# Sheet1.net
KiCad netlist of a schematic drawn in Altium Designer
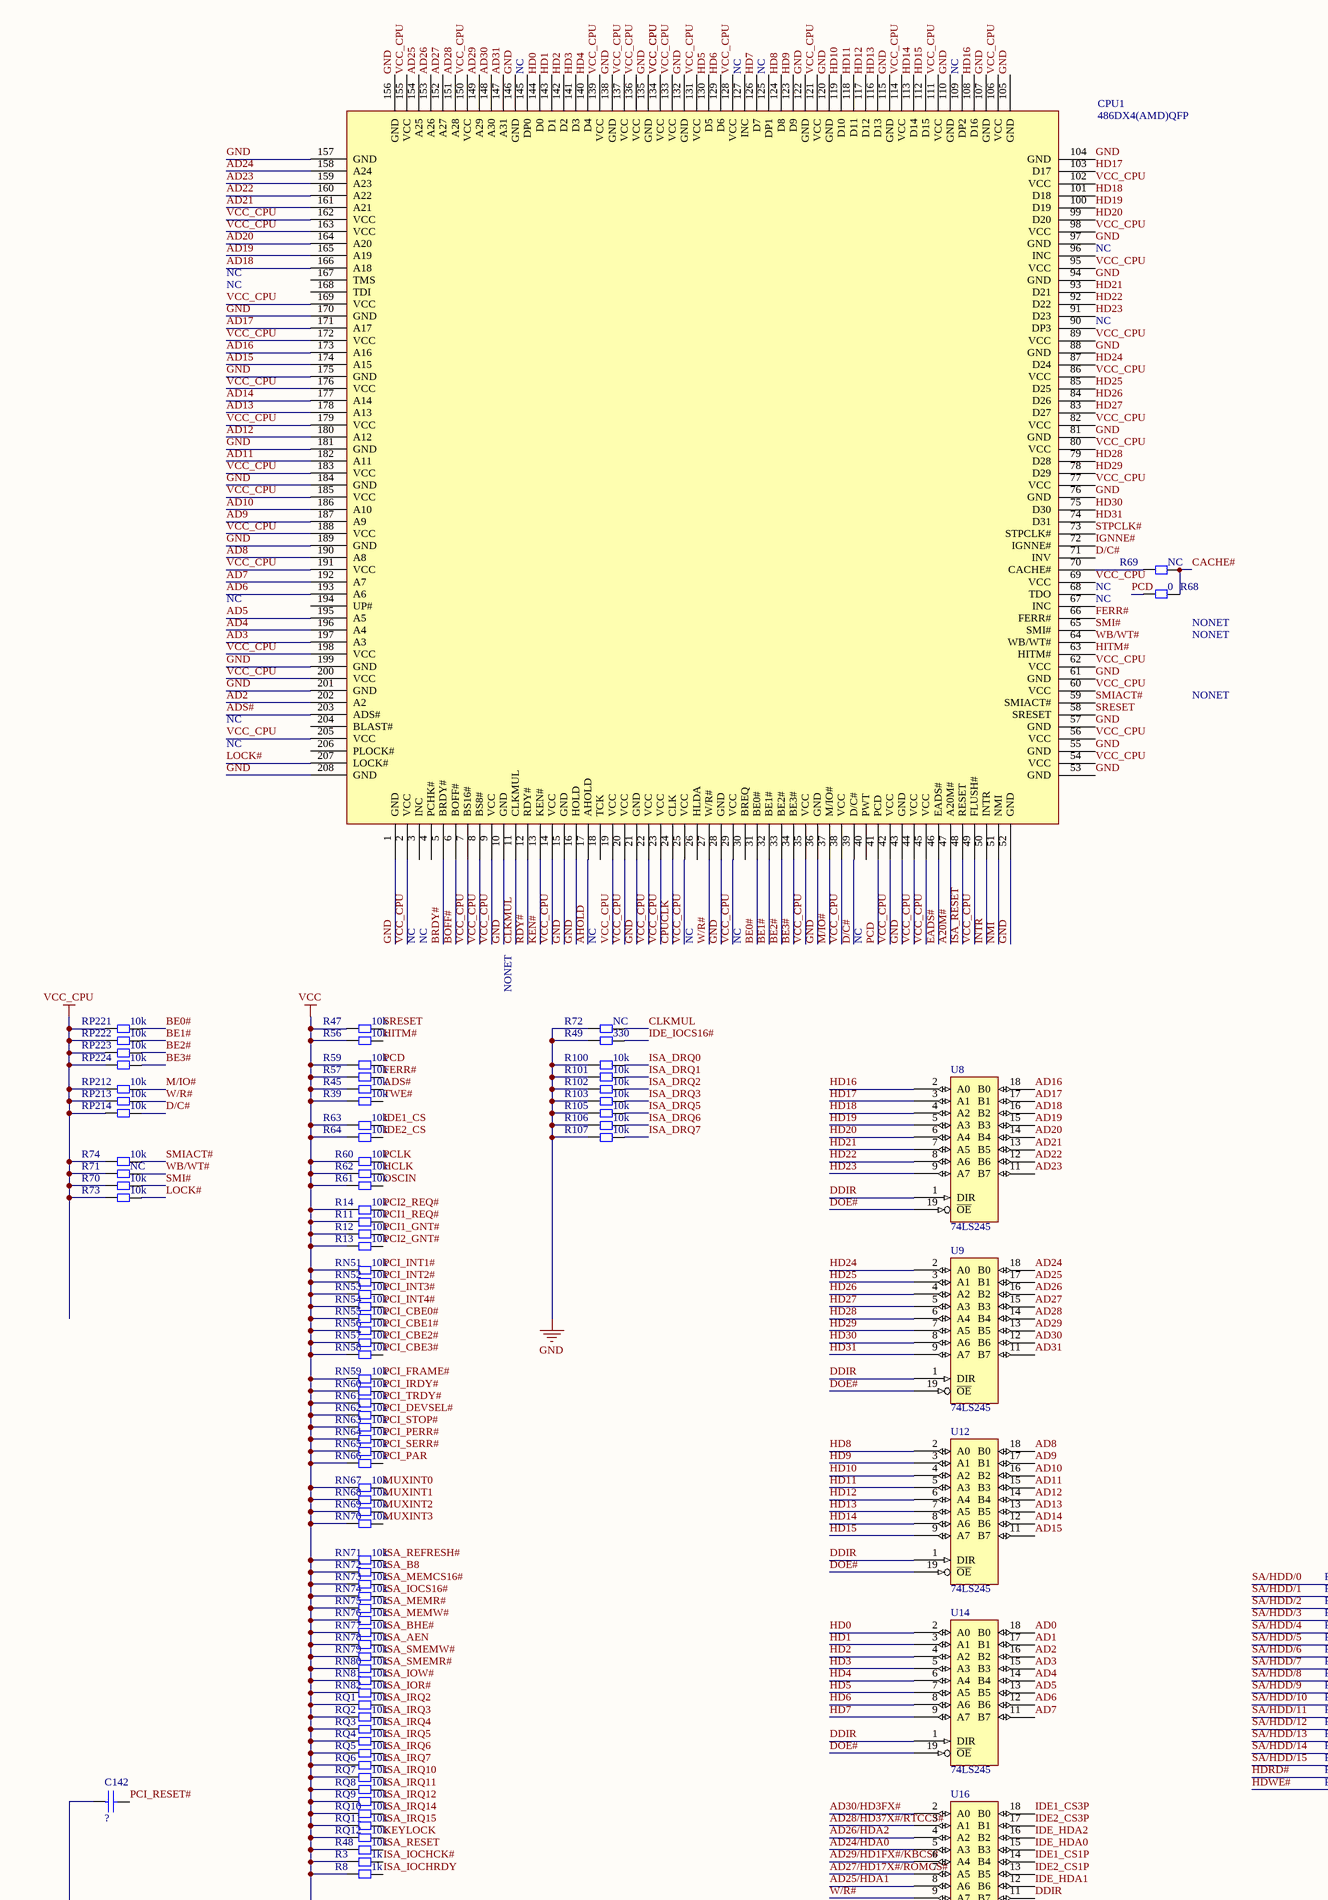
[diagram p0: Sheet1.SchDoc, top left]
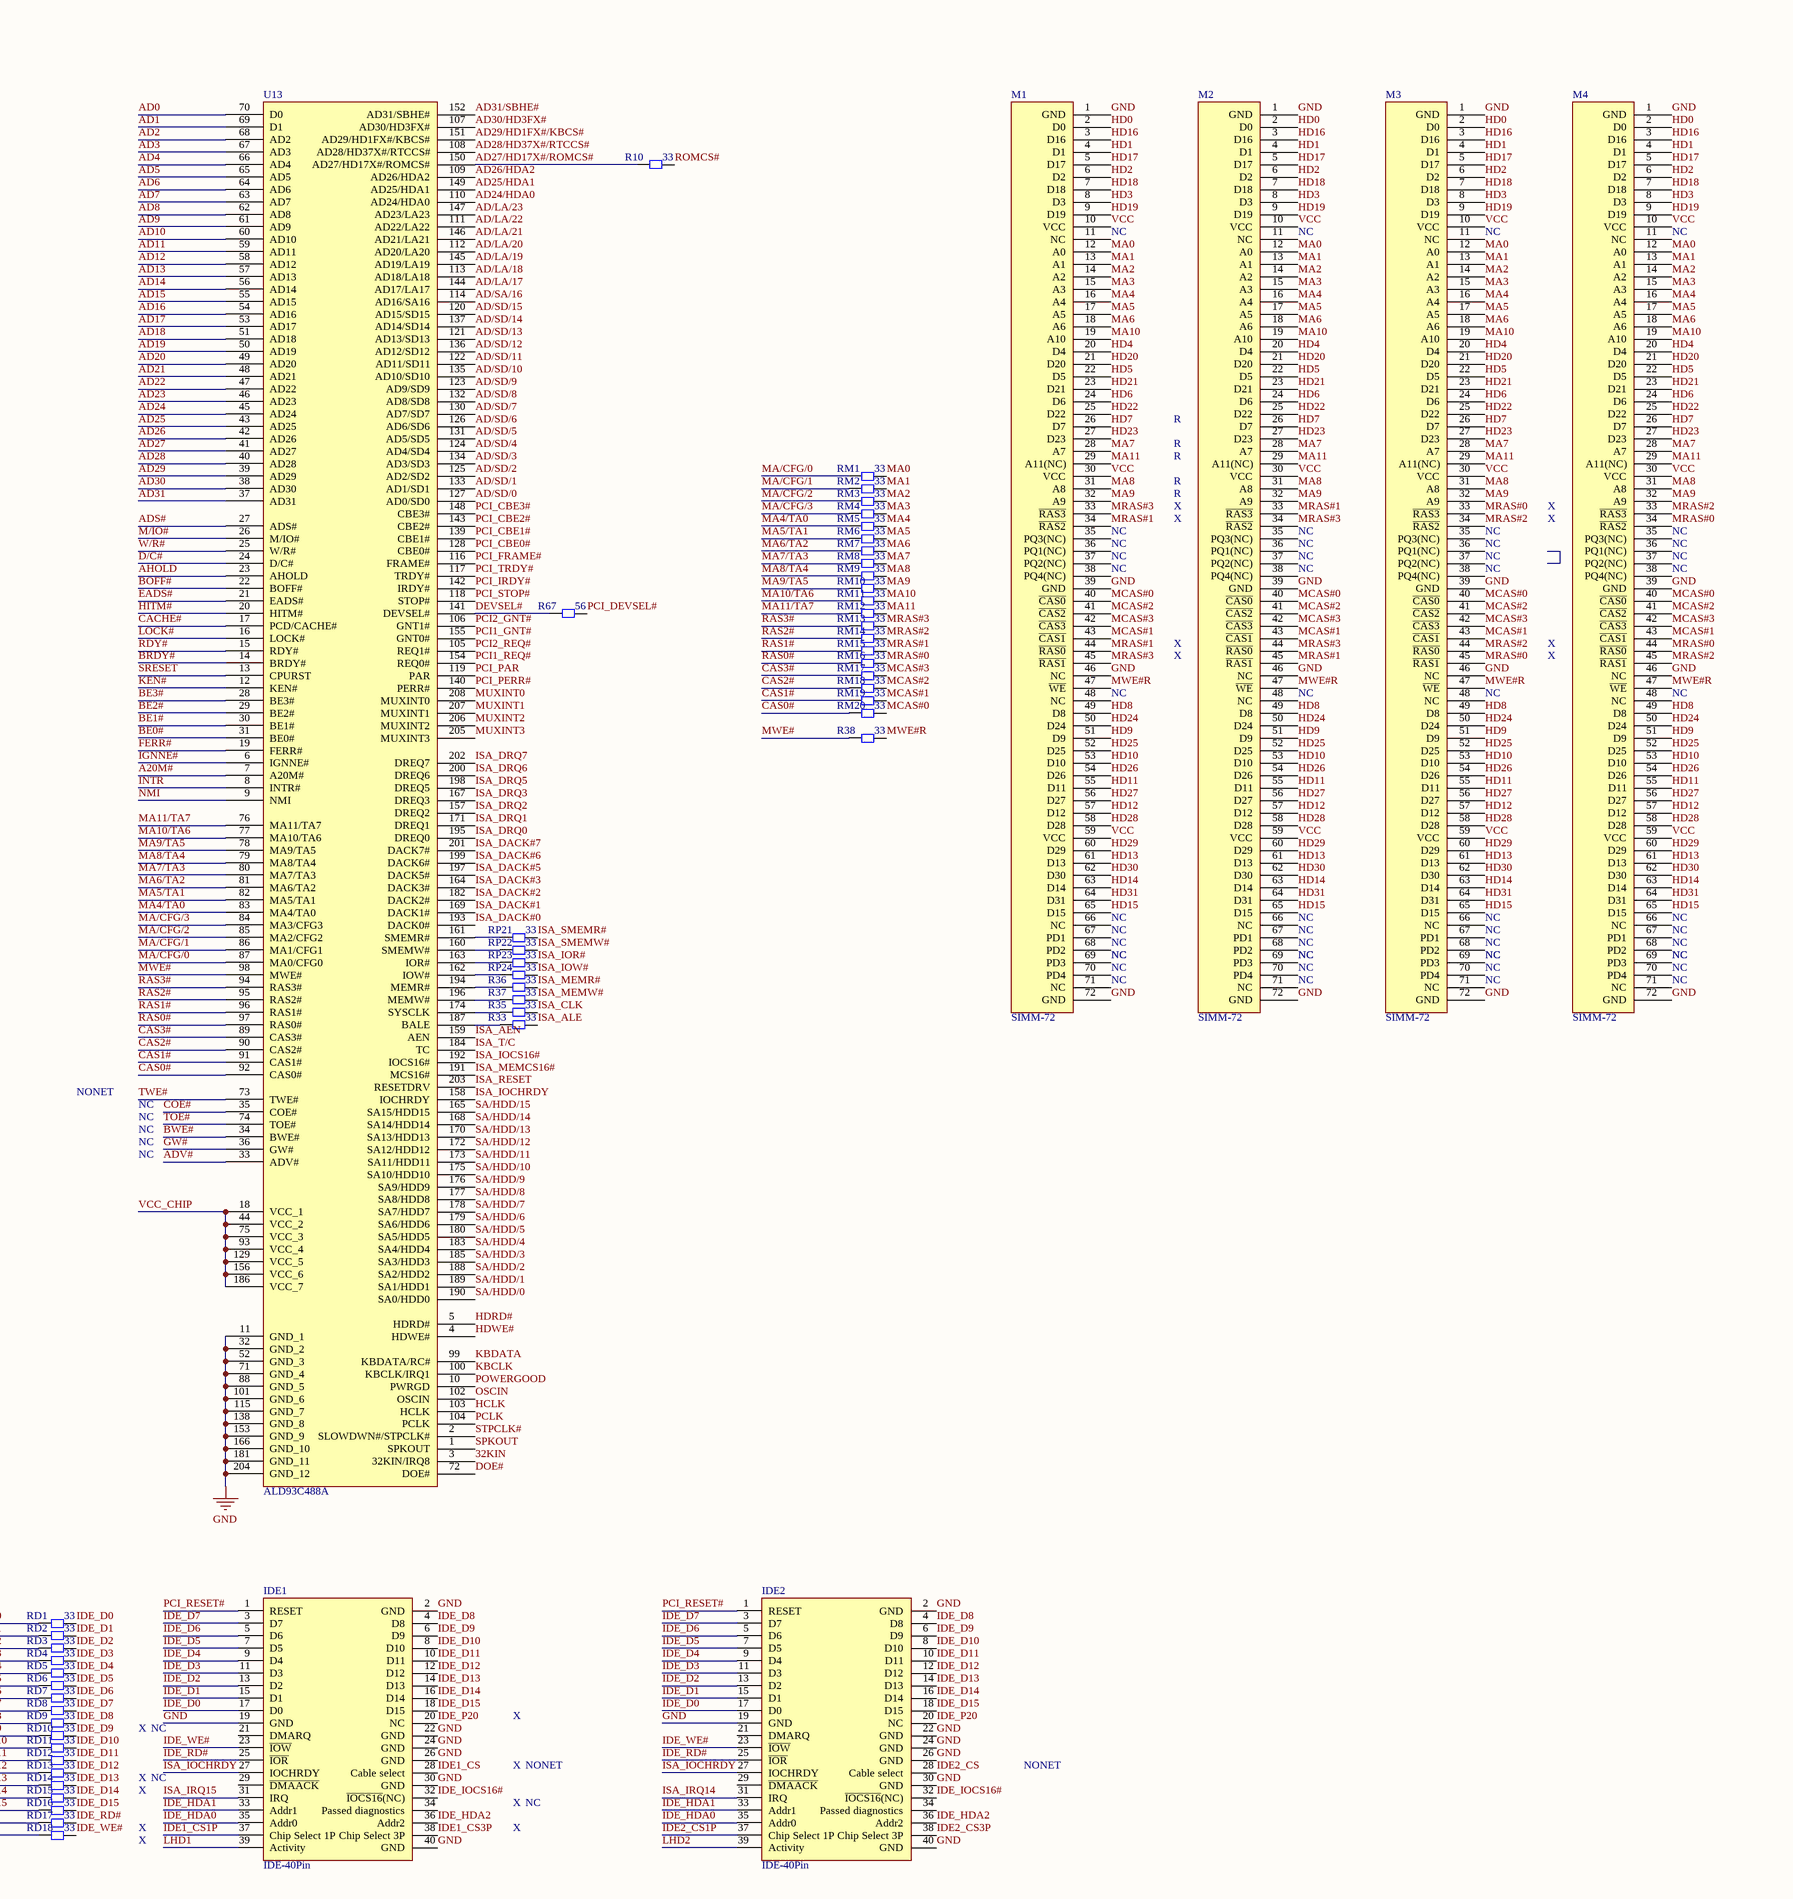
[diagram p1: Sheet1.SchDoc, top middle]
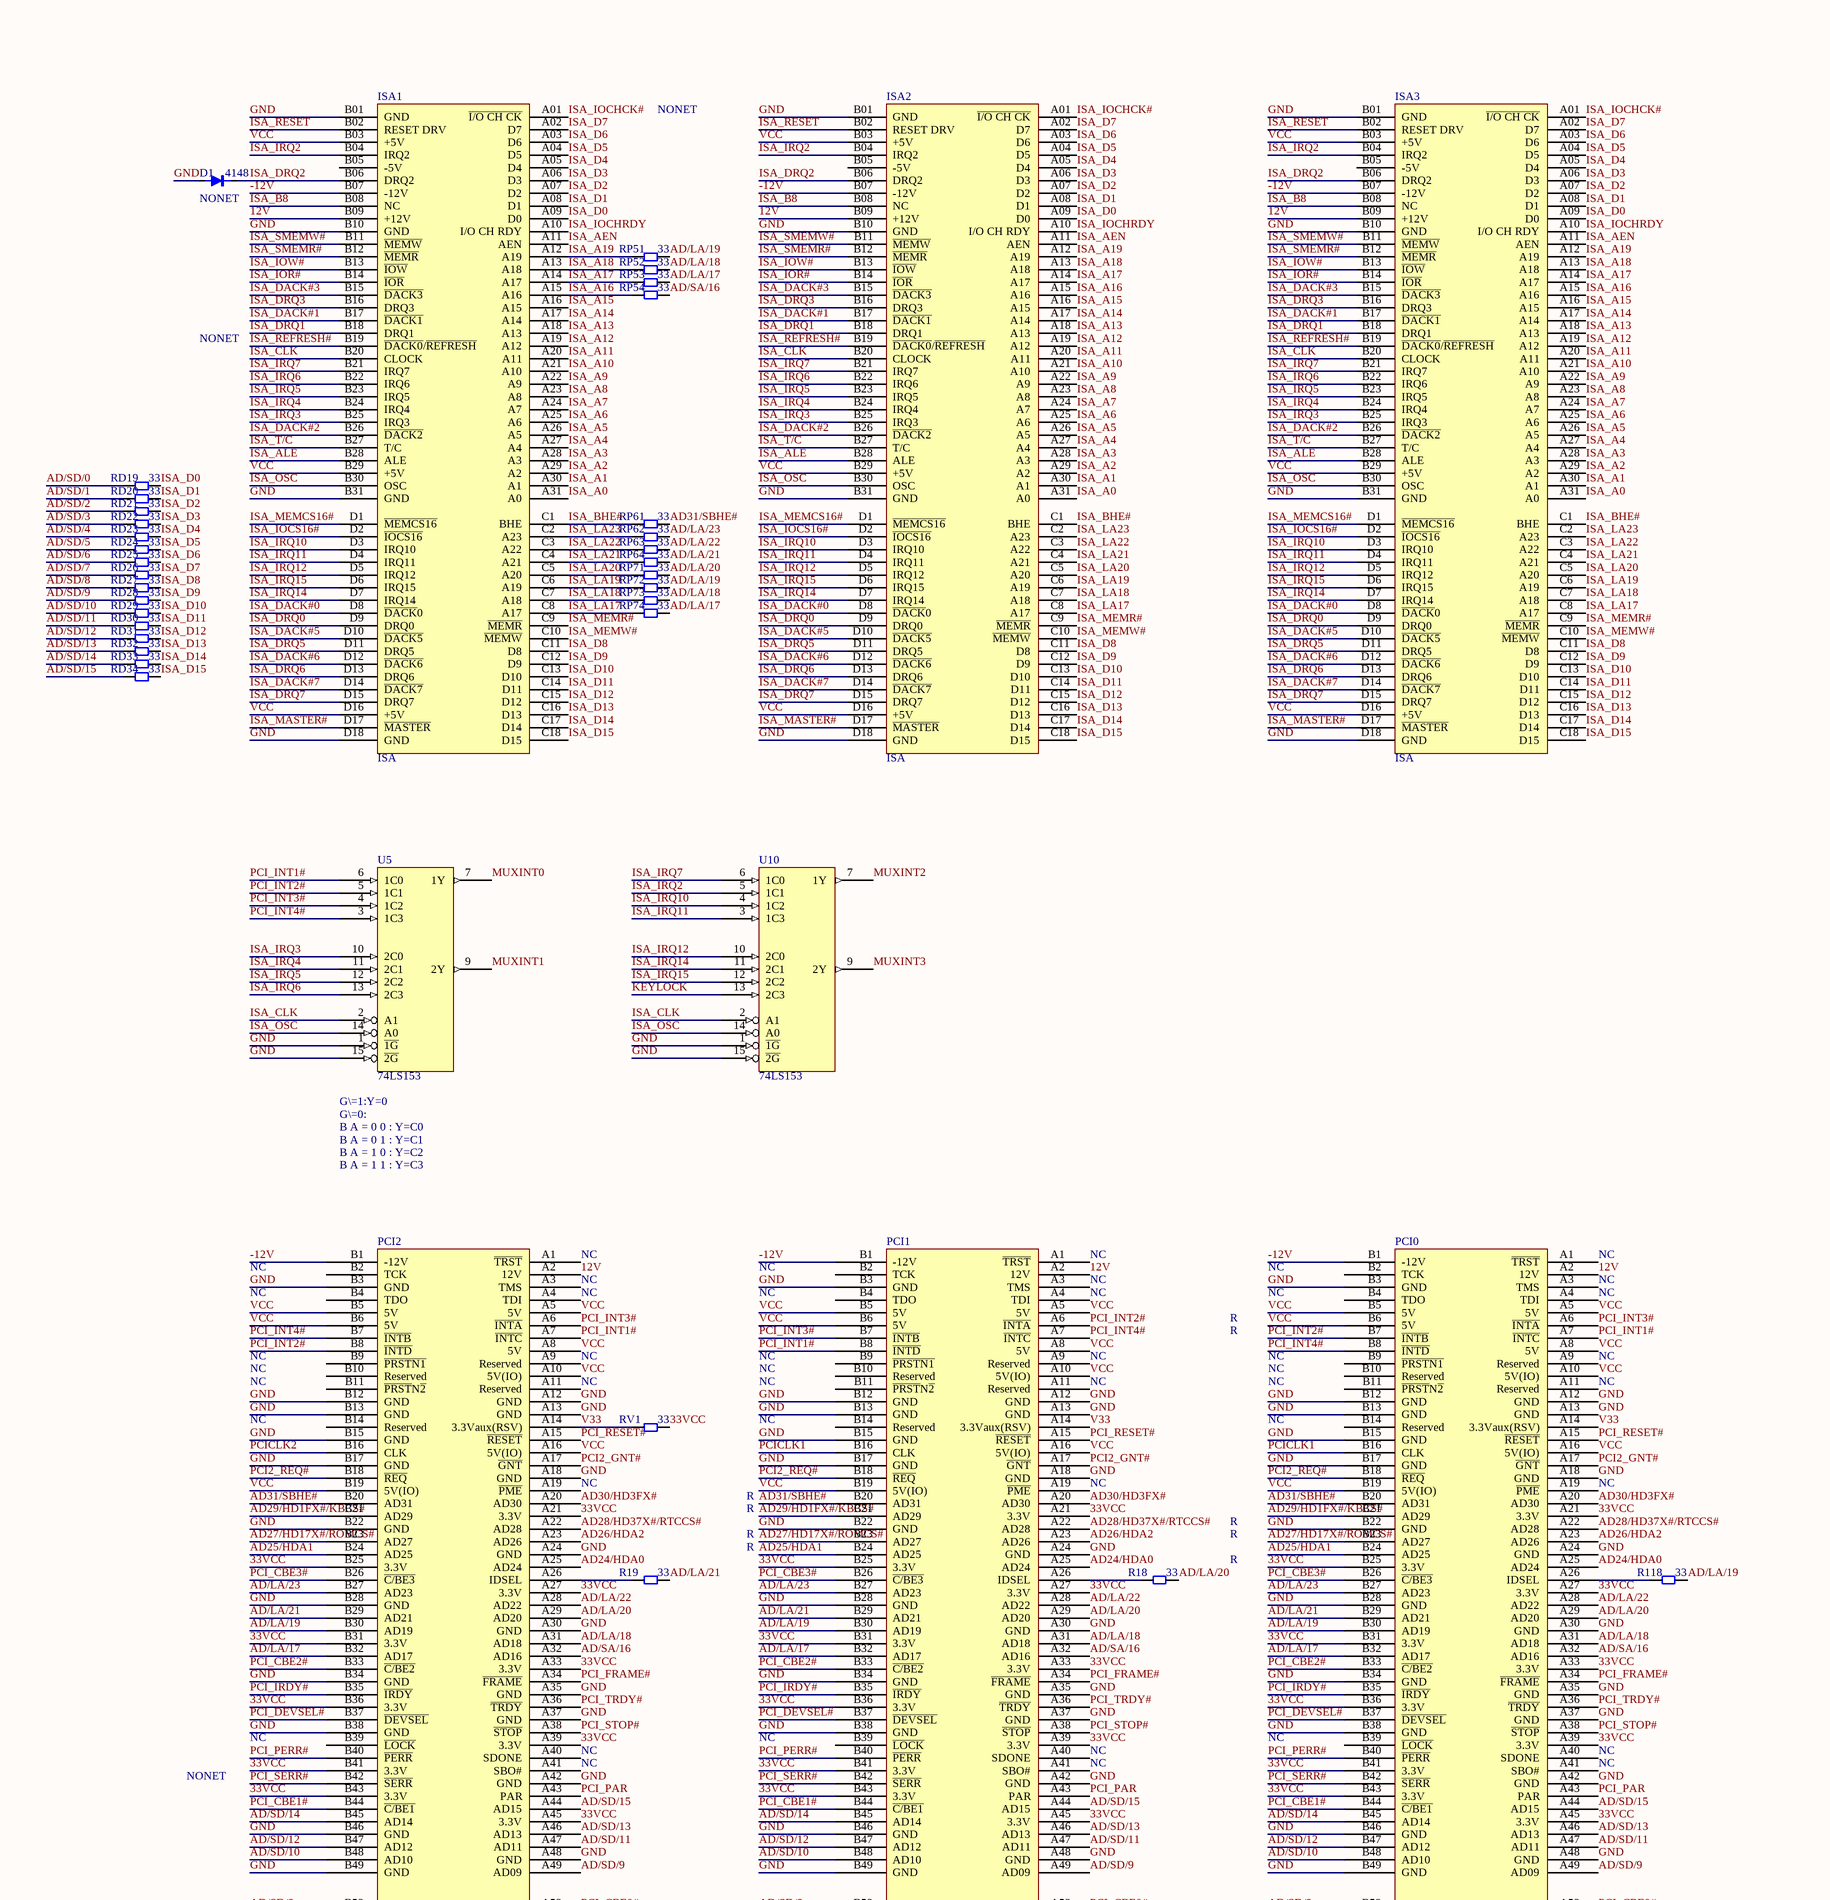
[diagram p2: Sheet1.SchDoc, top right]
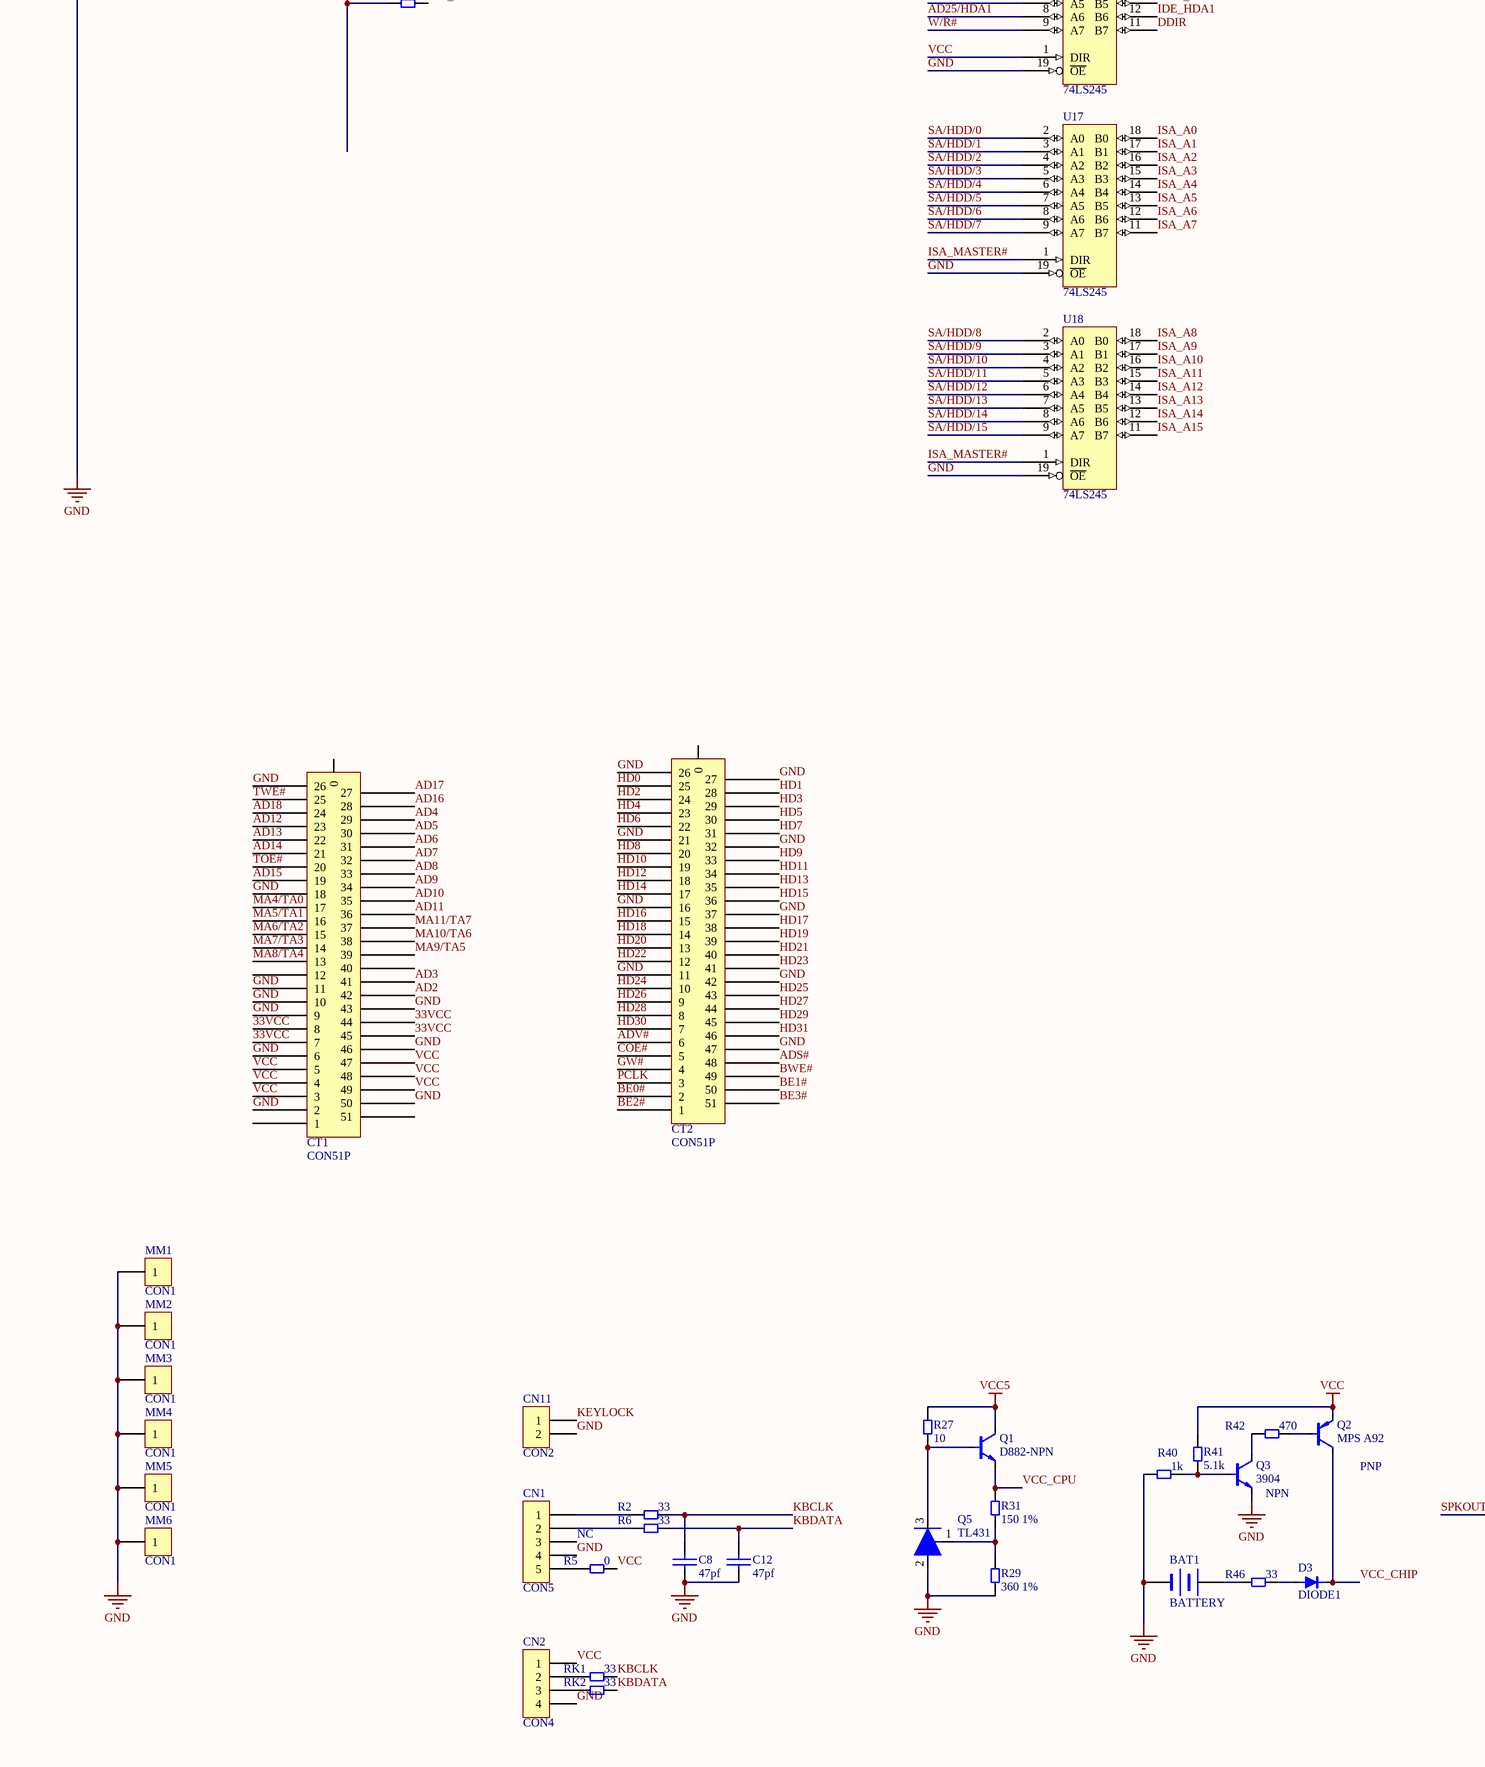
[diagram p3: Sheet1.SchDoc, bottom left]
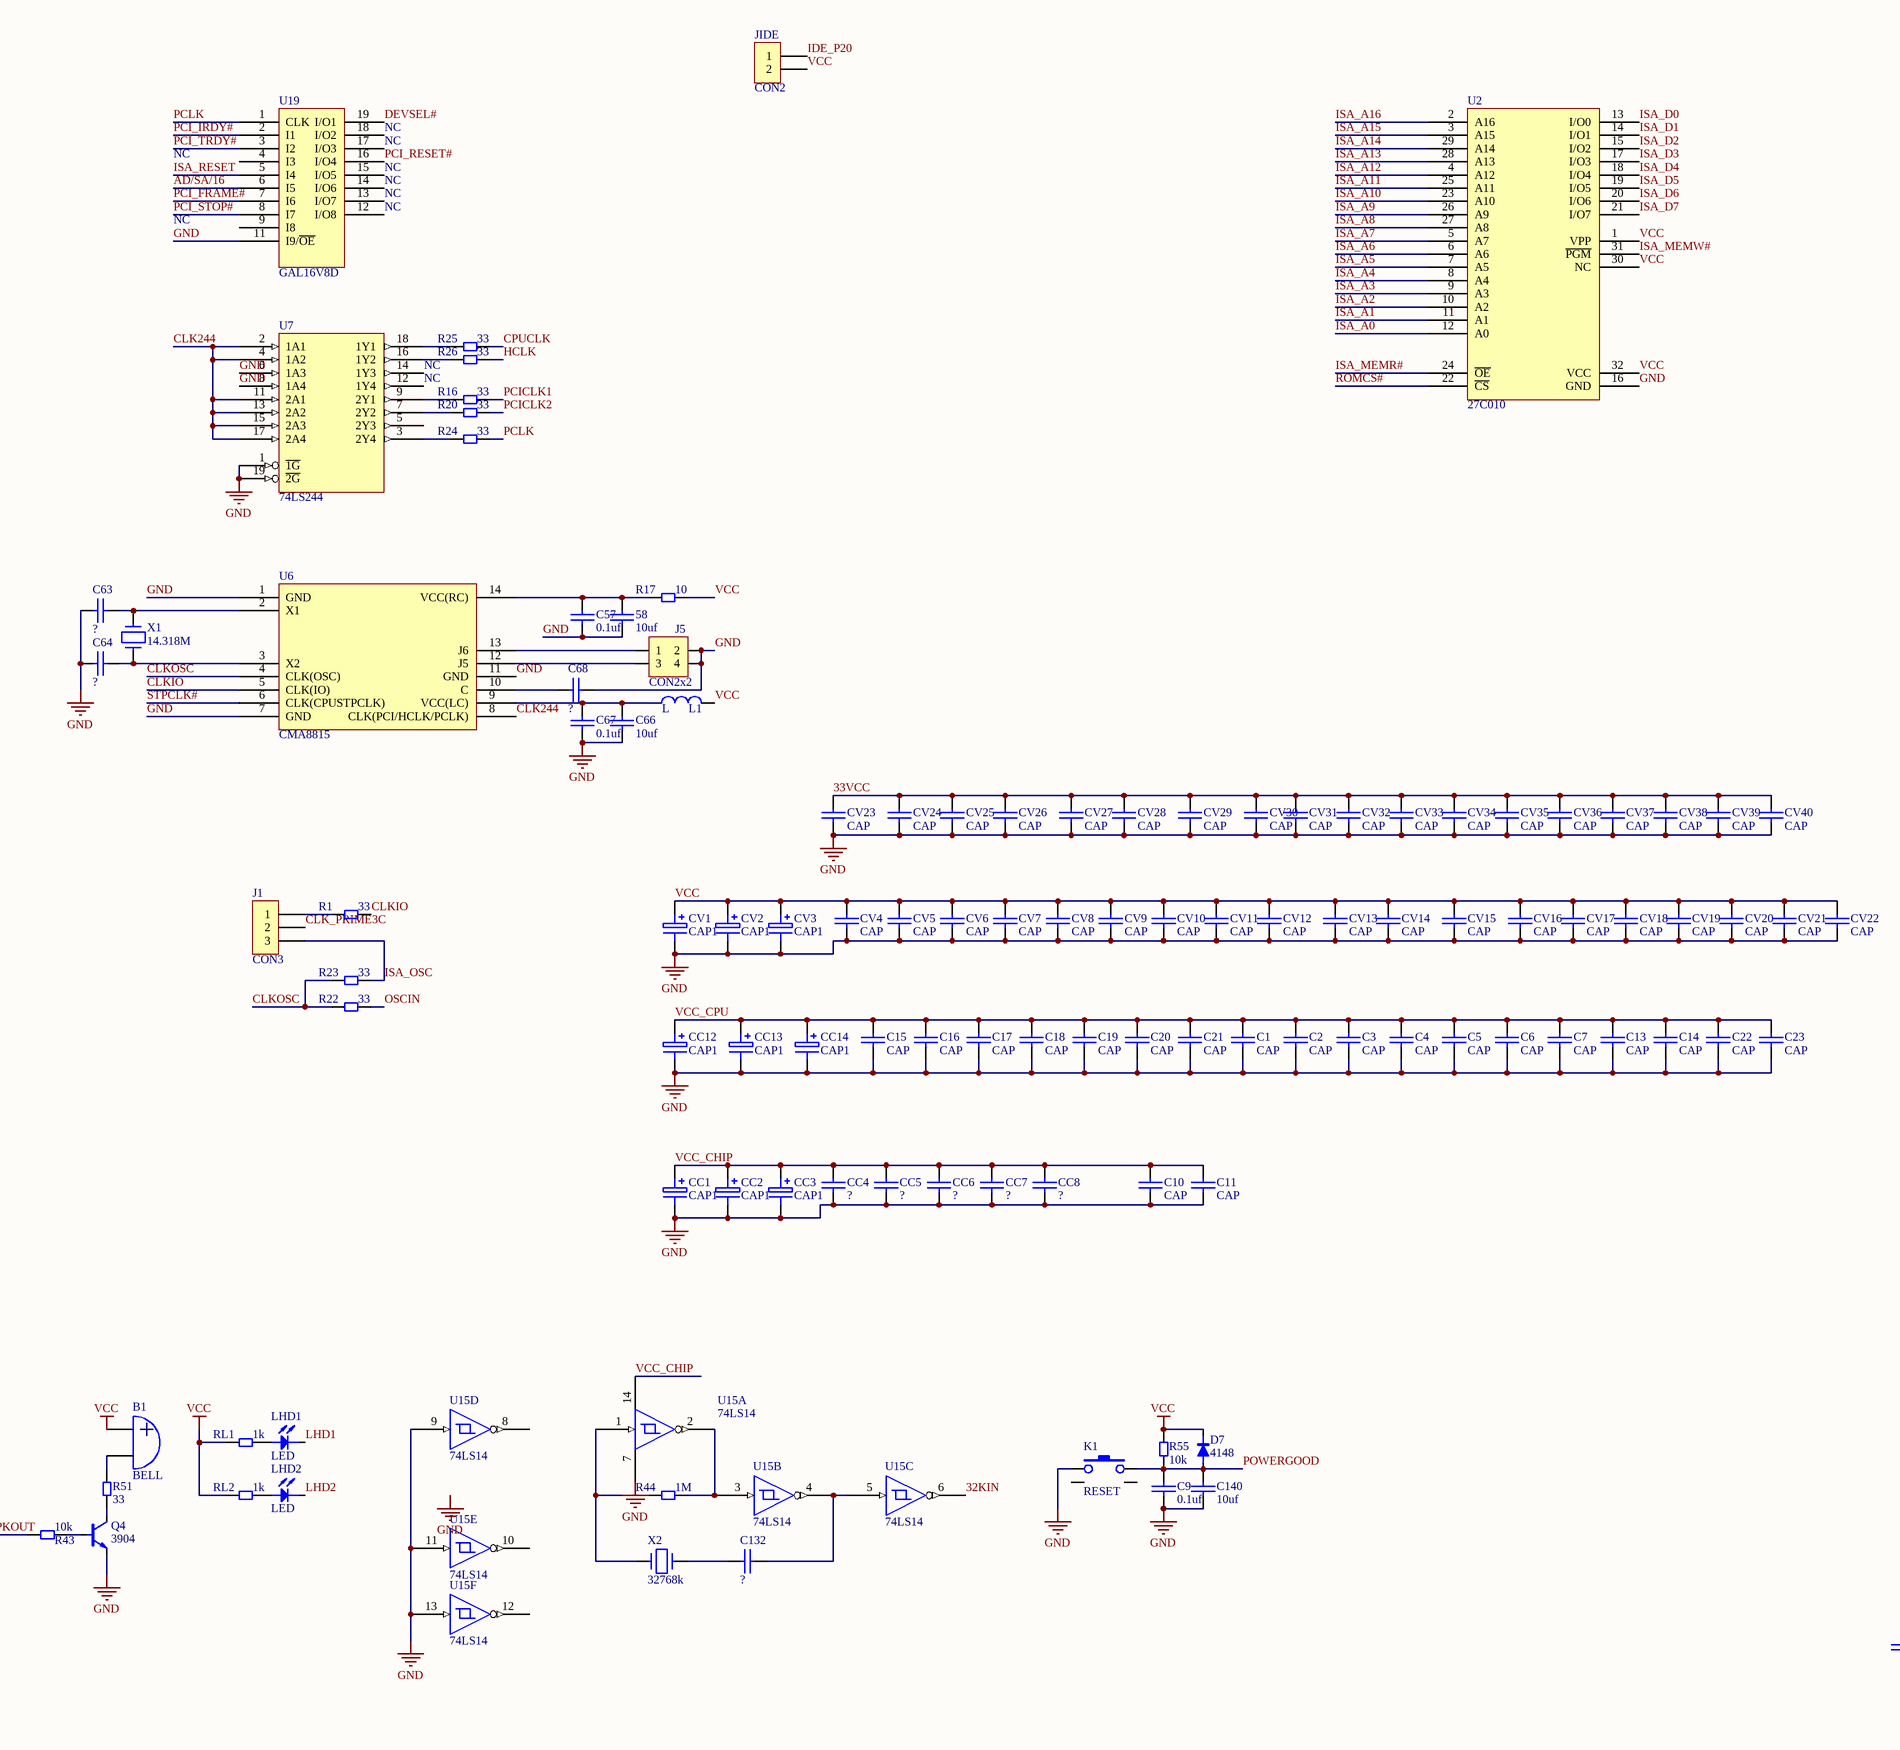
[diagram p4: Sheet1.SchDoc, bottom middle]
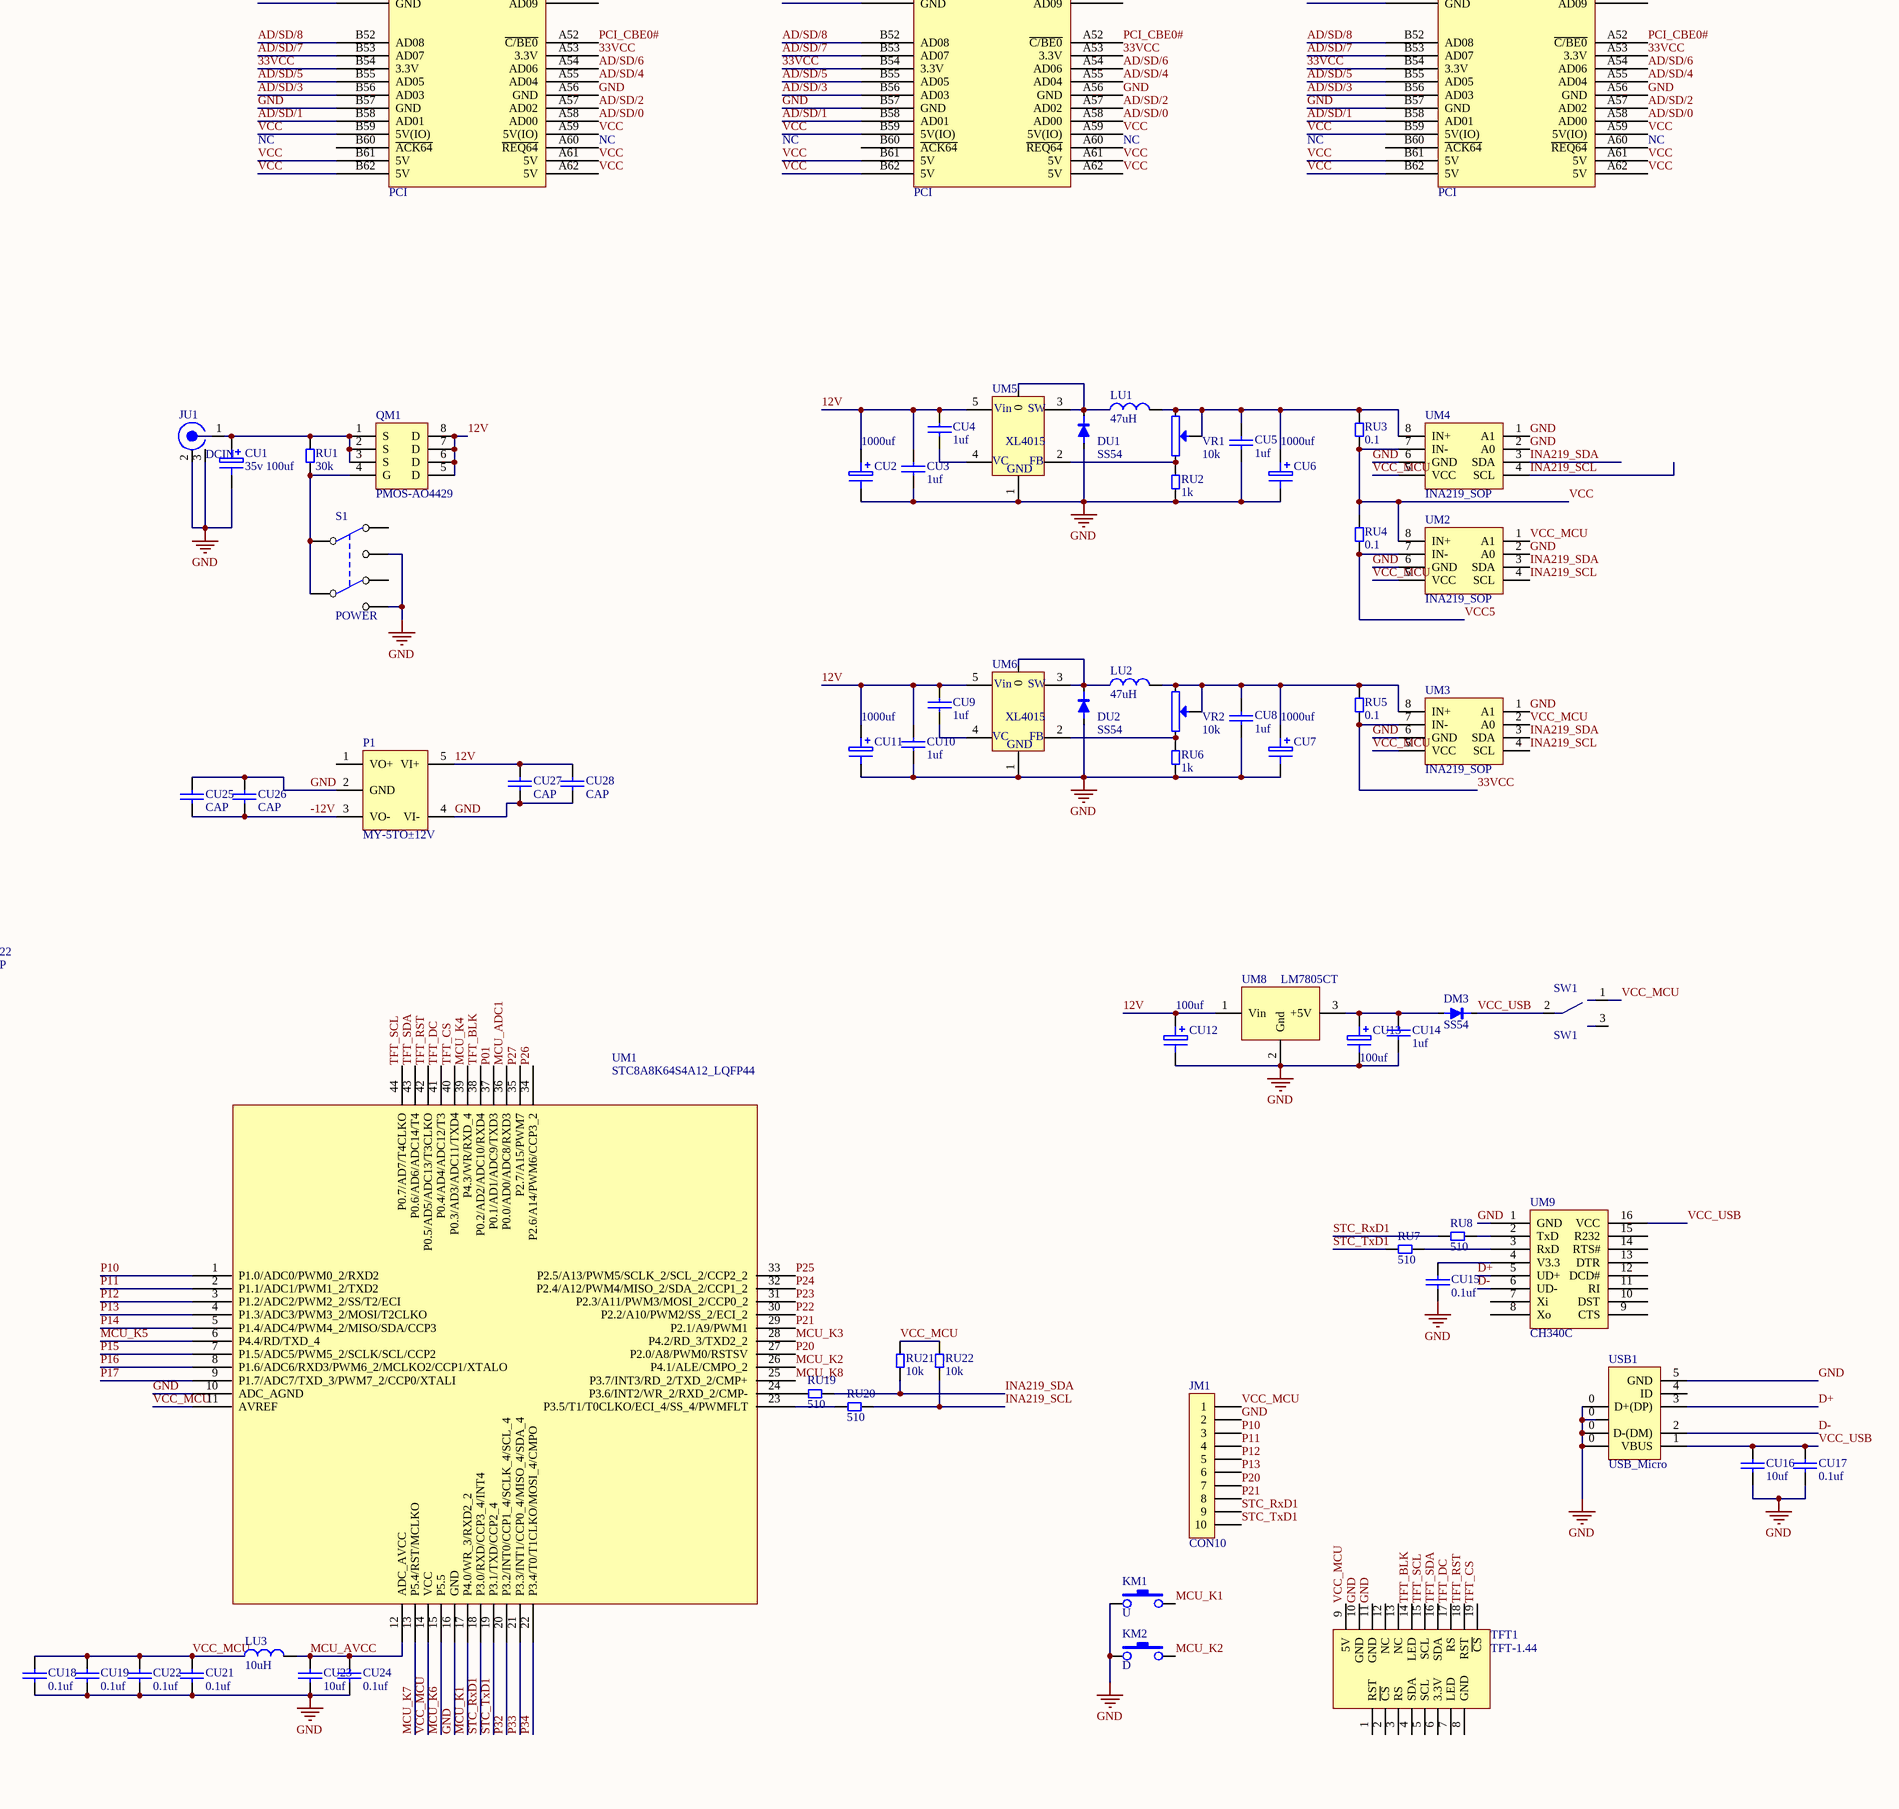
[diagram p5: Sheet1.SchDoc, bottom right]

(export (version "E")
  (design (tool "Eeschema 10.0.6"))
  (components
    (comp (ref "58") (value "10uf") (footprint "C0603") (libsource (lib "电阻电容二极管") (part "CAP")))
    (comp (ref "B1") (value "BELL") (footprint "bell") (libsource (lib "常用元件库") (part "BELL")))
    (comp (ref "BAT1") (value "BATTERY") (footprint "BATTERY3") (libsource (lib "常用元件库") (part "BATTERY")))
    (comp (ref "C1") (value "CAP") (footprint "C0603") (libsource (lib "电阻电容二极管") (part "CAP")))
    (comp (ref "C2") (value "CAP") (footprint "C0603") (libsource (lib "电阻电容二极管") (part "CAP")))
    (comp (ref "C3") (value "CAP") (footprint "C0603") (libsource (lib "电阻电容二极管") (part "CAP")))
    (comp (ref "C4") (value "CAP") (footprint "C0603") (libsource (lib "电阻电容二极管") (part "CAP")))
    (comp (ref "C5") (value "CAP") (footprint "C0603") (libsource (lib "电阻电容二极管") (part "CAP")))
    (comp (ref "C6") (value "CAP") (footprint "C0603") (libsource (lib "电阻电容二极管") (part "CAP")))
    (comp (ref "C7") (value "CAP") (footprint "C0603") (libsource (lib "电阻电容二极管") (part "CAP")))
    (comp (ref "C8") (value "47pf") (footprint "C0603") (libsource (lib "电阻电容二极管") (part "CAP")))
    (comp (ref "C9") (value "0.1uf") (footprint "C0603") (libsource (lib "电阻电容二极管") (part "CAP")))
    (comp (ref "C10") (value "CAP") (footprint "C0603") (libsource (lib "电阻电容二极管") (part "CAP")))
    (comp (ref "C11") (value "CAP") (footprint "C0603") (libsource (lib "电阻电容二极管") (part "CAP")))
    (comp (ref "C12") (value "47pf") (footprint "C0603") (libsource (lib "电阻电容二极管") (part "CAP")))
    (comp (ref "C13") (value "CAP") (footprint "C0603") (libsource (lib "电阻电容二极管") (part "CAP")))
    (comp (ref "C14") (value "CAP") (footprint "C0603") (libsource (lib "电阻电容二极管") (part "CAP")))
    (comp (ref "C15") (value "CAP") (footprint "C0603") (libsource (lib "电阻电容二极管") (part "CAP")))
    (comp (ref "C16") (value "CAP") (footprint "C0603") (libsource (lib "电阻电容二极管") (part "CAP")))
    (comp (ref "C17") (value "CAP") (footprint "C0603") (libsource (lib "电阻电容二极管") (part "CAP")))
    (comp (ref "C18") (value "CAP") (footprint "C0603") (libsource (lib "电阻电容二极管") (part "CAP")))
    (comp (ref "C19") (value "CAP") (footprint "C0603") (libsource (lib "电阻电容二极管") (part "CAP")))
    (comp (ref "C20") (value "CAP") (footprint "C0603") (libsource (lib "电阻电容二极管") (part "CAP")))
    (comp (ref "C21") (value "CAP") (footprint "C0603") (libsource (lib "电阻电容二极管") (part "CAP")))
    (comp (ref "C22") (value "CAP") (footprint "C0603") (libsource (lib "电阻电容二极管") (part "CAP")))
    (comp (ref "C23") (value "CAP") (footprint "C0603") (libsource (lib "电阻电容二极管") (part "CAP")))
    (comp (ref "C57") (value "0.1uf") (footprint "C0603") (libsource (lib "电阻电容二极管") (part "CAP")))
    (comp (ref "C63") (value "?") (footprint "C0603") (libsource (lib "电阻电容二极管") (part "CAP")))
    (comp (ref "C64") (value "?") (footprint "C0603") (libsource (lib "电阻电容二极管") (part "CAP")))
    (comp (ref "C66") (value "10uf") (footprint "C0603") (libsource (lib "电阻电容二极管") (part "CAP")))
    (comp (ref "C67") (value "0.1uf") (footprint "C0603") (libsource (lib "电阻电容二极管") (part "CAP")))
    (comp (ref "C68") (value "?") (footprint "C0603") (libsource (lib "电阻电容二极管") (part "CAP")))
    (comp (ref "C132") (value "?") (footprint "C0603") (libsource (lib "电阻电容二极管") (part "CAP")))
    (comp (ref "C140") (value "10uf") (footprint "C0603") (libsource (lib "电阻电容二极管") (part "CAP")))
    (comp (ref "C142") (value "?") (footprint "C0603") (libsource (lib "电阻电容二极管") (part "CAP")))
    (comp (ref "CC1") (value "CAP1") (footprint "RB.1/.2") (libsource (lib "电阻电容二极管") (part "CAP1")))
    (comp (ref "CC2") (value "CAP1") (footprint "RB.1/.2") (libsource (lib "电阻电容二极管") (part "CAP1")))
    (comp (ref "CC3") (value "CAP1") (footprint "RB.1/.2") (libsource (lib "电阻电容二极管") (part "CAP1")))
    (comp (ref "CC4") (value "?") (footprint "C0603") (libsource (lib "电阻电容二极管") (part "CAP")))
    (comp (ref "CC5") (value "?") (footprint "C0603") (libsource (lib "电阻电容二极管") (part "CAP")))
    (comp (ref "CC6") (value "?") (footprint "C0603") (libsource (lib "电阻电容二极管") (part "CAP")))
    (comp (ref "CC7") (value "?") (footprint "C0603") (libsource (lib "电阻电容二极管") (part "CAP")))
    (comp (ref "CC8") (value "?") (footprint "C0603") (libsource (lib "电阻电容二极管") (part "CAP")))
    (comp (ref "CC12") (value "CAP1") (footprint "RB.1/.2") (libsource (lib "电阻电容二极管") (part "CAP1")))
    (comp (ref "CC13") (value "CAP1") (footprint "RB.1/.2") (libsource (lib "电阻电容二极管") (part "CAP1")))
    (comp (ref "CC14") (value "CAP1") (footprint "RB.1/.2") (libsource (lib "电阻电容二极管") (part "CAP1")))
    (comp (ref "CN1") (value "CON5") (footprint "PS2-XT-5") (libsource (lib "常用元件库") (part "CON5")))
    (comp (ref "CN2") (value "CON4") (footprint "XH2.54-4") (libsource (lib "常用元件库") (part "CON4")))
    (comp (ref "CN11") (value "CON2") (footprint "SIP2") (libsource (lib "常用元件库") (part "CON2")))
    (comp (ref "CPU1")
      (value "486DX4(AMD)QFP")
      (footprint "QFP208")
      (libsource (lib "微机原理") (part "486DX4(AMD)QFP"))
    )
    (comp (ref "CT1") (value "CON51P") (footprint "BTB1.0-51P") (libsource (lib "常用元件库") (part "CON51P")))
    (comp (ref "CT2") (value "CON51P") (footprint "BTB1.0-51P") (libsource (lib "常用元件库") (part "CON51P")))
    (comp (ref "CU1") (value "35v 100uf") (footprint "CD6") (libsource (lib "电阻电容二极管") (part "CAP1")))
    (comp (ref "CU2") (value "1000uf") (footprint "SMD-EC-F10") (libsource (lib "电阻电容二极管") (part "CAP1")))
    (comp (ref "CU3") (value "1uf") (footprint "C0603") (libsource (lib "电阻电容二极管") (part "CAP")))
    (comp (ref "CU4") (value "1uf") (footprint "C0603") (libsource (lib "电阻电容二极管") (part "CAP")))
    (comp (ref "CU5") (value "1uf") (footprint "C0603") (libsource (lib "电阻电容二极管") (part "CAP")))
    (comp (ref "CU6") (value "1000uf") (footprint "SMD-EC-F10") (libsource (lib "电阻电容二极管") (part "CAP1")))
    (comp (ref "CU7") (value "1000uf") (footprint "SMD-EC-F10") (libsource (lib "电阻电容二极管") (part "CAP1")))
    (comp (ref "CU8") (value "1uf") (footprint "C0603") (libsource (lib "电阻电容二极管") (part "CAP")))
    (comp (ref "CU9") (value "1uf") (footprint "C0603") (libsource (lib "电阻电容二极管") (part "CAP")))
    (comp (ref "CU10") (value "1uf") (footprint "C0603") (libsource (lib "电阻电容二极管") (part "CAP")))
    (comp (ref "CU11") (value "1000uf") (footprint "SMD-EC-F10") (libsource (lib "电阻电容二极管") (part "CAP1")))
    (comp (ref "CU12") (value "100uf") (footprint "SMD-EC-F6.3") (libsource (lib "电阻电容二极管") (part "CAP1")))
    (comp (ref "CU13") (value "100uf") (footprint "SMD-EC-F6.3") (libsource (lib "电阻电容二极管") (part "CAP1")))
    (comp (ref "CU14") (value "1uf") (footprint "C0603") (libsource (lib "电阻电容二极管") (part "CAP")))
    (comp (ref "CU15") (value "0.1uf") (footprint "C0603") (libsource (lib "电阻电容二极管") (part "CAP")))
    (comp (ref "CU16") (value "10uf") (footprint "C0603") (libsource (lib "电阻电容二极管") (part "CAP")))
    (comp (ref "CU17") (value "0.1uf") (footprint "C0603") (libsource (lib "电阻电容二极管") (part "CAP")))
    (comp (ref "CU18") (value "0.1uf") (footprint "C0603") (libsource (lib "电阻电容二极管") (part "CAP")))
    (comp (ref "CU19") (value "0.1uf") (footprint "C0603") (libsource (lib "电阻电容二极管") (part "CAP")))
    (comp (ref "CU21") (value "0.1uf") (footprint "C0603") (libsource (lib "电阻电容二极管") (part "CAP")))
    (comp (ref "CU22") (value "0.1uf") (footprint "C0603") (libsource (lib "电阻电容二极管") (part "CAP")))
    (comp (ref "CU23") (value "10uf") (footprint "C0603") (libsource (lib "电阻电容二极管") (part "CAP")))
    (comp (ref "CU24") (value "0.1uf") (footprint "C0603") (libsource (lib "电阻电容二极管") (part "CAP")))
    (comp (ref "CU25") (value "CAP") (footprint "C0603") (libsource (lib "电阻电容二极管") (part "CAP")))
    (comp (ref "CU26") (value "CAP") (footprint "C0603") (libsource (lib "电阻电容二极管") (part "CAP")))
    (comp (ref "CU27") (value "CAP") (footprint "C0603") (libsource (lib "电阻电容二极管") (part "CAP")))
    (comp (ref "CU28") (value "CAP") (footprint "C0603") (libsource (lib "电阻电容二极管") (part "CAP")))
    (comp (ref "CV1") (value "CAP1") (footprint "RB.1/.2") (libsource (lib "电阻电容二极管") (part "CAP1")))
    (comp (ref "CV2") (value "CAP1") (footprint "RB.1/.2") (libsource (lib "电阻电容二极管") (part "CAP1")))
    (comp (ref "CV3") (value "CAP1") (footprint "RB.1/.2") (libsource (lib "电阻电容二极管") (part "CAP1")))
    (comp (ref "CV4") (value "CAP") (footprint "C0603") (libsource (lib "电阻电容二极管") (part "CAP")))
    (comp (ref "CV5") (value "CAP") (footprint "C0603") (libsource (lib "电阻电容二极管") (part "CAP")))
    (comp (ref "CV6") (value "CAP") (footprint "C0603") (libsource (lib "电阻电容二极管") (part "CAP")))
    (comp (ref "CV7") (value "CAP") (footprint "C0603") (libsource (lib "电阻电容二极管") (part "CAP")))
    (comp (ref "CV8") (value "CAP") (footprint "C0603") (libsource (lib "电阻电容二极管") (part "CAP")))
    (comp (ref "CV9") (value "CAP") (footprint "C0603") (libsource (lib "电阻电容二极管") (part "CAP")))
    (comp (ref "CV10") (value "CAP") (footprint "C0603") (libsource (lib "电阻电容二极管") (part "CAP")))
    (comp (ref "CV11") (value "CAP") (footprint "C0603") (libsource (lib "电阻电容二极管") (part "CAP")))
    (comp (ref "CV12") (value "CAP") (footprint "C0603") (libsource (lib "电阻电容二极管") (part "CAP")))
    (comp (ref "CV13") (value "CAP") (footprint "C0603") (libsource (lib "电阻电容二极管") (part "CAP")))
    (comp (ref "CV14") (value "CAP") (footprint "C0603") (libsource (lib "电阻电容二极管") (part "CAP")))
    (comp (ref "CV15") (value "CAP") (footprint "C0603") (libsource (lib "电阻电容二极管") (part "CAP")))
    (comp (ref "CV16") (value "CAP") (footprint "C0603") (libsource (lib "电阻电容二极管") (part "CAP")))
    (comp (ref "CV17") (value "CAP") (footprint "C0603") (libsource (lib "电阻电容二极管") (part "CAP")))
    (comp (ref "CV18") (value "CAP") (footprint "C0603") (libsource (lib "电阻电容二极管") (part "CAP")))
    (comp (ref "CV19") (value "CAP") (footprint "C0603") (libsource (lib "电阻电容二极管") (part "CAP")))
    (comp (ref "CV20") (value "CAP") (footprint "C0603") (libsource (lib "电阻电容二极管") (part "CAP")))
    (comp (ref "CV21") (value "CAP") (footprint "C0603") (libsource (lib "电阻电容二极管") (part "CAP")))
    (comp (ref "CV22") (value "CAP") (footprint "C0603") (libsource (lib "电阻电容二极管") (part "CAP")))
    (comp (ref "CV23") (value "CAP") (footprint "C0603") (libsource (lib "电阻电容二极管") (part "CAP")))
    (comp (ref "CV24") (value "CAP") (footprint "C0603") (libsource (lib "电阻电容二极管") (part "CAP")))
    (comp (ref "CV25") (value "CAP") (footprint "C0603") (libsource (lib "电阻电容二极管") (part "CAP")))
    (comp (ref "CV26") (value "CAP") (footprint "C0603") (libsource (lib "电阻电容二极管") (part "CAP")))
    (comp (ref "CV27") (value "CAP") (footprint "C0603") (libsource (lib "电阻电容二极管") (part "CAP")))
    (comp (ref "CV28") (value "CAP") (footprint "C0603") (libsource (lib "电阻电容二极管") (part "CAP")))
    (comp (ref "CV29") (value "CAP") (footprint "C0603") (libsource (lib "电阻电容二极管") (part "CAP")))
    (comp (ref "CV30") (value "CAP") (footprint "C0603") (libsource (lib "电阻电容二极管") (part "CAP")))
    (comp (ref "CV31") (value "CAP") (footprint "C0603") (libsource (lib "电阻电容二极管") (part "CAP")))
    (comp (ref "CV32") (value "CAP") (footprint "C0603") (libsource (lib "电阻电容二极管") (part "CAP")))
    (comp (ref "CV33") (value "CAP") (footprint "C0603") (libsource (lib "电阻电容二极管") (part "CAP")))
    (comp (ref "CV34") (value "CAP") (footprint "C0603") (libsource (lib "电阻电容二极管") (part "CAP")))
    (comp (ref "CV35") (value "CAP") (footprint "C0603") (libsource (lib "电阻电容二极管") (part "CAP")))
    (comp (ref "CV36") (value "CAP") (footprint "C0603") (libsource (lib "电阻电容二极管") (part "CAP")))
    (comp (ref "CV37") (value "CAP") (footprint "C0603") (libsource (lib "电阻电容二极管") (part "CAP")))
    (comp (ref "CV38") (value "CAP") (footprint "C0603") (libsource (lib "电阻电容二极管") (part "CAP")))
    (comp (ref "CV39") (value "CAP") (footprint "C0603") (libsource (lib "电阻电容二极管") (part "CAP")))
    (comp (ref "CV40") (value "CAP") (footprint "C0603") (libsource (lib "电阻电容二极管") (part "CAP")))
    (comp (ref "D1") (value "4148") (footprint "DO-214A(SMA)") (libsource (lib "常用元件库") (part "DIODE1")))
    (comp (ref "D3") (value "DIODE1") (footprint "DO-214A(SMA)") (libsource (lib "常用元件库") (part "DIODE1")))
    (comp (ref "D7") (value "4148") (footprint "DO-214A(SMA)") (libsource (lib "常用元件库") (part "DIODE1")))
    (comp (ref "DM3") (value "SS54") (footprint "DO-214A(SMA)") (libsource (lib "电阻电容二极管") (part "DIODE1")))
    (comp (ref "DU1") (value "SS54") (footprint "DO-214A(SMA)") (libsource (lib "电阻电容二极管") (part "DIODE1")))
    (comp (ref "DU2") (value "SS54") (footprint "DO-214A(SMA)") (libsource (lib "电阻电容二极管") (part "DIODE1")))
    (comp (ref "IDE1") (value "IDE-40Pin") (footprint "MY-IDE40") (libsource (lib "微机原理") (part "IDE-40Pin")))
    (comp (ref "IDE2") (value "IDE-40Pin") (footprint "MY-IDE40") (libsource (lib "微机原理") (part "IDE-40Pin")))
    (comp (ref "ISA1") (value "ISA") (footprint "MY-ISA16-98") (libsource (lib "微机原理") (part "ISA")))
    (comp (ref "ISA2") (value "ISA") (footprint "MY-ISA16-98") (libsource (lib "微机原理") (part "ISA")))
    (comp (ref "ISA3") (value "ISA") (footprint "MY-ISA16-98") (libsource (lib "微机原理") (part "ISA")))
    (comp (ref "J1") (value "CON3") (footprint "SIP3") (libsource (lib "常用元件库") (part "CON3")))
    (comp (ref "J5") (value "CON2x2") (footprint "SIP2x2(2.54)") (libsource (lib "常用元件库") (part "CON2x2")))
    (comp (ref "JIDE") (value "CON2") (footprint "SIP2") (libsource (lib "常用元件库") (part "CON2")))
    (comp (ref "JM1") (value "CON10") (footprint "sip10") (libsource (lib "常用元件库") (part "CON10")))
    (comp (ref "JU1")
      (value "DCIN")
      (footprint "DC5.5-2.5")
      (description "Connector")
      (libsource (lib "插件") (part "DCIN"))
    )
    (comp (ref "K1") (value "RESET") (footprint "AN66") (libsource (lib "常用元件库") (part "KEY4")))
    (comp (ref "KM1") (value "U") (footprint "AN66") (libsource (lib "常用元件库") (part "KEY")))
    (comp (ref "KM2") (value "D") (footprint "AN66") (libsource (lib "常用元件库") (part "KEY")))
    (comp (ref "L1") (value "L") (footprint "L0603") (libsource (lib "常用元件库") (part "L")))
    (comp (ref "LHD1") (value "LED") (footprint "LED0603") (libsource (lib "电阻电容二极管") (part "LED")))
    (comp (ref "LHD2") (value "LED") (footprint "LED0603") (libsource (lib "电阻电容二极管") (part "LED")))
    (comp (ref "LU1") (value "47uH") (footprint "L1260") (libsource (lib "常用元件库") (part "L")))
    (comp (ref "LU2") (value "47uH") (footprint "L1260") (libsource (lib "常用元件库") (part "L")))
    (comp (ref "LU3") (value "10uH") (footprint "L0805") (libsource (lib "常用元件库") (part "L")))
    (comp (ref "M1") (value "SIMM-72") (footprint "MY-SIMM72") (libsource (lib "微机原理") (part "SIMM-72")))
    (comp (ref "M2") (value "SIMM-72") (footprint "MY-SIMM72") (libsource (lib "微机原理") (part "SIMM-72")))
    (comp (ref "M3") (value "SIMM-72") (footprint "MY-SIMM72") (libsource (lib "微机原理") (part "SIMM-72")))
    (comp (ref "M4") (value "SIMM-72") (footprint "MY-SIMM72") (libsource (lib "微机原理") (part "SIMM-72")))
    (comp (ref "MM1") (value "CON1") (footprint "M3") (libsource (lib "常用元件库") (part "CON1")))
    (comp (ref "MM2") (value "CON1") (footprint "M3") (libsource (lib "常用元件库") (part "CON1")))
    (comp (ref "MM3") (value "CON1") (footprint "M3") (libsource (lib "常用元件库") (part "CON1")))
    (comp (ref "MM4") (value "CON1") (footprint "M3") (libsource (lib "常用元件库") (part "CON1")))
    (comp (ref "MM5") (value "CON1") (footprint "M3") (libsource (lib "常用元件库") (part "CON1")))
    (comp (ref "MM6") (value "CON1") (footprint "M3") (libsource (lib "常用元件库") (part "CON1")))
    (comp (ref "P1")
      (value "MY-5TO±12V")
      (footprint "MY-5TO±12")
      (libsource (lib "常用元件库") (part "MY-5TO±12V"))
    )
    (comp (ref "PCI0") (value "PCI") (footprint "PCI") (libsource (lib "微机原理") (part "PCI")))
    (comp (ref "PCI1") (value "PCI") (footprint "PCI") (libsource (lib "微机原理") (part "PCI")))
    (comp (ref "PCI2") (value "PCI") (footprint "PCI") (libsource (lib "微机原理") (part "PCI")))
    (comp (ref "Q1") (value "D882-NPN") (footprint "TO-126A") (libsource (lib "微机原理") (part "D882-NPN")))
    (comp (ref "Q2") (value "MPS A92") (footprint "TO-92") (libsource (lib "电阻电容二极管") (part "PNP")))
    (comp (ref "Q3") (value "3904") (footprint "SOT23") (libsource (lib "电阻电容二极管") (part "NPN")))
    (comp (ref "Q4") (value "3904") (footprint "SOT23") (libsource (lib "电阻电容二极管") (part "NPN")))
    (comp (ref "Q5") (value "TL431") (footprint "TO92") (libsource (lib "常用元件库") (part "TL431")))
    (comp (ref "QM1") (value "PMOS-AO4429") (footprint "SO-8") (libsource (lib "常用元件库") (part "MOS-SO-8")))
    (comp (ref "R1") (value "33") (footprint "R0603") (libsource (lib "电阻电容二极管") (part "RES2")))
    (comp (ref "R2") (value "33") (footprint "R0603") (libsource (lib "电阻电容二极管") (part "RES2")))
    (comp (ref "R3") (value "1k") (footprint "R0603") (libsource (lib "电阻电容二极管") (part "RES2")))
    (comp (ref "R5") (value "0") (footprint "R0603") (libsource (lib "电阻电容二极管") (part "RES2")))
    (comp (ref "R6") (value "33") (footprint "R0603") (libsource (lib "电阻电容二极管") (part "RES2")))
    (comp (ref "R8") (value "1k") (footprint "R0603") (libsource (lib "电阻电容二极管") (part "RES2")))
    (comp (ref "R10") (value "33") (footprint "R0603") (libsource (lib "电阻电容二极管") (part "RES2")))
    (comp (ref "R11") (value "10k") (footprint "R0603") (libsource (lib "电阻电容二极管") (part "RES2")))
    (comp (ref "R12") (value "10k") (footprint "R0603") (libsource (lib "电阻电容二极管") (part "RES2")))
    (comp (ref "R13") (value "10k") (footprint "R0603") (libsource (lib "电阻电容二极管") (part "RES2")))
    (comp (ref "R14") (value "10k") (footprint "R0603") (libsource (lib "电阻电容二极管") (part "RES2")))
    (comp (ref "R16") (value "33") (footprint "R0603") (libsource (lib "电阻电容二极管") (part "RES2")))
    (comp (ref "R17") (value "10") (footprint "R0603") (libsource (lib "电阻电容二极管") (part "RES2")))
    (comp (ref "R18") (value "33") (footprint "R0603") (libsource (lib "电阻电容二极管") (part "RES2")))
    (comp (ref "R19") (value "33") (footprint "R0603") (libsource (lib "电阻电容二极管") (part "RES2")))
    (comp (ref "R20") (value "33") (footprint "R0603") (libsource (lib "电阻电容二极管") (part "RES2")))
    (comp (ref "R22") (value "33") (footprint "R0603") (libsource (lib "电阻电容二极管") (part "RES2")))
    (comp (ref "R23") (value "33") (footprint "R0603") (libsource (lib "电阻电容二极管") (part "RES2")))
    (comp (ref "R24") (value "33") (footprint "R0603") (libsource (lib "电阻电容二极管") (part "RES2")))
    (comp (ref "R25") (value "33") (footprint "R0603") (libsource (lib "电阻电容二极管") (part "RES2")))
    (comp (ref "R26") (value "33") (footprint "R0603") (libsource (lib "电阻电容二极管") (part "RES2")))
    (comp (ref "R27") (value "10") (footprint "R0603") (libsource (lib "电阻电容二极管") (part "RES2")))
    (comp (ref "R29") (value "360 1%") (footprint "R0603") (libsource (lib "电阻电容二极管") (part "RES2")))
    (comp (ref "R31") (value "150 1%") (footprint "R0603") (libsource (lib "电阻电容二极管") (part "RES2")))
    (comp (ref "R33") (value "33") (footprint "R0603") (libsource (lib "电阻电容二极管") (part "RES2")))
    (comp (ref "R35") (value "33") (footprint "R0603") (libsource (lib "电阻电容二极管") (part "RES2")))
    (comp (ref "R36") (value "33") (footprint "R0603") (libsource (lib "电阻电容二极管") (part "RES2")))
    (comp (ref "R37") (value "33") (footprint "R0603") (libsource (lib "电阻电容二极管") (part "RES2")))
    (comp (ref "R38") (value "33") (footprint "R0603") (libsource (lib "电阻电容二极管") (part "RES2")))
    (comp (ref "R39") (value "10k") (footprint "R0603") (libsource (lib "电阻电容二极管") (part "RES2")))
    (comp (ref "R40") (value "1k") (footprint "R0603") (libsource (lib "电阻电容二极管") (part "RES2")))
    (comp (ref "R41") (value "5.1k") (footprint "R0603") (libsource (lib "电阻电容二极管") (part "RES2")))
    (comp (ref "R42") (value "470") (footprint "R0603") (libsource (lib "电阻电容二极管") (part "RES2")))
    (comp (ref "R43") (value "10k") (footprint "R0603") (libsource (lib "电阻电容二极管") (part "RES2")))
    (comp (ref "R44") (value "1M") (footprint "R0603") (libsource (lib "电阻电容二极管") (part "RES2")))
    (comp (ref "R45") (value "10k") (footprint "R0603") (libsource (lib "电阻电容二极管") (part "RES2")))
    (comp (ref "R46") (value "33") (footprint "R0603") (libsource (lib "电阻电容二极管") (part "RES2")))
    (comp (ref "R47") (value "10k") (footprint "R0603") (libsource (lib "电阻电容二极管") (part "RES2")))
    (comp (ref "R48") (value "10k") (footprint "R0603") (libsource (lib "电阻电容二极管") (part "RES2")))
    (comp (ref "R49") (value "330") (footprint "R0603") (libsource (lib "电阻电容二极管") (part "RES2")))
    (comp (ref "R51") (value "33") (footprint "R0603") (libsource (lib "电阻电容二极管") (part "RES2")))
    (comp (ref "R55") (value "10k") (footprint "R0603") (libsource (lib "电阻电容二极管") (part "RES2")))
    (comp (ref "R56") (value "10k") (footprint "R0603") (libsource (lib "电阻电容二极管") (part "RES2")))
    (comp (ref "R57") (value "10k") (footprint "R0603") (libsource (lib "电阻电容二极管") (part "RES2")))
    (comp (ref "R59") (value "10k") (footprint "R0603") (libsource (lib "电阻电容二极管") (part "RES2")))
    (comp (ref "R60") (value "10k") (footprint "R0603") (libsource (lib "电阻电容二极管") (part "RES2")))
    (comp (ref "R61") (value "10k") (footprint "R0603") (libsource (lib "电阻电容二极管") (part "RES2")))
    (comp (ref "R62") (value "10k") (footprint "R0603") (libsource (lib "电阻电容二极管") (part "RES2")))
    (comp (ref "R63") (value "10k") (footprint "R0603") (libsource (lib "电阻电容二极管") (part "RES2")))
    (comp (ref "R64") (value "10k") (footprint "R0603") (libsource (lib "电阻电容二极管") (part "RES2")))
    (comp (ref "R67") (value "56") (footprint "R0603") (libsource (lib "电阻电容二极管") (part "RES2")))
    (comp (ref "R68") (value "0") (footprint "R0603") (libsource (lib "电阻电容二极管") (part "RES2")))
    (comp (ref "R69") (value "NC") (footprint "R0603") (libsource (lib "电阻电容二极管") (part "RES2")))
    (comp (ref "R70") (value "10k") (footprint "R0603") (libsource (lib "电阻电容二极管") (part "RES2")))
    (comp (ref "R71") (value "NC") (footprint "R0603") (libsource (lib "电阻电容二极管") (part "RES2")))
    (comp (ref "R72") (value "NC") (footprint "R0603") (libsource (lib "电阻电容二极管") (part "RES2")))
    (comp (ref "R73") (value "10k") (footprint "R0603") (libsource (lib "电阻电容二极管") (part "RES2")))
    (comp (ref "R74") (value "10k") (footprint "R0603") (libsource (lib "电阻电容二极管") (part "RES2")))
    (comp (ref "R100") (value "10k") (footprint "R0603") (libsource (lib "电阻电容二极管") (part "RES2")))
    (comp (ref "R101") (value "10k") (footprint "R0603") (libsource (lib "电阻电容二极管") (part "RES2")))
    (comp (ref "R102") (value "10k") (footprint "R0603") (libsource (lib "电阻电容二极管") (part "RES2")))
    (comp (ref "R103") (value "10k") (footprint "R0603") (libsource (lib "电阻电容二极管") (part "RES2")))
    (comp (ref "R105") (value "10k") (footprint "R0603") (libsource (lib "电阻电容二极管") (part "RES2")))
    (comp (ref "R106") (value "10k") (footprint "R0603") (libsource (lib "电阻电容二极管") (part "RES2")))
    (comp (ref "R107") (value "10k") (footprint "R0603") (libsource (lib "电阻电容二极管") (part "RES2")))
    (comp (ref "R118") (value "33") (footprint "R0603") (libsource (lib "电阻电容二极管") (part "RES2")))
    (comp (ref "RD1") (value "33") (footprint "R0603") (libsource (lib "电阻电容二极管") (part "RES2")))
    (comp (ref "RD2") (value "33") (footprint "R0603") (libsource (lib "电阻电容二极管") (part "RES2")))
    (comp (ref "RD3") (value "33") (footprint "R0603") (libsource (lib "电阻电容二极管") (part "RES2")))
    (comp (ref "RD4") (value "33") (footprint "R0603") (libsource (lib "电阻电容二极管") (part "RES2")))
    (comp (ref "RD5") (value "33") (footprint "R0603") (libsource (lib "电阻电容二极管") (part "RES2")))
    (comp (ref "RD6") (value "33") (footprint "R0603") (libsource (lib "电阻电容二极管") (part "RES2")))
    (comp (ref "RD7") (value "33") (footprint "R0603") (libsource (lib "电阻电容二极管") (part "RES2")))
    (comp (ref "RD8") (value "33") (footprint "R0603") (libsource (lib "电阻电容二极管") (part "RES2")))
    (comp (ref "RD9") (value "33") (footprint "R0603") (libsource (lib "电阻电容二极管") (part "RES2")))
    (comp (ref "RD10") (value "33") (footprint "R0603") (libsource (lib "电阻电容二极管") (part "RES2")))
    (comp (ref "RD11") (value "33") (footprint "R0603") (libsource (lib "电阻电容二极管") (part "RES2")))
    (comp (ref "RD12") (value "33") (footprint "R0603") (libsource (lib "电阻电容二极管") (part "RES2")))
    (comp (ref "RD13") (value "33") (footprint "R0603") (libsource (lib "电阻电容二极管") (part "RES2")))
    (comp (ref "RD14") (value "33") (footprint "R0603") (libsource (lib "电阻电容二极管") (part "RES2")))
    (comp (ref "RD15") (value "33") (footprint "R0603") (libsource (lib "电阻电容二极管") (part "RES2")))
    (comp (ref "RD16") (value "33") (footprint "R0603") (libsource (lib "电阻电容二极管") (part "RES2")))
    (comp (ref "RD17") (value "33") (footprint "R0603") (libsource (lib "电阻电容二极管") (part "RES2")))
    (comp (ref "RD18") (value "33") (footprint "R0603") (libsource (lib "电阻电容二极管") (part "RES2")))
    (comp (ref "RD19") (value "33") (footprint "R0603") (libsource (lib "电阻电容二极管") (part "RES2")))
    (comp (ref "RD20") (value "33") (footprint "R0603") (libsource (lib "电阻电容二极管") (part "RES2")))
    (comp (ref "RD21") (value "33") (footprint "R0603") (libsource (lib "电阻电容二极管") (part "RES2")))
    (comp (ref "RD22") (value "33") (footprint "R0603") (libsource (lib "电阻电容二极管") (part "RES2")))
    (comp (ref "RD23") (value "33") (footprint "R0603") (libsource (lib "电阻电容二极管") (part "RES2")))
    (comp (ref "RD24") (value "33") (footprint "R0603") (libsource (lib "电阻电容二极管") (part "RES2")))
    (comp (ref "RD25") (value "33") (footprint "R0603") (libsource (lib "电阻电容二极管") (part "RES2")))
    (comp (ref "RD26") (value "33") (footprint "R0603") (libsource (lib "电阻电容二极管") (part "RES2")))
    (comp (ref "RD27") (value "33") (footprint "R0603") (libsource (lib "电阻电容二极管") (part "RES2")))
    (comp (ref "RD28") (value "33") (footprint "R0603") (libsource (lib "电阻电容二极管") (part "RES2")))
    (comp (ref "RD29") (value "33") (footprint "R0603") (libsource (lib "电阻电容二极管") (part "RES2")))
    (comp (ref "RD30") (value "33") (footprint "R0603") (libsource (lib "电阻电容二极管") (part "RES2")))
    (comp (ref "RD31") (value "33") (footprint "R0603") (libsource (lib "电阻电容二极管") (part "RES2")))
    (comp (ref "RD32") (value "33") (footprint "R0603") (libsource (lib "电阻电容二极管") (part "RES2")))
    (comp (ref "RD33") (value "33") (footprint "R0603") (libsource (lib "电阻电容二极管") (part "RES2")))
    (comp (ref "RD34") (value "33") (footprint "R0603") (libsource (lib "电阻电容二极管") (part "RES2")))
    (comp (ref "RK1") (value "33") (footprint "R0603") (libsource (lib "电阻电容二极管") (part "RES2")))
    (comp (ref "RK2") (value "33") (footprint "R0603") (libsource (lib "电阻电容二极管") (part "RES2")))
    (comp (ref "RL1") (value "1k") (footprint "R0603") (libsource (lib "电阻电容二极管") (part "RES2")))
    (comp (ref "RL2") (value "1k") (footprint "R0603") (libsource (lib "电阻电容二极管") (part "RES2")))
    (comp (ref "RM1") (value "33") (footprint "R0603") (libsource (lib "电阻电容二极管") (part "RES2")))
    (comp (ref "RM2") (value "33") (footprint "R0603") (libsource (lib "电阻电容二极管") (part "RES2")))
    (comp (ref "RM3") (value "33") (footprint "R0603") (libsource (lib "电阻电容二极管") (part "RES2")))
    (comp (ref "RM4") (value "33") (footprint "R0603") (libsource (lib "电阻电容二极管") (part "RES2")))
    (comp (ref "RM5") (value "33") (footprint "R0603") (libsource (lib "电阻电容二极管") (part "RES2")))
    (comp (ref "RM6") (value "33") (footprint "R0603") (libsource (lib "电阻电容二极管") (part "RES2")))
    (comp (ref "RM7") (value "33") (footprint "R0603") (libsource (lib "电阻电容二极管") (part "RES2")))
    (comp (ref "RM8") (value "33") (footprint "R0603") (libsource (lib "电阻电容二极管") (part "RES2")))
    (comp (ref "RM9") (value "33") (footprint "R0603") (libsource (lib "电阻电容二极管") (part "RES2")))
    (comp (ref "RM10") (value "33") (footprint "R0603") (libsource (lib "电阻电容二极管") (part "RES2")))
    (comp (ref "RM11") (value "33") (footprint "R0603") (libsource (lib "电阻电容二极管") (part "RES2")))
    (comp (ref "RM12") (value "33") (footprint "R0603") (libsource (lib "电阻电容二极管") (part "RES2")))
    (comp (ref "RM13") (value "33") (footprint "R0603") (libsource (lib "电阻电容二极管") (part "RES2")))
    (comp (ref "RM14") (value "33") (footprint "R0603") (libsource (lib "电阻电容二极管") (part "RES2")))
    (comp (ref "RM15") (value "33") (footprint "R0603") (libsource (lib "电阻电容二极管") (part "RES2")))
    (comp (ref "RM16") (value "33") (footprint "R0603") (libsource (lib "电阻电容二极管") (part "RES2")))
    (comp (ref "RM17") (value "33") (footprint "R0603") (libsource (lib "电阻电容二极管") (part "RES2")))
    (comp (ref "RM18") (value "33") (footprint "R0603") (libsource (lib "电阻电容二极管") (part "RES2")))
    (comp (ref "RM19") (value "33") (footprint "R0603") (libsource (lib "电阻电容二极管") (part "RES2")))
    (comp (ref "RM20") (value "33") (footprint "R0603") (libsource (lib "电阻电容二极管") (part "RES2")))
    (comp (ref "RN51") (value "10k") (footprint "R0603") (libsource (lib "电阻电容二极管") (part "RES2")))
    (comp (ref "RN52") (value "10k") (footprint "R0603") (libsource (lib "电阻电容二极管") (part "RES2")))
    (comp (ref "RN53") (value "10k") (footprint "R0603") (libsource (lib "电阻电容二极管") (part "RES2")))
    (comp (ref "RN54") (value "10k") (footprint "R0603") (libsource (lib "电阻电容二极管") (part "RES2")))
    (comp (ref "RN55") (value "10k") (footprint "R0603") (libsource (lib "电阻电容二极管") (part "RES2")))
    (comp (ref "RN56") (value "10k") (footprint "R0603") (libsource (lib "电阻电容二极管") (part "RES2")))
    (comp (ref "RN57") (value "10k") (footprint "R0603") (libsource (lib "电阻电容二极管") (part "RES2")))
    (comp (ref "RN58") (value "10k") (footprint "R0603") (libsource (lib "电阻电容二极管") (part "RES2")))
    (comp (ref "RN59") (value "10k") (footprint "R0603") (libsource (lib "电阻电容二极管") (part "RES2")))
    (comp (ref "RN60") (value "10k") (footprint "R0603") (libsource (lib "电阻电容二极管") (part "RES2")))
    (comp (ref "RN61") (value "10k") (footprint "R0603") (libsource (lib "电阻电容二极管") (part "RES2")))
    (comp (ref "RN62") (value "10k") (footprint "R0603") (libsource (lib "电阻电容二极管") (part "RES2")))
    (comp (ref "RN63") (value "10k") (footprint "R0603") (libsource (lib "电阻电容二极管") (part "RES2")))
    (comp (ref "RN64") (value "10k") (footprint "R0603") (libsource (lib "电阻电容二极管") (part "RES2")))
    (comp (ref "RN65") (value "10k") (footprint "R0603") (libsource (lib "电阻电容二极管") (part "RES2")))
    (comp (ref "RN66") (value "10k") (footprint "R0603") (libsource (lib "电阻电容二极管") (part "RES2")))
    (comp (ref "RN67") (value "10k") (footprint "R0603") (libsource (lib "电阻电容二极管") (part "RES2")))
    (comp (ref "RN68") (value "10k") (footprint "R0603") (libsource (lib "电阻电容二极管") (part "RES2")))
    (comp (ref "RN69") (value "10k") (footprint "R0603") (libsource (lib "电阻电容二极管") (part "RES2")))
    (comp (ref "RN70") (value "10k") (footprint "R0603") (libsource (lib "电阻电容二极管") (part "RES2")))
    (comp (ref "RN71") (value "10k") (footprint "R0603") (libsource (lib "电阻电容二极管") (part "RES2")))
    (comp (ref "RN72") (value "10k") (footprint "R0603") (libsource (lib "电阻电容二极管") (part "RES2")))
    (comp (ref "RN73") (value "10k") (footprint "R0603") (libsource (lib "电阻电容二极管") (part "RES2")))
    (comp (ref "RN74") (value "10k") (footprint "R0603") (libsource (lib "电阻电容二极管") (part "RES2")))
    (comp (ref "RN75") (value "10k") (footprint "R0603") (libsource (lib "电阻电容二极管") (part "RES2")))
    (comp (ref "RN76") (value "10k") (footprint "R0603") (libsource (lib "电阻电容二极管") (part "RES2")))
    (comp (ref "RN77") (value "10k") (footprint "R0603") (libsource (lib "电阻电容二极管") (part "RES2")))
    (comp (ref "RN78") (value "10k") (footprint "R0603") (libsource (lib "电阻电容二极管") (part "RES2")))
    (comp (ref "RN79") (value "10k") (footprint "R0603") (libsource (lib "电阻电容二极管") (part "RES2")))
    (comp (ref "RN80") (value "10k") (footprint "R0603") (libsource (lib "电阻电容二极管") (part "RES2")))
    (comp (ref "RN81") (value "10k") (footprint "R0603") (libsource (lib "电阻电容二极管") (part "RES2")))
    (comp (ref "RN82") (value "10k") (footprint "R0603") (libsource (lib "电阻电容二极管") (part "RES2")))
    (comp (ref "RP21") (value "33") (footprint "R0603") (libsource (lib "电阻电容二极管") (part "RES2")))
    (comp (ref "RP22") (value "33") (footprint "R0603") (libsource (lib "电阻电容二极管") (part "RES2")))
    (comp (ref "RP23") (value "33") (footprint "R0603") (libsource (lib "电阻电容二极管") (part "RES2")))
    (comp (ref "RP24") (value "33") (footprint "R0603") (libsource (lib "电阻电容二极管") (part "RES2")))
    (comp (ref "RP51") (value "33") (footprint "R0603") (libsource (lib "电阻电容二极管") (part "RES2")))
    (comp (ref "RP52") (value "33") (footprint "R0603") (libsource (lib "电阻电容二极管") (part "RES2")))
    (comp (ref "RP53") (value "33") (footprint "R0603") (libsource (lib "电阻电容二极管") (part "RES2")))
    (comp (ref "RP54") (value "33") (footprint "R0603") (libsource (lib "电阻电容二极管") (part "RES2")))
    (comp (ref "RP61") (value "33") (footprint "R0603") (libsource (lib "电阻电容二极管") (part "RES2")))
    (comp (ref "RP62") (value "33") (footprint "R0603") (libsource (lib "电阻电容二极管") (part "RES2")))
    (comp (ref "RP63") (value "33") (footprint "R0603") (libsource (lib "电阻电容二极管") (part "RES2")))
    (comp (ref "RP64") (value "33") (footprint "R0603") (libsource (lib "电阻电容二极管") (part "RES2")))
    (comp (ref "RP71") (value "33") (footprint "R0603") (libsource (lib "电阻电容二极管") (part "RES2")))
    (comp (ref "RP72") (value "33") (footprint "R0603") (libsource (lib "电阻电容二极管") (part "RES2")))
    (comp (ref "RP73") (value "33") (footprint "R0603") (libsource (lib "电阻电容二极管") (part "RES2")))
    (comp (ref "RP74") (value "33") (footprint "R0603") (libsource (lib "电阻电容二极管") (part "RES2")))
    (comp (ref "RP212") (value "10k") (footprint "R0603") (libsource (lib "电阻电容二极管") (part "RES2")))
    (comp (ref "RP213") (value "10k") (footprint "R0603") (libsource (lib "电阻电容二极管") (part "RES2")))
    (comp (ref "RP214") (value "10k") (footprint "R0603") (libsource (lib "电阻电容二极管") (part "RES2")))
    (comp (ref "RP221") (value "10k") (footprint "R0603") (libsource (lib "电阻电容二极管") (part "RES2")))
    (comp (ref "RP222") (value "10k") (footprint "R0603") (libsource (lib "电阻电容二极管") (part "RES2")))
    (comp (ref "RP223") (value "10k") (footprint "R0603") (libsource (lib "电阻电容二极管") (part "RES2")))
    (comp (ref "RP224") (value "10k") (footprint "R0603") (libsource (lib "电阻电容二极管") (part "RES2")))
    (comp (ref "RQ1") (value "10k") (footprint "R0603") (libsource (lib "电阻电容二极管") (part "RES2")))
    (comp (ref "RQ2") (value "10k") (footprint "R0603") (libsource (lib "电阻电容二极管") (part "RES2")))
    (comp (ref "RQ3") (value "10k") (footprint "R0603") (libsource (lib "电阻电容二极管") (part "RES2")))
    (comp (ref "RQ4") (value "10k") (footprint "R0603") (libsource (lib "电阻电容二极管") (part "RES2")))
    (comp (ref "RQ5") (value "10k") (footprint "R0603") (libsource (lib "电阻电容二极管") (part "RES2")))
    (comp (ref "RQ6") (value "10k") (footprint "R0603") (libsource (lib "电阻电容二极管") (part "RES2")))
    (comp (ref "RQ7") (value "10k") (footprint "R0603") (libsource (lib "电阻电容二极管") (part "RES2")))
    (comp (ref "RQ8") (value "10k") (footprint "R0603") (libsource (lib "电阻电容二极管") (part "RES2")))
    (comp (ref "RQ9") (value "10k") (footprint "R0603") (libsource (lib "电阻电容二极管") (part "RES2")))
    (comp (ref "RQ10") (value "10k") (footprint "R0603") (libsource (lib "电阻电容二极管") (part "RES2")))
    (comp (ref "RQ11") (value "10k") (footprint "R0603") (libsource (lib "电阻电容二极管") (part "RES2")))
    (comp (ref "RQ12") (value "10k") (footprint "R0603") (libsource (lib "电阻电容二极管") (part "RES2")))
    (comp (ref "RU1") (value "30k") (footprint "R0603") (libsource (lib "电阻电容二极管") (part "RES2")))
    (comp (ref "RU2") (value "1k") (footprint "R0603") (libsource (lib "电阻电容二极管") (part "RES2")))
    (comp (ref "RU3") (value "0.1") (footprint "2512") (libsource (lib "电阻电容二极管") (part "RES2")))
    (comp (ref "RU4") (value "0.1") (footprint "2512") (libsource (lib "电阻电容二极管") (part "RES2")))
    (comp (ref "RU5") (value "0.1") (footprint "2512") (libsource (lib "电阻电容二极管") (part "RES2")))
    (comp (ref "RU6") (value "1k") (footprint "R0603") (libsource (lib "电阻电容二极管") (part "RES2")))
    (comp (ref "RU7") (value "510") (footprint "R0603") (libsource (lib "电阻电容二极管") (part "RES2")))
    (comp (ref "RU8") (value "510") (footprint "R0603") (libsource (lib "电阻电容二极管") (part "RES2")))
    (comp (ref "RU19") (value "510") (footprint "R0603") (libsource (lib "电阻电容二极管") (part "RES2")))
    (comp (ref "RU20") (value "510") (footprint "R0603") (libsource (lib "电阻电容二极管") (part "RES2")))
    (comp (ref "RU21") (value "10k") (footprint "R0603") (libsource (lib "电阻电容二极管") (part "RES2")))
    (comp (ref "RU22") (value "10k") (footprint "R0603") (libsource (lib "电阻电容二极管") (part "RES2")))
    (comp (ref "RV1") (value "33") (footprint "R0603") (libsource (lib "电阻电容二极管") (part "RES2")))
    (comp (ref "S1") (value "POWER") (footprint "SW 8x8") (libsource (lib "开关") (part "双刀双柄开关")))
    (comp (ref "SW1") (value "SW1") (footprint "SW1") (libsource (lib "常用元件库") (part "SW1")))
    (comp (ref "TFT1")
      (value "TFT-1.44")
      (footprint "MY-1.44TFT")
      (libsource (lib "单片机及相关") (part "TFT-1.44"))
    )
    (comp (ref "U2") (value "27C010") (footprint "ZIF32") (libsource (lib "微机原理") (part "27C010")))
    (comp (ref "U5") (value "74LS153") (footprint "DIP-16") (libsource (lib "TTL74系列IC") (part "74LS153")))
    (comp (ref "U6") (value "CMA8815") (footprint "DIP14") (libsource (lib "微机原理") (part "CMA8815")))
    (comp (ref "U7") (value "74LS244") (footprint "DIP20") (libsource (lib "微机原理") (part "74LS244")))
    (comp (ref "U8") (value "74LS245") (footprint "SOP20") (libsource (lib "微机原理") (part "74LS245")))
    (comp (ref "U9") (value "74LS245") (footprint "SOP20") (libsource (lib "微机原理") (part "74LS245")))
    (comp (ref "U10") (value "74LS153") (footprint "DIP-16") (libsource (lib "TTL74系列IC") (part "74LS153")))
    (comp (ref "U12") (value "74LS245") (footprint "SOP20") (libsource (lib "微机原理") (part "74LS245")))
    (comp (ref "U13") (value "ALD93C488A") (footprint "QFP208") (libsource (lib "微机原理") (part "ALD93C488A")))
    (comp (ref "U14") (value "74LS245") (footprint "SOP20") (libsource (lib "微机原理") (part "74LS245")))
    (comp (ref "U15") (value "74LS14") (footprint "SO-14") (libsource (lib "0ALD488") (part "74LS14")))
    (comp (ref "U16") (value "74LS245") (footprint "SOP20") (libsource (lib "微机原理") (part "74LS245")))
    (comp (ref "U17") (value "74LS245") (footprint "SOP20") (libsource (lib "微机原理") (part "74LS245")))
    (comp (ref "U18") (value "74LS245") (footprint "SOP20") (libsource (lib "微机原理") (part "74LS245")))
    (comp (ref "U19") (value "GAL16V8D") (footprint "DIP20") (libsource (lib "微机原理") (part "GAL16V8D")))
    (comp (ref "UM1")
      (value "STC8A8K64S4A12_LQFP44")
      (footprint "LQFP44")
      (libsource (lib "单片机及相关") (part "STC8A8K64S4A12_LQFP44"))
    )
    (comp (ref "UM2") (value "INA219_SOP") (footprint "SO-8") (libsource (lib "单片机及相关") (part "INA219_SOP")))
    (comp (ref "UM3") (value "INA219_SOP") (footprint "SO-8") (libsource (lib "单片机及相关") (part "INA219_SOP")))
    (comp (ref "UM4") (value "INA219_SOP") (footprint "SO-8") (libsource (lib "单片机及相关") (part "INA219_SOP")))
    (comp (ref "UM5") (value "XL4015") (footprint "TO-263(T)") (libsource (lib "常用元件库") (part "XL4015")))
    (comp (ref "UM6") (value "XL4015") (footprint "TO-263(T)") (libsource (lib "常用元件库") (part "XL4015")))
    (comp (ref "UM8")
      (value "LM7805CT")
      (footprint "TO-252(DPAK)")
      (libsource (lib "单片机及相关") (part "LM7805CT"))
    )
    (comp (ref "UM9") (value "CH340C") (footprint "SOP-16") (libsource (lib "单片机及相关") (part "CH340G")))
    (comp (ref "USB1")
      (value "USB_Micro")
      (footprint "USB_Micro")
      (libsource (lib "My_Lib") (part "USB_Micro"))
    )
    (comp (ref "VR1") (value "10k") (footprint "3x3P") (libsource (lib "常用元件库") (part "VR")))
    (comp (ref "VR2") (value "10k") (footprint "3x3P") (libsource (lib "常用元件库") (part "VR")))
    (comp (ref "X1") (value "14.318M") (footprint "5032") (libsource (lib "常用元件库") (part "CRYSTAL")))
    (comp (ref "X2") (value "32768k") (footprint "CRY-26") (libsource (lib "常用元件库") (part "CRYSTAL")))
  )
  (nets
    (net (code "1") (name "/-12V") (class "Default")
      (node (ref "CU25") (pin "2") (pinfunction "2_2") (pintype "passive"))
      (node (ref "CU26") (pin "2") (pinfunction "2_2") (pintype "passive"))
      (node (ref "ISA1") (pin "B07") (pinfunction "-12V_B07") (pintype "passive"))
      (node (ref "ISA2") (pin "B07") (pinfunction "-12V_B07") (pintype "passive"))
      (node (ref "ISA3") (pin "B07") (pinfunction "-12V_B07") (pintype "passive"))
      (node (ref "P1") (pin "3") (pinfunction "VO-_3") (pintype "passive"))
      (node (ref "PCI0") (pin "B1") (pinfunction "-12V_B1") (pintype "passive"))
      (node (ref "PCI1") (pin "B1") (pinfunction "-12V_B1") (pintype "passive"))
      (node (ref "PCI2") (pin "B1") (pinfunction "-12V_B1") (pintype "passive"))
    )
    (net (code "2") (name "/12V") (class "Default")
      (node (ref "CU10") (pin "1") (pinfunction "1_1") (pintype "passive"))
      (node (ref "CU11") (pin "1") (pinfunction "1_1") (pintype "passive"))
      (node (ref "CU12") (pin "1") (pinfunction "1_1") (pintype "passive"))
      (node (ref "CU2") (pin "1") (pinfunction "1_1") (pintype "passive"))
      (node (ref "CU27") (pin "1") (pinfunction "1_1") (pintype "passive"))
      (node (ref "CU28") (pin "1") (pinfunction "1_1") (pintype "passive"))
      (node (ref "CU3") (pin "1") (pinfunction "1_1") (pintype "passive"))
      (node (ref "CU4") (pin "1") (pinfunction "1_1") (pintype "passive"))
      (node (ref "CU9") (pin "1") (pinfunction "1_1") (pintype "passive"))
      (node (ref "ISA1") (pin "B09") (pinfunction "+12V_B09") (pintype "passive"))
      (node (ref "ISA2") (pin "B09") (pinfunction "+12V_B09") (pintype "passive"))
      (node (ref "ISA3") (pin "B09") (pinfunction "+12V_B09") (pintype "passive"))
      (node (ref "P1") (pin "5") (pinfunction "VI+_5") (pintype "passive"))
      (node (ref "PCI0") (pin "A2") (pinfunction "12V_A2") (pintype "passive"))
      (node (ref "PCI1") (pin "A2") (pinfunction "12V_A2") (pintype "passive"))
      (node (ref "PCI2") (pin "A2") (pinfunction "12V_A2") (pintype "passive"))
      (node (ref "QM1") (pin "5") (pinfunction "D_5") (pintype "passive"))
      (node (ref "QM1") (pin "6") (pinfunction "D_6") (pintype "passive"))
      (node (ref "QM1") (pin "7") (pinfunction "D_7") (pintype "passive"))
      (node (ref "QM1") (pin "8") (pinfunction "D_8") (pintype "passive"))
      (node (ref "UM5") (pin "5") (pinfunction "VIN_5") (pintype "passive"))
      (node (ref "UM6") (pin "5") (pinfunction "VIN_5") (pintype "passive"))
      (node (ref "UM8") (pin "1") (pinfunction "Vin_1") (pintype "passive"))
    )
    (net (code "3") (name "/32KIN") (class "Default")
      (node (ref "U13") (pin "3") (pinfunction "32KIN/IRQ8_3") (pintype "passive"))
      (node (ref "U15") (pin "6") (pintype "output"))
    )
    (net (code "4") (name "/33VCC") (class "Default")
      (node (ref "CT1") (pin "44") (pinfunction "44_44") (pintype "passive"))
      (node (ref "CT1") (pin "45") (pinfunction "45_45") (pintype "passive"))
      (node (ref "CT1") (pin "7") (pinfunction "7_7") (pintype "passive"))
      (node (ref "CT1") (pin "8") (pinfunction "8_8") (pintype "passive"))
      (node (ref "CV23") (pin "1") (pinfunction "1_1") (pintype "passive"))
      (node (ref "CV24") (pin "1") (pinfunction "1_1") (pintype "passive"))
      (node (ref "CV25") (pin "1") (pinfunction "1_1") (pintype "passive"))
      (node (ref "CV26") (pin "1") (pinfunction "1_1") (pintype "passive"))
      (node (ref "CV27") (pin "1") (pinfunction "1_1") (pintype "passive"))
      (node (ref "CV28") (pin "1") (pinfunction "1_1") (pintype "passive"))
      (node (ref "CV29") (pin "1") (pinfunction "1_1") (pintype "passive"))
      (node (ref "CV30") (pin "1") (pinfunction "1_1") (pintype "passive"))
      (node (ref "CV31") (pin "1") (pinfunction "1_1") (pintype "passive"))
      (node (ref "CV32") (pin "1") (pinfunction "1_1") (pintype "passive"))
      (node (ref "CV33") (pin "1") (pinfunction "1_1") (pintype "passive"))
      (node (ref "CV34") (pin "1") (pinfunction "1_1") (pintype "passive"))
      (node (ref "CV35") (pin "1") (pinfunction "1_1") (pintype "passive"))
      (node (ref "CV36") (pin "1") (pinfunction "1_1") (pintype "passive"))
      (node (ref "CV37") (pin "1") (pinfunction "1_1") (pintype "passive"))
      (node (ref "CV38") (pin "1") (pinfunction "1_1") (pintype "passive"))
      (node (ref "CV39") (pin "1") (pinfunction "1_1") (pintype "passive"))
      (node (ref "CV40") (pin "1") (pinfunction "1_1") (pintype "passive"))
      (node (ref "PCI0") (pin "A21") (pinfunction "3.3V_A21") (pintype "passive"))
      (node (ref "PCI0") (pin "A27") (pinfunction "3.3V_A27") (pintype "passive"))
      (node (ref "PCI0") (pin "A33") (pinfunction "3.3V_A33") (pintype "passive"))
      (node (ref "PCI0") (pin "A39") (pinfunction "3.3V_A39") (pintype "passive"))
      (node (ref "PCI0") (pin "A45") (pinfunction "3.3V_A45") (pintype "passive"))
      (node (ref "PCI0") (pin "A53") (pinfunction "3.3V_A53") (pintype "passive"))
      (node (ref "PCI0") (pin "B25") (pinfunction "3.3V_B25") (pintype "passive"))
      (node (ref "PCI0") (pin "B31") (pinfunction "3.3V_B31") (pintype "passive"))
      (node (ref "PCI0") (pin "B36") (pinfunction "3.3V_B36") (pintype "passive"))
      (node (ref "PCI0") (pin "B41") (pinfunction "3.3V_B41") (pintype "passive"))
      (node (ref "PCI0") (pin "B43") (pinfunction "3.3V_B43") (pintype "passive"))
      (node (ref "PCI0") (pin "B54") (pinfunction "3.3V_B54") (pintype "passive"))
      (node (ref "PCI1") (pin "A21") (pinfunction "3.3V_A21") (pintype "passive"))
      (node (ref "PCI1") (pin "A27") (pinfunction "3.3V_A27") (pintype "passive"))
      (node (ref "PCI1") (pin "A33") (pinfunction "3.3V_A33") (pintype "passive"))
      (node (ref "PCI1") (pin "A39") (pinfunction "3.3V_A39") (pintype "passive"))
      (node (ref "PCI1") (pin "A45") (pinfunction "3.3V_A45") (pintype "passive"))
      (node (ref "PCI1") (pin "A53") (pinfunction "3.3V_A53") (pintype "passive"))
      (node (ref "PCI1") (pin "B25") (pinfunction "3.3V_B25") (pintype "passive"))
      (node (ref "PCI1") (pin "B31") (pinfunction "3.3V_B31") (pintype "passive"))
      (node (ref "PCI1") (pin "B36") (pinfunction "3.3V_B36") (pintype "passive"))
      (node (ref "PCI1") (pin "B41") (pinfunction "3.3V_B41") (pintype "passive"))
      (node (ref "PCI1") (pin "B43") (pinfunction "3.3V_B43") (pintype "passive"))
      (node (ref "PCI1") (pin "B54") (pinfunction "3.3V_B54") (pintype "passive"))
      (node (ref "PCI2") (pin "A21") (pinfunction "3.3V_A21") (pintype "passive"))
      (node (ref "PCI2") (pin "A27") (pinfunction "3.3V_A27") (pintype "passive"))
      (node (ref "PCI2") (pin "A33") (pinfunction "3.3V_A33") (pintype "passive"))
      (node (ref "PCI2") (pin "A39") (pinfunction "3.3V_A39") (pintype "passive"))
      (node (ref "PCI2") (pin "A45") (pinfunction "3.3V_A45") (pintype "passive"))
      (node (ref "PCI2") (pin "A53") (pinfunction "3.3V_A53") (pintype "passive"))
      (node (ref "PCI2") (pin "B25") (pinfunction "3.3V_B25") (pintype "passive"))
      (node (ref "PCI2") (pin "B31") (pinfunction "3.3V_B31") (pintype "passive"))
      (node (ref "PCI2") (pin "B36") (pinfunction "3.3V_B36") (pintype "passive"))
      (node (ref "PCI2") (pin "B41") (pinfunction "3.3V_B41") (pintype "passive"))
      (node (ref "PCI2") (pin "B43") (pinfunction "3.3V_B43") (pintype "passive"))
      (node (ref "PCI2") (pin "B54") (pinfunction "3.3V_B54") (pintype "passive"))
      (node (ref "RU5") (pin "1") (pinfunction "1_1") (pintype "passive"))
      (node (ref "RV1") (pin "1") (pinfunction "1_1") (pintype "passive"))
      (node (ref "UM3") (pin "7") (pinfunction "IN-_7") (pintype "passive"))
    )
    (net (code "5") (name "/A20M#") (class "Default")
      (node (ref "CPU1") (pin "47") (pinfunction "A20M#_47") (pintype "passive"))
      (node (ref "U13") (pin "7") (pinfunction "A20M#_7") (pintype "passive"))
    )
    (net (code "6") (name "/AD0") (class "Default")
      (node (ref "U13") (pin "70") (pinfunction "D0_70") (pintype "passive"))
      (node (ref "U14") (pin "18") (pinfunction "B0_18") (pintype "bidirectional"))
    )
    (net (code "7") (name "/AD1") (class "Default")
      (node (ref "U13") (pin "69") (pinfunction "D1_69") (pintype "passive"))
      (node (ref "U14") (pin "17") (pinfunction "B1_17") (pintype "bidirectional"))
    )
    (net (code "8") (name "/AD2") (class "Default")
      (node (ref "CPU1") (pin "202") (pinfunction "A2_202") (pintype "passive"))
      (node (ref "CT1") (pin "42") (pinfunction "42_42") (pintype "passive"))
      (node (ref "U13") (pin "68") (pinfunction "AD2_68") (pintype "passive"))
      (node (ref "U14") (pin "16") (pinfunction "B2_16") (pintype "bidirectional"))
    )
    (net (code "9") (name "/AD3") (class "Default")
      (node (ref "CPU1") (pin "197") (pinfunction "A3_197") (pintype "passive"))
      (node (ref "CT1") (pin "41") (pinfunction "41_41") (pintype "passive"))
      (node (ref "U13") (pin "67") (pinfunction "AD3_67") (pintype "passive"))
      (node (ref "U14") (pin "15") (pinfunction "B3_15") (pintype "bidirectional"))
    )
    (net (code "10") (name "/AD4") (class "Default")
      (node (ref "CPU1") (pin "196") (pinfunction "A4_196") (pintype "passive"))
      (node (ref "CT1") (pin "29") (pinfunction "29_29") (pintype "passive"))
      (node (ref "U13") (pin "66") (pinfunction "AD4_66") (pintype "passive"))
      (node (ref "U14") (pin "14") (pinfunction "B4_14") (pintype "bidirectional"))
    )
    (net (code "11") (name "/AD5") (class "Default")
      (node (ref "CPU1") (pin "195") (pinfunction "A5_195") (pintype "passive"))
      (node (ref "CT1") (pin "30") (pinfunction "30_30") (pintype "passive"))
      (node (ref "U13") (pin "65") (pinfunction "AD5_65") (pintype "passive"))
      (node (ref "U14") (pin "13") (pinfunction "B5_13") (pintype "bidirectional"))
    )
    (net (code "12") (name "/AD6") (class "Default")
      (node (ref "CPU1") (pin "193") (pinfunction "A6_193") (pintype "passive"))
      (node (ref "CT1") (pin "31") (pinfunction "31_31") (pintype "passive"))
      (node (ref "U13") (pin "64") (pinfunction "AD6_64") (pintype "passive"))
      (node (ref "U14") (pin "12") (pinfunction "B6_12") (pintype "bidirectional"))
    )
    (net (code "13") (name "/AD7") (class "Default")
      (node (ref "CPU1") (pin "192") (pinfunction "A7_192") (pintype "passive"))
      (node (ref "CT1") (pin "32") (pinfunction "32_32") (pintype "passive"))
      (node (ref "U13") (pin "63") (pinfunction "AD7_63") (pintype "passive"))
      (node (ref "U14") (pin "11") (pinfunction "B7_11") (pintype "bidirectional"))
    )
    (net (code "14") (name "/AD8") (class "Default")
      (node (ref "CPU1") (pin "190") (pinfunction "A8_190") (pintype "passive"))
      (node (ref "CT1") (pin "33") (pinfunction "33_33") (pintype "passive"))
      (node (ref "U12") (pin "18") (pinfunction "B0_18") (pintype "bidirectional"))
      (node (ref "U13") (pin "62") (pinfunction "AD8_62") (pintype "passive"))
    )
    (net (code "15") (name "/AD9") (class "Default")
      (node (ref "CPU1") (pin "187") (pinfunction "A9_187") (pintype "passive"))
      (node (ref "CT1") (pin "34") (pinfunction "34_34") (pintype "passive"))
      (node (ref "U12") (pin "17") (pinfunction "B1_17") (pintype "bidirectional"))
      (node (ref "U13") (pin "61") (pinfunction "AD9_61") (pintype "passive"))
    )
    (net (code "16") (name "/AD10") (class "Default")
      (node (ref "CPU1") (pin "186") (pinfunction "A10_186") (pintype "passive"))
      (node (ref "CT1") (pin "35") (pinfunction "35_35") (pintype "passive"))
      (node (ref "U12") (pin "16") (pinfunction "B2_16") (pintype "bidirectional"))
      (node (ref "U13") (pin "60") (pinfunction "AD10_60") (pintype "passive"))
    )
    (net (code "17") (name "/AD11") (class "Default")
      (node (ref "CPU1") (pin "182") (pinfunction "A11_182") (pintype "passive"))
      (node (ref "CT1") (pin "36") (pinfunction "36_36") (pintype "passive"))
      (node (ref "U12") (pin "15") (pinfunction "B3_15") (pintype "bidirectional"))
      (node (ref "U13") (pin "59") (pinfunction "AD11_59") (pintype "passive"))
    )
    (net (code "18") (name "/AD12") (class "Default")
      (node (ref "CPU1") (pin "180") (pinfunction "A12_180") (pintype "passive"))
      (node (ref "CT1") (pin "23") (pinfunction "23_23") (pintype "passive"))
      (node (ref "U12") (pin "14") (pinfunction "B4_14") (pintype "bidirectional"))
      (node (ref "U13") (pin "58") (pinfunction "AD12_58") (pintype "passive"))
    )
    (net (code "19") (name "/AD13") (class "Default")
      (node (ref "CPU1") (pin "178") (pinfunction "A13_178") (pintype "passive"))
      (node (ref "CT1") (pin "22") (pinfunction "22_22") (pintype "passive"))
      (node (ref "U12") (pin "13") (pinfunction "B5_13") (pintype "bidirectional"))
      (node (ref "U13") (pin "57") (pinfunction "AD13_57") (pintype "passive"))
    )
    (net (code "20") (name "/AD14") (class "Default")
      (node (ref "CPU1") (pin "177") (pinfunction "A14_177") (pintype "passive"))
      (node (ref "CT1") (pin "21") (pinfunction "21_21") (pintype "passive"))
      (node (ref "U12") (pin "12") (pinfunction "B6_12") (pintype "bidirectional"))
      (node (ref "U13") (pin "56") (pinfunction "AD14_56") (pintype "passive"))
    )
    (net (code "21") (name "/AD15") (class "Default")
      (node (ref "CPU1") (pin "174") (pinfunction "A15_174") (pintype "passive"))
      (node (ref "CT1") (pin "19") (pinfunction "19_19") (pintype "passive"))
      (node (ref "U12") (pin "11") (pinfunction "B7_11") (pintype "bidirectional"))
      (node (ref "U13") (pin "55") (pinfunction "AD15_55") (pintype "passive"))
    )
    (net (code "22") (name "/AD16") (class "Default")
      (node (ref "CPU1") (pin "173") (pinfunction "A16_173") (pintype "passive"))
      (node (ref "CT1") (pin "28") (pinfunction "28_28") (pintype "passive"))
      (node (ref "U13") (pin "54") (pinfunction "AD16_54") (pintype "passive"))
      (node (ref "U8") (pin "18") (pinfunction "B0_18") (pintype "bidirectional"))
    )
    (net (code "23") (name "/AD17") (class "Default")
      (node (ref "CPU1") (pin "171") (pinfunction "A17_171") (pintype "passive"))
      (node (ref "CT1") (pin "27") (pinfunction "27_27") (pintype "passive"))
      (node (ref "U13") (pin "53") (pinfunction "AD17_53") (pintype "passive"))
      (node (ref "U8") (pin "17") (pinfunction "B1_17") (pintype "bidirectional"))
    )
    (net (code "24") (name "/AD18") (class "Default")
      (node (ref "CPU1") (pin "166") (pinfunction "A18_166") (pintype "passive"))
      (node (ref "CT1") (pin "24") (pinfunction "24_24") (pintype "passive"))
      (node (ref "U13") (pin "51") (pinfunction "AD18_51") (pintype "passive"))
      (node (ref "U8") (pin "16") (pinfunction "B2_16") (pintype "bidirectional"))
    )
    (net (code "25") (name "/AD19") (class "Default")
      (node (ref "CPU1") (pin "165") (pinfunction "A19_165") (pintype "passive"))
      (node (ref "U13") (pin "50") (pinfunction "AD19_50") (pintype "passive"))
      (node (ref "U8") (pin "15") (pinfunction "B3_15") (pintype "bidirectional"))
    )
    (net (code "26") (name "/AD20") (class "Default")
      (node (ref "CPU1") (pin "164") (pinfunction "A20_164") (pintype "passive"))
      (node (ref "U13") (pin "49") (pinfunction "AD20_49") (pintype "passive"))
      (node (ref "U8") (pin "14") (pinfunction "B4_14") (pintype "bidirectional"))
    )
    (net (code "27") (name "/AD21") (class "Default")
      (node (ref "CPU1") (pin "161") (pinfunction "A21_161") (pintype "passive"))
      (node (ref "U13") (pin "48") (pinfunction "AD21_48") (pintype "passive"))
      (node (ref "U8") (pin "13") (pinfunction "B5_13") (pintype "bidirectional"))
    )
    (net (code "28") (name "/AD22") (class "Default")
      (node (ref "CPU1") (pin "160") (pinfunction "A22_160") (pintype "passive"))
      (node (ref "U13") (pin "47") (pinfunction "AD22_47") (pintype "passive"))
      (node (ref "U8") (pin "12") (pinfunction "B6_12") (pintype "bidirectional"))
    )
    (net (code "29") (name "/AD23") (class "Default")
      (node (ref "CPU1") (pin "159") (pinfunction "A23_159") (pintype "passive"))
      (node (ref "U13") (pin "46") (pinfunction "AD23_46") (pintype "passive"))
      (node (ref "U8") (pin "11") (pinfunction "B7_11") (pintype "bidirectional"))
    )
    (net (code "30") (name "/AD24") (class "Default")
      (node (ref "CPU1") (pin "158") (pinfunction "A24_158") (pintype "passive"))
      (node (ref "U13") (pin "45") (pinfunction "AD24_45") (pintype "passive"))
      (node (ref "U9") (pin "18") (pinfunction "B0_18") (pintype "bidirectional"))
    )
    (net (code "31") (name "/AD24{slash}HDA0") (class "Default")
      (node (ref "PCI0") (pin "A25") (pinfunction "AD24_A25") (pintype "passive"))
      (node (ref "PCI1") (pin "A25") (pinfunction "AD24_A25") (pintype "passive"))
      (node (ref "PCI2") (pin "A25") (pinfunction "AD24_A25") (pintype "passive"))
      (node (ref "U13") (pin "110") (pinfunction "AD24/HDA0_110") (pintype "passive"))
      (node (ref "U16") (pin "5") (pinfunction "A3_5") (pintype "bidirectional"))
    )
    (net (code "32") (name "/AD25") (class "Default")
      (node (ref "CPU1") (pin "154") (pinfunction "A25_154") (pintype "passive"))
      (node (ref "U13") (pin "43") (pinfunction "AD25_43") (pintype "passive"))
      (node (ref "U9") (pin "17") (pinfunction "B1_17") (pintype "bidirectional"))
    )
    (net (code "33") (name "/AD25{slash}HDA1") (class "Default")
      (node (ref "PCI0") (pin "B24") (pinfunction "AD25_B24") (pintype "passive"))
      (node (ref "PCI1") (pin "B24") (pinfunction "AD25_B24") (pintype "passive"))
      (node (ref "PCI2") (pin "B24") (pinfunction "AD25_B24") (pintype "passive"))
      (node (ref "U13") (pin "149") (pinfunction "AD25/HDA1_149") (pintype "passive"))
      (node (ref "U16") (pin "8") (pinfunction "A6_8") (pintype "bidirectional"))
    )
    (net (code "34") (name "/AD26") (class "Default")
      (node (ref "CPU1") (pin "153") (pinfunction "A26_153") (pintype "passive"))
      (node (ref "U13") (pin "42") (pinfunction "AD26_42") (pintype "passive"))
      (node (ref "U9") (pin "16") (pinfunction "B2_16") (pintype "bidirectional"))
    )
    (net (code "35") (name "/AD26{slash}HDA2") (class "Default")
      (node (ref "PCI0") (pin "A23") (pinfunction "AD26_A23") (pintype "passive"))
      (node (ref "PCI1") (pin "A23") (pinfunction "AD26_A23") (pintype "passive"))
      (node (ref "PCI2") (pin "A23") (pinfunction "AD26_A23") (pintype "passive"))
      (node (ref "U13") (pin "109") (pinfunction "AD26/HDA2_109") (pintype "passive"))
      (node (ref "U16") (pin "4") (pinfunction "A2_4") (pintype "bidirectional"))
    )
    (net (code "36") (name "/AD27") (class "Default")
      (node (ref "CPU1") (pin "152") (pinfunction "A27_152") (pintype "passive"))
      (node (ref "U13") (pin "41") (pinfunction "AD27_41") (pintype "passive"))
      (node (ref "U9") (pin "15") (pinfunction "B3_15") (pintype "bidirectional"))
    )
    (net (code "37") (name "/AD27{slash}HD17X#{slash}ROMCS#") (class "Default")
      (node (ref "PCI0") (pin "B23") (pinfunction "AD27_B23") (pintype "passive"))
      (node (ref "PCI1") (pin "B23") (pinfunction "AD27_B23") (pintype "passive"))
      (node (ref "PCI2") (pin "B23") (pinfunction "AD27_B23") (pintype "passive"))
      (node (ref "R10") (pin "2") (pinfunction "2_2") (pintype "passive"))
      (node (ref "U13") (pin "150") (pinfunction "AD27/HD17X#/ROMCS#_150") (pintype "passive"))
      (node (ref "U16") (pin "7") (pinfunction "A5_7") (pintype "bidirectional"))
    )
    (net (code "38") (name "/AD28") (class "Default")
      (node (ref "CPU1") (pin "151") (pinfunction "A28_151") (pintype "passive"))
      (node (ref "U13") (pin "40") (pinfunction "AD28_40") (pintype "passive"))
      (node (ref "U9") (pin "14") (pinfunction "B4_14") (pintype "bidirectional"))
    )
    (net (code "39") (name "/AD28{slash}HD37X#{slash}RTCCS#") (class "Default")
      (node (ref "PCI0") (pin "A22") (pinfunction "AD28_A22") (pintype "passive"))
      (node (ref "PCI1") (pin "A22") (pinfunction "AD28_A22") (pintype "passive"))
      (node (ref "PCI2") (pin "A22") (pinfunction "AD28_A22") (pintype "passive"))
      (node (ref "U13") (pin "108") (pinfunction "AD28/HD37X#/RTCCS#_108") (pintype "passive"))
      (node (ref "U16") (pin "3") (pinfunction "A1_3") (pintype "bidirectional"))
    )
    (net (code "40") (name "/AD29") (class "Default")
      (node (ref "CPU1") (pin "149") (pinfunction "A29_149") (pintype "passive"))
      (node (ref "U13") (pin "39") (pinfunction "AD29_39") (pintype "passive"))
      (node (ref "U9") (pin "13") (pinfunction "B5_13") (pintype "bidirectional"))
    )
    (net (code "41") (name "/AD29{slash}HD1FX#{slash}KBCS#") (class "Default")
      (node (ref "PCI0") (pin "B21") (pinfunction "AD29_B21") (pintype "passive"))
      (node (ref "PCI1") (pin "B21") (pinfunction "AD29_B21") (pintype "passive"))
      (node (ref "PCI2") (pin "B21") (pinfunction "AD29_B21") (pintype "passive"))
      (node (ref "U13") (pin "151") (pinfunction "AD29/HD1FX#/KBCS#_151") (pintype "passive"))
      (node (ref "U16") (pin "6") (pinfunction "A4_6") (pintype "bidirectional"))
    )
    (net (code "42") (name "/AD30") (class "Default")
      (node (ref "CPU1") (pin "148") (pinfunction "A30_148") (pintype "passive"))
      (node (ref "U13") (pin "38") (pinfunction "AD30_38") (pintype "passive"))
      (node (ref "U9") (pin "12") (pinfunction "B6_12") (pintype "bidirectional"))
    )
    (net (code "43") (name "/AD30{slash}HD3FX#") (class "Default")
      (node (ref "PCI0") (pin "A20") (pinfunction "AD30_A20") (pintype "passive"))
      (node (ref "PCI1") (pin "A20") (pinfunction "AD30_A20") (pintype "passive"))
      (node (ref "PCI2") (pin "A20") (pinfunction "AD30_A20") (pintype "passive"))
      (node (ref "U13") (pin "107") (pinfunction "AD30/HD3FX#_107") (pintype "passive"))
      (node (ref "U16") (pin "2") (pinfunction "A0_2") (pintype "bidirectional"))
    )
    (net (code "44") (name "/AD31") (class "Default")
      (node (ref "CPU1") (pin "147") (pinfunction "A31_147") (pintype "passive"))
      (node (ref "U13") (pin "37") (pinfunction "AD31_37") (pintype "passive"))
      (node (ref "U9") (pin "11") (pinfunction "B7_11") (pintype "bidirectional"))
    )
    (net (code "45") (name "/AD31{slash}SBHE#") (class "Default")
      (node (ref "PCI0") (pin "B20") (pinfunction "AD31_B20") (pintype "passive"))
      (node (ref "PCI1") (pin "B20") (pinfunction "AD31_B20") (pintype "passive"))
      (node (ref "PCI2") (pin "B20") (pinfunction "AD31_B20") (pintype "passive"))
      (node (ref "RP61") (pin "1") (pinfunction "1_1") (pintype "passive"))
      (node (ref "U13") (pin "152") (pinfunction "AD31/SBHE#_152") (pintype "passive"))
    )
    (net (code "46") (name "/ADS#") (class "Default")
      (node (ref "CPU1") (pin "203") (pinfunction "ADS#_203") (pintype "passive"))
      (node (ref "CT2") (pin "48") (pinfunction "48_48") (pintype "passive"))
      (node (ref "R45") (pin "1") (pinfunction "1_1") (pintype "passive"))
      (node (ref "U13") (pin "27") (pinfunction "ADS#_27") (pintype "passive"))
    )
    (net (code "47") (name "/ADV#") (class "Default")
      (node (ref "CT2") (pin "6") (pinfunction "6_6") (pintype "passive"))
      (node (ref "U13") (pin "33") (pinfunction "ADV#_33") (pintype "passive"))
    )
    (net (code "48") (name "/AD{slash}LA{slash}17") (class "Default")
      (node (ref "PCI0") (pin "B32") (pinfunction "AD17_B32") (pintype "passive"))
      (node (ref "PCI1") (pin "B32") (pinfunction "AD17_B32") (pintype "passive"))
      (node (ref "PCI2") (pin "B32") (pinfunction "AD17_B32") (pintype "passive"))
      (node (ref "RP53") (pin "1") (pinfunction "1_1") (pintype "passive"))
      (node (ref "RP74") (pin "1") (pinfunction "1_1") (pintype "passive"))
      (node (ref "U13") (pin "144") (pinfunction "AD17/LA17_144") (pintype "passive"))
    )
    (net (code "49") (name "/AD{slash}LA{slash}18") (class "Default")
      (node (ref "PCI0") (pin "A31") (pinfunction "AD18_A31") (pintype "passive"))
      (node (ref "PCI1") (pin "A31") (pinfunction "AD18_A31") (pintype "passive"))
      (node (ref "PCI2") (pin "A31") (pinfunction "AD18_A31") (pintype "passive"))
      (node (ref "RP52") (pin "1") (pinfunction "1_1") (pintype "passive"))
      (node (ref "RP73") (pin "1") (pinfunction "1_1") (pintype "passive"))
      (node (ref "U13") (pin "113") (pinfunction "AD18/LA18_113") (pintype "passive"))
    )
    (net (code "50") (name "/AD{slash}LA{slash}19") (class "Default")
      (node (ref "PCI0") (pin "B30") (pinfunction "AD19_B30") (pintype "passive"))
      (node (ref "PCI1") (pin "B30") (pinfunction "AD19_B30") (pintype "passive"))
      (node (ref "PCI2") (pin "B30") (pinfunction "AD19_B30") (pintype "passive"))
      (node (ref "R118") (pin "1") (pinfunction "1_1") (pintype "passive"))
      (node (ref "RP51") (pin "1") (pinfunction "1_1") (pintype "passive"))
      (node (ref "RP72") (pin "1") (pinfunction "1_1") (pintype "passive"))
      (node (ref "U13") (pin "145") (pinfunction "AD19/LA19_145") (pintype "passive"))
    )
    (net (code "51") (name "/AD{slash}LA{slash}20") (class "Default")
      (node (ref "PCI0") (pin "A29") (pinfunction "AD20_A29") (pintype "passive"))
      (node (ref "PCI1") (pin "A29") (pinfunction "AD20_A29") (pintype "passive"))
      (node (ref "PCI2") (pin "A29") (pinfunction "AD20_A29") (pintype "passive"))
      (node (ref "R18") (pin "1") (pinfunction "1_1") (pintype "passive"))
      (node (ref "RP71") (pin "1") (pinfunction "1_1") (pintype "passive"))
      (node (ref "U13") (pin "112") (pinfunction "AD20/LA20_112") (pintype "passive"))
    )
    (net (code "52") (name "/AD{slash}LA{slash}21") (class "Default")
      (node (ref "PCI0") (pin "B29") (pinfunction "AD21_B29") (pintype "passive"))
      (node (ref "PCI1") (pin "B29") (pinfunction "AD21_B29") (pintype "passive"))
      (node (ref "PCI2") (pin "B29") (pinfunction "AD21_B29") (pintype "passive"))
      (node (ref "R19") (pin "1") (pinfunction "1_1") (pintype "passive"))
      (node (ref "RP64") (pin "1") (pinfunction "1_1") (pintype "passive"))
      (node (ref "U13") (pin "146") (pinfunction "AD21/LA21_146") (pintype "passive"))
    )
    (net (code "53") (name "/AD{slash}LA{slash}22") (class "Default")
      (node (ref "PCI0") (pin "A28") (pinfunction "AD22_A28") (pintype "passive"))
      (node (ref "PCI1") (pin "A28") (pinfunction "AD22_A28") (pintype "passive"))
      (node (ref "PCI2") (pin "A28") (pinfunction "AD22_A28") (pintype "passive"))
      (node (ref "RP63") (pin "1") (pinfunction "1_1") (pintype "passive"))
      (node (ref "U13") (pin "111") (pinfunction "AD22/LA22_111") (pintype "passive"))
    )
    (net (code "54") (name "/AD{slash}LA{slash}23") (class "Default")
      (node (ref "PCI0") (pin "B27") (pinfunction "AD23_B27") (pintype "passive"))
      (node (ref "PCI1") (pin "B27") (pinfunction "AD23_B27") (pintype "passive"))
      (node (ref "PCI2") (pin "B27") (pinfunction "AD23_B27") (pintype "passive"))
      (node (ref "RP62") (pin "1") (pinfunction "1_1") (pintype "passive"))
      (node (ref "U13") (pin "147") (pinfunction "AD23/LA23_147") (pintype "passive"))
    )
    (net (code "55") (name "/AD{slash}SA{slash}16") (class "Default")
      (node (ref "PCI0") (pin "A32") (pinfunction "AD16_A32") (pintype "passive"))
      (node (ref "PCI1") (pin "A32") (pinfunction "AD16_A32") (pintype "passive"))
      (node (ref "PCI2") (pin "A32") (pinfunction "AD16_A32") (pintype "passive"))
      (node (ref "RP54") (pin "1") (pinfunction "1_1") (pintype "passive"))
      (node (ref "U13") (pin "114") (pinfunction "AD16/SA16_114") (pintype "passive"))
      (node (ref "U19") (pin "6") (pinfunction "I5_6") (pintype "passive"))
    )
    (net (code "56") (name "/AD{slash}SD{slash}0") (class "Default")
      (node (ref "PCI0") (pin "A58") (pinfunction "AD00_A58") (pintype "passive"))
      (node (ref "PCI1") (pin "A58") (pinfunction "AD00_A58") (pintype "passive"))
      (node (ref "PCI2") (pin "A58") (pinfunction "AD00_A58") (pintype "passive"))
      (node (ref "RD19") (pin "1") (pinfunction "1_1") (pintype "passive"))
      (node (ref "U13") (pin "127") (pinfunction "AD0/SD0_127") (pintype "passive"))
    )
    (net (code "57") (name "/AD{slash}SD{slash}1") (class "Default")
      (node (ref "PCI0") (pin "B58") (pinfunction "AD01_B58") (pintype "passive"))
      (node (ref "PCI1") (pin "B58") (pinfunction "AD01_B58") (pintype "passive"))
      (node (ref "PCI2") (pin "B58") (pinfunction "AD01_B58") (pintype "passive"))
      (node (ref "RD20") (pin "1") (pinfunction "1_1") (pintype "passive"))
      (node (ref "U13") (pin "133") (pinfunction "AD1/SD1_133") (pintype "passive"))
    )
    (net (code "58") (name "/AD{slash}SD{slash}2") (class "Default")
      (node (ref "PCI0") (pin "A57") (pinfunction "AD02_A57") (pintype "passive"))
      (node (ref "PCI1") (pin "A57") (pinfunction "AD02_A57") (pintype "passive"))
      (node (ref "PCI2") (pin "A57") (pinfunction "AD02_A57") (pintype "passive"))
      (node (ref "RD21") (pin "1") (pinfunction "1_1") (pintype "passive"))
      (node (ref "U13") (pin "125") (pinfunction "AD2/SD2_125") (pintype "passive"))
    )
    (net (code "59") (name "/AD{slash}SD{slash}3") (class "Default")
      (node (ref "PCI0") (pin "B56") (pinfunction "AD03_B56") (pintype "passive"))
      (node (ref "PCI1") (pin "B56") (pinfunction "AD03_B56") (pintype "passive"))
      (node (ref "PCI2") (pin "B56") (pinfunction "AD03_B56") (pintype "passive"))
      (node (ref "RD22") (pin "1") (pinfunction "1_1") (pintype "passive"))
      (node (ref "U13") (pin "134") (pinfunction "AD3/SD3_134") (pintype "passive"))
    )
    (net (code "60") (name "/AD{slash}SD{slash}4") (class "Default")
      (node (ref "PCI0") (pin "A55") (pinfunction "AD04_A55") (pintype "passive"))
      (node (ref "PCI1") (pin "A55") (pinfunction "AD04_A55") (pintype "passive"))
      (node (ref "PCI2") (pin "A55") (pinfunction "AD04_A55") (pintype "passive"))
      (node (ref "RD23") (pin "1") (pinfunction "1_1") (pintype "passive"))
      (node (ref "U13") (pin "124") (pinfunction "AD4/SD4_124") (pintype "passive"))
    )
    (net (code "61") (name "/AD{slash}SD{slash}5") (class "Default")
      (node (ref "PCI0") (pin "B55") (pinfunction "AD05_B55") (pintype "passive"))
      (node (ref "PCI1") (pin "B55") (pinfunction "AD05_B55") (pintype "passive"))
      (node (ref "PCI2") (pin "B55") (pinfunction "AD05_B55") (pintype "passive"))
      (node (ref "RD24") (pin "1") (pinfunction "1_1") (pintype "passive"))
      (node (ref "U13") (pin "131") (pinfunction "AD5/SD5_131") (pintype "passive"))
    )
    (net (code "62") (name "/AD{slash}SD{slash}6") (class "Default")
      (node (ref "PCI0") (pin "A54") (pinfunction "AD06_A54") (pintype "passive"))
      (node (ref "PCI1") (pin "A54") (pinfunction "AD06_A54") (pintype "passive"))
      (node (ref "PCI2") (pin "A54") (pinfunction "AD06_A54") (pintype "passive"))
      (node (ref "RD25") (pin "1") (pinfunction "1_1") (pintype "passive"))
      (node (ref "U13") (pin "126") (pinfunction "AD6/SD6_126") (pintype "passive"))
    )
    (net (code "63") (name "/AD{slash}SD{slash}7") (class "Default")
      (node (ref "PCI0") (pin "B53") (pinfunction "AD07_B53") (pintype "passive"))
      (node (ref "PCI1") (pin "B53") (pinfunction "AD07_B53") (pintype "passive"))
      (node (ref "PCI2") (pin "B53") (pinfunction "AD07_B53") (pintype "passive"))
      (node (ref "RD26") (pin "1") (pinfunction "1_1") (pintype "passive"))
      (node (ref "U13") (pin "130") (pinfunction "AD7/SD7_130") (pintype "passive"))
    )
    (net (code "64") (name "/AD{slash}SD{slash}8") (class "Default")
      (node (ref "PCI0") (pin "B52") (pinfunction "AD08_B52") (pintype "passive"))
      (node (ref "PCI1") (pin "B52") (pinfunction "AD08_B52") (pintype "passive"))
      (node (ref "PCI2") (pin "B52") (pinfunction "AD08_B52") (pintype "passive"))
      (node (ref "RD27") (pin "1") (pinfunction "1_1") (pintype "passive"))
      (node (ref "U13") (pin "132") (pinfunction "AD8/SD8_132") (pintype "passive"))
    )
    (net (code "65") (name "/AD{slash}SD{slash}9") (class "Default")
      (node (ref "PCI0") (pin "A49") (pinfunction "AD09_A49") (pintype "passive"))
      (node (ref "PCI1") (pin "A49") (pinfunction "AD09_A49") (pintype "passive"))
      (node (ref "PCI2") (pin "A49") (pinfunction "AD09_A49") (pintype "passive"))
      (node (ref "RD28") (pin "1") (pinfunction "1_1") (pintype "passive"))
      (node (ref "U13") (pin "123") (pinfunction "AD9/SD9_123") (pintype "passive"))
    )
    (net (code "66") (name "/AD{slash}SD{slash}10") (class "Default")
      (node (ref "PCI0") (pin "B48") (pinfunction "AD10_B48") (pintype "passive"))
      (node (ref "PCI1") (pin "B48") (pinfunction "AD10_B48") (pintype "passive"))
      (node (ref "PCI2") (pin "B48") (pinfunction "AD10_B48") (pintype "passive"))
      (node (ref "RD29") (pin "1") (pinfunction "1_1") (pintype "passive"))
      (node (ref "U13") (pin "135") (pinfunction "AD10/SD10_135") (pintype "passive"))
    )
    (net (code "67") (name "/AD{slash}SD{slash}11") (class "Default")
      (node (ref "PCI0") (pin "A47") (pinfunction "AD11_A47") (pintype "passive"))
      (node (ref "PCI1") (pin "A47") (pinfunction "AD11_A47") (pintype "passive"))
      (node (ref "PCI2") (pin "A47") (pinfunction "AD11_A47") (pintype "passive"))
      (node (ref "RD30") (pin "1") (pinfunction "1_1") (pintype "passive"))
      (node (ref "U13") (pin "122") (pinfunction "AD11/SD11_122") (pintype "passive"))
    )
    (net (code "68") (name "/AD{slash}SD{slash}12") (class "Default")
      (node (ref "PCI0") (pin "B47") (pinfunction "AD12_B47") (pintype "passive"))
      (node (ref "PCI1") (pin "B47") (pinfunction "AD12_B47") (pintype "passive"))
      (node (ref "PCI2") (pin "B47") (pinfunction "AD12_B47") (pintype "passive"))
      (node (ref "RD31") (pin "1") (pinfunction "1_1") (pintype "passive"))
      (node (ref "U13") (pin "136") (pinfunction "AD12/SD12_136") (pintype "passive"))
    )
    (net (code "69") (name "/AD{slash}SD{slash}13") (class "Default")
      (node (ref "PCI0") (pin "A46") (pinfunction "AD13_A46") (pintype "passive"))
      (node (ref "PCI1") (pin "A46") (pinfunction "AD13_A46") (pintype "passive"))
      (node (ref "PCI2") (pin "A46") (pinfunction "AD13_A46") (pintype "passive"))
      (node (ref "RD32") (pin "1") (pinfunction "1_1") (pintype "passive"))
      (node (ref "U13") (pin "121") (pinfunction "AD13/SD13_121") (pintype "passive"))
    )
    (net (code "70") (name "/AD{slash}SD{slash}14") (class "Default")
      (node (ref "PCI0") (pin "B45") (pinfunction "AD14_B45") (pintype "passive"))
      (node (ref "PCI1") (pin "B45") (pinfunction "AD14_B45") (pintype "passive"))
      (node (ref "PCI2") (pin "B45") (pinfunction "AD14_B45") (pintype "passive"))
      (node (ref "RD33") (pin "1") (pinfunction "1_1") (pintype "passive"))
      (node (ref "U13") (pin "137") (pinfunction "AD14/SD14_137") (pintype "passive"))
    )
    (net (code "71") (name "/AD{slash}SD{slash}15") (class "Default")
      (node (ref "PCI0") (pin "A44") (pinfunction "AD15_A44") (pintype "passive"))
      (node (ref "PCI1") (pin "A44") (pinfunction "AD15_A44") (pintype "passive"))
      (node (ref "PCI2") (pin "A44") (pinfunction "AD15_A44") (pintype "passive"))
      (node (ref "RD34") (pin "1") (pinfunction "1_1") (pintype "passive"))
      (node (ref "U13") (pin "120") (pinfunction "AD15/SD15_120") (pintype "passive"))
    )
    (net (code "72") (name "/AHOLD") (class "Default")
      (node (ref "CPU1") (pin "17") (pinfunction "AHOLD_17") (pintype "passive"))
      (node (ref "U13") (pin "23") (pinfunction "AHOLD_23") (pintype "passive"))
    )
    (net (code "73") (name "/BE0#") (class "Default")
      (node (ref "CPU1") (pin "31") (pinfunction "BE0#_31") (pintype "passive"))
      (node (ref "CT2") (pin "2") (pinfunction "2_2") (pintype "passive"))
      (node (ref "RP221") (pin "1") (pinfunction "1_1") (pintype "passive"))
      (node (ref "U13") (pin "31") (pinfunction "BE0#_31") (pintype "passive"))
    )
    (net (code "74") (name "/BE1#") (class "Default")
      (node (ref "CPU1") (pin "32") (pinfunction "BE1#_32") (pintype "passive"))
      (node (ref "CT2") (pin "50") (pinfunction "50_50") (pintype "passive"))
      (node (ref "RP222") (pin "1") (pinfunction "1_1") (pintype "passive"))
      (node (ref "U13") (pin "30") (pinfunction "BE1#_30") (pintype "passive"))
    )
    (net (code "75") (name "/BE2#") (class "Default")
      (node (ref "CPU1") (pin "33") (pinfunction "BE2#_33") (pintype "passive"))
      (node (ref "CT2") (pin "1") (pinfunction "1_1") (pintype "passive"))
      (node (ref "RP223") (pin "1") (pinfunction "1_1") (pintype "passive"))
      (node (ref "U13") (pin "29") (pinfunction "BE2#_29") (pintype "passive"))
    )
    (net (code "76") (name "/BE3#") (class "Default")
      (node (ref "CPU1") (pin "34") (pinfunction "BE3#_34") (pintype "passive"))
      (node (ref "CT2") (pin "51") (pinfunction "51_51") (pintype "passive"))
      (node (ref "RP224") (pin "1") (pinfunction "1_1") (pintype "passive"))
      (node (ref "U13") (pin "28") (pinfunction "BE3#_28") (pintype "passive"))
    )
    (net (code "77") (name "/BOFF#") (class "Default")
      (node (ref "CPU1") (pin "6") (pinfunction "BOFF#_6") (pintype "passive"))
      (node (ref "U13") (pin "22") (pinfunction "BOFF#_22") (pintype "passive"))
    )
    (net (code "78") (name "/BRDY#") (class "Default")
      (node (ref "CPU1") (pin "5") (pinfunction "BRDY#_5") (pintype "passive"))
      (node (ref "U13") (pin "14") (pinfunction "BRDY#_14") (pintype "passive"))
    )
    (net (code "79") (name "/BWE#") (class "Default")
      (node (ref "CT2") (pin "49") (pinfunction "49_49") (pintype "passive"))
      (node (ref "U13") (pin "34") (pinfunction "BWE#_34") (pintype "passive"))
    )
    (net (code "80") (name "/CACHE#") (class "Default")
      (node (ref "R68") (pin "2") (pinfunction "2_2") (pintype "passive"))
      (node (ref "R69") (pin "1") (pinfunction "1_1") (pintype "passive"))
      (node (ref "U13") (pin "17") (pinfunction "PCD/CACHE#_17") (pintype "passive"))
    )
    (net (code "81") (name "/CAS0#") (class "Default")
      (node (ref "RM20") (pin "1") (pinfunction "1_1") (pintype "passive"))
      (node (ref "U13") (pin "92") (pinfunction "CAS0#_92") (pintype "passive"))
    )
    (net (code "82") (name "/CAS1#") (class "Default")
      (node (ref "RM19") (pin "1") (pinfunction "1_1") (pintype "passive"))
      (node (ref "U13") (pin "91") (pinfunction "CAS1#_91") (pintype "passive"))
    )
    (net (code "83") (name "/CAS2#") (class "Default")
      (node (ref "RM18") (pin "1") (pinfunction "1_1") (pintype "passive"))
      (node (ref "U13") (pin "90") (pinfunction "CAS2#_90") (pintype "passive"))
    )
    (net (code "84") (name "/CAS3#") (class "Default")
      (node (ref "RM17") (pin "1") (pinfunction "1_1") (pintype "passive"))
      (node (ref "U13") (pin "89") (pinfunction "CAS3#_89") (pintype "passive"))
    )
    (net (code "85") (name "/CLK244") (class "Default")
      (node (ref "U6") (pin "8") (pinfunction "CLK(PCI/HCLK/PCLK)_8") (pintype "passive"))
      (node (ref "U7") (pin "11") (pinfunction "2A1_11") (pintype "input"))
      (node (ref "U7") (pin "13") (pinfunction "2A2_13") (pintype "input"))
      (node (ref "U7") (pin "15") (pinfunction "2A3_15") (pintype "input"))
      (node (ref "U7") (pin "17") (pinfunction "2A4_17") (pintype "input"))
      (node (ref "U7") (pin "2") (pinfunction "1A1_2") (pintype "input"))
      (node (ref "U7") (pin "4") (pinfunction "1A2_4") (pintype "input"))
    )
    (net (code "86") (name "/CLKIO") (class "Default")
      (node (ref "R1") (pin "2") (pinfunction "2_2") (pintype "passive"))
      (node (ref "U6") (pin "5") (pinfunction "CLK(IO)_5") (pintype "passive"))
    )
    (net (code "87") (name "/CLKMUL") (class "Default")
      (node (ref "CPU1") (pin "11") (pinfunction "CLKMUL_11") (pintype "passive"))
      (node (ref "R72") (pin "1") (pinfunction "1_1") (pintype "passive"))
    )
    (net (code "88") (name "/CLKOSC") (class "Default")
      (node (ref "R22") (pin "1") (pinfunction "1_1") (pintype "passive"))
      (node (ref "R23") (pin "1") (pinfunction "1_1") (pintype "passive"))
      (node (ref "U6") (pin "4") (pinfunction "CLK(OSC)_4") (pintype "passive"))
    )
    (net (code "89") (name "/CLK_PRIME3C") (class "Default")
      (node (ref "J1") (pin "2") (pinfunction "2_2") (pintype "passive"))
    )
    (net (code "90") (name "/COE#") (class "Default")
      (node (ref "CT2") (pin "5") (pinfunction "5_5") (pintype "passive"))
      (node (ref "U13") (pin "35") (pinfunction "COE#_35") (pintype "passive"))
    )
    (net (code "91") (name "/CPUCLK") (class "Default")
      (node (ref "CPU1") (pin "24") (pinfunction "CLK_24") (pintype "passive"))
      (node (ref "R25") (pin "1") (pinfunction "1_1") (pintype "passive"))
    )
    (net (code "92") (name "/D+") (class "Default")
      (node (ref "UM9") (pin "5") (pinfunction "UD+_5") (pintype "passive"))
      (node (ref "USB1") (pin "3") (pinfunction "D+(DP)_3") (pintype "passive"))
    )
    (net (code "93") (name "/D-") (class "Default")
      (node (ref "UM9") (pin "6") (pinfunction "UD-_6") (pintype "passive"))
      (node (ref "USB1") (pin "2") (pinfunction "D-(DM)_2") (pintype "passive"))
    )
    (net (code "94") (name "/DDIR") (class "Default")
      (node (ref "U12") (pin "1") (pinfunction "DIR_1") (pintype "input"))
      (node (ref "U14") (pin "1") (pinfunction "DIR_1") (pintype "input"))
      (node (ref "U16") (pin "11") (pinfunction "B7_11") (pintype "bidirectional"))
      (node (ref "U8") (pin "1") (pinfunction "DIR_1") (pintype "input"))
      (node (ref "U9") (pin "1") (pinfunction "DIR_1") (pintype "input"))
    )
    (net (code "95") (name "/DEVSEL#") (class "Default")
      (node (ref "R67") (pin "2") (pinfunction "2_2") (pintype "passive"))
      (node (ref "U13") (pin "141") (pinfunction "DEVSEL#_141") (pintype "passive"))
      (node (ref "U19") (pin "19") (pinfunction "I/O1_19") (pintype "passive"))
    )
    (net (code "96") (name "/DOE#") (class "Default")
      (node (ref "U12") (pin "19") (pinfunction "~{OE}_19") (pintype "input"))
      (node (ref "U13") (pin "72") (pinfunction "DOE#_72") (pintype "passive"))
      (node (ref "U14") (pin "19") (pinfunction "~{OE}_19") (pintype "input"))
      (node (ref "U8") (pin "19") (pinfunction "~{OE}_19") (pintype "input"))
      (node (ref "U9") (pin "19") (pinfunction "~{OE}_19") (pintype "input"))
    )
    (net (code "97") (name "/D{slash}C#") (class "Default")
      (node (ref "CPU1") (pin "39") (pinfunction "D/C#_39") (pintype "passive"))
      (node (ref "CPU1") (pin "71") (pinfunction "INV_71") (pintype "passive"))
      (node (ref "RP214") (pin "1") (pinfunction "1_1") (pintype "passive"))
      (node (ref "U13") (pin "24") (pinfunction "D/C#_24") (pintype "passive"))
    )
    (net (code "98") (name "/EADS#") (class "Default")
      (node (ref "CPU1") (pin "46") (pinfunction "EADS#_46") (pintype "passive"))
      (node (ref "U13") (pin "21") (pinfunction "EADS#_21") (pintype "passive"))
    )
    (net (code "99") (name "/FERR#") (class "Default")
      (node (ref "CPU1") (pin "66") (pinfunction "FERR#_66") (pintype "passive"))
      (node (ref "R57") (pin "1") (pinfunction "1_1") (pintype "passive"))
      (node (ref "U13") (pin "19") (pinfunction "FERR#_19") (pintype "passive"))
    )
    (net (code "100") (name "/GW#") (class "Default")
      (node (ref "CT2") (pin "4") (pinfunction "4_4") (pintype "passive"))
      (node (ref "U13") (pin "36") (pinfunction "GW#_36") (pintype "passive"))
    )
    (net (code "101") (name "/HCLK") (class "Default")
      (node (ref "R26") (pin "1") (pinfunction "1_1") (pintype "passive"))
      (node (ref "R62") (pin "1") (pinfunction "1_1") (pintype "passive"))
      (node (ref "U13") (pin "103") (pinfunction "HCLK_103") (pintype "passive"))
    )
    (net (code "102") (name "/HD0") (class "Default")
      (node (ref "CPU1") (pin "144") (pinfunction "D0_144") (pintype "passive"))
      (node (ref "CT2") (pin "25") (pinfunction "25_25") (pintype "passive"))
      (node (ref "M1") (pin "2") (pinfunction "D0_2") (pintype "passive"))
      (node (ref "M2") (pin "2") (pinfunction "D0_2") (pintype "passive"))
      (node (ref "M3") (pin "2") (pinfunction "D0_2") (pintype "passive"))
      (node (ref "M4") (pin "2") (pinfunction "D0_2") (pintype "passive"))
      (node (ref "U14") (pin "2") (pinfunction "A0_2") (pintype "bidirectional"))
    )
    (net (code "103") (name "/HD1") (class "Default")
      (node (ref "CPU1") (pin "143") (pinfunction "D1_143") (pintype "passive"))
      (node (ref "CT2") (pin "28") (pinfunction "28_28") (pintype "passive"))
      (node (ref "M1") (pin "4") (pinfunction "D1_4") (pintype "passive"))
      (node (ref "M2") (pin "4") (pinfunction "D1_4") (pintype "passive"))
      (node (ref "M3") (pin "4") (pinfunction "D1_4") (pintype "passive"))
      (node (ref "M4") (pin "4") (pinfunction "D1_4") (pintype "passive"))
      (node (ref "U14") (pin "3") (pinfunction "A1_3") (pintype "bidirectional"))
    )
    (net (code "104") (name "/HD2") (class "Default")
      (node (ref "CPU1") (pin "142") (pinfunction "D2_142") (pintype "passive"))
      (node (ref "CT2") (pin "24") (pinfunction "24_24") (pintype "passive"))
      (node (ref "M1") (pin "6") (pinfunction "D2_6") (pintype "passive"))
      (node (ref "M2") (pin "6") (pinfunction "D2_6") (pintype "passive"))
      (node (ref "M3") (pin "6") (pinfunction "D2_6") (pintype "passive"))
      (node (ref "M4") (pin "6") (pinfunction "D2_6") (pintype "passive"))
      (node (ref "U14") (pin "4") (pinfunction "A2_4") (pintype "bidirectional"))
    )
    (net (code "105") (name "/HD3") (class "Default")
      (node (ref "CPU1") (pin "141") (pinfunction "D3_141") (pintype "passive"))
      (node (ref "CT2") (pin "29") (pinfunction "29_29") (pintype "passive"))
      (node (ref "M1") (pin "8") (pinfunction "D3_8") (pintype "passive"))
      (node (ref "M2") (pin "8") (pinfunction "D3_8") (pintype "passive"))
      (node (ref "M3") (pin "8") (pinfunction "D3_8") (pintype "passive"))
      (node (ref "M4") (pin "8") (pinfunction "D3_8") (pintype "passive"))
      (node (ref "U14") (pin "5") (pinfunction "A3_5") (pintype "bidirectional"))
    )
    (net (code "106") (name "/HD4") (class "Default")
      (node (ref "CPU1") (pin "140") (pinfunction "D4_140") (pintype "passive"))
      (node (ref "CT2") (pin "23") (pinfunction "23_23") (pintype "passive"))
      (node (ref "M1") (pin "20") (pinfunction "D4_20") (pintype "passive"))
      (node (ref "M2") (pin "20") (pinfunction "D4_20") (pintype "passive"))
      (node (ref "M3") (pin "20") (pinfunction "D4_20") (pintype "passive"))
      (node (ref "M4") (pin "20") (pinfunction "D4_20") (pintype "passive"))
      (node (ref "U14") (pin "6") (pinfunction "A4_6") (pintype "bidirectional"))
    )
    (net (code "107") (name "/HD5") (class "Default")
      (node (ref "CPU1") (pin "130") (pinfunction "D5_130") (pintype "passive"))
      (node (ref "CT2") (pin "30") (pinfunction "30_30") (pintype "passive"))
      (node (ref "M1") (pin "22") (pinfunction "D5_22") (pintype "passive"))
      (node (ref "M2") (pin "22") (pinfunction "D5_22") (pintype "passive"))
      (node (ref "M3") (pin "22") (pinfunction "D5_22") (pintype "passive"))
      (node (ref "M4") (pin "22") (pinfunction "D5_22") (pintype "passive"))
      (node (ref "U14") (pin "7") (pinfunction "A5_7") (pintype "bidirectional"))
    )
    (net (code "108") (name "/HD6") (class "Default")
      (node (ref "CPU1") (pin "129") (pinfunction "D6_129") (pintype "passive"))
      (node (ref "CT2") (pin "22") (pinfunction "22_22") (pintype "passive"))
      (node (ref "M1") (pin "24") (pinfunction "D6_24") (pintype "passive"))
      (node (ref "M2") (pin "24") (pinfunction "D6_24") (pintype "passive"))
      (node (ref "M3") (pin "24") (pinfunction "D6_24") (pintype "passive"))
      (node (ref "M4") (pin "24") (pinfunction "D6_24") (pintype "passive"))
      (node (ref "U14") (pin "8") (pinfunction "A6_8") (pintype "bidirectional"))
    )
    (net (code "109") (name "/HD7") (class "Default")
      (node (ref "CPU1") (pin "126") (pinfunction "D7_126") (pintype "passive"))
      (node (ref "CT2") (pin "31") (pinfunction "31_31") (pintype "passive"))
      (node (ref "M1") (pin "26") (pinfunction "D7_26") (pintype "passive"))
      (node (ref "M2") (pin "26") (pinfunction "D7_26") (pintype "passive"))
      (node (ref "M3") (pin "26") (pinfunction "D7_26") (pintype "passive"))
      (node (ref "M4") (pin "26") (pinfunction "D7_26") (pintype "passive"))
      (node (ref "U14") (pin "9") (pinfunction "A7_9") (pintype "bidirectional"))
    )
    (net (code "110") (name "/HD8") (class "Default")
      (node (ref "CPU1") (pin "124") (pinfunction "D8_124") (pintype "passive"))
      (node (ref "CT2") (pin "20") (pinfunction "20_20") (pintype "passive"))
      (node (ref "M1") (pin "49") (pinfunction "D8_49") (pintype "passive"))
      (node (ref "M2") (pin "49") (pinfunction "D8_49") (pintype "passive"))
      (node (ref "M3") (pin "49") (pinfunction "D8_49") (pintype "passive"))
      (node (ref "M4") (pin "49") (pinfunction "D8_49") (pintype "passive"))
      (node (ref "U12") (pin "2") (pinfunction "A0_2") (pintype "bidirectional"))
    )
    (net (code "111") (name "/HD9") (class "Default")
      (node (ref "CPU1") (pin "123") (pinfunction "D9_123") (pintype "passive"))
      (node (ref "CT2") (pin "33") (pinfunction "33_33") (pintype "passive"))
      (node (ref "M1") (pin "51") (pinfunction "D9_51") (pintype "passive"))
      (node (ref "M2") (pin "51") (pinfunction "D9_51") (pintype "passive"))
      (node (ref "M3") (pin "51") (pinfunction "D9_51") (pintype "passive"))
      (node (ref "M4") (pin "51") (pinfunction "D9_51") (pintype "passive"))
      (node (ref "U12") (pin "3") (pinfunction "A1_3") (pintype "bidirectional"))
    )
    (net (code "112") (name "/HD10") (class "Default")
      (node (ref "CPU1") (pin "119") (pinfunction "D10_119") (pintype "passive"))
      (node (ref "CT2") (pin "19") (pinfunction "19_19") (pintype "passive"))
      (node (ref "M1") (pin "53") (pinfunction "D10_53") (pintype "passive"))
      (node (ref "M2") (pin "53") (pinfunction "D10_53") (pintype "passive"))
      (node (ref "M3") (pin "53") (pinfunction "D10_53") (pintype "passive"))
      (node (ref "M4") (pin "53") (pinfunction "D10_53") (pintype "passive"))
      (node (ref "U12") (pin "4") (pinfunction "A2_4") (pintype "bidirectional"))
    )
    (net (code "113") (name "/HD11") (class "Default")
      (node (ref "CPU1") (pin "118") (pinfunction "D11_118") (pintype "passive"))
      (node (ref "CT2") (pin "34") (pinfunction "34_34") (pintype "passive"))
      (node (ref "M1") (pin "55") (pinfunction "D11_55") (pintype "passive"))
      (node (ref "M2") (pin "55") (pinfunction "D11_55") (pintype "passive"))
      (node (ref "M3") (pin "55") (pinfunction "D11_55") (pintype "passive"))
      (node (ref "M4") (pin "55") (pinfunction "D11_55") (pintype "passive"))
      (node (ref "U12") (pin "5") (pinfunction "A3_5") (pintype "bidirectional"))
    )
    (net (code "114") (name "/HD12") (class "Default")
      (node (ref "CPU1") (pin "117") (pinfunction "D12_117") (pintype "passive"))
      (node (ref "CT2") (pin "18") (pinfunction "18_18") (pintype "passive"))
      (node (ref "M1") (pin "57") (pinfunction "D12_57") (pintype "passive"))
      (node (ref "M2") (pin "57") (pinfunction "D12_57") (pintype "passive"))
      (node (ref "M3") (pin "57") (pinfunction "D12_57") (pintype "passive"))
      (node (ref "M4") (pin "57") (pinfunction "D12_57") (pintype "passive"))
      (node (ref "U12") (pin "6") (pinfunction "A4_6") (pintype "bidirectional"))
    )
    (net (code "115") (name "/HD13") (class "Default")
      (node (ref "CPU1") (pin "116") (pinfunction "D13_116") (pintype "passive"))
      (node (ref "CT2") (pin "35") (pinfunction "35_35") (pintype "passive"))
      (node (ref "M1") (pin "61") (pinfunction "D13_61") (pintype "passive"))
      (node (ref "M2") (pin "61") (pinfunction "D13_61") (pintype "passive"))
      (node (ref "M3") (pin "61") (pinfunction "D13_61") (pintype "passive"))
      (node (ref "M4") (pin "61") (pinfunction "D13_61") (pintype "passive"))
      (node (ref "U12") (pin "7") (pinfunction "A5_7") (pintype "bidirectional"))
    )
    (net (code "116") (name "/HD14") (class "Default")
      (node (ref "CPU1") (pin "113") (pinfunction "D14_113") (pintype "passive"))
      (node (ref "CT2") (pin "17") (pinfunction "17_17") (pintype "passive"))
      (node (ref "M1") (pin "63") (pinfunction "D14_63") (pintype "passive"))
      (node (ref "M2") (pin "63") (pinfunction "D14_63") (pintype "passive"))
      (node (ref "M3") (pin "63") (pinfunction "D14_63") (pintype "passive"))
      (node (ref "M4") (pin "63") (pinfunction "D14_63") (pintype "passive"))
      (node (ref "U12") (pin "8") (pinfunction "A6_8") (pintype "bidirectional"))
    )
    (net (code "117") (name "/HD15") (class "Default")
      (node (ref "CPU1") (pin "112") (pinfunction "D15_112") (pintype "passive"))
      (node (ref "CT2") (pin "36") (pinfunction "36_36") (pintype "passive"))
      (node (ref "M1") (pin "65") (pinfunction "D15_65") (pintype "passive"))
      (node (ref "M2") (pin "65") (pinfunction "D15_65") (pintype "passive"))
      (node (ref "M3") (pin "65") (pinfunction "D15_65") (pintype "passive"))
      (node (ref "M4") (pin "65") (pinfunction "D15_65") (pintype "passive"))
      (node (ref "U12") (pin "9") (pinfunction "A7_9") (pintype "bidirectional"))
    )
    (net (code "118") (name "/HD16") (class "Default")
      (node (ref "CPU1") (pin "108") (pinfunction "D16_108") (pintype "passive"))
      (node (ref "CT2") (pin "15") (pinfunction "15_15") (pintype "passive"))
      (node (ref "M1") (pin "3") (pinfunction "D16_3") (pintype "passive"))
      (node (ref "M2") (pin "3") (pinfunction "D16_3") (pintype "passive"))
      (node (ref "M3") (pin "3") (pinfunction "D16_3") (pintype "passive"))
      (node (ref "M4") (pin "3") (pinfunction "D16_3") (pintype "passive"))
      (node (ref "U8") (pin "2") (pinfunction "A0_2") (pintype "bidirectional"))
    )
    (net (code "119") (name "/HD17") (class "Default")
      (node (ref "CPU1") (pin "103") (pinfunction "D17_103") (pintype "passive"))
      (node (ref "CT2") (pin "38") (pinfunction "38_38") (pintype "passive"))
      (node (ref "M1") (pin "5") (pinfunction "D17_5") (pintype "passive"))
      (node (ref "M2") (pin "5") (pinfunction "D17_5") (pintype "passive"))
      (node (ref "M3") (pin "5") (pinfunction "D17_5") (pintype "passive"))
      (node (ref "M4") (pin "5") (pinfunction "D17_5") (pintype "passive"))
      (node (ref "U8") (pin "3") (pinfunction "A1_3") (pintype "bidirectional"))
    )
    (net (code "120") (name "/HD18") (class "Default")
      (node (ref "CPU1") (pin "101") (pinfunction "D18_101") (pintype "passive"))
      (node (ref "CT2") (pin "14") (pinfunction "14_14") (pintype "passive"))
      (node (ref "M1") (pin "7") (pinfunction "D18_7") (pintype "passive"))
      (node (ref "M2") (pin "7") (pinfunction "D18_7") (pintype "passive"))
      (node (ref "M3") (pin "7") (pinfunction "D18_7") (pintype "passive"))
      (node (ref "M4") (pin "7") (pinfunction "D18_7") (pintype "passive"))
      (node (ref "U8") (pin "4") (pinfunction "A2_4") (pintype "bidirectional"))
    )
    (net (code "121") (name "/HD19") (class "Default")
      (node (ref "CPU1") (pin "100") (pinfunction "D19_100") (pintype "passive"))
      (node (ref "CT2") (pin "39") (pinfunction "39_39") (pintype "passive"))
      (node (ref "M1") (pin "9") (pinfunction "D19_9") (pintype "passive"))
      (node (ref "M2") (pin "9") (pinfunction "D19_9") (pintype "passive"))
      (node (ref "M3") (pin "9") (pinfunction "D19_9") (pintype "passive"))
      (node (ref "M4") (pin "9") (pinfunction "D19_9") (pintype "passive"))
      (node (ref "U8") (pin "5") (pinfunction "A3_5") (pintype "bidirectional"))
    )
    (net (code "122") (name "/HD20") (class "Default")
      (node (ref "CPU1") (pin "99") (pinfunction "D20_99") (pintype "passive"))
      (node (ref "CT2") (pin "13") (pinfunction "13_13") (pintype "passive"))
      (node (ref "M1") (pin "21") (pinfunction "D20_21") (pintype "passive"))
      (node (ref "M2") (pin "21") (pinfunction "D20_21") (pintype "passive"))
      (node (ref "M3") (pin "21") (pinfunction "D20_21") (pintype "passive"))
      (node (ref "M4") (pin "21") (pinfunction "D20_21") (pintype "passive"))
      (node (ref "U8") (pin "6") (pinfunction "A4_6") (pintype "bidirectional"))
    )
    (net (code "123") (name "/HD21") (class "Default")
      (node (ref "CPU1") (pin "93") (pinfunction "D21_93") (pintype "passive"))
      (node (ref "CT2") (pin "40") (pinfunction "40_40") (pintype "passive"))
      (node (ref "M1") (pin "23") (pinfunction "D21_23") (pintype "passive"))
      (node (ref "M2") (pin "23") (pinfunction "D21_23") (pintype "passive"))
      (node (ref "M3") (pin "23") (pinfunction "D21_23") (pintype "passive"))
      (node (ref "M4") (pin "23") (pinfunction "D21_23") (pintype "passive"))
      (node (ref "U8") (pin "7") (pinfunction "A5_7") (pintype "bidirectional"))
    )
    (net (code "124") (name "/HD22") (class "Default")
      (node (ref "CPU1") (pin "92") (pinfunction "D22_92") (pintype "passive"))
      (node (ref "CT2") (pin "12") (pinfunction "12_12") (pintype "passive"))
      (node (ref "M1") (pin "25") (pinfunction "D22_25") (pintype "passive"))
      (node (ref "M2") (pin "25") (pinfunction "D22_25") (pintype "passive"))
      (node (ref "M3") (pin "25") (pinfunction "D22_25") (pintype "passive"))
      (node (ref "M4") (pin "25") (pinfunction "D22_25") (pintype "passive"))
      (node (ref "U8") (pin "8") (pinfunction "A6_8") (pintype "bidirectional"))
    )
    (net (code "125") (name "/HD23") (class "Default")
      (node (ref "CPU1") (pin "91") (pinfunction "D23_91") (pintype "passive"))
      (node (ref "CT2") (pin "41") (pinfunction "41_41") (pintype "passive"))
      (node (ref "M1") (pin "27") (pinfunction "D23_27") (pintype "passive"))
      (node (ref "M2") (pin "27") (pinfunction "D23_27") (pintype "passive"))
      (node (ref "M3") (pin "27") (pinfunction "D23_27") (pintype "passive"))
      (node (ref "M4") (pin "27") (pinfunction "D23_27") (pintype "passive"))
      (node (ref "U8") (pin "9") (pinfunction "A7_9") (pintype "bidirectional"))
    )
    (net (code "126") (name "/HD24") (class "Default")
      (node (ref "CPU1") (pin "87") (pinfunction "D24_87") (pintype "passive"))
      (node (ref "CT2") (pin "10") (pinfunction "10_10") (pintype "passive"))
      (node (ref "M1") (pin "50") (pinfunction "D24_50") (pintype "passive"))
      (node (ref "M2") (pin "50") (pinfunction "D24_50") (pintype "passive"))
      (node (ref "M3") (pin "50") (pinfunction "D24_50") (pintype "passive"))
      (node (ref "M4") (pin "50") (pinfunction "D24_50") (pintype "passive"))
      (node (ref "U9") (pin "2") (pinfunction "A0_2") (pintype "bidirectional"))
    )
    (net (code "127") (name "/HD25") (class "Default")
      (node (ref "CPU1") (pin "85") (pinfunction "D25_85") (pintype "passive"))
      (node (ref "CT2") (pin "43") (pinfunction "43_43") (pintype "passive"))
      (node (ref "M1") (pin "52") (pinfunction "D25_52") (pintype "passive"))
      (node (ref "M2") (pin "52") (pinfunction "D25_52") (pintype "passive"))
      (node (ref "M3") (pin "52") (pinfunction "D25_52") (pintype "passive"))
      (node (ref "M4") (pin "52") (pinfunction "D25_52") (pintype "passive"))
      (node (ref "U9") (pin "3") (pinfunction "A1_3") (pintype "bidirectional"))
    )
    (net (code "128") (name "/HD26") (class "Default")
      (node (ref "CPU1") (pin "84") (pinfunction "D26_84") (pintype "passive"))
      (node (ref "CT2") (pin "9") (pinfunction "9_9") (pintype "passive"))
      (node (ref "M1") (pin "54") (pinfunction "D26_54") (pintype "passive"))
      (node (ref "M2") (pin "54") (pinfunction "D26_54") (pintype "passive"))
      (node (ref "M3") (pin "54") (pinfunction "D26_54") (pintype "passive"))
      (node (ref "M4") (pin "54") (pinfunction "D26_54") (pintype "passive"))
      (node (ref "U9") (pin "4") (pinfunction "A2_4") (pintype "bidirectional"))
    )
    (net (code "129") (name "/HD27") (class "Default")
      (node (ref "CPU1") (pin "83") (pinfunction "D27_83") (pintype "passive"))
      (node (ref "CT2") (pin "44") (pinfunction "44_44") (pintype "passive"))
      (node (ref "M1") (pin "56") (pinfunction "D27_56") (pintype "passive"))
      (node (ref "M2") (pin "56") (pinfunction "D27_56") (pintype "passive"))
      (node (ref "M3") (pin "56") (pinfunction "D27_56") (pintype "passive"))
      (node (ref "M4") (pin "56") (pinfunction "D27_56") (pintype "passive"))
      (node (ref "U9") (pin "5") (pinfunction "A3_5") (pintype "bidirectional"))
    )
    (net (code "130") (name "/HD28") (class "Default")
      (node (ref "CPU1") (pin "79") (pinfunction "D28_79") (pintype "passive"))
      (node (ref "CT2") (pin "8") (pinfunction "8_8") (pintype "passive"))
      (node (ref "M1") (pin "58") (pinfunction "D28_58") (pintype "passive"))
      (node (ref "M2") (pin "58") (pinfunction "D28_58") (pintype "passive"))
      (node (ref "M3") (pin "58") (pinfunction "D28_58") (pintype "passive"))
      (node (ref "M4") (pin "58") (pinfunction "D28_58") (pintype "passive"))
      (node (ref "U9") (pin "6") (pinfunction "A4_6") (pintype "bidirectional"))
    )
    (net (code "131") (name "/HD29") (class "Default")
      (node (ref "CPU1") (pin "78") (pinfunction "D29_78") (pintype "passive"))
      (node (ref "CT2") (pin "45") (pinfunction "45_45") (pintype "passive"))
      (node (ref "M1") (pin "60") (pinfunction "D29_60") (pintype "passive"))
      (node (ref "M2") (pin "60") (pinfunction "D29_60") (pintype "passive"))
      (node (ref "M3") (pin "60") (pinfunction "D29_60") (pintype "passive"))
      (node (ref "M4") (pin "60") (pinfunction "D29_60") (pintype "passive"))
      (node (ref "U9") (pin "7") (pinfunction "A5_7") (pintype "bidirectional"))
    )
    (net (code "132") (name "/HD30") (class "Default")
      (node (ref "CPU1") (pin "75") (pinfunction "D30_75") (pintype "passive"))
      (node (ref "CT2") (pin "7") (pinfunction "7_7") (pintype "passive"))
      (node (ref "M1") (pin "62") (pinfunction "D30_62") (pintype "passive"))
      (node (ref "M2") (pin "62") (pinfunction "D30_62") (pintype "passive"))
      (node (ref "M3") (pin "62") (pinfunction "D30_62") (pintype "passive"))
      (node (ref "M4") (pin "62") (pinfunction "D30_62") (pintype "passive"))
      (node (ref "U9") (pin "8") (pinfunction "A6_8") (pintype "bidirectional"))
    )
    (net (code "133") (name "/HD31") (class "Default")
      (node (ref "CPU1") (pin "74") (pinfunction "D31_74") (pintype "passive"))
      (node (ref "CT2") (pin "46") (pinfunction "46_46") (pintype "passive"))
      (node (ref "M1") (pin "64") (pinfunction "D31_64") (pintype "passive"))
      (node (ref "M2") (pin "64") (pinfunction "D31_64") (pintype "passive"))
      (node (ref "M3") (pin "64") (pinfunction "D31_64") (pintype "passive"))
      (node (ref "M4") (pin "64") (pinfunction "D31_64") (pintype "passive"))
      (node (ref "U9") (pin "9") (pinfunction "A7_9") (pintype "bidirectional"))
    )
    (net (code "134") (name "/HDRD#") (class "Default")
      (node (ref "RD17") (pin "1") (pinfunction "1_1") (pintype "passive"))
      (node (ref "U13") (pin "5") (pinfunction "HDRD#_5") (pintype "passive"))
    )
    (net (code "135") (name "/HDWE#") (class "Default")
      (node (ref "RD18") (pin "1") (pinfunction "1_1") (pintype "passive"))
      (node (ref "U13") (pin "4") (pinfunction "HDWE#_4") (pintype "passive"))
    )
    (net (code "136") (name "/HITM#") (class "Default")
      (node (ref "CPU1") (pin "63") (pinfunction "HITM#_63") (pintype "passive"))
      (node (ref "R56") (pin "1") (pinfunction "1_1") (pintype "passive"))
      (node (ref "U13") (pin "20") (pinfunction "HITM#_20") (pintype "passive"))
    )
    (net (code "137") (name "/IDE1_CS") (class "Default")
      (node (ref "IDE1") (pin "28") (pinfunction "Cable_select_28") (pintype "passive"))
      (node (ref "R63") (pin "1") (pinfunction "1_1") (pintype "passive"))
    )
    (net (code "138") (name "/IDE1_CS1P") (class "Default")
      (node (ref "IDE1") (pin "37") (pinfunction "Chip_Select_1P_37") (pintype "passive"))
      (node (ref "U16") (pin "14") (pinfunction "B4_14") (pintype "bidirectional"))
    )
    (net (code "139") (name "/IDE1_CS3P") (class "Default")
      (node (ref "IDE1") (pin "38") (pinfunction "Chip_Select_3P_38") (pintype "passive"))
      (node (ref "U16") (pin "18") (pinfunction "B0_18") (pintype "bidirectional"))
    )
    (net (code "140") (name "/IDE2_CS") (class "Default")
      (node (ref "IDE2") (pin "28") (pinfunction "Cable_select_28") (pintype "passive"))
      (node (ref "R64") (pin "1") (pinfunction "1_1") (pintype "passive"))
    )
    (net (code "141") (name "/IDE2_CS1P") (class "Default")
      (node (ref "IDE2") (pin "37") (pinfunction "Chip_Select_1P_37") (pintype "passive"))
      (node (ref "U16") (pin "13") (pinfunction "B5_13") (pintype "bidirectional"))
    )
    (net (code "142") (name "/IDE2_CS3P") (class "Default")
      (node (ref "IDE2") (pin "38") (pinfunction "Chip_Select_3P_38") (pintype "passive"))
      (node (ref "U16") (pin "17") (pinfunction "B1_17") (pintype "bidirectional"))
    )
    (net (code "143") (name "/IDE_D0") (class "Default")
      (node (ref "IDE1") (pin "17") (pinfunction "D0_17") (pintype "passive"))
      (node (ref "IDE2") (pin "17") (pinfunction "D0_17") (pintype "passive"))
      (node (ref "RD1") (pin "2") (pinfunction "2_2") (pintype "passive"))
    )
    (net (code "144") (name "/IDE_D1") (class "Default")
      (node (ref "IDE1") (pin "15") (pinfunction "D1_15") (pintype "passive"))
      (node (ref "IDE2") (pin "15") (pinfunction "D1_15") (pintype "passive"))
      (node (ref "RD2") (pin "2") (pinfunction "2_2") (pintype "passive"))
    )
    (net (code "145") (name "/IDE_D2") (class "Default")
      (node (ref "IDE1") (pin "13") (pinfunction "D2_13") (pintype "passive"))
      (node (ref "IDE2") (pin "13") (pinfunction "D2_13") (pintype "passive"))
      (node (ref "RD3") (pin "2") (pinfunction "2_2") (pintype "passive"))
    )
    (net (code "146") (name "/IDE_D3") (class "Default")
      (node (ref "IDE1") (pin "11") (pinfunction "D3_11") (pintype "passive"))
      (node (ref "IDE2") (pin "11") (pinfunction "D3_11") (pintype "passive"))
      (node (ref "RD4") (pin "2") (pinfunction "2_2") (pintype "passive"))
    )
    (net (code "147") (name "/IDE_D4") (class "Default")
      (node (ref "IDE1") (pin "9") (pinfunction "D4_9") (pintype "passive"))
      (node (ref "IDE2") (pin "9") (pinfunction "D4_9") (pintype "passive"))
      (node (ref "RD5") (pin "2") (pinfunction "2_2") (pintype "passive"))
    )
    (net (code "148") (name "/IDE_D5") (class "Default")
      (node (ref "IDE1") (pin "7") (pinfunction "D5_7") (pintype "passive"))
      (node (ref "IDE2") (pin "7") (pinfunction "D5_7") (pintype "passive"))
      (node (ref "RD6") (pin "2") (pinfunction "2_2") (pintype "passive"))
    )
    (net (code "149") (name "/IDE_D6") (class "Default")
      (node (ref "IDE1") (pin "5") (pinfunction "D6_5") (pintype "passive"))
      (node (ref "IDE2") (pin "5") (pinfunction "D6_5") (pintype "passive"))
      (node (ref "RD7") (pin "2") (pinfunction "2_2") (pintype "passive"))
    )
    (net (code "150") (name "/IDE_D7") (class "Default")
      (node (ref "IDE1") (pin "3") (pinfunction "D7_3") (pintype "passive"))
      (node (ref "IDE2") (pin "3") (pinfunction "D7_3") (pintype "passive"))
      (node (ref "RD8") (pin "2") (pinfunction "2_2") (pintype "passive"))
    )
    (net (code "151") (name "/IDE_D8") (class "Default")
      (node (ref "IDE1") (pin "4") (pinfunction "D8_4") (pintype "passive"))
      (node (ref "IDE2") (pin "4") (pinfunction "D8_4") (pintype "passive"))
      (node (ref "RD9") (pin "2") (pinfunction "2_2") (pintype "passive"))
    )
    (net (code "152") (name "/IDE_D9") (class "Default")
      (node (ref "IDE1") (pin "6") (pinfunction "D9_6") (pintype "passive"))
      (node (ref "IDE2") (pin "6") (pinfunction "D9_6") (pintype "passive"))
      (node (ref "RD10") (pin "2") (pinfunction "2_2") (pintype "passive"))
    )
    (net (code "153") (name "/IDE_D10") (class "Default")
      (node (ref "IDE1") (pin "8") (pinfunction "D10_8") (pintype "passive"))
      (node (ref "IDE2") (pin "8") (pinfunction "D10_8") (pintype "passive"))
      (node (ref "RD11") (pin "2") (pinfunction "2_2") (pintype "passive"))
    )
    (net (code "154") (name "/IDE_D11") (class "Default")
      (node (ref "IDE1") (pin "10") (pinfunction "D11_10") (pintype "passive"))
      (node (ref "IDE2") (pin "10") (pinfunction "D11_10") (pintype "passive"))
      (node (ref "RD12") (pin "2") (pinfunction "2_2") (pintype "passive"))
    )
    (net (code "155") (name "/IDE_D12") (class "Default")
      (node (ref "IDE1") (pin "12") (pinfunction "D12_12") (pintype "passive"))
      (node (ref "IDE2") (pin "12") (pinfunction "D12_12") (pintype "passive"))
      (node (ref "RD13") (pin "2") (pinfunction "2_2") (pintype "passive"))
    )
    (net (code "156") (name "/IDE_D13") (class "Default")
      (node (ref "IDE1") (pin "14") (pinfunction "D13_14") (pintype "passive"))
      (node (ref "IDE2") (pin "14") (pinfunction "D13_14") (pintype "passive"))
      (node (ref "RD14") (pin "2") (pinfunction "2_2") (pintype "passive"))
    )
    (net (code "157") (name "/IDE_D14") (class "Default")
      (node (ref "IDE1") (pin "16") (pinfunction "D14_16") (pintype "passive"))
      (node (ref "IDE2") (pin "16") (pinfunction "D14_16") (pintype "passive"))
      (node (ref "RD15") (pin "2") (pinfunction "2_2") (pintype "passive"))
    )
    (net (code "158") (name "/IDE_D15") (class "Default")
      (node (ref "IDE1") (pin "18") (pinfunction "D15_18") (pintype "passive"))
      (node (ref "IDE2") (pin "18") (pinfunction "D15_18") (pintype "passive"))
      (node (ref "RD16") (pin "2") (pinfunction "2_2") (pintype "passive"))
    )
    (net (code "159") (name "/IDE_HDA0") (class "Default")
      (node (ref "IDE1") (pin "35") (pinfunction "Addr0_35") (pintype "passive"))
      (node (ref "IDE2") (pin "35") (pinfunction "Addr0_35") (pintype "passive"))
      (node (ref "U16") (pin "15") (pinfunction "B3_15") (pintype "bidirectional"))
    )
    (net (code "160") (name "/IDE_HDA1") (class "Default")
      (node (ref "IDE1") (pin "33") (pinfunction "Addr1_33") (pintype "passive"))
      (node (ref "IDE2") (pin "33") (pinfunction "Addr1_33") (pintype "passive"))
      (node (ref "U16") (pin "12") (pinfunction "B6_12") (pintype "bidirectional"))
    )
    (net (code "161") (name "/IDE_HDA2") (class "Default")
      (node (ref "IDE1") (pin "36") (pinfunction "Addr2_36") (pintype "passive"))
      (node (ref "IDE2") (pin "36") (pinfunction "Addr2_36") (pintype "passive"))
      (node (ref "U16") (pin "16") (pinfunction "B2_16") (pintype "bidirectional"))
    )
    (net (code "162") (name "/IDE_IOCS16#") (class "Default")
      (node (ref "IDE1") (pin "32") (pinfunction "~{IOCS16}(NC)_32") (pintype "passive"))
      (node (ref "IDE2") (pin "32") (pinfunction "~{IOCS16}(NC)_32") (pintype "passive"))
      (node (ref "R49") (pin "1") (pinfunction "1_1") (pintype "passive"))
    )
    (net (code "163") (name "/IDE_P20") (class "Default")
      (node (ref "IDE1") (pin "20") (pinfunction "NC_20") (pintype "passive"))
      (node (ref "IDE2") (pin "20") (pinfunction "NC_20") (pintype "passive"))
      (node (ref "JIDE") (pin "1") (pinfunction "1_1") (pintype "passive"))
    )
    (net (code "164") (name "/IDE_RD#") (class "Default")
      (node (ref "IDE1") (pin "25") (pinfunction "~{IOR}_25") (pintype "passive"))
      (node (ref "IDE2") (pin "25") (pinfunction "~{IOR}_25") (pintype "passive"))
      (node (ref "RD17") (pin "2") (pinfunction "2_2") (pintype "passive"))
    )
    (net (code "165") (name "/IDE_WE#") (class "Default")
      (node (ref "IDE1") (pin "23") (pinfunction "~{IOW}_23") (pintype "passive"))
      (node (ref "IDE2") (pin "23") (pinfunction "~{IOW}_23") (pintype "passive"))
      (node (ref "RD18") (pin "2") (pinfunction "2_2") (pintype "passive"))
    )
    (net (code "166") (name "/IGNNE#") (class "Default")
      (node (ref "CPU1") (pin "72") (pinfunction "IGNNE#_72") (pintype "passive"))
      (node (ref "U13") (pin "6") (pinfunction "IGNNE#_6") (pintype "passive"))
    )
    (net (code "167") (name "/INA219_SCL") (class "Default")
      (node (ref "RU20") (pin "2") (pinfunction "2_2") (pintype "passive"))
      (node (ref "RU22") (pin "1") (pinfunction "1_1") (pintype "passive"))
      (node (ref "UM2") (pin "4") (pinfunction "SCL_4") (pintype "passive"))
      (node (ref "UM3") (pin "4") (pinfunction "SCL_4") (pintype "passive"))
      (node (ref "UM4") (pin "4") (pinfunction "SCL_4") (pintype "passive"))
    )
    (net (code "168") (name "/INA219_SDA") (class "Default")
      (node (ref "RU19") (pin "2") (pinfunction "2_2") (pintype "passive"))
      (node (ref "RU21") (pin "1") (pinfunction "1_1") (pintype "passive"))
      (node (ref "UM2") (pin "3") (pinfunction "SDA_3") (pintype "passive"))
      (node (ref "UM3") (pin "3") (pinfunction "SDA_3") (pintype "passive"))
      (node (ref "UM4") (pin "3") (pinfunction "SDA_3") (pintype "passive"))
    )
    (net (code "169") (name "/INTR") (class "Default")
      (node (ref "CPU1") (pin "50") (pinfunction "INTR_50") (pintype "passive"))
      (node (ref "U13") (pin "8") (pinfunction "INTR#_8") (pintype "passive"))
    )
    (net (code "170") (name "/ISA_A0") (class "Default")
      (node (ref "ISA1") (pin "A31") (pinfunction "A0_A31") (pintype "passive"))
      (node (ref "ISA2") (pin "A31") (pinfunction "A0_A31") (pintype "passive"))
      (node (ref "ISA3") (pin "A31") (pinfunction "A0_A31") (pintype "passive"))
      (node (ref "U17") (pin "18") (pinfunction "B0_18") (pintype "bidirectional"))
      (node (ref "U2") (pin "12") (pinfunction "A0_12") (pintype "passive"))
    )
    (net (code "171") (name "/ISA_A1") (class "Default")
      (node (ref "ISA1") (pin "A30") (pinfunction "A1_A30") (pintype "passive"))
      (node (ref "ISA2") (pin "A30") (pinfunction "A1_A30") (pintype "passive"))
      (node (ref "ISA3") (pin "A30") (pinfunction "A1_A30") (pintype "passive"))
      (node (ref "U17") (pin "17") (pinfunction "B1_17") (pintype "bidirectional"))
      (node (ref "U2") (pin "11") (pinfunction "A1_11") (pintype "passive"))
    )
    (net (code "172") (name "/ISA_A2") (class "Default")
      (node (ref "ISA1") (pin "A29") (pinfunction "A2_A29") (pintype "passive"))
      (node (ref "ISA2") (pin "A29") (pinfunction "A2_A29") (pintype "passive"))
      (node (ref "ISA3") (pin "A29") (pinfunction "A2_A29") (pintype "passive"))
      (node (ref "U17") (pin "16") (pinfunction "B2_16") (pintype "bidirectional"))
      (node (ref "U2") (pin "10") (pinfunction "A2_10") (pintype "passive"))
    )
    (net (code "173") (name "/ISA_A3") (class "Default")
      (node (ref "ISA1") (pin "A28") (pinfunction "A3_A28") (pintype "passive"))
      (node (ref "ISA2") (pin "A28") (pinfunction "A3_A28") (pintype "passive"))
      (node (ref "ISA3") (pin "A28") (pinfunction "A3_A28") (pintype "passive"))
      (node (ref "U17") (pin "15") (pinfunction "B3_15") (pintype "bidirectional"))
      (node (ref "U2") (pin "9") (pinfunction "A3_9") (pintype "passive"))
    )
    (net (code "174") (name "/ISA_A4") (class "Default")
      (node (ref "ISA1") (pin "A27") (pinfunction "A4_A27") (pintype "passive"))
      (node (ref "ISA2") (pin "A27") (pinfunction "A4_A27") (pintype "passive"))
      (node (ref "ISA3") (pin "A27") (pinfunction "A4_A27") (pintype "passive"))
      (node (ref "U17") (pin "14") (pinfunction "B4_14") (pintype "bidirectional"))
      (node (ref "U2") (pin "8") (pinfunction "A4_8") (pintype "passive"))
    )
    (net (code "175") (name "/ISA_A5") (class "Default")
      (node (ref "ISA1") (pin "A26") (pinfunction "A5_A26") (pintype "passive"))
      (node (ref "ISA2") (pin "A26") (pinfunction "A5_A26") (pintype "passive"))
      (node (ref "ISA3") (pin "A26") (pinfunction "A5_A26") (pintype "passive"))
      (node (ref "U17") (pin "13") (pinfunction "B5_13") (pintype "bidirectional"))
      (node (ref "U2") (pin "7") (pinfunction "A5_7") (pintype "passive"))
    )
    (net (code "176") (name "/ISA_A6") (class "Default")
      (node (ref "ISA1") (pin "A25") (pinfunction "A6_A25") (pintype "passive"))
      (node (ref "ISA2") (pin "A25") (pinfunction "A6_A25") (pintype "passive"))
      (node (ref "ISA3") (pin "A25") (pinfunction "A6_A25") (pintype "passive"))
      (node (ref "U17") (pin "12") (pinfunction "B6_12") (pintype "bidirectional"))
      (node (ref "U2") (pin "6") (pinfunction "A6_6") (pintype "passive"))
    )
    (net (code "177") (name "/ISA_A7") (class "Default")
      (node (ref "ISA1") (pin "A24") (pinfunction "A7_A24") (pintype "passive"))
      (node (ref "ISA2") (pin "A24") (pinfunction "A7_A24") (pintype "passive"))
      (node (ref "ISA3") (pin "A24") (pinfunction "A7_A24") (pintype "passive"))
      (node (ref "U17") (pin "11") (pinfunction "B7_11") (pintype "bidirectional"))
      (node (ref "U2") (pin "5") (pinfunction "A7_5") (pintype "passive"))
    )
    (net (code "178") (name "/ISA_A8") (class "Default")
      (node (ref "ISA1") (pin "A23") (pinfunction "A8_A23") (pintype "passive"))
      (node (ref "ISA2") (pin "A23") (pinfunction "A8_A23") (pintype "passive"))
      (node (ref "ISA3") (pin "A23") (pinfunction "A8_A23") (pintype "passive"))
      (node (ref "U18") (pin "18") (pinfunction "B0_18") (pintype "bidirectional"))
      (node (ref "U2") (pin "27") (pinfunction "A8_27") (pintype "passive"))
    )
    (net (code "179") (name "/ISA_A9") (class "Default")
      (node (ref "ISA1") (pin "A22") (pinfunction "A9_A22") (pintype "passive"))
      (node (ref "ISA2") (pin "A22") (pinfunction "A9_A22") (pintype "passive"))
      (node (ref "ISA3") (pin "A22") (pinfunction "A9_A22") (pintype "passive"))
      (node (ref "U18") (pin "17") (pinfunction "B1_17") (pintype "bidirectional"))
      (node (ref "U2") (pin "26") (pinfunction "A9_26") (pintype "passive"))
    )
    (net (code "180") (name "/ISA_A10") (class "Default")
      (node (ref "ISA1") (pin "A21") (pinfunction "A10_A21") (pintype "passive"))
      (node (ref "ISA2") (pin "A21") (pinfunction "A10_A21") (pintype "passive"))
      (node (ref "ISA3") (pin "A21") (pinfunction "A10_A21") (pintype "passive"))
      (node (ref "U18") (pin "16") (pinfunction "B2_16") (pintype "bidirectional"))
      (node (ref "U2") (pin "23") (pinfunction "A10_23") (pintype "passive"))
    )
    (net (code "181") (name "/ISA_A11") (class "Default")
      (node (ref "ISA1") (pin "A20") (pinfunction "A11_A20") (pintype "passive"))
      (node (ref "ISA2") (pin "A20") (pinfunction "A11_A20") (pintype "passive"))
      (node (ref "ISA3") (pin "A20") (pinfunction "A11_A20") (pintype "passive"))
      (node (ref "U18") (pin "15") (pinfunction "B3_15") (pintype "bidirectional"))
      (node (ref "U2") (pin "25") (pinfunction "A11_25") (pintype "passive"))
    )
    (net (code "182") (name "/ISA_A12") (class "Default")
      (node (ref "ISA1") (pin "A19") (pinfunction "A12_A19") (pintype "passive"))
      (node (ref "ISA2") (pin "A19") (pinfunction "A12_A19") (pintype "passive"))
      (node (ref "ISA3") (pin "A19") (pinfunction "A12_A19") (pintype "passive"))
      (node (ref "U18") (pin "14") (pinfunction "B4_14") (pintype "bidirectional"))
      (node (ref "U2") (pin "4") (pinfunction "A12_4") (pintype "passive"))
    )
    (net (code "183") (name "/ISA_A13") (class "Default")
      (node (ref "ISA1") (pin "A18") (pinfunction "A13_A18") (pintype "passive"))
      (node (ref "ISA2") (pin "A18") (pinfunction "A13_A18") (pintype "passive"))
      (node (ref "ISA3") (pin "A18") (pinfunction "A13_A18") (pintype "passive"))
      (node (ref "U18") (pin "13") (pinfunction "B5_13") (pintype "bidirectional"))
      (node (ref "U2") (pin "28") (pinfunction "A13_28") (pintype "passive"))
    )
    (net (code "184") (name "/ISA_A14") (class "Default")
      (node (ref "ISA1") (pin "A17") (pinfunction "A14_A17") (pintype "passive"))
      (node (ref "ISA2") (pin "A17") (pinfunction "A14_A17") (pintype "passive"))
      (node (ref "ISA3") (pin "A17") (pinfunction "A14_A17") (pintype "passive"))
      (node (ref "U18") (pin "12") (pinfunction "B6_12") (pintype "bidirectional"))
      (node (ref "U2") (pin "29") (pinfunction "A14_29") (pintype "passive"))
    )
    (net (code "185") (name "/ISA_A15") (class "Default")
      (node (ref "ISA1") (pin "A16") (pinfunction "A15_A16") (pintype "passive"))
      (node (ref "ISA2") (pin "A16") (pinfunction "A15_A16") (pintype "passive"))
      (node (ref "ISA3") (pin "A16") (pinfunction "A15_A16") (pintype "passive"))
      (node (ref "U18") (pin "11") (pinfunction "B7_11") (pintype "bidirectional"))
      (node (ref "U2") (pin "3") (pinfunction "A15_3") (pintype "passive"))
    )
    (net (code "186") (name "/ISA_A16") (class "Default")
      (node (ref "ISA1") (pin "A15") (pinfunction "A16_A15") (pintype "passive"))
      (node (ref "ISA2") (pin "A15") (pinfunction "A16_A15") (pintype "passive"))
      (node (ref "ISA3") (pin "A15") (pinfunction "A16_A15") (pintype "passive"))
      (node (ref "RP54") (pin "2") (pinfunction "2_2") (pintype "passive"))
      (node (ref "U2") (pin "2") (pinfunction "A16_2") (pintype "passive"))
    )
    (net (code "187") (name "/ISA_A17") (class "Default")
      (node (ref "ISA1") (pin "A14") (pinfunction "A17_A14") (pintype "passive"))
      (node (ref "ISA2") (pin "A14") (pinfunction "A17_A14") (pintype "passive"))
      (node (ref "ISA3") (pin "A14") (pinfunction "A17_A14") (pintype "passive"))
      (node (ref "RP53") (pin "2") (pinfunction "2_2") (pintype "passive"))
    )
    (net (code "188") (name "/ISA_A18") (class "Default")
      (node (ref "ISA1") (pin "A13") (pinfunction "A18_A13") (pintype "passive"))
      (node (ref "ISA2") (pin "A13") (pinfunction "A18_A13") (pintype "passive"))
      (node (ref "ISA3") (pin "A13") (pinfunction "A18_A13") (pintype "passive"))
      (node (ref "RP52") (pin "2") (pinfunction "2_2") (pintype "passive"))
    )
    (net (code "189") (name "/ISA_A19") (class "Default")
      (node (ref "ISA1") (pin "A12") (pinfunction "A19_A12") (pintype "passive"))
      (node (ref "ISA2") (pin "A12") (pinfunction "A19_A12") (pintype "passive"))
      (node (ref "ISA3") (pin "A12") (pinfunction "A19_A12") (pintype "passive"))
      (node (ref "RP51") (pin "2") (pinfunction "2_2") (pintype "passive"))
    )
    (net (code "190") (name "/ISA_AEN") (class "Default")
      (node (ref "ISA1") (pin "A11") (pinfunction "AEN_A11") (pintype "passive"))
      (node (ref "ISA2") (pin "A11") (pinfunction "AEN_A11") (pintype "passive"))
      (node (ref "ISA3") (pin "A11") (pinfunction "AEN_A11") (pintype "passive"))
      (node (ref "RN78") (pin "1") (pinfunction "1_1") (pintype "passive"))
      (node (ref "U13") (pin "159") (pinfunction "AEN_159") (pintype "passive"))
    )
    (net (code "191") (name "/ISA_ALE") (class "Default")
      (node (ref "ISA1") (pin "B28") (pinfunction "ALE_B28") (pintype "passive"))
      (node (ref "ISA2") (pin "B28") (pinfunction "ALE_B28") (pintype "passive"))
      (node (ref "ISA3") (pin "B28") (pinfunction "ALE_B28") (pintype "passive"))
      (node (ref "R33") (pin "1") (pinfunction "1_1") (pintype "passive"))
    )
    (net (code "192") (name "/ISA_B8") (class "Default")
      (node (ref "ISA1") (pin "B08") (pinfunction "NC_B08") (pintype "passive"))
      (node (ref "ISA2") (pin "B08") (pinfunction "NC_B08") (pintype "passive"))
      (node (ref "ISA3") (pin "B08") (pinfunction "NC_B08") (pintype "passive"))
      (node (ref "RN72") (pin "1") (pinfunction "1_1") (pintype "passive"))
    )
    (net (code "193") (name "/ISA_BHE#") (class "Default")
      (node (ref "ISA1") (pin "C1") (pinfunction "BHE_C1") (pintype "passive"))
      (node (ref "ISA2") (pin "C1") (pinfunction "BHE_C1") (pintype "passive"))
      (node (ref "ISA3") (pin "C1") (pinfunction "BHE_C1") (pintype "passive"))
      (node (ref "RN77") (pin "1") (pinfunction "1_1") (pintype "passive"))
      (node (ref "RP61") (pin "2") (pinfunction "2_2") (pintype "passive"))
    )
    (net (code "194") (name "/ISA_CLK") (class "Default")
      (node (ref "ISA1") (pin "B20") (pinfunction "CLOCK_B20") (pintype "passive"))
      (node (ref "ISA2") (pin "B20") (pinfunction "CLOCK_B20") (pintype "passive"))
      (node (ref "ISA3") (pin "B20") (pinfunction "CLOCK_B20") (pintype "passive"))
      (node (ref "R35") (pin "1") (pinfunction "1_1") (pintype "passive"))
      (node (ref "U10") (pin "2") (pinfunction "A1_2") (pintype "input"))
      (node (ref "U5") (pin "2") (pinfunction "A1_2") (pintype "input"))
    )
    (net (code "195") (name "/ISA_D0") (class "Default")
      (node (ref "ISA1") (pin "A09") (pinfunction "D0_A09") (pintype "passive"))
      (node (ref "ISA2") (pin "A09") (pinfunction "D0_A09") (pintype "passive"))
      (node (ref "ISA3") (pin "A09") (pinfunction "D0_A09") (pintype "passive"))
      (node (ref "RD19") (pin "2") (pinfunction "2_2") (pintype "passive"))
      (node (ref "U2") (pin "13") (pinfunction "I/O0_13") (pintype "passive"))
    )
    (net (code "196") (name "/ISA_D1") (class "Default")
      (node (ref "ISA1") (pin "A08") (pinfunction "D1_A08") (pintype "passive"))
      (node (ref "ISA2") (pin "A08") (pinfunction "D1_A08") (pintype "passive"))
      (node (ref "ISA3") (pin "A08") (pinfunction "D1_A08") (pintype "passive"))
      (node (ref "RD20") (pin "2") (pinfunction "2_2") (pintype "passive"))
      (node (ref "U2") (pin "14") (pinfunction "I/O1_14") (pintype "passive"))
    )
    (net (code "197") (name "/ISA_D2") (class "Default")
      (node (ref "ISA1") (pin "A07") (pinfunction "D2_A07") (pintype "passive"))
      (node (ref "ISA2") (pin "A07") (pinfunction "D2_A07") (pintype "passive"))
      (node (ref "ISA3") (pin "A07") (pinfunction "D2_A07") (pintype "passive"))
      (node (ref "RD21") (pin "2") (pinfunction "2_2") (pintype "passive"))
      (node (ref "U2") (pin "15") (pinfunction "I/O2_15") (pintype "passive"))
    )
    (net (code "198") (name "/ISA_D3") (class "Default")
      (node (ref "ISA1") (pin "A06") (pinfunction "D3_A06") (pintype "passive"))
      (node (ref "ISA2") (pin "A06") (pinfunction "D3_A06") (pintype "passive"))
      (node (ref "ISA3") (pin "A06") (pinfunction "D3_A06") (pintype "passive"))
      (node (ref "RD22") (pin "2") (pinfunction "2_2") (pintype "passive"))
      (node (ref "U2") (pin "17") (pinfunction "I/O3_17") (pintype "passive"))
    )
    (net (code "199") (name "/ISA_D4") (class "Default")
      (node (ref "ISA1") (pin "A05") (pinfunction "D4_A05") (pintype "passive"))
      (node (ref "ISA2") (pin "A05") (pinfunction "D4_A05") (pintype "passive"))
      (node (ref "ISA3") (pin "A05") (pinfunction "D4_A05") (pintype "passive"))
      (node (ref "RD23") (pin "2") (pinfunction "2_2") (pintype "passive"))
      (node (ref "U2") (pin "18") (pinfunction "I/O4_18") (pintype "passive"))
    )
    (net (code "200") (name "/ISA_D5") (class "Default")
      (node (ref "ISA1") (pin "A04") (pinfunction "D5_A04") (pintype "passive"))
      (node (ref "ISA2") (pin "A04") (pinfunction "D5_A04") (pintype "passive"))
      (node (ref "ISA3") (pin "A04") (pinfunction "D5_A04") (pintype "passive"))
      (node (ref "RD24") (pin "2") (pinfunction "2_2") (pintype "passive"))
      (node (ref "U2") (pin "19") (pinfunction "I/O5_19") (pintype "passive"))
    )
    (net (code "201") (name "/ISA_D6") (class "Default")
      (node (ref "ISA1") (pin "A03") (pinfunction "D6_A03") (pintype "passive"))
      (node (ref "ISA2") (pin "A03") (pinfunction "D6_A03") (pintype "passive"))
      (node (ref "ISA3") (pin "A03") (pinfunction "D6_A03") (pintype "passive"))
      (node (ref "RD25") (pin "2") (pinfunction "2_2") (pintype "passive"))
      (node (ref "U2") (pin "20") (pinfunction "I/O6_20") (pintype "passive"))
    )
    (net (code "202") (name "/ISA_D7") (class "Default")
      (node (ref "ISA1") (pin "A02") (pinfunction "D7_A02") (pintype "passive"))
      (node (ref "ISA2") (pin "A02") (pinfunction "D7_A02") (pintype "passive"))
      (node (ref "ISA3") (pin "A02") (pinfunction "D7_A02") (pintype "passive"))
      (node (ref "RD26") (pin "2") (pinfunction "2_2") (pintype "passive"))
      (node (ref "U2") (pin "21") (pinfunction "I/O7_21") (pintype "passive"))
    )
    (net (code "203") (name "/ISA_D8") (class "Default")
      (node (ref "ISA1") (pin "C11") (pinfunction "D8_C11") (pintype "passive"))
      (node (ref "ISA2") (pin "C11") (pinfunction "D8_C11") (pintype "passive"))
      (node (ref "ISA3") (pin "C11") (pinfunction "D8_C11") (pintype "passive"))
      (node (ref "RD27") (pin "2") (pinfunction "2_2") (pintype "passive"))
    )
    (net (code "204") (name "/ISA_D9") (class "Default")
      (node (ref "ISA1") (pin "C12") (pinfunction "D9_C12") (pintype "passive"))
      (node (ref "ISA2") (pin "C12") (pinfunction "D9_C12") (pintype "passive"))
      (node (ref "ISA3") (pin "C12") (pinfunction "D9_C12") (pintype "passive"))
      (node (ref "RD28") (pin "2") (pinfunction "2_2") (pintype "passive"))
    )
    (net (code "205") (name "/ISA_D10") (class "Default")
      (node (ref "ISA1") (pin "C13") (pinfunction "D10_C13") (pintype "passive"))
      (node (ref "ISA2") (pin "C13") (pinfunction "D10_C13") (pintype "passive"))
      (node (ref "ISA3") (pin "C13") (pinfunction "D10_C13") (pintype "passive"))
      (node (ref "RD29") (pin "2") (pinfunction "2_2") (pintype "passive"))
    )
    (net (code "206") (name "/ISA_D11") (class "Default")
      (node (ref "ISA1") (pin "C14") (pinfunction "D11_C14") (pintype "passive"))
      (node (ref "ISA2") (pin "C14") (pinfunction "D11_C14") (pintype "passive"))
      (node (ref "ISA3") (pin "C14") (pinfunction "D11_C14") (pintype "passive"))
      (node (ref "RD30") (pin "2") (pinfunction "2_2") (pintype "passive"))
    )
    (net (code "207") (name "/ISA_D12") (class "Default")
      (node (ref "ISA1") (pin "C15") (pinfunction "D12_C15") (pintype "passive"))
      (node (ref "ISA2") (pin "C15") (pinfunction "D12_C15") (pintype "passive"))
      (node (ref "ISA3") (pin "C15") (pinfunction "D12_C15") (pintype "passive"))
      (node (ref "RD31") (pin "2") (pinfunction "2_2") (pintype "passive"))
    )
    (net (code "208") (name "/ISA_D13") (class "Default")
      (node (ref "ISA1") (pin "C16") (pinfunction "D13_C16") (pintype "passive"))
      (node (ref "ISA2") (pin "C16") (pinfunction "D13_C16") (pintype "passive"))
      (node (ref "ISA3") (pin "C16") (pinfunction "D13_C16") (pintype "passive"))
      (node (ref "RD32") (pin "2") (pinfunction "2_2") (pintype "passive"))
    )
    (net (code "209") (name "/ISA_D14") (class "Default")
      (node (ref "ISA1") (pin "C17") (pinfunction "D14_C17") (pintype "passive"))
      (node (ref "ISA2") (pin "C17") (pinfunction "D14_C17") (pintype "passive"))
      (node (ref "ISA3") (pin "C17") (pinfunction "D14_C17") (pintype "passive"))
      (node (ref "RD33") (pin "2") (pinfunction "2_2") (pintype "passive"))
    )
    (net (code "210") (name "/ISA_D15") (class "Default")
      (node (ref "ISA1") (pin "C18") (pinfunction "D15_C18") (pintype "passive"))
      (node (ref "ISA2") (pin "C18") (pinfunction "D15_C18") (pintype "passive"))
      (node (ref "ISA3") (pin "C18") (pinfunction "D15_C18") (pintype "passive"))
      (node (ref "RD34") (pin "2") (pinfunction "2_2") (pintype "passive"))
    )
    (net (code "211") (name "/ISA_DACK#0") (class "Default")
      (node (ref "ISA1") (pin "D8") (pinfunction "~{DACK}0_D8") (pintype "passive"))
      (node (ref "ISA2") (pin "D8") (pinfunction "~{DACK}0_D8") (pintype "passive"))
      (node (ref "ISA3") (pin "D8") (pinfunction "~{DACK}0_D8") (pintype "passive"))
      (node (ref "U13") (pin "193") (pinfunction "DACK0#_193") (pintype "passive"))
    )
    (net (code "212") (name "/ISA_DACK#1") (class "Default")
      (node (ref "ISA1") (pin "B17") (pinfunction "~{DACK1}_B17") (pintype "passive"))
      (node (ref "ISA2") (pin "B17") (pinfunction "~{DACK1}_B17") (pintype "passive"))
      (node (ref "ISA3") (pin "B17") (pinfunction "~{DACK1}_B17") (pintype "passive"))
      (node (ref "U13") (pin "169") (pinfunction "DACK1#_169") (pintype "passive"))
    )
    (net (code "213") (name "/ISA_DACK#2") (class "Default")
      (node (ref "ISA1") (pin "B26") (pinfunction "~{DACK2}_B26") (pintype "passive"))
      (node (ref "ISA2") (pin "B26") (pinfunction "~{DACK2}_B26") (pintype "passive"))
      (node (ref "ISA3") (pin "B26") (pinfunction "~{DACK2}_B26") (pintype "passive"))
      (node (ref "U13") (pin "182") (pinfunction "DACK2#_182") (pintype "passive"))
    )
    (net (code "214") (name "/ISA_DACK#3") (class "Default")
      (node (ref "ISA1") (pin "B15") (pinfunction "~{DACK3}_B15") (pintype "passive"))
      (node (ref "ISA2") (pin "B15") (pinfunction "~{DACK3}_B15") (pintype "passive"))
      (node (ref "ISA3") (pin "B15") (pinfunction "~{DACK3}_B15") (pintype "passive"))
      (node (ref "U13") (pin "164") (pinfunction "DACK3#_164") (pintype "passive"))
    )
    (net (code "215") (name "/ISA_DACK#5") (class "Default")
      (node (ref "ISA1") (pin "D10") (pinfunction "~{DACK5}_D10") (pintype "passive"))
      (node (ref "ISA2") (pin "D10") (pinfunction "~{DACK5}_D10") (pintype "passive"))
      (node (ref "ISA3") (pin "D10") (pinfunction "~{DACK5}_D10") (pintype "passive"))
      (node (ref "U13") (pin "197") (pinfunction "DACK5#_197") (pintype "passive"))
    )
    (net (code "216") (name "/ISA_DACK#6") (class "Default")
      (node (ref "ISA1") (pin "D12") (pinfunction "~{DACK6}_D12") (pintype "passive"))
      (node (ref "ISA2") (pin "D12") (pinfunction "~{DACK6}_D12") (pintype "passive"))
      (node (ref "ISA3") (pin "D12") (pinfunction "~{DACK6}_D12") (pintype "passive"))
      (node (ref "U13") (pin "199") (pinfunction "DACK6#_199") (pintype "passive"))
    )
    (net (code "217") (name "/ISA_DACK#7") (class "Default")
      (node (ref "ISA1") (pin "D14") (pinfunction "~{DACK7}_D14") (pintype "passive"))
      (node (ref "ISA2") (pin "D14") (pinfunction "~{DACK7}_D14") (pintype "passive"))
      (node (ref "ISA3") (pin "D14") (pinfunction "~{DACK7}_D14") (pintype "passive"))
      (node (ref "U13") (pin "201") (pinfunction "DACK7#_201") (pintype "passive"))
    )
    (net (code "218") (name "/ISA_DRQ0") (class "Default")
      (node (ref "ISA1") (pin "D9") (pinfunction "DRQ0_D9") (pintype "passive"))
      (node (ref "ISA2") (pin "D9") (pinfunction "DRQ0_D9") (pintype "passive"))
      (node (ref "ISA3") (pin "D9") (pinfunction "DRQ0_D9") (pintype "passive"))
      (node (ref "R100") (pin "1") (pinfunction "1_1") (pintype "passive"))
      (node (ref "U13") (pin "195") (pinfunction "DREQ0_195") (pintype "passive"))
    )
    (net (code "219") (name "/ISA_DRQ1") (class "Default")
      (node (ref "ISA1") (pin "B18") (pinfunction "DRQ1_B18") (pintype "passive"))
      (node (ref "ISA2") (pin "B18") (pinfunction "DRQ1_B18") (pintype "passive"))
      (node (ref "ISA3") (pin "B18") (pinfunction "DRQ1_B18") (pintype "passive"))
      (node (ref "R101") (pin "1") (pinfunction "1_1") (pintype "passive"))
      (node (ref "U13") (pin "171") (pinfunction "DREQ1_171") (pintype "passive"))
    )
    (net (code "220") (name "/ISA_DRQ2") (class "Default")
      (node (ref "D1") (pin "K") (pinfunction "K_K") (pintype "passive"))
      (node (ref "ISA1") (pin "B06") (pinfunction "DRQ2_B06") (pintype "passive"))
      (node (ref "ISA2") (pin "B06") (pinfunction "DRQ2_B06") (pintype "passive"))
      (node (ref "ISA3") (pin "B06") (pinfunction "DRQ2_B06") (pintype "passive"))
      (node (ref "R102") (pin "1") (pinfunction "1_1") (pintype "passive"))
      (node (ref "U13") (pin "157") (pinfunction "DREQ2_157") (pintype "passive"))
    )
    (net (code "221") (name "/ISA_DRQ3") (class "Default")
      (node (ref "ISA1") (pin "B16") (pinfunction "DRQ3_B16") (pintype "passive"))
      (node (ref "ISA2") (pin "B16") (pinfunction "DRQ3_B16") (pintype "passive"))
      (node (ref "ISA3") (pin "B16") (pinfunction "DRQ3_B16") (pintype "passive"))
      (node (ref "R103") (pin "1") (pinfunction "1_1") (pintype "passive"))
      (node (ref "U13") (pin "167") (pinfunction "DREQ3_167") (pintype "passive"))
    )
    (net (code "222") (name "/ISA_DRQ5") (class "Default")
      (node (ref "ISA1") (pin "D11") (pinfunction "DRQ5_D11") (pintype "passive"))
      (node (ref "ISA2") (pin "D11") (pinfunction "DRQ5_D11") (pintype "passive"))
      (node (ref "ISA3") (pin "D11") (pinfunction "DRQ5_D11") (pintype "passive"))
      (node (ref "R105") (pin "1") (pinfunction "1_1") (pintype "passive"))
      (node (ref "U13") (pin "198") (pinfunction "DREQ5_198") (pintype "passive"))
    )
    (net (code "223") (name "/ISA_DRQ6") (class "Default")
      (node (ref "ISA1") (pin "D13") (pinfunction "DRQ6_D13") (pintype "passive"))
      (node (ref "ISA2") (pin "D13") (pinfunction "DRQ6_D13") (pintype "passive"))
      (node (ref "ISA3") (pin "D13") (pinfunction "DRQ6_D13") (pintype "passive"))
      (node (ref "R106") (pin "1") (pinfunction "1_1") (pintype "passive"))
      (node (ref "U13") (pin "200") (pinfunction "DREQ6_200") (pintype "passive"))
    )
    (net (code "224") (name "/ISA_DRQ7") (class "Default")
      (node (ref "ISA1") (pin "D15") (pinfunction "DRQ7_D15") (pintype "passive"))
      (node (ref "ISA2") (pin "D15") (pinfunction "DRQ7_D15") (pintype "passive"))
      (node (ref "ISA3") (pin "D15") (pinfunction "DRQ7_D15") (pintype "passive"))
      (node (ref "R107") (pin "1") (pinfunction "1_1") (pintype "passive"))
      (node (ref "U13") (pin "202") (pinfunction "DREQ7_202") (pintype "passive"))
    )
    (net (code "225") (name "/ISA_IOCHCK#") (class "Default")
      (node (ref "ISA1") (pin "A01") (pinfunction "~{I/O_CH_CK}_A01") (pintype "passive"))
      (node (ref "ISA2") (pin "A01") (pinfunction "~{I/O_CH_CK}_A01") (pintype "passive"))
      (node (ref "ISA3") (pin "A01") (pinfunction "~{I/O_CH_CK}_A01") (pintype "passive"))
      (node (ref "R3") (pin "1") (pinfunction "1_1") (pintype "passive"))
    )
    (net (code "226") (name "/ISA_IOCHRDY") (class "Default")
      (node (ref "IDE1") (pin "27") (pinfunction "IOCHRDY_27") (pintype "passive"))
      (node (ref "IDE2") (pin "27") (pinfunction "IOCHRDY_27") (pintype "passive"))
      (node (ref "ISA1") (pin "A10") (pinfunction "I/O_CH_RDY_A10") (pintype "passive"))
      (node (ref "ISA2") (pin "A10") (pinfunction "I/O_CH_RDY_A10") (pintype "passive"))
      (node (ref "ISA3") (pin "A10") (pinfunction "I/O_CH_RDY_A10") (pintype "passive"))
      (node (ref "R8") (pin "1") (pinfunction "1_1") (pintype "passive"))
      (node (ref "U13") (pin "158") (pinfunction "IOCHRDY_158") (pintype "passive"))
    )
    (net (code "227") (name "/ISA_IOCS16#") (class "Default")
      (node (ref "ISA1") (pin "D2") (pinfunction "~{IOCS16}_D2") (pintype "passive"))
      (node (ref "ISA2") (pin "D2") (pinfunction "~{IOCS16}_D2") (pintype "passive"))
      (node (ref "ISA3") (pin "D2") (pinfunction "~{IOCS16}_D2") (pintype "passive"))
      (node (ref "RN74") (pin "1") (pinfunction "1_1") (pintype "passive"))
      (node (ref "U13") (pin "192") (pinfunction "IOCS16#_192") (pintype "passive"))
    )
    (net (code "228") (name "/ISA_IOR#") (class "Default")
      (node (ref "ISA1") (pin "B14") (pinfunction "~{IOR}_B14") (pintype "passive"))
      (node (ref "ISA2") (pin "B14") (pinfunction "~{IOR}_B14") (pintype "passive"))
      (node (ref "ISA3") (pin "B14") (pinfunction "~{IOR}_B14") (pintype "passive"))
      (node (ref "RN82") (pin "1") (pinfunction "1_1") (pintype "passive"))
      (node (ref "RP23") (pin "1") (pinfunction "1_1") (pintype "passive"))
    )
    (net (code "229") (name "/ISA_IOW#") (class "Default")
      (node (ref "ISA1") (pin "B13") (pinfunction "~{IOW}_B13") (pintype "passive"))
      (node (ref "ISA2") (pin "B13") (pinfunction "~{IOW}_B13") (pintype "passive"))
      (node (ref "ISA3") (pin "B13") (pinfunction "~{IOW}_B13") (pintype "passive"))
      (node (ref "RN81") (pin "1") (pinfunction "1_1") (pintype "passive"))
      (node (ref "RP24") (pin "1") (pinfunction "1_1") (pintype "passive"))
    )
    (net (code "230") (name "/ISA_IRQ2") (class "Default")
      (node (ref "ISA1") (pin "B04") (pinfunction "IRQ2_B04") (pintype "passive"))
      (node (ref "ISA2") (pin "B04") (pinfunction "IRQ2_B04") (pintype "passive"))
      (node (ref "ISA3") (pin "B04") (pinfunction "IRQ2_B04") (pintype "passive"))
      (node (ref "RQ1") (pin "1") (pinfunction "1_1") (pintype "passive"))
      (node (ref "U10") (pin "5") (pinfunction "1C1_5") (pintype "input"))
    )
    (net (code "231") (name "/ISA_IRQ3") (class "Default")
      (node (ref "ISA1") (pin "B25") (pinfunction "IRQ3_B25") (pintype "passive"))
      (node (ref "ISA2") (pin "B25") (pinfunction "IRQ3_B25") (pintype "passive"))
      (node (ref "ISA3") (pin "B25") (pinfunction "IRQ3_B25") (pintype "passive"))
      (node (ref "RQ2") (pin "1") (pinfunction "1_1") (pintype "passive"))
      (node (ref "U5") (pin "10") (pinfunction "2C0_10") (pintype "input"))
    )
    (net (code "232") (name "/ISA_IRQ4") (class "Default")
      (node (ref "ISA1") (pin "B24") (pinfunction "IRQ4_B24") (pintype "passive"))
      (node (ref "ISA2") (pin "B24") (pinfunction "IRQ4_B24") (pintype "passive"))
      (node (ref "ISA3") (pin "B24") (pinfunction "IRQ4_B24") (pintype "passive"))
      (node (ref "RQ3") (pin "1") (pinfunction "1_1") (pintype "passive"))
      (node (ref "U5") (pin "11") (pinfunction "2C1_11") (pintype "input"))
    )
    (net (code "233") (name "/ISA_IRQ5") (class "Default")
      (node (ref "ISA1") (pin "B23") (pinfunction "IRQ5_B23") (pintype "passive"))
      (node (ref "ISA2") (pin "B23") (pinfunction "IRQ5_B23") (pintype "passive"))
      (node (ref "ISA3") (pin "B23") (pinfunction "IRQ5_B23") (pintype "passive"))
      (node (ref "RQ4") (pin "1") (pinfunction "1_1") (pintype "passive"))
      (node (ref "U5") (pin "12") (pinfunction "2C2_12") (pintype "input"))
    )
    (net (code "234") (name "/ISA_IRQ6") (class "Default")
      (node (ref "ISA1") (pin "B22") (pinfunction "IRQ6_B22") (pintype "passive"))
      (node (ref "ISA2") (pin "B22") (pinfunction "IRQ6_B22") (pintype "passive"))
      (node (ref "ISA3") (pin "B22") (pinfunction "IRQ6_B22") (pintype "passive"))
      (node (ref "RQ5") (pin "1") (pinfunction "1_1") (pintype "passive"))
      (node (ref "U5") (pin "13") (pinfunction "2C3_13") (pintype "input"))
    )
    (net (code "235") (name "/ISA_IRQ7") (class "Default")
      (node (ref "ISA1") (pin "B21") (pinfunction "IRQ7_B21") (pintype "passive"))
      (node (ref "ISA2") (pin "B21") (pinfunction "IRQ7_B21") (pintype "passive"))
      (node (ref "ISA3") (pin "B21") (pinfunction "IRQ7_B21") (pintype "passive"))
      (node (ref "RQ6") (pin "1") (pinfunction "1_1") (pintype "passive"))
      (node (ref "U10") (pin "6") (pinfunction "1C0_6") (pintype "input"))
    )
    (net (code "236") (name "/ISA_IRQ10") (class "Default")
      (node (ref "ISA1") (pin "D3") (pinfunction "IRQ10_D3") (pintype "passive"))
      (node (ref "ISA2") (pin "D3") (pinfunction "IRQ10_D3") (pintype "passive"))
      (node (ref "ISA3") (pin "D3") (pinfunction "IRQ10_D3") (pintype "passive"))
      (node (ref "RQ7") (pin "1") (pinfunction "1_1") (pintype "passive"))
      (node (ref "U10") (pin "4") (pinfunction "1C2_4") (pintype "input"))
    )
    (net (code "237") (name "/ISA_IRQ11") (class "Default")
      (node (ref "ISA1") (pin "D4") (pinfunction "IRQ11_D4") (pintype "passive"))
      (node (ref "ISA2") (pin "D4") (pinfunction "IRQ11_D4") (pintype "passive"))
      (node (ref "ISA3") (pin "D4") (pinfunction "IRQ11_D4") (pintype "passive"))
      (node (ref "RQ8") (pin "1") (pinfunction "1_1") (pintype "passive"))
      (node (ref "U10") (pin "3") (pinfunction "1C3_3") (pintype "input"))
    )
    (net (code "238") (name "/ISA_IRQ12") (class "Default")
      (node (ref "ISA1") (pin "D5") (pinfunction "IRQ12_D5") (pintype "passive"))
      (node (ref "ISA2") (pin "D5") (pinfunction "IRQ12_D5") (pintype "passive"))
      (node (ref "ISA3") (pin "D5") (pinfunction "IRQ12_D5") (pintype "passive"))
      (node (ref "RQ9") (pin "1") (pinfunction "1_1") (pintype "passive"))
      (node (ref "U10") (pin "10") (pinfunction "2C0_10") (pintype "input"))
    )
    (net (code "239") (name "/ISA_IRQ14") (class "Default")
      (node (ref "IDE2") (pin "31") (pinfunction "IRQ_31") (pintype "passive"))
      (node (ref "ISA1") (pin "D7") (pinfunction "IRQ14_D7") (pintype "passive"))
      (node (ref "ISA2") (pin "D7") (pinfunction "IRQ14_D7") (pintype "passive"))
      (node (ref "ISA3") (pin "D7") (pinfunction "IRQ14_D7") (pintype "passive"))
      (node (ref "RQ10") (pin "1") (pinfunction "1_1") (pintype "passive"))
      (node (ref "U10") (pin "11") (pinfunction "2C1_11") (pintype "input"))
    )
    (net (code "240") (name "/ISA_IRQ15") (class "Default")
      (node (ref "IDE1") (pin "31") (pinfunction "IRQ_31") (pintype "passive"))
      (node (ref "ISA1") (pin "D6") (pinfunction "IRQ15_D6") (pintype "passive"))
      (node (ref "ISA2") (pin "D6") (pinfunction "IRQ15_D6") (pintype "passive"))
      (node (ref "ISA3") (pin "D6") (pinfunction "IRQ15_D6") (pintype "passive"))
      (node (ref "RQ11") (pin "1") (pinfunction "1_1") (pintype "passive"))
      (node (ref "U10") (pin "12") (pinfunction "2C2_12") (pintype "input"))
    )
    (net (code "241") (name "/ISA_LA17") (class "Default")
      (node (ref "ISA1") (pin "C8") (pinfunction "A17_C8") (pintype "passive"))
      (node (ref "ISA2") (pin "C8") (pinfunction "A17_C8") (pintype "passive"))
      (node (ref "ISA3") (pin "C8") (pinfunction "A17_C8") (pintype "passive"))
      (node (ref "RP74") (pin "2") (pinfunction "2_2") (pintype "passive"))
    )
    (net (code "242") (name "/ISA_LA18") (class "Default")
      (node (ref "ISA1") (pin "C7") (pinfunction "A18_C7") (pintype "passive"))
      (node (ref "ISA2") (pin "C7") (pinfunction "A18_C7") (pintype "passive"))
      (node (ref "ISA3") (pin "C7") (pinfunction "A18_C7") (pintype "passive"))
      (node (ref "RP73") (pin "2") (pinfunction "2_2") (pintype "passive"))
    )
    (net (code "243") (name "/ISA_LA19") (class "Default")
      (node (ref "ISA1") (pin "C6") (pinfunction "A19_C6") (pintype "passive"))
      (node (ref "ISA2") (pin "C6") (pinfunction "A19_C6") (pintype "passive"))
      (node (ref "ISA3") (pin "C6") (pinfunction "A19_C6") (pintype "passive"))
      (node (ref "RP72") (pin "2") (pinfunction "2_2") (pintype "passive"))
    )
    (net (code "244") (name "/ISA_LA20") (class "Default")
      (node (ref "ISA1") (pin "C5") (pinfunction "A20_C5") (pintype "passive"))
      (node (ref "ISA2") (pin "C5") (pinfunction "A20_C5") (pintype "passive"))
      (node (ref "ISA3") (pin "C5") (pinfunction "A20_C5") (pintype "passive"))
      (node (ref "RP71") (pin "2") (pinfunction "2_2") (pintype "passive"))
    )
    (net (code "245") (name "/ISA_LA21") (class "Default")
      (node (ref "ISA1") (pin "C4") (pinfunction "A21_C4") (pintype "passive"))
      (node (ref "ISA2") (pin "C4") (pinfunction "A21_C4") (pintype "passive"))
      (node (ref "ISA3") (pin "C4") (pinfunction "A21_C4") (pintype "passive"))
      (node (ref "RP64") (pin "2") (pinfunction "2_2") (pintype "passive"))
    )
    (net (code "246") (name "/ISA_LA22") (class "Default")
      (node (ref "ISA1") (pin "C3") (pinfunction "A22_C3") (pintype "passive"))
      (node (ref "ISA2") (pin "C3") (pinfunction "A22_C3") (pintype "passive"))
      (node (ref "ISA3") (pin "C3") (pinfunction "A22_C3") (pintype "passive"))
      (node (ref "RP63") (pin "2") (pinfunction "2_2") (pintype "passive"))
    )
    (net (code "247") (name "/ISA_LA23") (class "Default")
      (node (ref "ISA1") (pin "C2") (pinfunction "A23_C2") (pintype "passive"))
      (node (ref "ISA2") (pin "C2") (pinfunction "A23_C2") (pintype "passive"))
      (node (ref "ISA3") (pin "C2") (pinfunction "A23_C2") (pintype "passive"))
      (node (ref "RP62") (pin "2") (pinfunction "2_2") (pintype "passive"))
    )
    (net (code "248") (name "/ISA_MASTER#") (class "Default")
      (node (ref "ISA1") (pin "D17") (pinfunction "~{MASTER}_D17") (pintype "passive"))
      (node (ref "ISA2") (pin "D17") (pinfunction "~{MASTER}_D17") (pintype "passive"))
      (node (ref "ISA3") (pin "D17") (pinfunction "~{MASTER}_D17") (pintype "passive"))
      (node (ref "U17") (pin "1") (pinfunction "DIR_1") (pintype "input"))
      (node (ref "U18") (pin "1") (pinfunction "DIR_1") (pintype "input"))
    )
    (net (code "249") (name "/ISA_MEMCS16#") (class "Default")
      (node (ref "ISA1") (pin "D1") (pinfunction "~{MEMCS16}_D1") (pintype "passive"))
      (node (ref "ISA2") (pin "D1") (pinfunction "~{MEMCS16}_D1") (pintype "passive"))
      (node (ref "ISA3") (pin "D1") (pinfunction "~{MEMCS16}_D1") (pintype "passive"))
      (node (ref "RN73") (pin "1") (pinfunction "1_1") (pintype "passive"))
      (node (ref "U13") (pin "191") (pinfunction "MCS16#_191") (pintype "passive"))
    )
    (net (code "250") (name "/ISA_MEMR#") (class "Default")
      (node (ref "ISA1") (pin "C9") (pinfunction "~{MEMR}_C9") (pintype "passive"))
      (node (ref "ISA2") (pin "C9") (pinfunction "~{MEMR}_C9") (pintype "passive"))
      (node (ref "ISA3") (pin "C9") (pinfunction "~{MEMR}_C9") (pintype "passive"))
      (node (ref "R36") (pin "1") (pinfunction "1_1") (pintype "passive"))
      (node (ref "RN75") (pin "1") (pinfunction "1_1") (pintype "passive"))
      (node (ref "U2") (pin "24") (pinfunction "~{OE}_24") (pintype "passive"))
    )
    (net (code "251") (name "/ISA_MEMW#") (class "Default")
      (node (ref "ISA1") (pin "C10") (pinfunction "~{MEMW}_C10") (pintype "passive"))
      (node (ref "ISA2") (pin "C10") (pinfunction "~{MEMW}_C10") (pintype "passive"))
      (node (ref "ISA3") (pin "C10") (pinfunction "~{MEMW}_C10") (pintype "passive"))
      (node (ref "R37") (pin "1") (pinfunction "1_1") (pintype "passive"))
      (node (ref "RN76") (pin "1") (pinfunction "1_1") (pintype "passive"))
      (node (ref "U2") (pin "31") (pinfunction "~{PGM}_31") (pintype "passive"))
    )
    (net (code "252") (name "/ISA_OSC") (class "Default")
      (node (ref "ISA1") (pin "B30") (pinfunction "OSC_B30") (pintype "passive"))
      (node (ref "ISA2") (pin "B30") (pinfunction "OSC_B30") (pintype "passive"))
      (node (ref "ISA3") (pin "B30") (pinfunction "OSC_B30") (pintype "passive"))
      (node (ref "J1") (pin "3") (pinfunction "3_3") (pintype "passive"))
      (node (ref "R23") (pin "2") (pinfunction "2_2") (pintype "passive"))
      (node (ref "U10") (pin "14") (pinfunction "A0_14") (pintype "input"))
      (node (ref "U5") (pin "14") (pinfunction "A0_14") (pintype "input"))
    )
    (net (code "253") (name "/ISA_REFRESH#") (class "Default")
      (node (ref "ISA1") (pin "B19") (pinfunction "~{DACK0}/~{REFRESH}_B19") (pintype "passive"))
      (node (ref "ISA2") (pin "B19") (pinfunction "~{DACK0}/~{REFRESH}_B19") (pintype "passive"))
      (node (ref "ISA3") (pin "B19") (pinfunction "~{DACK0}/~{REFRESH}_B19") (pintype "passive"))
      (node (ref "RN71") (pin "1") (pinfunction "1_1") (pintype "passive"))
    )
    (net (code "254") (name "/ISA_RESET") (class "Default")
      (node (ref "CPU1") (pin "48") (pinfunction "RESET_48") (pintype "passive"))
      (node (ref "ISA1") (pin "B02") (pinfunction "RESET_DRV_B02") (pintype "passive"))
      (node (ref "ISA2") (pin "B02") (pinfunction "RESET_DRV_B02") (pintype "passive"))
      (node (ref "ISA3") (pin "B02") (pinfunction "RESET_DRV_B02") (pintype "passive"))
      (node (ref "R48") (pin "1") (pinfunction "1_1") (pintype "passive"))
      (node (ref "U13") (pin "203") (pinfunction "RESETDRV_203") (pintype "passive"))
      (node (ref "U19") (pin "5") (pinfunction "I4_5") (pintype "passive"))
    )
    (net (code "255") (name "/ISA_SMEMR#") (class "Default")
      (node (ref "ISA1") (pin "B12") (pinfunction "~{MEMR}_B12") (pintype "passive"))
      (node (ref "ISA2") (pin "B12") (pinfunction "~{MEMR}_B12") (pintype "passive"))
      (node (ref "ISA3") (pin "B12") (pinfunction "~{MEMR}_B12") (pintype "passive"))
      (node (ref "RN80") (pin "1") (pinfunction "1_1") (pintype "passive"))
      (node (ref "RP21") (pin "1") (pinfunction "1_1") (pintype "passive"))
    )
    (net (code "256") (name "/ISA_SMEMW#") (class "Default")
      (node (ref "ISA1") (pin "B11") (pinfunction "~{MEMW}_B11") (pintype "passive"))
      (node (ref "ISA2") (pin "B11") (pinfunction "~{MEMW}_B11") (pintype "passive"))
      (node (ref "ISA3") (pin "B11") (pinfunction "~{MEMW}_B11") (pintype "passive"))
      (node (ref "RN79") (pin "1") (pinfunction "1_1") (pintype "passive"))
      (node (ref "RP22") (pin "1") (pinfunction "1_1") (pintype "passive"))
    )
    (net (code "257") (name "/ISA_T{slash}C") (class "Default")
      (node (ref "ISA1") (pin "B27") (pinfunction "T/C_B27") (pintype "passive"))
      (node (ref "ISA2") (pin "B27") (pinfunction "T/C_B27") (pintype "passive"))
      (node (ref "ISA3") (pin "B27") (pinfunction "T/C_B27") (pintype "passive"))
      (node (ref "U13") (pin "184") (pinfunction "TC_184") (pintype "passive"))
    )
    (net (code "258") (name "/KBCLK") (class "Default")
      (node (ref "C8") (pin "2") (pinfunction "2_2") (pintype "passive"))
      (node (ref "R2") (pin "1") (pinfunction "1_1") (pintype "passive"))
      (node (ref "RK1") (pin "1") (pinfunction "1_1") (pintype "passive"))
      (node (ref "U13") (pin "100") (pinfunction "KBCLK/IRQ1_100") (pintype "passive"))
    )
    (net (code "259") (name "/KBDATA") (class "Default")
      (node (ref "C12") (pin "2") (pinfunction "2_2") (pintype "passive"))
      (node (ref "R6") (pin "1") (pinfunction "1_1") (pintype "passive"))
      (node (ref "RK2") (pin "1") (pinfunction "1_1") (pintype "passive"))
      (node (ref "U13") (pin "99") (pinfunction "KBDATA/RC#_99") (pintype "passive"))
    )
    (net (code "260") (name "/KEN#") (class "Default")
      (node (ref "CPU1") (pin "13") (pinfunction "KEN#_13") (pintype "passive"))
      (node (ref "U13") (pin "12") (pinfunction "KEN#_12") (pintype "passive"))
    )
    (net (code "261") (name "/KEYLOCK") (class "Default")
      (node (ref "CN11") (pin "1") (pinfunction "1_1") (pintype "passive"))
      (node (ref "RQ12") (pin "1") (pinfunction "1_1") (pintype "passive"))
      (node (ref "U10") (pin "13") (pinfunction "2C3_13") (pintype "input"))
    )
    (net (code "262") (name "/LHD1") (class "Default")
      (node (ref "IDE1") (pin "39") (pinfunction "Activity_39") (pintype "passive"))
      (node (ref "LHD1") (pin "2") (pintype "passive"))
    )
    (net (code "263") (name "/LHD2") (class "Default")
      (node (ref "IDE2") (pin "39") (pinfunction "Activity_39") (pintype "passive"))
      (node (ref "LHD2") (pin "2") (pintype "passive"))
    )
    (net (code "264") (name "/LOCK#") (class "Default")
      (node (ref "CPU1") (pin "207") (pinfunction "LOCK#_207") (pintype "passive"))
      (node (ref "R73") (pin "1") (pinfunction "1_1") (pintype "passive"))
      (node (ref "U13") (pin "16") (pinfunction "LOCK#_16") (pintype "passive"))
    )
    (net (code "265") (name "/MA0") (class "Default")
      (node (ref "M1") (pin "12") (pinfunction "A0_12") (pintype "passive"))
      (node (ref "M2") (pin "12") (pinfunction "A0_12") (pintype "passive"))
      (node (ref "M3") (pin "12") (pinfunction "A0_12") (pintype "passive"))
      (node (ref "M4") (pin "12") (pinfunction "A0_12") (pintype "passive"))
      (node (ref "RM1") (pin "2") (pinfunction "2_2") (pintype "passive"))
    )
    (net (code "266") (name "/MA1") (class "Default")
      (node (ref "M1") (pin "13") (pinfunction "A1_13") (pintype "passive"))
      (node (ref "M2") (pin "13") (pinfunction "A1_13") (pintype "passive"))
      (node (ref "M3") (pin "13") (pinfunction "A1_13") (pintype "passive"))
      (node (ref "M4") (pin "13") (pinfunction "A1_13") (pintype "passive"))
      (node (ref "RM2") (pin "2") (pinfunction "2_2") (pintype "passive"))
    )
    (net (code "267") (name "/MA2") (class "Default")
      (node (ref "M1") (pin "14") (pinfunction "A2_14") (pintype "passive"))
      (node (ref "M2") (pin "14") (pinfunction "A2_14") (pintype "passive"))
      (node (ref "M3") (pin "14") (pinfunction "A2_14") (pintype "passive"))
      (node (ref "M4") (pin "14") (pinfunction "A2_14") (pintype "passive"))
      (node (ref "RM3") (pin "2") (pinfunction "2_2") (pintype "passive"))
    )
    (net (code "268") (name "/MA3") (class "Default")
      (node (ref "M1") (pin "15") (pinfunction "A3_15") (pintype "passive"))
      (node (ref "M2") (pin "15") (pinfunction "A3_15") (pintype "passive"))
      (node (ref "M3") (pin "15") (pinfunction "A3_15") (pintype "passive"))
      (node (ref "M4") (pin "15") (pinfunction "A3_15") (pintype "passive"))
      (node (ref "RM4") (pin "2") (pinfunction "2_2") (pintype "passive"))
    )
    (net (code "269") (name "/MA4") (class "Default")
      (node (ref "M1") (pin "16") (pinfunction "A4_16") (pintype "passive"))
      (node (ref "M2") (pin "16") (pinfunction "A4_16") (pintype "passive"))
      (node (ref "M3") (pin "16") (pinfunction "A4_16") (pintype "passive"))
      (node (ref "M4") (pin "16") (pinfunction "A4_16") (pintype "passive"))
      (node (ref "RM5") (pin "2") (pinfunction "2_2") (pintype "passive"))
    )
    (net (code "270") (name "/MA4{slash}TA0") (class "Default")
      (node (ref "CT1") (pin "17") (pinfunction "17_17") (pintype "passive"))
      (node (ref "RM5") (pin "1") (pinfunction "1_1") (pintype "passive"))
      (node (ref "U13") (pin "83") (pinfunction "MA4/TA0_83") (pintype "passive"))
    )
    (net (code "271") (name "/MA5") (class "Default")
      (node (ref "M1") (pin "17") (pinfunction "A5_17") (pintype "passive"))
      (node (ref "M2") (pin "17") (pinfunction "A5_17") (pintype "passive"))
      (node (ref "M3") (pin "17") (pinfunction "A5_17") (pintype "passive"))
      (node (ref "M4") (pin "17") (pinfunction "A5_17") (pintype "passive"))
      (node (ref "RM6") (pin "2") (pinfunction "2_2") (pintype "passive"))
    )
    (net (code "272") (name "/MA5{slash}TA1") (class "Default")
      (node (ref "CT1") (pin "16") (pinfunction "16_16") (pintype "passive"))
      (node (ref "RM6") (pin "1") (pinfunction "1_1") (pintype "passive"))
      (node (ref "U13") (pin "82") (pinfunction "MA5/TA1_82") (pintype "passive"))
    )
    (net (code "273") (name "/MA6") (class "Default")
      (node (ref "M1") (pin "18") (pinfunction "A6_18") (pintype "passive"))
      (node (ref "M2") (pin "18") (pinfunction "A6_18") (pintype "passive"))
      (node (ref "M3") (pin "18") (pinfunction "A6_18") (pintype "passive"))
      (node (ref "M4") (pin "18") (pinfunction "A6_18") (pintype "passive"))
      (node (ref "RM7") (pin "2") (pinfunction "2_2") (pintype "passive"))
    )
    (net (code "274") (name "/MA6{slash}TA2") (class "Default")
      (node (ref "CT1") (pin "15") (pinfunction "15_15") (pintype "passive"))
      (node (ref "RM7") (pin "1") (pinfunction "1_1") (pintype "passive"))
      (node (ref "U13") (pin "81") (pinfunction "MA6/TA2_81") (pintype "passive"))
    )
    (net (code "275") (name "/MA7") (class "Default")
      (node (ref "M1") (pin "28") (pinfunction "A7_28") (pintype "passive"))
      (node (ref "M2") (pin "28") (pinfunction "A7_28") (pintype "passive"))
      (node (ref "M3") (pin "28") (pinfunction "A7_28") (pintype "passive"))
      (node (ref "M4") (pin "28") (pinfunction "A7_28") (pintype "passive"))
      (node (ref "RM8") (pin "2") (pinfunction "2_2") (pintype "passive"))
    )
    (net (code "276") (name "/MA7{slash}TA3") (class "Default")
      (node (ref "CT1") (pin "14") (pinfunction "14_14") (pintype "passive"))
      (node (ref "RM8") (pin "1") (pinfunction "1_1") (pintype "passive"))
      (node (ref "U13") (pin "80") (pinfunction "MA7/TA3_80") (pintype "passive"))
    )
    (net (code "277") (name "/MA8") (class "Default")
      (node (ref "M1") (pin "31") (pinfunction "A8_31") (pintype "passive"))
      (node (ref "M2") (pin "31") (pinfunction "A8_31") (pintype "passive"))
      (node (ref "M3") (pin "31") (pinfunction "A8_31") (pintype "passive"))
      (node (ref "M4") (pin "31") (pinfunction "A8_31") (pintype "passive"))
      (node (ref "RM9") (pin "2") (pinfunction "2_2") (pintype "passive"))
    )
    (net (code "278") (name "/MA8{slash}TA4") (class "Default")
      (node (ref "CT1") (pin "13") (pinfunction "13_13") (pintype "passive"))
      (node (ref "RM9") (pin "1") (pinfunction "1_1") (pintype "passive"))
      (node (ref "U13") (pin "79") (pinfunction "MA8/TA4_79") (pintype "passive"))
    )
    (net (code "279") (name "/MA9") (class "Default")
      (node (ref "M1") (pin "32") (pinfunction "A9_32") (pintype "passive"))
      (node (ref "M2") (pin "32") (pinfunction "A9_32") (pintype "passive"))
      (node (ref "M3") (pin "32") (pinfunction "A9_32") (pintype "passive"))
      (node (ref "M4") (pin "32") (pinfunction "A9_32") (pintype "passive"))
      (node (ref "RM10") (pin "2") (pinfunction "2_2") (pintype "passive"))
    )
    (net (code "280") (name "/MA9{slash}TA5") (class "Default")
      (node (ref "CT1") (pin "39") (pinfunction "39_39") (pintype "passive"))
      (node (ref "RM10") (pin "1") (pinfunction "1_1") (pintype "passive"))
      (node (ref "U13") (pin "78") (pinfunction "MA9/TA5_78") (pintype "passive"))
    )
    (net (code "281") (name "/MA10") (class "Default")
      (node (ref "M1") (pin "19") (pinfunction "A10_19") (pintype "passive"))
      (node (ref "M2") (pin "19") (pinfunction "A10_19") (pintype "passive"))
      (node (ref "M3") (pin "19") (pinfunction "A10_19") (pintype "passive"))
      (node (ref "M4") (pin "19") (pinfunction "A10_19") (pintype "passive"))
      (node (ref "RM11") (pin "2") (pinfunction "2_2") (pintype "passive"))
    )
    (net (code "282") (name "/MA10{slash}TA6") (class "Default")
      (node (ref "CT1") (pin "38") (pinfunction "38_38") (pintype "passive"))
      (node (ref "RM11") (pin "1") (pinfunction "1_1") (pintype "passive"))
      (node (ref "U13") (pin "77") (pinfunction "MA10/TA6_77") (pintype "passive"))
    )
    (net (code "283") (name "/MA11") (class "Default")
      (node (ref "M1") (pin "29") (pinfunction "A11(NC)_29") (pintype "passive"))
      (node (ref "M2") (pin "29") (pinfunction "A11(NC)_29") (pintype "passive"))
      (node (ref "M3") (pin "29") (pinfunction "A11(NC)_29") (pintype "passive"))
      (node (ref "M4") (pin "29") (pinfunction "A11(NC)_29") (pintype "passive"))
      (node (ref "RM12") (pin "2") (pinfunction "2_2") (pintype "passive"))
    )
    (net (code "284") (name "/MA11{slash}TA7") (class "Default")
      (node (ref "CT1") (pin "37") (pinfunction "37_37") (pintype "passive"))
      (node (ref "RM12") (pin "1") (pinfunction "1_1") (pintype "passive"))
      (node (ref "U13") (pin "76") (pinfunction "MA11/TA7_76") (pintype "passive"))
    )
    (net (code "285") (name "/MA{slash}CFG{slash}0") (class "Default")
      (node (ref "RM1") (pin "1") (pinfunction "1_1") (pintype "passive"))
      (node (ref "U13") (pin "87") (pinfunction "MA0/CFG0_87") (pintype "passive"))
    )
    (net (code "286") (name "/MA{slash}CFG{slash}1") (class "Default")
      (node (ref "RM2") (pin "1") (pinfunction "1_1") (pintype "passive"))
      (node (ref "U13") (pin "86") (pinfunction "MA1/CFG1_86") (pintype "passive"))
    )
    (net (code "287") (name "/MA{slash}CFG{slash}2") (class "Default")
      (node (ref "RM3") (pin "1") (pinfunction "1_1") (pintype "passive"))
      (node (ref "U13") (pin "85") (pinfunction "MA2/CFG2_85") (pintype "passive"))
    )
    (net (code "288") (name "/MA{slash}CFG{slash}3") (class "Default")
      (node (ref "RM4") (pin "1") (pinfunction "1_1") (pintype "passive"))
      (node (ref "U13") (pin "84") (pinfunction "MA3/CFG3_84") (pintype "passive"))
    )
    (net (code "289") (name "/MCAS#0") (class "Default")
      (node (ref "M1") (pin "40") (pinfunction "~{CAS0}_40") (pintype "passive"))
      (node (ref "M2") (pin "40") (pinfunction "~{CAS0}_40") (pintype "passive"))
      (node (ref "M3") (pin "40") (pinfunction "~{CAS0}_40") (pintype "passive"))
      (node (ref "M4") (pin "40") (pinfunction "~{CAS0}_40") (pintype "passive"))
      (node (ref "RM20") (pin "2") (pinfunction "2_2") (pintype "passive"))
    )
    (net (code "290") (name "/MCAS#1") (class "Default")
      (node (ref "M1") (pin "43") (pinfunction "~{CAS1}_43") (pintype "passive"))
      (node (ref "M2") (pin "43") (pinfunction "~{CAS1}_43") (pintype "passive"))
      (node (ref "M3") (pin "43") (pinfunction "~{CAS1}_43") (pintype "passive"))
      (node (ref "M4") (pin "43") (pinfunction "~{CAS1}_43") (pintype "passive"))
      (node (ref "RM19") (pin "2") (pinfunction "2_2") (pintype "passive"))
    )
    (net (code "291") (name "/MCAS#2") (class "Default")
      (node (ref "M1") (pin "41") (pinfunction "~{CAS2}_41") (pintype "passive"))
      (node (ref "M2") (pin "41") (pinfunction "~{CAS2}_41") (pintype "passive"))
      (node (ref "M3") (pin "41") (pinfunction "~{CAS2}_41") (pintype "passive"))
      (node (ref "M4") (pin "41") (pinfunction "~{CAS2}_41") (pintype "passive"))
      (node (ref "RM18") (pin "2") (pinfunction "2_2") (pintype "passive"))
    )
    (net (code "292") (name "/MCAS#3") (class "Default")
      (node (ref "M1") (pin "42") (pinfunction "~{CAS3}_42") (pintype "passive"))
      (node (ref "M2") (pin "42") (pinfunction "~{CAS3}_42") (pintype "passive"))
      (node (ref "M3") (pin "42") (pinfunction "~{CAS3}_42") (pintype "passive"))
      (node (ref "M4") (pin "42") (pinfunction "~{CAS3}_42") (pintype "passive"))
      (node (ref "RM17") (pin "2") (pinfunction "2_2") (pintype "passive"))
    )
    (net (code "293") (name "/MCU_ADC1") (class "Default")
      (node (ref "UM1") (pin "36") (pinfunction "P0.0/AD0/ADC8/RXD3_36") (pintype "passive"))
    )
    (net (code "294") (name "/MCU_AVCC") (class "Default")
      (node (ref "CU23") (pin "1") (pinfunction "1_1") (pintype "passive"))
      (node (ref "CU24") (pin "1") (pinfunction "1_1") (pintype "passive"))
      (node (ref "LU3") (pin "1") (pinfunction "1_1") (pintype "passive"))
      (node (ref "UM1") (pin "12") (pinfunction "ADC_AVCC_12") (pintype "passive"))
    )
    (net (code "295") (name "/MCU_K1") (class "Default")
      (node (ref "KM1") (pin "2") (pinfunction "2_2") (pintype "passive"))
      (node (ref "UM1") (pin "17") (pinfunction "P4.0/WR_3/RXD2_2_17") (pintype "passive"))
    )
    (net (code "296") (name "/MCU_K2") (class "Default")
      (node (ref "KM2") (pin "2") (pinfunction "2_2") (pintype "passive"))
      (node (ref "UM1") (pin "26") (pinfunction "P4.1/ALE/CMPO_2_26") (pintype "passive"))
    )
    (net (code "297") (name "/MCU_K3") (class "Default")
      (node (ref "UM1") (pin "28") (pinfunction "P4.2/RD_3/TXD2_2_28") (pintype "passive"))
    )
    (net (code "298") (name "/MCU_K4") (class "Default")
      (node (ref "UM1") (pin "39") (pinfunction "P4.3/WR/RXD_4_39") (pintype "passive"))
    )
    (net (code "299") (name "/MCU_K5") (class "Default")
      (node (ref "UM1") (pin "6") (pinfunction "P4.4/RD/TXD_4_6") (pintype "passive"))
    )
    (net (code "300") (name "/MCU_K6") (class "Default")
      (node (ref "UM1") (pin "15") (pinfunction "P5.5_15") (pintype "passive"))
    )
    (net (code "301") (name "/MCU_K7") (class "Default")
      (node (ref "UM1") (pin "13") (pinfunction "P5.4/RST/MCLKO_13") (pintype "passive"))
    )
    (net (code "302") (name "/MCU_K8") (class "Default")
      (node (ref "UM1") (pin "25") (pinfunction "P3.7/INT3/RD_2/TXD_2/CMP+_25") (pintype "passive"))
    )
    (net (code "303") (name "/MRAS#0") (class "Default")
      (node (ref "M3") (pin "33") (pinfunction "~{RAS3}_33") (pintype "passive"))
      (node (ref "M3") (pin "45") (pinfunction "~{RAS1}_45") (pintype "passive"))
      (node (ref "M4") (pin "34") (pinfunction "~{RAS2}_34") (pintype "passive"))
      (node (ref "M4") (pin "44") (pinfunction "~{RAS0}_44") (pintype "passive"))
      (node (ref "RM16") (pin "2") (pinfunction "2_2") (pintype "passive"))
    )
    (net (code "304") (name "/MRAS#1") (class "Default")
      (node (ref "M1") (pin "34") (pinfunction "~{RAS2}_34") (pintype "passive"))
      (node (ref "M1") (pin "44") (pinfunction "~{RAS0}_44") (pintype "passive"))
      (node (ref "M2") (pin "33") (pinfunction "~{RAS3}_33") (pintype "passive"))
      (node (ref "M2") (pin "45") (pinfunction "~{RAS1}_45") (pintype "passive"))
      (node (ref "RM15") (pin "2") (pinfunction "2_2") (pintype "passive"))
    )
    (net (code "305") (name "/MRAS#2") (class "Default")
      (node (ref "M3") (pin "34") (pinfunction "~{RAS2}_34") (pintype "passive"))
      (node (ref "M3") (pin "44") (pinfunction "~{RAS0}_44") (pintype "passive"))
      (node (ref "M4") (pin "33") (pinfunction "~{RAS3}_33") (pintype "passive"))
      (node (ref "M4") (pin "45") (pinfunction "~{RAS1}_45") (pintype "passive"))
      (node (ref "RM14") (pin "2") (pinfunction "2_2") (pintype "passive"))
    )
    (net (code "306") (name "/MRAS#3") (class "Default")
      (node (ref "M1") (pin "33") (pinfunction "~{RAS3}_33") (pintype "passive"))
      (node (ref "M1") (pin "45") (pinfunction "~{RAS1}_45") (pintype "passive"))
      (node (ref "M2") (pin "34") (pinfunction "~{RAS2}_34") (pintype "passive"))
      (node (ref "M2") (pin "44") (pinfunction "~{RAS0}_44") (pintype "passive"))
      (node (ref "RM13") (pin "2") (pinfunction "2_2") (pintype "passive"))
    )
    (net (code "307") (name "/MUXINT0") (class "Default")
      (node (ref "RN67") (pin "1") (pinfunction "1_1") (pintype "passive"))
      (node (ref "U13") (pin "208") (pinfunction "MUXINT0_208") (pintype "passive"))
      (node (ref "U5") (pin "7") (pinfunction "1Y_7") (pintype "output"))
    )
    (net (code "308") (name "/MUXINT1") (class "Default")
      (node (ref "RN68") (pin "1") (pinfunction "1_1") (pintype "passive"))
      (node (ref "U13") (pin "207") (pinfunction "MUXINT1_207") (pintype "passive"))
      (node (ref "U5") (pin "9") (pinfunction "2Y_9") (pintype "output"))
    )
    (net (code "309") (name "/MUXINT2") (class "Default")
      (node (ref "RN69") (pin "1") (pinfunction "1_1") (pintype "passive"))
      (node (ref "U10") (pin "7") (pinfunction "1Y_7") (pintype "output"))
      (node (ref "U13") (pin "206") (pinfunction "MUXINT2_206") (pintype "passive"))
    )
    (net (code "310") (name "/MUXINT3") (class "Default")
      (node (ref "RN70") (pin "1") (pinfunction "1_1") (pintype "passive"))
      (node (ref "U10") (pin "9") (pinfunction "2Y_9") (pintype "output"))
      (node (ref "U13") (pin "205") (pinfunction "MUXINT3_205") (pintype "passive"))
    )
    (net (code "311") (name "/MWE#") (class "Default")
      (node (ref "R38") (pin "2") (pinfunction "2_2") (pintype "passive"))
      (node (ref "U13") (pin "98") (pinfunction "MWE#_98") (pintype "passive"))
    )
    (net (code "312") (name "/MWE#R") (class "Default")
      (node (ref "M1") (pin "47") (pinfunction "~{WE}_47") (pintype "passive"))
      (node (ref "M2") (pin "47") (pinfunction "~{WE}_47") (pintype "passive"))
      (node (ref "M3") (pin "47") (pinfunction "~{WE}_47") (pintype "passive"))
      (node (ref "M4") (pin "47") (pinfunction "~{WE}_47") (pintype "passive"))
      (node (ref "R38") (pin "1") (pinfunction "1_1") (pintype "passive"))
    )
    (net (code "313") (name "/M{slash}IO#") (class "Default")
      (node (ref "CPU1") (pin "37") (pinfunction "M/IO#_37") (pintype "passive"))
      (node (ref "RP212") (pin "1") (pinfunction "1_1") (pintype "passive"))
      (node (ref "U13") (pin "26") (pinfunction "M/IO#_26") (pintype "passive"))
    )
    (net (code "314") (name "/NMI") (class "Default")
      (node (ref "CPU1") (pin "51") (pinfunction "NMI_51") (pintype "passive"))
      (node (ref "U13") (pin "9") (pinfunction "NMI_9") (pintype "passive"))
    )
    (net (code "315") (name "/OSCIN") (class "Default")
      (node (ref "R22") (pin "2") (pinfunction "2_2") (pintype "passive"))
      (node (ref "R61") (pin "1") (pinfunction "1_1") (pintype "passive"))
      (node (ref "U13") (pin "102") (pinfunction "OSCIN_102") (pintype "passive"))
    )
    (net (code "316") (name "/P01") (class "Default")
      (node (ref "UM1") (pin "37") (pinfunction "P0.1/AD1/ADC9/TXD3_37") (pintype "passive"))
    )
    (net (code "317") (name "/P10") (class "Default")
      (node (ref "JM1") (pin "3") (pinfunction "3_3") (pintype "passive"))
      (node (ref "UM1") (pin "1") (pinfunction "P1.0/ADC0/PWM0_2/RXD2_1") (pintype "passive"))
    )
    (net (code "318") (name "/P11") (class "Default")
      (node (ref "JM1") (pin "4") (pinfunction "4_4") (pintype "passive"))
      (node (ref "UM1") (pin "2") (pinfunction "P1.1/ADC1/PWM1_2/TXD2_2") (pintype "passive"))
    )
    (net (code "319") (name "/P12") (class "Default")
      (node (ref "JM1") (pin "5") (pinfunction "5_5") (pintype "passive"))
      (node (ref "UM1") (pin "3") (pinfunction "P1.2/ADC2/PWM2_2/SS/T2/ECI_3") (pintype "passive"))
    )
    (net (code "320") (name "/P13") (class "Default")
      (node (ref "JM1") (pin "6") (pinfunction "6_6") (pintype "passive"))
      (node (ref "UM1") (pin "4") (pinfunction "P1.3/ADC3/PWM3_2/MOSI/T2CLKO_4") (pintype "passive"))
    )
    (net (code "321") (name "/P14") (class "Default")
      (node (ref "UM1") (pin "5") (pinfunction "P1.4/ADC4/PWM4_2/MISO/SDA/CCP3_5") (pintype "passive"))
    )
    (net (code "322") (name "/P15") (class "Default")
      (node (ref "UM1") (pin "7") (pinfunction "P1.5/ADC5/PWM5_2/SCLK/SCL/CCP2_7") (pintype "passive"))
    )
    (net (code "323") (name "/P16") (class "Default")
      (node (ref "UM1") (pin "8") (pinfunction "P1.6/ADC6/RXD3/PWM6_2/MCLKO2/CCP1/XTALO_8") (pintype "passive"))
    )
    (net (code "324") (name "/P17") (class "Default")
      (node (ref "UM1") (pin "9") (pinfunction "P1.7/ADC7/TXD_3/PWM7_2/CCP0/XTALI_9") (pintype "passive"))
    )
    (net (code "325") (name "/P20") (class "Default")
      (node (ref "JM1") (pin "7") (pinfunction "7_7") (pintype "passive"))
      (node (ref "UM1") (pin "27") (pinfunction "P2.0/A8/PWM0/RSTSV_27") (pintype "passive"))
    )
    (net (code "326") (name "/P21") (class "Default")
      (node (ref "JM1") (pin "8") (pinfunction "8_8") (pintype "passive"))
      (node (ref "UM1") (pin "29") (pinfunction "P2.1/A9/PWM1_29") (pintype "passive"))
    )
    (net (code "327") (name "/P22") (class "Default")
      (node (ref "UM1") (pin "30") (pinfunction "P2.2/A10/PWM2/SS_2/ECI_2_30") (pintype "passive"))
    )
    (net (code "328") (name "/P23") (class "Default")
      (node (ref "UM1") (pin "31") (pinfunction "P2.3/A11/PWM3/MOSI_2/CCP0_2_31") (pintype "passive"))
    )
    (net (code "329") (name "/P24") (class "Default")
      (node (ref "UM1") (pin "32") (pinfunction "P2.4/A12/PWM4/MISO_2/SDA_2/CCP1_2_32") (pintype "passive"))
    )
    (net (code "330") (name "/P25") (class "Default")
      (node (ref "UM1") (pin "33") (pinfunction "P2.5/A13/PWM5/SCLK_2/SCL_2/CCP2_2_33") (pintype "passive"))
    )
    (net (code "331") (name "/P26") (class "Default")
      (node (ref "UM1") (pin "34") (pinfunction "P2.6/A14/PWM6/CCP3_2_34") (pintype "passive"))
    )
    (net (code "332") (name "/P27") (class "Default")
      (node (ref "UM1") (pin "35") (pinfunction "P2.7/A15/PWM7_35") (pintype "passive"))
    )
    (net (code "333") (name "/P32") (class "Default")
      (node (ref "UM1") (pin "20") (pinfunction "P3.2/INT0/CCP1_4/SCLK_4/SCL_4_20") (pintype "passive"))
    )
    (net (code "334") (name "/P33") (class "Default")
      (node (ref "UM1") (pin "21") (pinfunction "P3.3/INT1/CCP0_4/MISO_4/SDA_4_21") (pintype "passive"))
    )
    (net (code "335") (name "/P34") (class "Default")
      (node (ref "UM1") (pin "22") (pinfunction "P3.4/T0/T1CLKO/MOSI_4/CMPO_22") (pintype "passive"))
    )
    (net (code "336") (name "/PCD") (class "Default")
      (node (ref "CPU1") (pin "41") (pinfunction "PCD_41") (pintype "passive"))
      (node (ref "R59") (pin "1") (pinfunction "1_1") (pintype "passive"))
      (node (ref "R68") (pin "1") (pinfunction "1_1") (pintype "passive"))
    )
    (net (code "337") (name "/PCI1_GNT#") (class "Default")
      (node (ref "R12") (pin "1") (pinfunction "1_1") (pintype "passive"))
      (node (ref "U13") (pin "155") (pinfunction "GNT0#_155") (pintype "passive"))
    )
    (net (code "338") (name "/PCI1_REQ#") (class "Default")
      (node (ref "R11") (pin "1") (pinfunction "1_1") (pintype "passive"))
      (node (ref "U13") (pin "154") (pinfunction "REQ0#_154") (pintype "passive"))
    )
    (net (code "339") (name "/PCI2_GNT#") (class "Default")
      (node (ref "PCI0") (pin "A17") (pinfunction "~{GNT}_A17") (pintype "passive"))
      (node (ref "PCI1") (pin "A17") (pinfunction "~{GNT}_A17") (pintype "passive"))
      (node (ref "PCI2") (pin "A17") (pinfunction "~{GNT}_A17") (pintype "passive"))
      (node (ref "R13") (pin "1") (pinfunction "1_1") (pintype "passive"))
      (node (ref "U13") (pin "106") (pinfunction "GNT1#_106") (pintype "passive"))
    )
    (net (code "340") (name "/PCI2_REQ#") (class "Default")
      (node (ref "PCI0") (pin "B18") (pinfunction "~{REQ}_B18") (pintype "passive"))
      (node (ref "PCI1") (pin "B18") (pinfunction "~{REQ}_B18") (pintype "passive"))
      (node (ref "PCI2") (pin "B18") (pinfunction "~{REQ}_B18") (pintype "passive"))
      (node (ref "R14") (pin "1") (pinfunction "1_1") (pintype "passive"))
      (node (ref "U13") (pin "105") (pinfunction "REQ1#_105") (pintype "passive"))
    )
    (net (code "341") (name "/PCICLK1") (class "Default")
      (node (ref "PCI0") (pin "B16") (pinfunction "CLK_B16") (pintype "passive"))
      (node (ref "PCI1") (pin "B16") (pinfunction "CLK_B16") (pintype "passive"))
      (node (ref "R16") (pin "1") (pinfunction "1_1") (pintype "passive"))
    )
    (net (code "342") (name "/PCICLK2") (class "Default")
      (node (ref "PCI2") (pin "B16") (pinfunction "CLK_B16") (pintype "passive"))
      (node (ref "R20") (pin "1") (pinfunction "1_1") (pintype "passive"))
    )
    (net (code "343") (name "/PCI_CBE0#") (class "Default")
      (node (ref "PCI0") (pin "A52") (pinfunction "~{C/BE0}_A52") (pintype "passive"))
      (node (ref "PCI1") (pin "A52") (pinfunction "~{C/BE0}_A52") (pintype "passive"))
      (node (ref "PCI2") (pin "A52") (pinfunction "~{C/BE0}_A52") (pintype "passive"))
      (node (ref "RN55") (pin "1") (pinfunction "1_1") (pintype "passive"))
      (node (ref "U13") (pin "128") (pinfunction "CBE0#_128") (pintype "passive"))
    )
    (net (code "344") (name "/PCI_CBE1#") (class "Default")
      (node (ref "PCI0") (pin "B44") (pinfunction "~{C/BE1}_B44") (pintype "passive"))
      (node (ref "PCI1") (pin "B44") (pinfunction "~{C/BE1}_B44") (pintype "passive"))
      (node (ref "PCI2") (pin "B44") (pinfunction "~{C/BE1}_B44") (pintype "passive"))
      (node (ref "RN56") (pin "1") (pinfunction "1_1") (pintype "passive"))
      (node (ref "U13") (pin "139") (pinfunction "CBE1#_139") (pintype "passive"))
    )
    (net (code "345") (name "/PCI_CBE2#") (class "Default")
      (node (ref "PCI0") (pin "B33") (pinfunction "~{C/BE2}_B33") (pintype "passive"))
      (node (ref "PCI1") (pin "B33") (pinfunction "~{C/BE2}_B33") (pintype "passive"))
      (node (ref "PCI2") (pin "B33") (pinfunction "~{C/BE2}_B33") (pintype "passive"))
      (node (ref "RN57") (pin "1") (pinfunction "1_1") (pintype "passive"))
      (node (ref "U13") (pin "143") (pinfunction "CBE2#_143") (pintype "passive"))
    )
    (net (code "346") (name "/PCI_CBE3#") (class "Default")
      (node (ref "PCI0") (pin "B26") (pinfunction "~{C/BE3}_B26") (pintype "passive"))
      (node (ref "PCI1") (pin "B26") (pinfunction "~{C/BE3}_B26") (pintype "passive"))
      (node (ref "PCI2") (pin "B26") (pinfunction "~{C/BE3}_B26") (pintype "passive"))
      (node (ref "RN58") (pin "1") (pinfunction "1_1") (pintype "passive"))
      (node (ref "U13") (pin "148") (pinfunction "CBE3#_148") (pintype "passive"))
    )
    (net (code "347") (name "/PCI_DEVSEL#") (class "Default")
      (node (ref "PCI0") (pin "B37") (pinfunction "~{DEVSEL}_B37") (pintype "passive"))
      (node (ref "PCI1") (pin "B37") (pinfunction "~{DEVSEL}_B37") (pintype "passive"))
      (node (ref "PCI2") (pin "B37") (pinfunction "~{DEVSEL}_B37") (pintype "passive"))
      (node (ref "R67") (pin "1") (pinfunction "1_1") (pintype "passive"))
      (node (ref "RN62") (pin "1") (pinfunction "1_1") (pintype "passive"))
    )
    (net (code "348") (name "/PCI_FRAME#") (class "Default")
      (node (ref "PCI0") (pin "A34") (pinfunction "~{FRAME}_A34") (pintype "passive"))
      (node (ref "PCI1") (pin "A34") (pinfunction "~{FRAME}_A34") (pintype "passive"))
      (node (ref "PCI2") (pin "A34") (pinfunction "~{FRAME}_A34") (pintype "passive"))
      (node (ref "RN59") (pin "1") (pinfunction "1_1") (pintype "passive"))
      (node (ref "U13") (pin "116") (pinfunction "FRAME#_116") (pintype "passive"))
      (node (ref "U19") (pin "7") (pinfunction "I6_7") (pintype "passive"))
    )
    (net (code "349") (name "/PCI_INT1#") (class "Default")
      (node (ref "PCI0") (pin "A7") (pinfunction "~{INTC}_A7") (pintype "passive"))
      (node (ref "PCI1") (pin "B8") (pinfunction "~{INTD}_B8") (pintype "passive"))
      (node (ref "PCI2") (pin "A7") (pinfunction "~{INTC}_A7") (pintype "passive"))
      (node (ref "RN51") (pin "1") (pinfunction "1_1") (pintype "passive"))
      (node (ref "U5") (pin "6") (pinfunction "1C0_6") (pintype "input"))
    )
    (net (code "350") (name "/PCI_INT2#") (class "Default")
      (node (ref "PCI0") (pin "B7") (pinfunction "~{INTB}_B7") (pintype "passive"))
      (node (ref "PCI1") (pin "A6") (pinfunction "~{INTA}_A6") (pintype "passive"))
      (node (ref "PCI2") (pin "B8") (pinfunction "~{INTD}_B8") (pintype "passive"))
      (node (ref "RN52") (pin "1") (pinfunction "1_1") (pintype "passive"))
      (node (ref "U5") (pin "5") (pinfunction "1C1_5") (pintype "input"))
    )
    (net (code "351") (name "/PCI_INT3#") (class "Default")
      (node (ref "PCI0") (pin "A6") (pinfunction "~{INTA}_A6") (pintype "passive"))
      (node (ref "PCI1") (pin "B7") (pinfunction "~{INTB}_B7") (pintype "passive"))
      (node (ref "PCI2") (pin "A6") (pinfunction "~{INTA}_A6") (pintype "passive"))
      (node (ref "RN53") (pin "1") (pinfunction "1_1") (pintype "passive"))
      (node (ref "U5") (pin "4") (pinfunction "1C2_4") (pintype "input"))
    )
    (net (code "352") (name "/PCI_INT4#") (class "Default")
      (node (ref "PCI0") (pin "B8") (pinfunction "~{INTD}_B8") (pintype "passive"))
      (node (ref "PCI1") (pin "A7") (pinfunction "~{INTC}_A7") (pintype "passive"))
      (node (ref "PCI2") (pin "B7") (pinfunction "~{INTB}_B7") (pintype "passive"))
      (node (ref "RN54") (pin "1") (pinfunction "1_1") (pintype "passive"))
      (node (ref "U5") (pin "3") (pinfunction "1C3_3") (pintype "input"))
    )
    (net (code "353") (name "/PCI_IRDY#") (class "Default")
      (node (ref "PCI0") (pin "B35") (pinfunction "~{IRDY}_B35") (pintype "passive"))
      (node (ref "PCI1") (pin "B35") (pinfunction "~{IRDY}_B35") (pintype "passive"))
      (node (ref "PCI2") (pin "B35") (pinfunction "~{IRDY}_B35") (pintype "passive"))
      (node (ref "RN60") (pin "1") (pinfunction "1_1") (pintype "passive"))
      (node (ref "U13") (pin "142") (pinfunction "IRDY#_142") (pintype "passive"))
      (node (ref "U19") (pin "2") (pinfunction "I1_2") (pintype "passive"))
    )
    (net (code "354") (name "/PCI_PAR") (class "Default")
      (node (ref "PCI0") (pin "A43") (pinfunction "PAR_A43") (pintype "passive"))
      (node (ref "PCI1") (pin "A43") (pinfunction "PAR_A43") (pintype "passive"))
      (node (ref "PCI2") (pin "A43") (pinfunction "PAR_A43") (pintype "passive"))
      (node (ref "RN66") (pin "1") (pinfunction "1_1") (pintype "passive"))
      (node (ref "U13") (pin "119") (pinfunction "PAR_119") (pintype "passive"))
    )
    (net (code "355") (name "/PCI_PERR#") (class "Default")
      (node (ref "PCI0") (pin "B40") (pinfunction "~{PERR}_B40") (pintype "passive"))
      (node (ref "PCI1") (pin "B40") (pinfunction "~{PERR}_B40") (pintype "passive"))
      (node (ref "PCI2") (pin "B40") (pinfunction "~{PERR}_B40") (pintype "passive"))
      (node (ref "RN64") (pin "1") (pinfunction "1_1") (pintype "passive"))
      (node (ref "U13") (pin "140") (pinfunction "PERR#_140") (pintype "passive"))
    )
    (net (code "356") (name "/PCI_RESET#") (class "Default")
      (node (ref "C142") (pin "2") (pinfunction "2_2") (pintype "passive"))
      (node (ref "IDE1") (pin "1") (pinfunction "RESET_1") (pintype "passive"))
      (node (ref "IDE2") (pin "1") (pinfunction "RESET_1") (pintype "passive"))
      (node (ref "PCI0") (pin "A15") (pinfunction "~{RESET}_A15") (pintype "passive"))
      (node (ref "PCI1") (pin "A15") (pinfunction "~{RESET}_A15") (pintype "passive"))
      (node (ref "PCI2") (pin "A15") (pinfunction "~{RESET}_A15") (pintype "passive"))
      (node (ref "U19") (pin "16") (pinfunction "I/O4_16") (pintype "passive"))
    )
    (net (code "357") (name "/PCI_SERR#") (class "Default")
      (node (ref "PCI0") (pin "B42") (pinfunction "~{SERR}_B42") (pintype "passive"))
      (node (ref "PCI1") (pin "B42") (pinfunction "~{SERR}_B42") (pintype "passive"))
      (node (ref "PCI2") (pin "B42") (pinfunction "~{SERR}_B42") (pintype "passive"))
      (node (ref "RN65") (pin "1") (pinfunction "1_1") (pintype "passive"))
    )
    (net (code "358") (name "/PCI_STOP#") (class "Default")
      (node (ref "PCI0") (pin "A38") (pinfunction "~{STOP}_A38") (pintype "passive"))
      (node (ref "PCI1") (pin "A38") (pinfunction "~{STOP}_A38") (pintype "passive"))
      (node (ref "PCI2") (pin "A38") (pinfunction "~{STOP}_A38") (pintype "passive"))
      (node (ref "RN63") (pin "1") (pinfunction "1_1") (pintype "passive"))
      (node (ref "U13") (pin "118") (pinfunction "STOP#_118") (pintype "passive"))
      (node (ref "U19") (pin "8") (pinfunction "I7_8") (pintype "passive"))
    )
    (net (code "359") (name "/PCI_TRDY#") (class "Default")
      (node (ref "PCI0") (pin "A36") (pinfunction "~{TRDY}_A36") (pintype "passive"))
      (node (ref "PCI1") (pin "A36") (pinfunction "~{TRDY}_A36") (pintype "passive"))
      (node (ref "PCI2") (pin "A36") (pinfunction "~{TRDY}_A36") (pintype "passive"))
      (node (ref "RN61") (pin "1") (pinfunction "1_1") (pintype "passive"))
      (node (ref "U13") (pin "117") (pinfunction "TRDY#_117") (pintype "passive"))
      (node (ref "U19") (pin "3") (pinfunction "I2_3") (pintype "passive"))
    )
    (net (code "360") (name "/PCLK") (class "Default")
      (node (ref "CT2") (pin "3") (pinfunction "3_3") (pintype "passive"))
      (node (ref "R24") (pin "1") (pinfunction "1_1") (pintype "passive"))
      (node (ref "R60") (pin "1") (pinfunction "1_1") (pintype "passive"))
      (node (ref "U13") (pin "104") (pinfunction "PCLK_104") (pintype "passive"))
      (node (ref "U19") (pin "1") (pinfunction "CLK_1") (pintype "passive"))
    )
    (net (code "361") (name "/POWERGOOD") (class "Default")
      (node (ref "C140") (pin "2") (pinfunction "2_2") (pintype "passive"))
      (node (ref "C9") (pin "2") (pinfunction "2_2") (pintype "passive"))
      (node (ref "D7") (pin "A") (pinfunction "A_A") (pintype "passive"))
      (node (ref "K1") (pin "2") (pinfunction "2_2") (pintype "passive"))
      (node (ref "R55") (pin "2") (pinfunction "2_2") (pintype "passive"))
      (node (ref "U13") (pin "10") (pinfunction "PWRGD_10") (pintype "passive"))
    )
    (net (code "362") (name "/RAS0#") (class "Default")
      (node (ref "RM16") (pin "1") (pinfunction "1_1") (pintype "passive"))
      (node (ref "U13") (pin "97") (pinfunction "RAS0#_97") (pintype "passive"))
    )
    (net (code "363") (name "/RAS1#") (class "Default")
      (node (ref "RM15") (pin "1") (pinfunction "1_1") (pintype "passive"))
      (node (ref "U13") (pin "96") (pinfunction "RAS1#_96") (pintype "passive"))
    )
    (net (code "364") (name "/RAS2#") (class "Default")
      (node (ref "RM14") (pin "1") (pinfunction "1_1") (pintype "passive"))
      (node (ref "U13") (pin "95") (pinfunction "RAS2#_95") (pintype "passive"))
    )
    (net (code "365") (name "/RAS3#") (class "Default")
      (node (ref "RM13") (pin "1") (pinfunction "1_1") (pintype "passive"))
      (node (ref "U13") (pin "94") (pinfunction "RAS3#_94") (pintype "passive"))
    )
    (net (code "366") (name "/RDY#") (class "Default")
      (node (ref "CPU1") (pin "12") (pinfunction "RDY#_12") (pintype "passive"))
      (node (ref "U13") (pin "15") (pinfunction "RDY#_15") (pintype "passive"))
    )
    (net (code "367") (name "/ROMCS#") (class "Default")
      (node (ref "R10") (pin "1") (pinfunction "1_1") (pintype "passive"))
      (node (ref "U2") (pin "22") (pinfunction "~{CS}_22") (pintype "passive"))
    )
    (net (code "368") (name "/SA{slash}HDD{slash}0") (class "Default")
      (node (ref "RD1") (pin "1") (pinfunction "1_1") (pintype "passive"))
      (node (ref "U13") (pin "190") (pinfunction "SA0/HDD0_190") (pintype "passive"))
      (node (ref "U17") (pin "2") (pinfunction "A0_2") (pintype "bidirectional"))
    )
    (net (code "369") (name "/SA{slash}HDD{slash}1") (class "Default")
      (node (ref "RD2") (pin "1") (pinfunction "1_1") (pintype "passive"))
      (node (ref "U13") (pin "189") (pinfunction "SA1/HDD1_189") (pintype "passive"))
      (node (ref "U17") (pin "3") (pinfunction "A1_3") (pintype "bidirectional"))
    )
    (net (code "370") (name "/SA{slash}HDD{slash}2") (class "Default")
      (node (ref "RD3") (pin "1") (pinfunction "1_1") (pintype "passive"))
      (node (ref "U13") (pin "188") (pinfunction "SA2/HDD2_188") (pintype "passive"))
      (node (ref "U17") (pin "4") (pinfunction "A2_4") (pintype "bidirectional"))
    )
    (net (code "371") (name "/SA{slash}HDD{slash}3") (class "Default")
      (node (ref "RD4") (pin "1") (pinfunction "1_1") (pintype "passive"))
      (node (ref "U13") (pin "185") (pinfunction "SA3/HDD3_185") (pintype "passive"))
      (node (ref "U17") (pin "5") (pinfunction "A3_5") (pintype "bidirectional"))
    )
    (net (code "372") (name "/SA{slash}HDD{slash}4") (class "Default")
      (node (ref "RD5") (pin "1") (pinfunction "1_1") (pintype "passive"))
      (node (ref "U13") (pin "183") (pinfunction "SA4/HDD4_183") (pintype "passive"))
      (node (ref "U17") (pin "6") (pinfunction "A4_6") (pintype "bidirectional"))
    )
    (net (code "373") (name "/SA{slash}HDD{slash}5") (class "Default")
      (node (ref "RD6") (pin "1") (pinfunction "1_1") (pintype "passive"))
      (node (ref "U13") (pin "180") (pinfunction "SA5/HDD5_180") (pintype "passive"))
      (node (ref "U17") (pin "7") (pinfunction "A5_7") (pintype "bidirectional"))
    )
    (net (code "374") (name "/SA{slash}HDD{slash}6") (class "Default")
      (node (ref "RD7") (pin "1") (pinfunction "1_1") (pintype "passive"))
      (node (ref "U13") (pin "179") (pinfunction "SA6/HDD6_179") (pintype "passive"))
      (node (ref "U17") (pin "8") (pinfunction "A6_8") (pintype "bidirectional"))
    )
    (net (code "375") (name "/SA{slash}HDD{slash}7") (class "Default")
      (node (ref "RD8") (pin "1") (pinfunction "1_1") (pintype "passive"))
      (node (ref "U13") (pin "178") (pinfunction "SA7/HDD7_178") (pintype "passive"))
      (node (ref "U17") (pin "9") (pinfunction "A7_9") (pintype "bidirectional"))
    )
    (net (code "376") (name "/SA{slash}HDD{slash}8") (class "Default")
      (node (ref "RD9") (pin "1") (pinfunction "1_1") (pintype "passive"))
      (node (ref "U13") (pin "177") (pinfunction "SA8/HDD8_177") (pintype "passive"))
      (node (ref "U18") (pin "2") (pinfunction "A0_2") (pintype "bidirectional"))
    )
    (net (code "377") (name "/SA{slash}HDD{slash}9") (class "Default")
      (node (ref "RD10") (pin "1") (pinfunction "1_1") (pintype "passive"))
      (node (ref "U13") (pin "176") (pinfunction "SA9/HDD9_176") (pintype "passive"))
      (node (ref "U18") (pin "3") (pinfunction "A1_3") (pintype "bidirectional"))
    )
    (net (code "378") (name "/SA{slash}HDD{slash}10") (class "Default")
      (node (ref "RD11") (pin "1") (pinfunction "1_1") (pintype "passive"))
      (node (ref "U13") (pin "175") (pinfunction "SA10/HDD10_175") (pintype "passive"))
      (node (ref "U18") (pin "4") (pinfunction "A2_4") (pintype "bidirectional"))
    )
    (net (code "379") (name "/SA{slash}HDD{slash}11") (class "Default")
      (node (ref "RD12") (pin "1") (pinfunction "1_1") (pintype "passive"))
      (node (ref "U13") (pin "173") (pinfunction "SA11/HDD11_173") (pintype "passive"))
      (node (ref "U18") (pin "5") (pinfunction "A3_5") (pintype "bidirectional"))
    )
    (net (code "380") (name "/SA{slash}HDD{slash}12") (class "Default")
      (node (ref "RD13") (pin "1") (pinfunction "1_1") (pintype "passive"))
      (node (ref "U13") (pin "172") (pinfunction "SA12/HDD12_172") (pintype "passive"))
      (node (ref "U18") (pin "6") (pinfunction "A4_6") (pintype "bidirectional"))
    )
    (net (code "381") (name "/SA{slash}HDD{slash}13") (class "Default")
      (node (ref "RD14") (pin "1") (pinfunction "1_1") (pintype "passive"))
      (node (ref "U13") (pin "170") (pinfunction "SA13/HDD13_170") (pintype "passive"))
      (node (ref "U18") (pin "7") (pinfunction "A5_7") (pintype "bidirectional"))
    )
    (net (code "382") (name "/SA{slash}HDD{slash}14") (class "Default")
      (node (ref "RD15") (pin "1") (pinfunction "1_1") (pintype "passive"))
      (node (ref "U13") (pin "168") (pinfunction "SA14/HDD14_168") (pintype "passive"))
      (node (ref "U18") (pin "8") (pinfunction "A6_8") (pintype "bidirectional"))
    )
    (net (code "383") (name "/SA{slash}HDD{slash}15") (class "Default")
      (node (ref "RD16") (pin "1") (pinfunction "1_1") (pintype "passive"))
      (node (ref "U13") (pin "165") (pinfunction "SA15/HDD15_165") (pintype "passive"))
      (node (ref "U18") (pin "9") (pinfunction "A7_9") (pintype "bidirectional"))
    )
    (net (code "384") (name "/SMI#") (class "Default")
      (node (ref "CPU1") (pin "65") (pinfunction "SMI#_65") (pintype "passive"))
      (node (ref "R70") (pin "1") (pinfunction "1_1") (pintype "passive"))
    )
    (net (code "385") (name "/SMIACT#") (class "Default")
      (node (ref "CPU1") (pin "59") (pinfunction "SMIACT#_59") (pintype "passive"))
      (node (ref "R74") (pin "1") (pinfunction "1_1") (pintype "passive"))
    )
    (net (code "386") (name "/SPKOUT") (class "Default")
      (node (ref "R43") (pin "2") (pinfunction "2_2") (pintype "passive"))
      (node (ref "U13") (pin "1") (pinfunction "SPKOUT_1") (pintype "passive"))
    )
    (net (code "387") (name "/SRESET") (class "Default")
      (node (ref "CPU1") (pin "58") (pinfunction "SRESET_58") (pintype "passive"))
      (node (ref "R47") (pin "1") (pinfunction "1_1") (pintype "passive"))
      (node (ref "U13") (pin "13") (pinfunction "CPURST_13") (pintype "passive"))
    )
    (net (code "388") (name "/STC_RxD1") (class "Default")
      (node (ref "JM1") (pin "9") (pinfunction "9_9") (pintype "passive"))
      (node (ref "RU8") (pin "1") (pinfunction "1_1") (pintype "passive"))
      (node (ref "UM1") (pin "18") (pinfunction "P3.0/RXD/CCP3_4/INT4_18") (pintype "passive"))
    )
    (net (code "389") (name "/STC_TxD1") (class "Default")
      (node (ref "JM1") (pin "10") (pinfunction "10_10") (pintype "passive"))
      (node (ref "RU7") (pin "1") (pinfunction "1_1") (pintype "passive"))
      (node (ref "UM1") (pin "19") (pinfunction "P3.1/TXD/CCP2_4_19") (pintype "passive"))
    )
    (net (code "390") (name "/STPCLK#") (class "Default")
      (node (ref "CPU1") (pin "73") (pinfunction "STPCLK#_73") (pintype "passive"))
      (node (ref "U13") (pin "2") (pinfunction "SLOWDWN#/STPCLK#_2") (pintype "passive"))
      (node (ref "U6") (pin "6") (pinfunction "CLK(CPUSTPCLK)_6") (pintype "passive"))
    )
    (net (code "391") (name "/TFT_BLK") (class "Default")
      (node (ref "TFT1") (pin "14") (pinfunction "LED_14") (pintype "passive"))
      (node (ref "UM1") (pin "38") (pinfunction "P0.2/AD2/ADC10/RXD4_38") (pintype "passive"))
    )
    (net (code "392") (name "/TFT_CS") (class "Default")
      (node (ref "TFT1") (pin "19") (pinfunction "~{CS}_19") (pintype "passive"))
      (node (ref "UM1") (pin "40") (pinfunction "P0.3/AD3/ADC11/TXD4_40") (pintype "passive"))
    )
    (net (code "393") (name "/TFT_DC") (class "Default")
      (node (ref "TFT1") (pin "17") (pinfunction "RS_17") (pintype "passive"))
      (node (ref "UM1") (pin "41") (pinfunction "P0.4/AD4/ADC12/T3_41") (pintype "passive"))
    )
    (net (code "394") (name "/TFT_RST") (class "Default")
      (node (ref "TFT1") (pin "18") (pinfunction "RST_18") (pintype "passive"))
      (node (ref "UM1") (pin "42") (pinfunction "P0.5/AD5/ADC13/T3CLKO_42") (pintype "passive"))
    )
    (net (code "395") (name "/TFT_SCL") (class "Default")
      (node (ref "TFT1") (pin "15") (pinfunction "SCL_15") (pintype "passive"))
      (node (ref "UM1") (pin "44") (pinfunction "P0.7/AD7/T4CLKO_44") (pintype "passive"))
    )
    (net (code "396") (name "/TFT_SDA") (class "Default")
      (node (ref "TFT1") (pin "16") (pinfunction "SDA_16") (pintype "passive"))
      (node (ref "UM1") (pin "43") (pinfunction "P0.6/AD6/ADC14/T4_43") (pintype "passive"))
    )
    (net (code "397") (name "/TOE#") (class "Default")
      (node (ref "CT1") (pin "20") (pinfunction "20_20") (pintype "passive"))
      (node (ref "U13") (pin "74") (pinfunction "TOE#_74") (pintype "passive"))
    )
    (net (code "398") (name "/TWE#") (class "Default")
      (node (ref "CT1") (pin "25") (pinfunction "25_25") (pintype "passive"))
      (node (ref "R39") (pin "1") (pinfunction "1_1") (pintype "passive"))
      (node (ref "U13") (pin "73") (pinfunction "TWE#_73") (pintype "passive"))
    )
    (net (code "399") (name "/V33") (class "Default")
      (node (ref "PCI0") (pin "A14") (pinfunction "3.3Vaux(RSV)_A14") (pintype "passive"))
      (node (ref "PCI1") (pin "A14") (pinfunction "3.3Vaux(RSV)_A14") (pintype "passive"))
      (node (ref "PCI2") (pin "A14") (pinfunction "3.3Vaux(RSV)_A14") (pintype "passive"))
      (node (ref "RV1") (pin "2") (pinfunction "2_2") (pintype "passive"))
    )
    (net (code "400") (name "/VCC_CHIP") (class "Default")
      (node (ref "C10") (pin "1") (pinfunction "1_1") (pintype "passive"))
      (node (ref "C11") (pin "1") (pinfunction "1_1") (pintype "passive"))
      (node (ref "CC1") (pin "1") (pinfunction "1_1") (pintype "passive"))
      (node (ref "CC2") (pin "1") (pinfunction "1_1") (pintype "passive"))
      (node (ref "CC3") (pin "1") (pinfunction "1_1") (pintype "passive"))
      (node (ref "CC4") (pin "2") (pinfunction "2_2") (pintype "passive"))
      (node (ref "CC5") (pin "2") (pinfunction "2_2") (pintype "passive"))
      (node (ref "CC6") (pin "2") (pinfunction "2_2") (pintype "passive"))
      (node (ref "CC7") (pin "2") (pinfunction "2_2") (pintype "passive"))
      (node (ref "CC8") (pin "2") (pinfunction "2_2") (pintype "passive"))
      (node (ref "D3") (pin "K") (pinfunction "K_K") (pintype "passive"))
      (node (ref "Q2") (pin "C") (pinfunction "c_C") (pintype "passive"))
      (node (ref "U13") (pin "129") (pinfunction "VCC_5_129") (pintype "passive"))
      (node (ref "U13") (pin "156") (pinfunction "VCC_6_156") (pintype "passive"))
      (node (ref "U13") (pin "18") (pinfunction "VCC_1_18") (pintype "passive"))
      (node (ref "U13") (pin "186") (pinfunction "VCC_7_186") (pintype "passive"))
      (node (ref "U13") (pin "44") (pinfunction "VCC_2_44") (pintype "passive"))
      (node (ref "U13") (pin "75") (pinfunction "VCC_3_75") (pintype "passive"))
      (node (ref "U13") (pin "93") (pinfunction "VCC_4_93") (pintype "passive"))
      (node (ref "U15") (pin "14") (pintype "power_in"))
    )
    (net (code "401") (name "/VCC_MCU") (class "Default")
      (node (ref "CU18") (pin "1") (pinfunction "1_1") (pintype "passive"))
      (node (ref "CU19") (pin "1") (pinfunction "1_1") (pintype "passive"))
      (node (ref "CU21") (pin "1") (pinfunction "1_1") (pintype "passive"))
      (node (ref "CU22") (pin "1") (pinfunction "1_1") (pintype "passive"))
      (node (ref "JM1") (pin "1") (pinfunction "1_1") (pintype "passive"))
      (node (ref "LU3") (pin "2") (pinfunction "2_2") (pintype "passive"))
      (node (ref "RU21") (pin "2") (pinfunction "2_2") (pintype "passive"))
      (node (ref "RU22") (pin "2") (pinfunction "2_2") (pintype "passive"))
      (node (ref "SW1") (pin "1") (pinfunction "1_1") (pintype "passive"))
      (node (ref "TFT1") (pin "9") (pinfunction "5V_9") (pintype "passive"))
      (node (ref "UM1") (pin "11") (pinfunction "AVREF_11") (pintype "passive"))
      (node (ref "UM1") (pin "14") (pinfunction "VCC_14") (pintype "passive"))
      (node (ref "UM2") (pin "1") (pinfunction "A1_1") (pintype "passive"))
      (node (ref "UM2") (pin "5") (pinfunction "VCC_5") (pintype "passive"))
      (node (ref "UM3") (pin "2") (pinfunction "A0_2") (pintype "passive"))
      (node (ref "UM3") (pin "5") (pinfunction "VCC_5") (pintype "passive"))
      (node (ref "UM4") (pin "5") (pinfunction "VCC_5") (pintype "passive"))
    )
    (net (code "402") (name "/VCC_USB") (class "Default")
      (node (ref "CU16") (pin "1") (pinfunction "1_1") (pintype "passive"))
      (node (ref "CU17") (pin "1") (pinfunction "1_1") (pintype "passive"))
      (node (ref "DM3") (pin "K") (pinfunction "K_K") (pintype "passive"))
      (node (ref "SW1") (pin "2") (pinfunction "2_2") (pintype "passive"))
      (node (ref "UM9") (pin "16") (pinfunction "VCC_16") (pintype "passive"))
      (node (ref "USB1") (pin "1") (pinfunction "VBUS_1") (pintype "passive"))
    )
    (net (code "403") (name "/WB{slash}WT#") (class "Default")
      (node (ref "CPU1") (pin "64") (pinfunction "WB/WT#_64") (pintype "passive"))
      (node (ref "R71") (pin "1") (pinfunction "1_1") (pintype "passive"))
    )
    (net (code "404") (name "/W{slash}R#") (class "Default")
      (node (ref "CPU1") (pin "27") (pinfunction "W/R#_27") (pintype "passive"))
      (node (ref "RP213") (pin "1") (pinfunction "1_1") (pintype "passive"))
      (node (ref "U13") (pin "25") (pinfunction "W/R#_25") (pintype "passive"))
      (node (ref "U16") (pin "9") (pinfunction "A7_9") (pintype "bidirectional"))
    )
    (net (code "405") (name "GND") (class "Default")
      (node (ref "58") (pin "1") (pinfunction "1_1") (pintype "passive"))
      (node (ref "BAT1") (pin "2") (pinfunction "-_2") (pintype "passive"))
      (node (ref "C1") (pin "2") (pinfunction "2_2") (pintype "passive"))
      (node (ref "C10") (pin "2") (pinfunction "2_2") (pintype "passive"))
      (node (ref "C11") (pin "2") (pinfunction "2_2") (pintype "passive"))
      (node (ref "C12") (pin "1") (pinfunction "1_1") (pintype "passive"))
      (node (ref "C13") (pin "2") (pinfunction "2_2") (pintype "passive"))
      (node (ref "C14") (pin "2") (pinfunction "2_2") (pintype "passive"))
      (node (ref "C140") (pin "1") (pinfunction "1_1") (pintype "passive"))
      (node (ref "C142") (pin "1") (pinfunction "1_1") (pintype "passive"))
      (node (ref "C15") (pin "2") (pinfunction "2_2") (pintype "passive"))
      (node (ref "C16") (pin "2") (pinfunction "2_2") (pintype "passive"))
      (node (ref "C17") (pin "2") (pinfunction "2_2") (pintype "passive"))
      (node (ref "C18") (pin "2") (pinfunction "2_2") (pintype "passive"))
      (node (ref "C19") (pin "2") (pinfunction "2_2") (pintype "passive"))
      (node (ref "C2") (pin "2") (pinfunction "2_2") (pintype "passive"))
      (node (ref "C20") (pin "2") (pinfunction "2_2") (pintype "passive"))
      (node (ref "C21") (pin "2") (pinfunction "2_2") (pintype "passive"))
      (node (ref "C22") (pin "2") (pinfunction "2_2") (pintype "passive"))
      (node (ref "C23") (pin "2") (pinfunction "2_2") (pintype "passive"))
      (node (ref "C3") (pin "2") (pinfunction "2_2") (pintype "passive"))
      (node (ref "C4") (pin "2") (pinfunction "2_2") (pintype "passive"))
      (node (ref "C5") (pin "2") (pinfunction "2_2") (pintype "passive"))
      (node (ref "C57") (pin "1") (pinfunction "1_1") (pintype "passive"))
      (node (ref "C6") (pin "2") (pinfunction "2_2") (pintype "passive"))
      (node (ref "C63") (pin "1") (pinfunction "1_1") (pintype "passive"))
      (node (ref "C64") (pin "1") (pinfunction "1_1") (pintype "passive"))
      (node (ref "C66") (pin "1") (pinfunction "1_1") (pintype "passive"))
      (node (ref "C67") (pin "1") (pinfunction "1_1") (pintype "passive"))
      (node (ref "C68") (pin "2") (pinfunction "2_2") (pintype "passive"))
      (node (ref "C7") (pin "2") (pinfunction "2_2") (pintype "passive"))
      (node (ref "C8") (pin "1") (pinfunction "1_1") (pintype "passive"))
      (node (ref "C9") (pin "1") (pinfunction "1_1") (pintype "passive"))
      (node (ref "CC1") (pin "2") (pinfunction "E_2") (pintype "passive"))
      (node (ref "CC12") (pin "2") (pinfunction "E_2") (pintype "passive"))
      (node (ref "CC13") (pin "2") (pinfunction "E_2") (pintype "passive"))
      (node (ref "CC14") (pin "2") (pinfunction "E_2") (pintype "passive"))
      (node (ref "CC2") (pin "2") (pinfunction "E_2") (pintype "passive"))
      (node (ref "CC3") (pin "2") (pinfunction "E_2") (pintype "passive"))
      (node (ref "CC4") (pin "1") (pinfunction "1_1") (pintype "passive"))
      (node (ref "CC5") (pin "1") (pinfunction "1_1") (pintype "passive"))
      (node (ref "CC6") (pin "1") (pinfunction "1_1") (pintype "passive"))
      (node (ref "CC7") (pin "1") (pinfunction "1_1") (pintype "passive"))
      (node (ref "CC8") (pin "1") (pinfunction "1_1") (pintype "passive"))
      (node (ref "CN1") (pin "4") (pinfunction "4_4") (pintype "passive"))
      (node (ref "CN11") (pin "2") (pinfunction "2_2") (pintype "passive"))
      (node (ref "CN2") (pin "4") (pinfunction "4_4") (pintype "passive"))
      (node (ref "CPU1") (pin "1") (pinfunction "GND_1") (pintype "passive"))
      (node (ref "CPU1") (pin "10") (pinfunction "GND_10") (pintype "passive"))
      (node (ref "CPU1") (pin "104") (pinfunction "GND_104") (pintype "passive"))
      (node (ref "CPU1") (pin "105") (pinfunction "GND_105") (pintype "passive"))
      (node (ref "CPU1") (pin "107") (pinfunction "GND_107") (pintype "passive"))
      (node (ref "CPU1") (pin "110") (pinfunction "GND_110") (pintype "passive"))
      (node (ref "CPU1") (pin "115") (pinfunction "GND_115") (pintype "passive"))
      (node (ref "CPU1") (pin "120") (pinfunction "GND_120") (pintype "passive"))
      (node (ref "CPU1") (pin "122") (pinfunction "GND_122") (pintype "passive"))
      (node (ref "CPU1") (pin "132") (pinfunction "GND_132") (pintype "passive"))
      (node (ref "CPU1") (pin "135") (pinfunction "GND_135") (pintype "passive"))
      (node (ref "CPU1") (pin "138") (pinfunction "GND_138") (pintype "passive"))
      (node (ref "CPU1") (pin "146") (pinfunction "GND_146") (pintype "passive"))
      (node (ref "CPU1") (pin "15") (pinfunction "GND_15") (pintype "passive"))
      (node (ref "CPU1") (pin "156") (pinfunction "GND_156") (pintype "passive"))
      (node (ref "CPU1") (pin "157") (pinfunction "GND_157") (pintype "passive"))
      (node (ref "CPU1") (pin "16") (pinfunction "HOLD_16") (pintype "passive"))
      (node (ref "CPU1") (pin "170") (pinfunction "GND_170") (pintype "passive"))
      (node (ref "CPU1") (pin "175") (pinfunction "GND_175") (pintype "passive"))
      (node (ref "CPU1") (pin "181") (pinfunction "GND_181") (pintype "passive"))
      (node (ref "CPU1") (pin "184") (pinfunction "GND_184") (pintype "passive"))
      (node (ref "CPU1") (pin "189") (pinfunction "GND_189") (pintype "passive"))
      (node (ref "CPU1") (pin "199") (pinfunction "GND_199") (pintype "passive"))
      (node (ref "CPU1") (pin "201") (pinfunction "GND_201") (pintype "passive"))
      (node (ref "CPU1") (pin "208") (pinfunction "GND_208") (pintype "passive"))
      (node (ref "CPU1") (pin "21") (pinfunction "GND_21") (pintype "passive"))
      (node (ref "CPU1") (pin "28") (pinfunction "GND_28") (pintype "passive"))
      (node (ref "CPU1") (pin "36") (pinfunction "GND_36") (pintype "passive"))
      (node (ref "CPU1") (pin "43") (pinfunction "GND_43") (pintype "passive"))
      (node (ref "CPU1") (pin "52") (pinfunction "GND_52") (pintype "passive"))
      (node (ref "CPU1") (pin "53") (pinfunction "GND_53") (pintype "passive"))
      (node (ref "CPU1") (pin "55") (pinfunction "GND_55") (pintype "passive"))
      (node (ref "CPU1") (pin "57") (pinfunction "GND_57") (pintype "passive"))
      (node (ref "CPU1") (pin "61") (pinfunction "GND_61") (pintype "passive"))
      (node (ref "CPU1") (pin "76") (pinfunction "GND_76") (pintype "passive"))
      (node (ref "CPU1") (pin "81") (pinfunction "GND_81") (pintype "passive"))
      (node (ref "CPU1") (pin "88") (pinfunction "GND_88") (pintype "passive"))
      (node (ref "CPU1") (pin "94") (pinfunction "GND_94") (pintype "passive"))
      (node (ref "CPU1") (pin "97") (pinfunction "GND_97") (pintype "passive"))
      (node (ref "CT1") (pin "10") (pinfunction "10_10") (pintype "passive"))
      (node (ref "CT1") (pin "11") (pinfunction "11_11") (pintype "passive"))
      (node (ref "CT1") (pin "18") (pinfunction "18_18") (pintype "passive"))
      (node (ref "CT1") (pin "2") (pinfunction "2_2") (pintype "passive"))
      (node (ref "CT1") (pin "26") (pinfunction "26_26") (pintype "passive"))
      (node (ref "CT1") (pin "43") (pinfunction "43_43") (pintype "passive"))
      (node (ref "CT1") (pin "46") (pinfunction "46_46") (pintype "passive"))
      (node (ref "CT1") (pin "50") (pinfunction "50_50") (pintype "passive"))
      (node (ref "CT1") (pin "6") (pinfunction "6_6") (pintype "passive"))
      (node (ref "CT1") (pin "9") (pinfunction "9_9") (pintype "passive"))
      (node (ref "CT2") (pin "11") (pinfunction "11_11") (pintype "passive"))
      (node (ref "CT2") (pin "16") (pinfunction "16_16") (pintype "passive"))
      (node (ref "CT2") (pin "21") (pinfunction "21_21") (pintype "passive"))
      (node (ref "CT2") (pin "26") (pinfunction "26_26") (pintype "passive"))
      (node (ref "CT2") (pin "27") (pinfunction "27_27") (pintype "passive"))
      (node (ref "CT2") (pin "32") (pinfunction "32_32") (pintype "passive"))
      (node (ref "CT2") (pin "37") (pinfunction "37_37") (pintype "passive"))
      (node (ref "CT2") (pin "42") (pinfunction "42_42") (pintype "passive"))
      (node (ref "CT2") (pin "47") (pinfunction "47_47") (pintype "passive"))
      (node (ref "CU1") (pin "2") (pinfunction "E_2") (pintype "passive"))
      (node (ref "CU10") (pin "2") (pinfunction "2_2") (pintype "passive"))
      (node (ref "CU11") (pin "2") (pinfunction "E_2") (pintype "passive"))
      (node (ref "CU12") (pin "2") (pinfunction "E_2") (pintype "passive"))
      (node (ref "CU13") (pin "2") (pinfunction "E_2") (pintype "passive"))
      (node (ref "CU14") (pin "2") (pinfunction "2_2") (pintype "passive"))
      (node (ref "CU15") (pin "1") (pinfunction "1_1") (pintype "passive"))
      (node (ref "CU16") (pin "2") (pinfunction "2_2") (pintype "passive"))
      (node (ref "CU17") (pin "2") (pinfunction "2_2") (pintype "passive"))
      (node (ref "CU18") (pin "2") (pinfunction "2_2") (pintype "passive"))
      (node (ref "CU19") (pin "2") (pinfunction "2_2") (pintype "passive"))
      (node (ref "CU2") (pin "2") (pinfunction "E_2") (pintype "passive"))
      (node (ref "CU21") (pin "2") (pinfunction "2_2") (pintype "passive"))
      (node (ref "CU22") (pin "2") (pinfunction "2_2") (pintype "passive"))
      (node (ref "CU23") (pin "2") (pinfunction "2_2") (pintype "passive"))
      (node (ref "CU24") (pin "2") (pinfunction "2_2") (pintype "passive"))
      (node (ref "CU25") (pin "1") (pinfunction "1_1") (pintype "passive"))
      (node (ref "CU26") (pin "1") (pinfunction "1_1") (pintype "passive"))
      (node (ref "CU27") (pin "2") (pinfunction "2_2") (pintype "passive"))
      (node (ref "CU28") (pin "2") (pinfunction "2_2") (pintype "passive"))
      (node (ref "CU3") (pin "2") (pinfunction "2_2") (pintype "passive"))
      (node (ref "CU5") (pin "2") (pinfunction "2_2") (pintype "passive"))
      (node (ref "CU6") (pin "2") (pinfunction "E_2") (pintype "passive"))
      (node (ref "CU7") (pin "2") (pinfunction "E_2") (pintype "passive"))
      (node (ref "CU8") (pin "2") (pinfunction "2_2") (pintype "passive"))
      (node (ref "CV1") (pin "2") (pinfunction "E_2") (pintype "passive"))
      (node (ref "CV10") (pin "2") (pinfunction "2_2") (pintype "passive"))
      (node (ref "CV11") (pin "2") (pinfunction "2_2") (pintype "passive"))
      (node (ref "CV12") (pin "2") (pinfunction "2_2") (pintype "passive"))
      (node (ref "CV13") (pin "2") (pinfunction "2_2") (pintype "passive"))
      (node (ref "CV14") (pin "2") (pinfunction "2_2") (pintype "passive"))
      (node (ref "CV15") (pin "2") (pinfunction "2_2") (pintype "passive"))
      (node (ref "CV16") (pin "2") (pinfunction "2_2") (pintype "passive"))
      (node (ref "CV17") (pin "2") (pinfunction "2_2") (pintype "passive"))
      (node (ref "CV18") (pin "2") (pinfunction "2_2") (pintype "passive"))
      (node (ref "CV19") (pin "2") (pinfunction "2_2") (pintype "passive"))
      (node (ref "CV2") (pin "2") (pinfunction "E_2") (pintype "passive"))
      (node (ref "CV20") (pin "2") (pinfunction "2_2") (pintype "passive"))
      (node (ref "CV21") (pin "2") (pinfunction "2_2") (pintype "passive"))
      (node (ref "CV22") (pin "2") (pinfunction "2_2") (pintype "passive"))
      (node (ref "CV23") (pin "2") (pinfunction "2_2") (pintype "passive"))
      (node (ref "CV24") (pin "2") (pinfunction "2_2") (pintype "passive"))
      (node (ref "CV25") (pin "2") (pinfunction "2_2") (pintype "passive"))
      (node (ref "CV26") (pin "2") (pinfunction "2_2") (pintype "passive"))
      (node (ref "CV27") (pin "2") (pinfunction "2_2") (pintype "passive"))
      (node (ref "CV28") (pin "2") (pinfunction "2_2") (pintype "passive"))
      (node (ref "CV29") (pin "2") (pinfunction "2_2") (pintype "passive"))
      (node (ref "CV3") (pin "2") (pinfunction "E_2") (pintype "passive"))
      (node (ref "CV30") (pin "2") (pinfunction "2_2") (pintype "passive"))
      (node (ref "CV31") (pin "2") (pinfunction "2_2") (pintype "passive"))
      (node (ref "CV32") (pin "2") (pinfunction "2_2") (pintype "passive"))
      (node (ref "CV33") (pin "2") (pinfunction "2_2") (pintype "passive"))
      (node (ref "CV34") (pin "2") (pinfunction "2_2") (pintype "passive"))
      (node (ref "CV35") (pin "2") (pinfunction "2_2") (pintype "passive"))
      (node (ref "CV36") (pin "2") (pinfunction "2_2") (pintype "passive"))
      (node (ref "CV37") (pin "2") (pinfunction "2_2") (pintype "passive"))
      (node (ref "CV38") (pin "2") (pinfunction "2_2") (pintype "passive"))
      (node (ref "CV39") (pin "2") (pinfunction "2_2") (pintype "passive"))
      (node (ref "CV4") (pin "2") (pinfunction "2_2") (pintype "passive"))
      (node (ref "CV40") (pin "2") (pinfunction "2_2") (pintype "passive"))
      (node (ref "CV5") (pin "2") (pinfunction "2_2") (pintype "passive"))
      (node (ref "CV6") (pin "2") (pinfunction "2_2") (pintype "passive"))
      (node (ref "CV7") (pin "2") (pinfunction "2_2") (pintype "passive"))
      (node (ref "CV8") (pin "2") (pinfunction "2_2") (pintype "passive"))
      (node (ref "CV9") (pin "2") (pinfunction "2_2") (pintype "passive"))
      (node (ref "D1") (pin "A") (pinfunction "A_A") (pintype "passive"))
      (node (ref "DU1") (pin "A") (pinfunction "A_A") (pintype "passive"))
      (node (ref "DU2") (pin "A") (pinfunction "A_A") (pintype "passive"))
      (node (ref "IDE1") (pin "19") (pinfunction "GND_19") (pintype "passive"))
      (node (ref "IDE1") (pin "2") (pinfunction "GND_2") (pintype "passive"))
      (node (ref "IDE1") (pin "22") (pinfunction "GND_22") (pintype "passive"))
      (node (ref "IDE1") (pin "24") (pinfunction "GND_24") (pintype "passive"))
      (node (ref "IDE1") (pin "26") (pinfunction "GND_26") (pintype "passive"))
      (node (ref "IDE1") (pin "30") (pinfunction "GND_30") (pintype "passive"))
      (node (ref "IDE1") (pin "40") (pinfunction "GND_40") (pintype "passive"))
      (node (ref "IDE2") (pin "19") (pinfunction "GND_19") (pintype "passive"))
      (node (ref "IDE2") (pin "2") (pinfunction "GND_2") (pintype "passive"))
      (node (ref "IDE2") (pin "22") (pinfunction "GND_22") (pintype "passive"))
      (node (ref "IDE2") (pin "24") (pinfunction "GND_24") (pintype "passive"))
      (node (ref "IDE2") (pin "26") (pinfunction "GND_26") (pintype "passive"))
      (node (ref "IDE2") (pin "30") (pinfunction "GND_30") (pintype "passive"))
      (node (ref "IDE2") (pin "40") (pinfunction "GND_40") (pintype "passive"))
      (node (ref "ISA1") (pin "B01") (pinfunction "GND_B01") (pintype "passive"))
      (node (ref "ISA1") (pin "B10") (pinfunction "GND_B10") (pintype "passive"))
      (node (ref "ISA1") (pin "B31") (pinfunction "GND_B31") (pintype "passive"))
      (node (ref "ISA1") (pin "D18") (pinfunction "GND_D18") (pintype "passive"))
      (node (ref "ISA2") (pin "B01") (pinfunction "GND_B01") (pintype "passive"))
      (node (ref "ISA2") (pin "B10") (pinfunction "GND_B10") (pintype "passive"))
      (node (ref "ISA2") (pin "B31") (pinfunction "GND_B31") (pintype "passive"))
      (node (ref "ISA2") (pin "D18") (pinfunction "GND_D18") (pintype "passive"))
      (node (ref "ISA3") (pin "B01") (pinfunction "GND_B01") (pintype "passive"))
      (node (ref "ISA3") (pin "B10") (pinfunction "GND_B10") (pintype "passive"))
      (node (ref "ISA3") (pin "B31") (pinfunction "GND_B31") (pintype "passive"))
      (node (ref "ISA3") (pin "D18") (pinfunction "GND_D18") (pintype "passive"))
      (node (ref "J5") (pin "2") (pinfunction "2_2") (pintype "passive"))
      (node (ref "J5") (pin "4") (pinfunction "4_4") (pintype "passive"))
      (node (ref "JM1") (pin "2") (pinfunction "2_2") (pintype "passive"))
      (node (ref "JU1") (pin "2") (pinfunction "-_2") (pintype "passive"))
      (node (ref "JU1") (pin "3") (pinfunction "-_3") (pintype "passive"))
      (node (ref "K1") (pin "1") (pinfunction "1_1") (pintype "passive"))
      (node (ref "KM1") (pin "1") (pinfunction "1_1") (pintype "passive"))
      (node (ref "KM2") (pin "1") (pinfunction "1_1") (pintype "passive"))
      (node (ref "M1") (pin "1") (pinfunction "GND_1") (pintype "passive"))
      (node (ref "M1") (pin "39") (pinfunction "GND_39") (pintype "passive"))
      (node (ref "M1") (pin "46") (pinfunction "NC_46") (pintype "passive"))
      (node (ref "M1") (pin "72") (pinfunction "GND_72") (pintype "passive"))
      (node (ref "M2") (pin "1") (pinfunction "GND_1") (pintype "passive"))
      (node (ref "M2") (pin "39") (pinfunction "GND_39") (pintype "passive"))
      (node (ref "M2") (pin "46") (pinfunction "NC_46") (pintype "passive"))
      (node (ref "M2") (pin "72") (pinfunction "GND_72") (pintype "passive"))
      (node (ref "M3") (pin "1") (pinfunction "GND_1") (pintype "passive"))
      (node (ref "M3") (pin "39") (pinfunction "GND_39") (pintype "passive"))
      (node (ref "M3") (pin "46") (pinfunction "NC_46") (pintype "passive"))
      (node (ref "M3") (pin "72") (pinfunction "GND_72") (pintype "passive"))
      (node (ref "M4") (pin "1") (pinfunction "GND_1") (pintype "passive"))
      (node (ref "M4") (pin "39") (pinfunction "GND_39") (pintype "passive"))
      (node (ref "M4") (pin "46") (pinfunction "NC_46") (pintype "passive"))
      (node (ref "M4") (pin "72") (pinfunction "GND_72") (pintype "passive"))
      (node (ref "MM1") (pin "1") (pinfunction "1_1") (pintype "passive"))
      (node (ref "MM2") (pin "1") (pinfunction "1_1") (pintype "passive"))
      (node (ref "MM3") (pin "1") (pinfunction "1_1") (pintype "passive"))
      (node (ref "MM4") (pin "1") (pinfunction "1_1") (pintype "passive"))
      (node (ref "MM5") (pin "1") (pinfunction "1_1") (pintype "passive"))
      (node (ref "MM6") (pin "1") (pinfunction "1_1") (pintype "passive"))
      (node (ref "P1") (pin "2") (pinfunction "GND_2") (pintype "passive"))
      (node (ref "P1") (pin "4") (pinfunction "VI-_4") (pintype "passive"))
      (node (ref "PCI0") (pin "A12") (pinfunction "GND_A12") (pintype "passive"))
      (node (ref "PCI0") (pin "A13") (pinfunction "GND_A13") (pintype "passive"))
      (node (ref "PCI0") (pin "A18") (pinfunction "GND_A18") (pintype "passive"))
      (node (ref "PCI0") (pin "A24") (pinfunction "GND_A24") (pintype "passive"))
      (node (ref "PCI0") (pin "A30") (pinfunction "GND_A30") (pintype "passive"))
      (node (ref "PCI0") (pin "A35") (pinfunction "GND_A35") (pintype "passive"))
      (node (ref "PCI0") (pin "A37") (pinfunction "GND_A37") (pintype "passive"))
      (node (ref "PCI0") (pin "A42") (pinfunction "GND_A42") (pintype "passive"))
      (node (ref "PCI0") (pin "A48") (pinfunction "GND_A48") (pintype "passive"))
      (node (ref "PCI0") (pin "A56") (pinfunction "GND_A56") (pintype "passive"))
      (node (ref "PCI0") (pin "B12") (pinfunction "GND_B12") (pintype "passive"))
      (node (ref "PCI0") (pin "B13") (pinfunction "GND_B13") (pintype "passive"))
      (node (ref "PCI0") (pin "B15") (pinfunction "GND_B15") (pintype "passive"))
      (node (ref "PCI0") (pin "B17") (pinfunction "GND_B17") (pintype "passive"))
      (node (ref "PCI0") (pin "B22") (pinfunction "GND_B22") (pintype "passive"))
      (node (ref "PCI0") (pin "B28") (pinfunction "GND_B28") (pintype "passive"))
      (node (ref "PCI0") (pin "B3") (pinfunction "GND_B3") (pintype "passive"))
      (node (ref "PCI0") (pin "B34") (pinfunction "GND_B34") (pintype "passive"))
      (node (ref "PCI0") (pin "B38") (pinfunction "GND_B38") (pintype "passive"))
      (node (ref "PCI0") (pin "B46") (pinfunction "GND_B46") (pintype "passive"))
      (node (ref "PCI0") (pin "B49") (pinfunction "GND_B49") (pintype "passive"))
      (node (ref "PCI0") (pin "B57") (pinfunction "GND_B57") (pintype "passive"))
      (node (ref "PCI1") (pin "A12") (pinfunction "GND_A12") (pintype "passive"))
      (node (ref "PCI1") (pin "A13") (pinfunction "GND_A13") (pintype "passive"))
      (node (ref "PCI1") (pin "A18") (pinfunction "GND_A18") (pintype "passive"))
      (node (ref "PCI1") (pin "A24") (pinfunction "GND_A24") (pintype "passive"))
      (node (ref "PCI1") (pin "A30") (pinfunction "GND_A30") (pintype "passive"))
      (node (ref "PCI1") (pin "A35") (pinfunction "GND_A35") (pintype "passive"))
      (node (ref "PCI1") (pin "A37") (pinfunction "GND_A37") (pintype "passive"))
      (node (ref "PCI1") (pin "A42") (pinfunction "GND_A42") (pintype "passive"))
      (node (ref "PCI1") (pin "A48") (pinfunction "GND_A48") (pintype "passive"))
      (node (ref "PCI1") (pin "A56") (pinfunction "GND_A56") (pintype "passive"))
      (node (ref "PCI1") (pin "B12") (pinfunction "GND_B12") (pintype "passive"))
      (node (ref "PCI1") (pin "B13") (pinfunction "GND_B13") (pintype "passive"))
      (node (ref "PCI1") (pin "B15") (pinfunction "GND_B15") (pintype "passive"))
      (node (ref "PCI1") (pin "B17") (pinfunction "GND_B17") (pintype "passive"))
      (node (ref "PCI1") (pin "B22") (pinfunction "GND_B22") (pintype "passive"))
      (node (ref "PCI1") (pin "B28") (pinfunction "GND_B28") (pintype "passive"))
      (node (ref "PCI1") (pin "B3") (pinfunction "GND_B3") (pintype "passive"))
      (node (ref "PCI1") (pin "B34") (pinfunction "GND_B34") (pintype "passive"))
      (node (ref "PCI1") (pin "B38") (pinfunction "GND_B38") (pintype "passive"))
      (node (ref "PCI1") (pin "B46") (pinfunction "GND_B46") (pintype "passive"))
      (node (ref "PCI1") (pin "B49") (pinfunction "GND_B49") (pintype "passive"))
      (node (ref "PCI1") (pin "B57") (pinfunction "GND_B57") (pintype "passive"))
      (node (ref "PCI2") (pin "A12") (pinfunction "GND_A12") (pintype "passive"))
      (node (ref "PCI2") (pin "A13") (pinfunction "GND_A13") (pintype "passive"))
      (node (ref "PCI2") (pin "A18") (pinfunction "GND_A18") (pintype "passive"))
      (node (ref "PCI2") (pin "A24") (pinfunction "GND_A24") (pintype "passive"))
      (node (ref "PCI2") (pin "A30") (pinfunction "GND_A30") (pintype "passive"))
      (node (ref "PCI2") (pin "A35") (pinfunction "GND_A35") (pintype "passive"))
      (node (ref "PCI2") (pin "A37") (pinfunction "GND_A37") (pintype "passive"))
      (node (ref "PCI2") (pin "A42") (pinfunction "GND_A42") (pintype "passive"))
      (node (ref "PCI2") (pin "A48") (pinfunction "GND_A48") (pintype "passive"))
      (node (ref "PCI2") (pin "A56") (pinfunction "GND_A56") (pintype "passive"))
      (node (ref "PCI2") (pin "B12") (pinfunction "GND_B12") (pintype "passive"))
      (node (ref "PCI2") (pin "B13") (pinfunction "GND_B13") (pintype "passive"))
      (node (ref "PCI2") (pin "B15") (pinfunction "GND_B15") (pintype "passive"))
      (node (ref "PCI2") (pin "B17") (pinfunction "GND_B17") (pintype "passive"))
      (node (ref "PCI2") (pin "B22") (pinfunction "GND_B22") (pintype "passive"))
      (node (ref "PCI2") (pin "B28") (pinfunction "GND_B28") (pintype "passive"))
      (node (ref "PCI2") (pin "B3") (pinfunction "GND_B3") (pintype "passive"))
      (node (ref "PCI2") (pin "B34") (pinfunction "GND_B34") (pintype "passive"))
      (node (ref "PCI2") (pin "B38") (pinfunction "GND_B38") (pintype "passive"))
      (node (ref "PCI2") (pin "B46") (pinfunction "GND_B46") (pintype "passive"))
      (node (ref "PCI2") (pin "B49") (pinfunction "GND_B49") (pintype "passive"))
      (node (ref "PCI2") (pin "B57") (pinfunction "GND_B57") (pintype "passive"))
      (node (ref "Q3") (pin "E") (pinfunction "e_E") (pintype "passive"))
      (node (ref "Q4") (pin "E") (pinfunction "e_E") (pintype "passive"))
      (node (ref "Q5") (pin "2") (pinfunction "A_2") (pintype "passive"))
      (node (ref "R100") (pin "2") (pinfunction "2_2") (pintype "passive"))
      (node (ref "R101") (pin "2") (pinfunction "2_2") (pintype "passive"))
      (node (ref "R102") (pin "2") (pinfunction "2_2") (pintype "passive"))
      (node (ref "R103") (pin "2") (pinfunction "2_2") (pintype "passive"))
      (node (ref "R105") (pin "2") (pinfunction "2_2") (pintype "passive"))
      (node (ref "R106") (pin "2") (pinfunction "2_2") (pintype "passive"))
      (node (ref "R107") (pin "2") (pinfunction "2_2") (pintype "passive"))
      (node (ref "R29") (pin "2") (pinfunction "2_2") (pintype "passive"))
      (node (ref "R40") (pin "2") (pinfunction "2_2") (pintype "passive"))
      (node (ref "R49") (pin "2") (pinfunction "2_2") (pintype "passive"))
      (node (ref "R72") (pin "2") (pinfunction "2_2") (pintype "passive"))
      (node (ref "RU2") (pin "2") (pinfunction "2_2") (pintype "passive"))
      (node (ref "RU6") (pin "2") (pinfunction "2_2") (pintype "passive"))
      (node (ref "S1") (pin "2") (pinfunction "NC1_2") (pintype "passive"))
      (node (ref "S1") (pin "5") (pinfunction "COMMON2_5") (pintype "passive"))
      (node (ref "TFT1") (pin "10") (pinfunction "GND_10") (pintype "passive"))
      (node (ref "TFT1") (pin "11") (pinfunction "GND_11") (pintype "passive"))
      (node (ref "U10") (pin "1") (pinfunction "~{1G}_1") (pintype "input"))
      (node (ref "U10") (pin "15") (pinfunction "~{2G}_15") (pintype "input"))
      (node (ref "U10") (pin "8") (pinfunction "GND_8") (pintype "power_in"))
      (node (ref "U12") (pin "10") (pinfunction "GND_10") (pintype "power_in"))
      (node (ref "U13") (pin "101") (pinfunction "GND_6_101") (pintype "passive"))
      (node (ref "U13") (pin "11") (pinfunction "GND_1_11") (pintype "passive"))
      (node (ref "U13") (pin "115") (pinfunction "GND_7_115") (pintype "passive"))
      (node (ref "U13") (pin "138") (pinfunction "GND_8_138") (pintype "passive"))
      (node (ref "U13") (pin "153") (pinfunction "GND_9_153") (pintype "passive"))
      (node (ref "U13") (pin "166") (pinfunction "GND_10_166") (pintype "passive"))
      (node (ref "U13") (pin "181") (pinfunction "GND_11_181") (pintype "passive"))
      (node (ref "U13") (pin "204") (pinfunction "GND_12_204") (pintype "passive"))
      (node (ref "U13") (pin "32") (pinfunction "GND_2_32") (pintype "passive"))
      (node (ref "U13") (pin "52") (pinfunction "GND_3_52") (pintype "passive"))
      (node (ref "U13") (pin "71") (pinfunction "GND_4_71") (pintype "passive"))
      (node (ref "U13") (pin "88") (pinfunction "GND_5_88") (pintype "passive"))
      (node (ref "U14") (pin "10") (pinfunction "GND_10") (pintype "power_in"))
      (node (ref "U15") (pin "11") (pintype "input"))
      (node (ref "U15") (pin "13") (pintype "input"))
      (node (ref "U15") (pin "7") (pinfunction "GND_7") (pintype "power_in"))
      (node (ref "U15") (pin "9") (pintype "input"))
      (node (ref "U16") (pin "10") (pinfunction "GND_10") (pintype "power_in"))
      (node (ref "U16") (pin "19") (pinfunction "~{OE}_19") (pintype "input"))
      (node (ref "U17") (pin "10") (pinfunction "GND_10") (pintype "power_in"))
      (node (ref "U17") (pin "19") (pinfunction "~{OE}_19") (pintype "input"))
      (node (ref "U18") (pin "10") (pinfunction "GND_10") (pintype "power_in"))
      (node (ref "U18") (pin "19") (pinfunction "~{OE}_19") (pintype "input"))
      (node (ref "U19") (pin "10") (pinfunction "GND_10") (pintype "power_in"))
      (node (ref "U19") (pin "11") (pinfunction "I9/~{OE}_11") (pintype "passive"))
      (node (ref "U2") (pin "16") (pinfunction "GND_16") (pintype "passive"))
      (node (ref "U5") (pin "1") (pinfunction "~{1G}_1") (pintype "input"))
      (node (ref "U5") (pin "15") (pinfunction "~{2G}_15") (pintype "input"))
      (node (ref "U5") (pin "8") (pinfunction "GND_8") (pintype "power_in"))
      (node (ref "U6") (pin "1") (pinfunction "GND_1") (pintype "passive"))
      (node (ref "U6") (pin "11") (pinfunction "GND_11") (pintype "passive"))
      (node (ref "U6") (pin "7") (pinfunction "GND_7") (pintype "passive"))
      (node (ref "U7") (pin "1") (pinfunction "~{1G}_1") (pintype "input"))
      (node (ref "U7") (pin "10") (pinfunction "GND_10") (pintype "power_in"))
      (node (ref "U7") (pin "19") (pinfunction "~{2G}_19") (pintype "input"))
      (node (ref "U7") (pin "6") (pinfunction "1A3_6") (pintype "input"))
      (node (ref "U7") (pin "8") (pinfunction "1A4_8") (pintype "input"))
      (node (ref "U8") (pin "10") (pinfunction "GND_10") (pintype "power_in"))
      (node (ref "U9") (pin "10") (pinfunction "GND_10") (pintype "power_in"))
      (node (ref "UM1") (pin "10") (pinfunction "ADC_AGND_10") (pintype "passive"))
      (node (ref "UM1") (pin "16") (pinfunction "GND_16") (pintype "passive"))
      (node (ref "UM2") (pin "2") (pinfunction "A0_2") (pintype "passive"))
      (node (ref "UM2") (pin "6") (pinfunction "GND_6") (pintype "passive"))
      (node (ref "UM3") (pin "1") (pinfunction "A1_1") (pintype "passive"))
      (node (ref "UM3") (pin "6") (pinfunction "GND_6") (pintype "passive"))
      (node (ref "UM4") (pin "1") (pinfunction "A1_1") (pintype "passive"))
      (node (ref "UM4") (pin "2") (pinfunction "A0_2") (pintype "passive"))
      (node (ref "UM4") (pin "6") (pinfunction "GND_6") (pintype "passive"))
      (node (ref "UM5") (pin "1") (pinfunction "GND_1") (pintype "passive"))
      (node (ref "UM6") (pin "1") (pinfunction "GND_1") (pintype "passive"))
      (node (ref "UM8") (pin "2") (pinfunction "Gnd_2") (pintype "passive"))
      (node (ref "UM9") (pin "1") (pinfunction "GND_1") (pintype "passive"))
      (node (ref "USB1") (pin "0") (pinfunction "0_0") (pintype "passive"))
      (node (ref "USB1") (pin "5") (pinfunction "GND_5") (pintype "passive"))
    )
    (net (code "406") (name "Net-(B1-Pad2)") (class "Default")
      (node (ref "B1") (pin "2") (pinfunction "2_2") (pintype "passive"))
      (node (ref "R51") (pin "1") (pinfunction "1_1") (pintype "passive"))
    )
    (net (code "407") (name "Net-(BAT1-+)") (class "Default")
      (node (ref "BAT1") (pin "1") (pinfunction "+_1") (pintype "passive"))
      (node (ref "R46") (pin "2") (pinfunction "2_2") (pintype "passive"))
    )
    (net (code "408") (name "Net-(C132-Pad1)") (class "Default")
      (node (ref "C132") (pin "1") (pinfunction "1_1") (pintype "passive"))
      (node (ref "X2") (pin "1") (pinfunction "1_1") (pintype "passive"))
    )
    (net (code "409") (name "Net-(C132-Pad2)") (class "Default")
      (node (ref "C132") (pin "2") (pinfunction "2_2") (pintype "passive"))
      (node (ref "U15") (pin "4") (pintype "output"))
      (node (ref "U15") (pin "5") (pintype "input"))
    )
    (net (code "410") (name "Net-(CN1-Pad1)") (class "Default")
      (node (ref "CN1") (pin "1") (pinfunction "1_1") (pintype "passive"))
      (node (ref "R2") (pin "2") (pinfunction "2_2") (pintype "passive"))
    )
    (net (code "411") (name "Net-(CN1-Pad2)") (class "Default")
      (node (ref "CN1") (pin "2") (pinfunction "2_2") (pintype "passive"))
      (node (ref "R6") (pin "2") (pinfunction "2_2") (pintype "passive"))
    )
    (net (code "412") (name "Net-(CN1-Pad5)") (class "Default")
      (node (ref "CN1") (pin "5") (pinfunction "5_5") (pintype "passive"))
      (node (ref "R5") (pin "2") (pinfunction "2_2") (pintype "passive"))
    )
    (net (code "413") (name "Net-(CN2-Pad2)") (class "Default")
      (node (ref "CN2") (pin "2") (pinfunction "2_2") (pintype "passive"))
      (node (ref "RK1") (pin "2") (pinfunction "2_2") (pintype "passive"))
    )
    (net (code "414") (name "Net-(CN2-Pad3)") (class "Default")
      (node (ref "CN2") (pin "3") (pinfunction "3_3") (pintype "passive"))
      (node (ref "RK2") (pin "2") (pinfunction "2_2") (pintype "passive"))
    )
    (net (code "415") (name "Net-(CPU1-CACHE#)") (class "Default")
      (node (ref "CPU1") (pin "70") (pinfunction "CACHE#_70") (pintype "passive"))
      (node (ref "R69") (pin "2") (pinfunction "2_2") (pintype "passive"))
    )
    (net (code "416") (name "Net-(CU4-Pad2)") (class "Default")
      (node (ref "CU4") (pin "2") (pinfunction "2_2") (pintype "passive"))
      (node (ref "UM5") (pin "4") (pinfunction "VOUT_4") (pintype "passive"))
    )
    (net (code "417") (name "Net-(CU9-Pad2)") (class "Default")
      (node (ref "CU9") (pin "2") (pinfunction "2_2") (pintype "passive"))
      (node (ref "UM6") (pin "4") (pinfunction "VOUT_4") (pintype "passive"))
    )
    (net (code "418") (name "Net-(D3-PadA)") (class "Default")
      (node (ref "D3") (pin "A") (pinfunction "A_A") (pintype "passive"))
      (node (ref "R46") (pin "1") (pinfunction "1_1") (pintype "passive"))
    )
    (net (code "419") (name "Net-(DU1-PadK)") (class "Default")
      (node (ref "DU1") (pin "K") (pinfunction "K_K") (pintype "passive"))
      (node (ref "LU1") (pin "2") (pinfunction "2_2") (pintype "passive"))
      (node (ref "UM5") (pin "0") (pinfunction "0_0") (pintype "passive"))
      (node (ref "UM5") (pin "3") (pinfunction "VOUT_3") (pintype "passive"))
    )
    (net (code "420") (name "Net-(DU2-PadK)") (class "Default")
      (node (ref "DU2") (pin "K") (pinfunction "K_K") (pintype "passive"))
      (node (ref "LU2") (pin "2") (pinfunction "2_2") (pintype "passive"))
      (node (ref "UM6") (pin "0") (pinfunction "0_0") (pintype "passive"))
      (node (ref "UM6") (pin "3") (pinfunction "VOUT_3") (pintype "passive"))
    )
    (net (code "421") (name "Net-(J1-Pad1)") (class "Default")
      (node (ref "J1") (pin "1") (pinfunction "1_1") (pintype "passive"))
      (node (ref "R1") (pin "1") (pinfunction "1_1") (pintype "passive"))
    )
    (net (code "422") (name "Net-(JU1-+)") (class "Default")
      (node (ref "CU1") (pin "1") (pinfunction "1_1") (pintype "passive"))
      (node (ref "JU1") (pin "1") (pinfunction "+_1") (pintype "passive"))
      (node (ref "QM1") (pin "1") (pinfunction "S_1") (pintype "passive"))
      (node (ref "QM1") (pin "2") (pinfunction "S_2") (pintype "passive"))
      (node (ref "QM1") (pin "3") (pinfunction "S_3") (pintype "passive"))
      (node (ref "RU1") (pin "2") (pinfunction "2_2") (pintype "passive"))
    )
    (net (code "423") (name "Net-(LHD1-Pad1)") (class "Default")
      (node (ref "LHD1") (pin "1") (pintype "passive"))
      (node (ref "RL1") (pin "1") (pinfunction "1_1") (pintype "passive"))
    )
    (net (code "424") (name "Net-(LHD2-Pad1)") (class "Default")
      (node (ref "LHD2") (pin "1") (pintype "passive"))
      (node (ref "RL2") (pin "1") (pinfunction "1_1") (pintype "passive"))
    )
    (net (code "425") (name "Net-(PCI0-IDSEL)") (class "Default")
      (node (ref "PCI0") (pin "A26") (pinfunction "IDSEL_A26") (pintype "passive"))
      (node (ref "R118") (pin "2") (pinfunction "2_2") (pintype "passive"))
    )
    (net (code "426") (name "Net-(PCI1-IDSEL)") (class "Default")
      (node (ref "PCI1") (pin "A26") (pinfunction "IDSEL_A26") (pintype "passive"))
      (node (ref "R18") (pin "2") (pinfunction "2_2") (pintype "passive"))
    )
    (net (code "427") (name "Net-(PCI2-IDSEL)") (class "Default")
      (node (ref "PCI2") (pin "A26") (pinfunction "IDSEL_A26") (pintype "passive"))
      (node (ref "R19") (pin "2") (pinfunction "2_2") (pintype "passive"))
    )
    (net (code "428") (name "Net-(Q1-B)") (class "Default")
      (node (ref "Q1") (pin "3") (pinfunction "B_3") (pintype "passive"))
      (node (ref "Q5") (pin "3") (pinfunction "K_3") (pintype "passive"))
      (node (ref "R27") (pin "2") (pinfunction "2_2") (pintype "passive"))
    )
    (net (code "429") (name "Net-(Q2-b)") (class "Default")
      (node (ref "Q2") (pin "B") (pinfunction "b_B") (pintype "passive"))
      (node (ref "R42") (pin "1") (pinfunction "1_1") (pintype "passive"))
    )
    (net (code "430") (name "Net-(Q3-b)") (class "Default")
      (node (ref "Q3") (pin "B") (pinfunction "b_B") (pintype "passive"))
      (node (ref "R40") (pin "1") (pinfunction "1_1") (pintype "passive"))
      (node (ref "R41") (pin "2") (pinfunction "2_2") (pintype "passive"))
    )
    (net (code "431") (name "Net-(Q3-c)") (class "Default")
      (node (ref "Q3") (pin "C") (pinfunction "c_C") (pintype "passive"))
      (node (ref "R42") (pin "2") (pinfunction "2_2") (pintype "passive"))
    )
    (net (code "432") (name "Net-(Q4-b)") (class "Default")
      (node (ref "Q4") (pin "B") (pinfunction "b_B") (pintype "passive"))
      (node (ref "R43") (pin "1") (pinfunction "1_1") (pintype "passive"))
    )
    (net (code "433") (name "Net-(Q4-c)") (class "Default")
      (node (ref "Q4") (pin "C") (pinfunction "c_C") (pintype "passive"))
      (node (ref "R51") (pin "2") (pinfunction "2_2") (pintype "passive"))
    )
    (net (code "434") (name "Net-(Q5-REF)") (class "Default")
      (node (ref "Q5") (pin "1") (pinfunction "REF_1") (pintype "passive"))
      (node (ref "R29") (pin "1") (pinfunction "1_1") (pintype "passive"))
      (node (ref "R31") (pin "2") (pinfunction "2_2") (pintype "passive"))
    )
    (net (code "435") (name "Net-(QM1-G)") (class "Default")
      (node (ref "QM1") (pin "4") (pinfunction "G_4") (pintype "passive"))
      (node (ref "RU1") (pin "1") (pinfunction "1_1") (pintype "passive"))
      (node (ref "S1") (pin "3") (pinfunction "COMMON1_3") (pintype "passive"))
      (node (ref "S1") (pin "6") (pinfunction "NO2_6") (pintype "passive"))
    )
    (net (code "436") (name "Net-(R44-Pad1)") (class "Default")
      (node (ref "R44") (pin "1") (pinfunction "1_1") (pintype "passive"))
      (node (ref "U15") (pin "2") (pintype "output"))
      (node (ref "U15") (pin "3") (pintype "input"))
    )
    (net (code "437") (name "Net-(R44-Pad2)") (class "Default")
      (node (ref "R44") (pin "2") (pinfunction "2_2") (pintype "passive"))
      (node (ref "U15") (pin "1") (pintype "input"))
      (node (ref "X2") (pin "2") (pinfunction "2_2") (pintype "passive"))
    )
    (net (code "438") (name "Net-(RU2-Pad1)") (class "Default")
      (node (ref "RU2") (pin "1") (pinfunction "1_1") (pintype "passive"))
      (node (ref "UM5") (pin "2") (pinfunction "VOUT_2") (pintype "passive"))
      (node (ref "VR1") (pin "2") (pintype "passive"))
    )
    (net (code "439") (name "Net-(RU6-Pad1)") (class "Default")
      (node (ref "RU6") (pin "1") (pinfunction "1_1") (pintype "passive"))
      (node (ref "UM6") (pin "2") (pinfunction "VOUT_2") (pintype "passive"))
      (node (ref "VR2") (pin "2") (pintype "passive"))
    )
    (net (code "440") (name "Net-(U6-C)") (class "Default")
      (node (ref "C68") (pin "1") (pinfunction "1_1") (pintype "passive"))
      (node (ref "U6") (pin "10") (pinfunction "C_10") (pintype "passive"))
    )
    (net (code "441") (name "Net-(U6-J5)") (class "Default")
      (node (ref "J5") (pin "3") (pinfunction "3_3") (pintype "passive"))
      (node (ref "U6") (pin "12") (pinfunction "J5_12") (pintype "passive"))
    )
    (net (code "442") (name "Net-(U6-J6)") (class "Default")
      (node (ref "J5") (pin "1") (pinfunction "1_1") (pintype "passive"))
      (node (ref "U6") (pin "13") (pinfunction "J6_13") (pintype "passive"))
    )
    (net (code "443") (name "Net-(U6-VCC(LC))") (class "Default")
      (node (ref "C66") (pin "2") (pinfunction "2_2") (pintype "passive"))
      (node (ref "C67") (pin "2") (pinfunction "2_2") (pintype "passive"))
      (node (ref "L1") (pin "2") (pinfunction "2_2") (pintype "passive"))
      (node (ref "U6") (pin "9") (pinfunction "VCC(LC)_9") (pintype "passive"))
    )
    (net (code "444") (name "Net-(U6-VCC(RC))") (class "Default")
      (node (ref "58") (pin "2") (pinfunction "2_2") (pintype "passive"))
      (node (ref "C57") (pin "2") (pinfunction "2_2") (pintype "passive"))
      (node (ref "R17") (pin "2") (pinfunction "2_2") (pintype "passive"))
      (node (ref "U6") (pin "14") (pinfunction "VCC(RC)_14") (pintype "passive"))
    )
    (net (code "445") (name "Net-(U6-X1)") (class "Default")
      (node (ref "C63") (pin "2") (pinfunction "2_2") (pintype "passive"))
      (node (ref "U6") (pin "2") (pinfunction "X1_2") (pintype "passive"))
      (node (ref "X1") (pin "2") (pinfunction "2_2") (pintype "passive"))
    )
    (net (code "446") (name "Net-(U6-X2)") (class "Default")
      (node (ref "C64") (pin "2") (pinfunction "2_2") (pintype "passive"))
      (node (ref "U6") (pin "3") (pinfunction "X2_3") (pintype "passive"))
      (node (ref "X1") (pin "1") (pinfunction "1_1") (pintype "passive"))
    )
    (net (code "447") (name "Net-(U7-1Y1)") (class "Default")
      (node (ref "R25") (pin "2") (pinfunction "2_2") (pintype "passive"))
      (node (ref "U7") (pin "18") (pinfunction "1Y1_18") (pintype "output"))
    )
    (net (code "448") (name "Net-(U7-1Y2)") (class "Default")
      (node (ref "R26") (pin "2") (pinfunction "2_2") (pintype "passive"))
      (node (ref "U7") (pin "16") (pinfunction "1Y2_16") (pintype "output"))
    )
    (net (code "449") (name "Net-(U7-2Y1)") (class "Default")
      (node (ref "R16") (pin "2") (pinfunction "2_2") (pintype "passive"))
      (node (ref "U7") (pin "9") (pinfunction "2Y1_9") (pintype "output"))
    )
    (net (code "450") (name "Net-(U7-2Y2)") (class "Default")
      (node (ref "R20") (pin "2") (pinfunction "2_2") (pintype "passive"))
      (node (ref "U7") (pin "7") (pinfunction "2Y2_7") (pintype "output"))
    )
    (net (code "451") (name "Net-(U7-2Y4)") (class "Default")
      (node (ref "R24") (pin "2") (pinfunction "2_2") (pintype "passive"))
      (node (ref "U7") (pin "3") (pinfunction "2Y4_3") (pintype "output"))
    )
    (net (code "452") (name "Net-(U13-BALE)") (class "Default")
      (node (ref "R33") (pin "2") (pinfunction "2_2") (pintype "passive"))
      (node (ref "U13") (pin "187") (pinfunction "BALE_187") (pintype "passive"))
    )
    (net (code "453") (name "Net-(U13-IOR#)") (class "Default")
      (node (ref "RP23") (pin "2") (pinfunction "2_2") (pintype "passive"))
      (node (ref "U13") (pin "163") (pinfunction "IOR#_163") (pintype "passive"))
    )
    (net (code "454") (name "Net-(U13-IOW#)") (class "Default")
      (node (ref "RP24") (pin "2") (pinfunction "2_2") (pintype "passive"))
      (node (ref "U13") (pin "162") (pinfunction "IOW#_162") (pintype "passive"))
    )
    (net (code "455") (name "Net-(U13-MEMR#)") (class "Default")
      (node (ref "R36") (pin "2") (pinfunction "2_2") (pintype "passive"))
      (node (ref "U13") (pin "194") (pinfunction "MEMR#_194") (pintype "passive"))
    )
    (net (code "456") (name "Net-(U13-MEMW#)") (class "Default")
      (node (ref "R37") (pin "2") (pinfunction "2_2") (pintype "passive"))
      (node (ref "U13") (pin "196") (pinfunction "MEMW#_196") (pintype "passive"))
    )
    (net (code "457") (name "Net-(U13-SMEMR#)") (class "Default")
      (node (ref "RP21") (pin "2") (pinfunction "2_2") (pintype "passive"))
      (node (ref "U13") (pin "161") (pinfunction "SMEMR#_161") (pintype "passive"))
    )
    (net (code "458") (name "Net-(U13-SMEMW#)") (class "Default")
      (node (ref "RP22") (pin "2") (pinfunction "2_2") (pintype "passive"))
      (node (ref "U13") (pin "160") (pinfunction "SMEMW#_160") (pintype "passive"))
    )
    (net (code "459") (name "Net-(U13-SYSCLK)") (class "Default")
      (node (ref "R35") (pin "2") (pinfunction "2_2") (pintype "passive"))
      (node (ref "U13") (pin "174") (pinfunction "SYSCLK_174") (pintype "passive"))
    )
    (net (code "460") (name "Net-(UM1-P3.5{slash}T1{slash}T0CLKO{slash}ECI_4{slash}SS_4{slash}PWMFLT)") (class "Default")
      (node (ref "RU20") (pin "1") (pinfunction "1_1") (pintype "passive"))
      (node (ref "UM1") (pin "23") (pinfunction "P3.5/T1/T0CLKO/ECI_4/SS_4/PWMFLT_23") (pintype "passive"))
    )
    (net (code "461") (name "Net-(UM1-P3.6{slash}INT2{slash}WR_2{slash}RXD_2{slash}CMP-)") (class "Default")
      (node (ref "RU19") (pin "1") (pinfunction "1_1") (pintype "passive"))
      (node (ref "UM1") (pin "24") (pinfunction "P3.6/INT2/WR_2/RXD_2/CMP-_24") (pintype "passive"))
    )
    (net (code "462") (name "Net-(UM3-IN+)") (class "Default")
      (node (ref "CU7") (pin "1") (pinfunction "1_1") (pintype "passive"))
      (node (ref "CU8") (pin "1") (pinfunction "1_1") (pintype "passive"))
      (node (ref "LU2") (pin "1") (pinfunction "1_1") (pintype "passive"))
      (node (ref "RU5") (pin "2") (pinfunction "2_2") (pintype "passive"))
      (node (ref "UM3") (pin "8") (pinfunction "IN+_8") (pintype "passive"))
      (node (ref "VR2") (pin "1") (pintype "passive"))
      (node (ref "VR2") (pin "W") (pintype "passive"))
    )
    (net (code "463") (name "Net-(UM4-IN+)") (class "Default")
      (node (ref "CU5") (pin "1") (pinfunction "1_1") (pintype "passive"))
      (node (ref "CU6") (pin "1") (pinfunction "1_1") (pintype "passive"))
      (node (ref "LU1") (pin "1") (pinfunction "1_1") (pintype "passive"))
      (node (ref "RU3") (pin "2") (pinfunction "2_2") (pintype "passive"))
      (node (ref "UM4") (pin "8") (pinfunction "IN+_8") (pintype "passive"))
      (node (ref "VR1") (pin "1") (pintype "passive"))
      (node (ref "VR1") (pin "W") (pintype "passive"))
    )
    (net (code "464") (name "Net-(UM8-+5V)") (class "Default")
      (node (ref "CU13") (pin "1") (pinfunction "1_1") (pintype "passive"))
      (node (ref "CU14") (pin "1") (pinfunction "1_1") (pintype "passive"))
      (node (ref "DM3") (pin "A") (pinfunction "A_A") (pintype "passive"))
      (node (ref "UM8") (pin "3") (pinfunction "+5V_3") (pintype "passive"))
    )
    (net (code "465") (name "Net-(UM9-RxD)") (class "Default")
      (node (ref "RU7") (pin "2") (pinfunction "2_2") (pintype "passive"))
      (node (ref "UM9") (pin "3") (pinfunction "RxD_3") (pintype "passive"))
    )
    (net (code "466") (name "Net-(UM9-TxD)") (class "Default")
      (node (ref "RU8") (pin "2") (pinfunction "2_2") (pintype "passive"))
      (node (ref "UM9") (pin "2") (pinfunction "TxD_2") (pintype "passive"))
    )
    (net (code "467") (name "Net-(UM9-V3.3)") (class "Default")
      (node (ref "CU15") (pin "2") (pinfunction "2_2") (pintype "passive"))
      (node (ref "UM9") (pin "4") (pinfunction "V3.3_4") (pintype "passive"))
    )
    (net (code "468") (name "VCC") (class "Default")
      (node (ref "B1") (pin "1") (pinfunction "1_1") (pintype "passive"))
      (node (ref "CN2") (pin "1") (pinfunction "1_1") (pintype "passive"))
      (node (ref "CT1") (pin "3") (pinfunction "3_3") (pintype "passive"))
      (node (ref "CT1") (pin "4") (pinfunction "4_4") (pintype "passive"))
      (node (ref "CT1") (pin "47") (pinfunction "47_47") (pintype "passive"))
      (node (ref "CT1") (pin "48") (pinfunction "48_48") (pintype "passive"))
      (node (ref "CT1") (pin "49") (pinfunction "49_49") (pintype "passive"))
      (node (ref "CT1") (pin "5") (pinfunction "5_5") (pintype "passive"))
      (node (ref "CV1") (pin "1") (pinfunction "1_1") (pintype "passive"))
      (node (ref "CV10") (pin "1") (pinfunction "1_1") (pintype "passive"))
      (node (ref "CV11") (pin "1") (pinfunction "1_1") (pintype "passive"))
      (node (ref "CV12") (pin "1") (pinfunction "1_1") (pintype "passive"))
      (node (ref "CV13") (pin "1") (pinfunction "1_1") (pintype "passive"))
      (node (ref "CV14") (pin "1") (pinfunction "1_1") (pintype "passive"))
      (node (ref "CV15") (pin "1") (pinfunction "1_1") (pintype "passive"))
      (node (ref "CV16") (pin "1") (pinfunction "1_1") (pintype "passive"))
      (node (ref "CV17") (pin "1") (pinfunction "1_1") (pintype "passive"))
      (node (ref "CV18") (pin "1") (pinfunction "1_1") (pintype "passive"))
      (node (ref "CV19") (pin "1") (pinfunction "1_1") (pintype "passive"))
      (node (ref "CV2") (pin "1") (pinfunction "1_1") (pintype "passive"))
      (node (ref "CV20") (pin "1") (pinfunction "1_1") (pintype "passive"))
      (node (ref "CV21") (pin "1") (pinfunction "1_1") (pintype "passive"))
      (node (ref "CV22") (pin "1") (pinfunction "1_1") (pintype "passive"))
      (node (ref "CV3") (pin "1") (pinfunction "1_1") (pintype "passive"))
      (node (ref "CV4") (pin "1") (pinfunction "1_1") (pintype "passive"))
      (node (ref "CV5") (pin "1") (pinfunction "1_1") (pintype "passive"))
      (node (ref "CV6") (pin "1") (pinfunction "1_1") (pintype "passive"))
      (node (ref "CV7") (pin "1") (pinfunction "1_1") (pintype "passive"))
      (node (ref "CV8") (pin "1") (pinfunction "1_1") (pintype "passive"))
      (node (ref "CV9") (pin "1") (pinfunction "1_1") (pintype "passive"))
      (node (ref "D7") (pin "K") (pinfunction "K_K") (pintype "passive"))
      (node (ref "ISA1") (pin "B03") (pinfunction "+5V_B03") (pintype "passive"))
      (node (ref "ISA1") (pin "B29") (pinfunction "+5V_B29") (pintype "passive"))
      (node (ref "ISA1") (pin "D16") (pinfunction "+5V_D16") (pintype "passive"))
      (node (ref "ISA2") (pin "B03") (pinfunction "+5V_B03") (pintype "passive"))
      (node (ref "ISA2") (pin "B29") (pinfunction "+5V_B29") (pintype "passive"))
      (node (ref "ISA2") (pin "D16") (pinfunction "+5V_D16") (pintype "passive"))
      (node (ref "ISA3") (pin "B03") (pinfunction "+5V_B03") (pintype "passive"))
      (node (ref "ISA3") (pin "B29") (pinfunction "+5V_B29") (pintype "passive"))
      (node (ref "ISA3") (pin "D16") (pinfunction "+5V_D16") (pintype "passive"))
      (node (ref "JIDE") (pin "2") (pinfunction "2_2") (pintype "passive"))
      (node (ref "L1") (pin "1") (pinfunction "1_1") (pintype "passive"))
      (node (ref "M1") (pin "10") (pinfunction "VCC_10") (pintype "passive"))
      (node (ref "M1") (pin "30") (pinfunction "VCC_30") (pintype "passive"))
      (node (ref "M1") (pin "59") (pinfunction "VCC_59") (pintype "passive"))
      (node (ref "M2") (pin "10") (pinfunction "VCC_10") (pintype "passive"))
      (node (ref "M2") (pin "30") (pinfunction "VCC_30") (pintype "passive"))
      (node (ref "M2") (pin "59") (pinfunction "VCC_59") (pintype "passive"))
      (node (ref "M3") (pin "10") (pinfunction "VCC_10") (pintype "passive"))
      (node (ref "M3") (pin "30") (pinfunction "VCC_30") (pintype "passive"))
      (node (ref "M3") (pin "59") (pinfunction "VCC_59") (pintype "passive"))
      (node (ref "M4") (pin "10") (pinfunction "VCC_10") (pintype "passive"))
      (node (ref "M4") (pin "30") (pinfunction "VCC_30") (pintype "passive"))
      (node (ref "M4") (pin "59") (pinfunction "VCC_59") (pintype "passive"))
      (node (ref "PCI0") (pin "A10") (pinfunction "5V(IO)_A10") (pintype "passive"))
      (node (ref "PCI0") (pin "A16") (pinfunction "5V(IO)_A16") (pintype "passive"))
      (node (ref "PCI0") (pin "A5") (pinfunction "5V_A5") (pintype "passive"))
      (node (ref "PCI0") (pin "A59") (pinfunction "5V(IO)_A59") (pintype "passive"))
      (node (ref "PCI0") (pin "A61") (pinfunction "5V_A61") (pintype "passive"))
      (node (ref "PCI0") (pin "A62") (pinfunction "5V_A62") (pintype "passive"))
      (node (ref "PCI0") (pin "A8") (pinfunction "5V_A8") (pintype "passive"))
      (node (ref "PCI0") (pin "B19") (pinfunction "5V(IO)_B19") (pintype "passive"))
      (node (ref "PCI0") (pin "B5") (pinfunction "5V_B5") (pintype "passive"))
      (node (ref "PCI0") (pin "B59") (pinfunction "5V(IO)_B59") (pintype "passive"))
      (node (ref "PCI0") (pin "B6") (pinfunction "5V_B6") (pintype "passive"))
      (node (ref "PCI0") (pin "B61") (pinfunction "5V_B61") (pintype "passive"))
      (node (ref "PCI0") (pin "B62") (pinfunction "5V_B62") (pintype "passive"))
      (node (ref "PCI1") (pin "A10") (pinfunction "5V(IO)_A10") (pintype "passive"))
      (node (ref "PCI1") (pin "A16") (pinfunction "5V(IO)_A16") (pintype "passive"))
      (node (ref "PCI1") (pin "A5") (pinfunction "5V_A5") (pintype "passive"))
      (node (ref "PCI1") (pin "A59") (pinfunction "5V(IO)_A59") (pintype "passive"))
      (node (ref "PCI1") (pin "A61") (pinfunction "5V_A61") (pintype "passive"))
      (node (ref "PCI1") (pin "A62") (pinfunction "5V_A62") (pintype "passive"))
      (node (ref "PCI1") (pin "A8") (pinfunction "5V_A8") (pintype "passive"))
      (node (ref "PCI1") (pin "B19") (pinfunction "5V(IO)_B19") (pintype "passive"))
      (node (ref "PCI1") (pin "B5") (pinfunction "5V_B5") (pintype "passive"))
      (node (ref "PCI1") (pin "B59") (pinfunction "5V(IO)_B59") (pintype "passive"))
      (node (ref "PCI1") (pin "B6") (pinfunction "5V_B6") (pintype "passive"))
      (node (ref "PCI1") (pin "B61") (pinfunction "5V_B61") (pintype "passive"))
      (node (ref "PCI1") (pin "B62") (pinfunction "5V_B62") (pintype "passive"))
      (node (ref "PCI2") (pin "A10") (pinfunction "5V(IO)_A10") (pintype "passive"))
      (node (ref "PCI2") (pin "A16") (pinfunction "5V(IO)_A16") (pintype "passive"))
      (node (ref "PCI2") (pin "A5") (pinfunction "5V_A5") (pintype "passive"))
      (node (ref "PCI2") (pin "A59") (pinfunction "5V(IO)_A59") (pintype "passive"))
      (node (ref "PCI2") (pin "A61") (pinfunction "5V_A61") (pintype "passive"))
      (node (ref "PCI2") (pin "A62") (pinfunction "5V_A62") (pintype "passive"))
      (node (ref "PCI2") (pin "A8") (pinfunction "5V_A8") (pintype "passive"))
      (node (ref "PCI2") (pin "B19") (pinfunction "5V(IO)_B19") (pintype "passive"))
      (node (ref "PCI2") (pin "B5") (pinfunction "5V_B5") (pintype "passive"))
      (node (ref "PCI2") (pin "B59") (pinfunction "5V(IO)_B59") (pintype "passive"))
      (node (ref "PCI2") (pin "B6") (pinfunction "5V_B6") (pintype "passive"))
      (node (ref "PCI2") (pin "B61") (pinfunction "5V_B61") (pintype "passive"))
      (node (ref "PCI2") (pin "B62") (pinfunction "5V_B62") (pintype "passive"))
      (node (ref "Q2") (pin "E") (pinfunction "e_E") (pintype "passive"))
      (node (ref "R11") (pin "2") (pinfunction "2_2") (pintype "passive"))
      (node (ref "R12") (pin "2") (pinfunction "2_2") (pintype "passive"))
      (node (ref "R13") (pin "2") (pinfunction "2_2") (pintype "passive"))
      (node (ref "R14") (pin "2") (pinfunction "2_2") (pintype "passive"))
      (node (ref "R17") (pin "1") (pinfunction "1_1") (pintype "passive"))
      (node (ref "R3") (pin "2") (pinfunction "2_2") (pintype "passive"))
      (node (ref "R39") (pin "2") (pinfunction "2_2") (pintype "passive"))
      (node (ref "R41") (pin "1") (pinfunction "1_1") (pintype "passive"))
      (node (ref "R45") (pin "2") (pinfunction "2_2") (pintype "passive"))
      (node (ref "R47") (pin "2") (pinfunction "2_2") (pintype "passive"))
      (node (ref "R48") (pin "2") (pinfunction "2_2") (pintype "passive"))
      (node (ref "R5") (pin "1") (pinfunction "1_1") (pintype "passive"))
      (node (ref "R55") (pin "1") (pinfunction "1_1") (pintype "passive"))
      (node (ref "R56") (pin "2") (pinfunction "2_2") (pintype "passive"))
      (node (ref "R57") (pin "2") (pinfunction "2_2") (pintype "passive"))
      (node (ref "R59") (pin "2") (pinfunction "2_2") (pintype "passive"))
      (node (ref "R60") (pin "2") (pinfunction "2_2") (pintype "passive"))
      (node (ref "R61") (pin "2") (pinfunction "2_2") (pintype "passive"))
      (node (ref "R62") (pin "2") (pinfunction "2_2") (pintype "passive"))
      (node (ref "R63") (pin "2") (pinfunction "2_2") (pintype "passive"))
      (node (ref "R64") (pin "2") (pinfunction "2_2") (pintype "passive"))
      (node (ref "R8") (pin "2") (pinfunction "2_2") (pintype "passive"))
      (node (ref "RL1") (pin "2") (pinfunction "2_2") (pintype "passive"))
      (node (ref "RL2") (pin "2") (pinfunction "2_2") (pintype "passive"))
      (node (ref "RN51") (pin "2") (pinfunction "2_2") (pintype "passive"))
      (node (ref "RN52") (pin "2") (pinfunction "2_2") (pintype "passive"))
      (node (ref "RN53") (pin "2") (pinfunction "2_2") (pintype "passive"))
      (node (ref "RN54") (pin "2") (pinfunction "2_2") (pintype "passive"))
      (node (ref "RN55") (pin "2") (pinfunction "2_2") (pintype "passive"))
      (node (ref "RN56") (pin "2") (pinfunction "2_2") (pintype "passive"))
      (node (ref "RN57") (pin "2") (pinfunction "2_2") (pintype "passive"))
      (node (ref "RN58") (pin "2") (pinfunction "2_2") (pintype "passive"))
      (node (ref "RN59") (pin "2") (pinfunction "2_2") (pintype "passive"))
      (node (ref "RN60") (pin "2") (pinfunction "2_2") (pintype "passive"))
      (node (ref "RN61") (pin "2") (pinfunction "2_2") (pintype "passive"))
      (node (ref "RN62") (pin "2") (pinfunction "2_2") (pintype "passive"))
      (node (ref "RN63") (pin "2") (pinfunction "2_2") (pintype "passive"))
      (node (ref "RN64") (pin "2") (pinfunction "2_2") (pintype "passive"))
      (node (ref "RN65") (pin "2") (pinfunction "2_2") (pintype "passive"))
      (node (ref "RN66") (pin "2") (pinfunction "2_2") (pintype "passive"))
      (node (ref "RN67") (pin "2") (pinfunction "2_2") (pintype "passive"))
      (node (ref "RN68") (pin "2") (pinfunction "2_2") (pintype "passive"))
      (node (ref "RN69") (pin "2") (pinfunction "2_2") (pintype "passive"))
      (node (ref "RN70") (pin "2") (pinfunction "2_2") (pintype "passive"))
      (node (ref "RN71") (pin "2") (pinfunction "2_2") (pintype "passive"))
      (node (ref "RN72") (pin "2") (pinfunction "2_2") (pintype "passive"))
      (node (ref "RN73") (pin "2") (pinfunction "2_2") (pintype "passive"))
      (node (ref "RN74") (pin "2") (pinfunction "2_2") (pintype "passive"))
      (node (ref "RN75") (pin "2") (pinfunction "2_2") (pintype "passive"))
      (node (ref "RN76") (pin "2") (pinfunction "2_2") (pintype "passive"))
      (node (ref "RN77") (pin "2") (pinfunction "2_2") (pintype "passive"))
      (node (ref "RN78") (pin "2") (pinfunction "2_2") (pintype "passive"))
      (node (ref "RN79") (pin "2") (pinfunction "2_2") (pintype "passive"))
      (node (ref "RN80") (pin "2") (pinfunction "2_2") (pintype "passive"))
      (node (ref "RN81") (pin "2") (pinfunction "2_2") (pintype "passive"))
      (node (ref "RN82") (pin "2") (pinfunction "2_2") (pintype "passive"))
      (node (ref "RQ1") (pin "2") (pinfunction "2_2") (pintype "passive"))
      (node (ref "RQ10") (pin "2") (pinfunction "2_2") (pintype "passive"))
      (node (ref "RQ11") (pin "2") (pinfunction "2_2") (pintype "passive"))
      (node (ref "RQ12") (pin "2") (pinfunction "2_2") (pintype "passive"))
      (node (ref "RQ2") (pin "2") (pinfunction "2_2") (pintype "passive"))
      (node (ref "RQ3") (pin "2") (pinfunction "2_2") (pintype "passive"))
      (node (ref "RQ4") (pin "2") (pinfunction "2_2") (pintype "passive"))
      (node (ref "RQ5") (pin "2") (pinfunction "2_2") (pintype "passive"))
      (node (ref "RQ6") (pin "2") (pinfunction "2_2") (pintype "passive"))
      (node (ref "RQ7") (pin "2") (pinfunction "2_2") (pintype "passive"))
      (node (ref "RQ8") (pin "2") (pinfunction "2_2") (pintype "passive"))
      (node (ref "RQ9") (pin "2") (pinfunction "2_2") (pintype "passive"))
      (node (ref "RU3") (pin "1") (pinfunction "1_1") (pintype "passive"))
      (node (ref "RU4") (pin "2") (pinfunction "2_2") (pintype "passive"))
      (node (ref "U10") (pin "16") (pinfunction "VCC_16") (pintype "power_in"))
      (node (ref "U12") (pin "20") (pinfunction "VCC_20") (pintype "power_in"))
      (node (ref "U14") (pin "20") (pinfunction "VCC_20") (pintype "power_in"))
      (node (ref "U16") (pin "1") (pinfunction "DIR_1") (pintype "input"))
      (node (ref "U16") (pin "20") (pinfunction "VCC_20") (pintype "power_in"))
      (node (ref "U17") (pin "20") (pinfunction "VCC_20") (pintype "power_in"))
      (node (ref "U18") (pin "20") (pinfunction "VCC_20") (pintype "power_in"))
      (node (ref "U19") (pin "20") (pinfunction "VCC_20") (pintype "power_in"))
      (node (ref "U2") (pin "1") (pinfunction "VPP_1") (pintype "passive"))
      (node (ref "U2") (pin "30") (pinfunction "NC_30") (pintype "passive"))
      (node (ref "U2") (pin "32") (pinfunction "VCC_32") (pintype "passive"))
      (node (ref "U5") (pin "16") (pinfunction "VCC_16") (pintype "power_in"))
      (node (ref "U7") (pin "20") (pinfunction "VCC_20") (pintype "power_in"))
      (node (ref "U8") (pin "20") (pinfunction "VCC_20") (pintype "power_in"))
      (node (ref "U9") (pin "20") (pinfunction "VCC_20") (pintype "power_in"))
      (node (ref "UM2") (pin "8") (pinfunction "IN+_8") (pintype "passive"))
      (node (ref "UM4") (pin "7") (pinfunction "IN-_7") (pintype "passive"))
    )
    (net (code "469") (name "VCC5") (class "Default")
      (node (ref "Q1") (pin "2") (pinfunction "C_2") (pintype "passive"))
      (node (ref "R27") (pin "1") (pinfunction "1_1") (pintype "passive"))
      (node (ref "RU4") (pin "1") (pinfunction "1_1") (pintype "passive"))
      (node (ref "UM2") (pin "7") (pinfunction "IN-_7") (pintype "passive"))
    )
    (net (code "470") (name "VCC_CPU") (class "Default")
      (node (ref "C1") (pin "1") (pinfunction "1_1") (pintype "passive"))
      (node (ref "C13") (pin "1") (pinfunction "1_1") (pintype "passive"))
      (node (ref "C14") (pin "1") (pinfunction "1_1") (pintype "passive"))
      (node (ref "C15") (pin "1") (pinfunction "1_1") (pintype "passive"))
      (node (ref "C16") (pin "1") (pinfunction "1_1") (pintype "passive"))
      (node (ref "C17") (pin "1") (pinfunction "1_1") (pintype "passive"))
      (node (ref "C18") (pin "1") (pinfunction "1_1") (pintype "passive"))
      (node (ref "C19") (pin "1") (pinfunction "1_1") (pintype "passive"))
      (node (ref "C2") (pin "1") (pinfunction "1_1") (pintype "passive"))
      (node (ref "C20") (pin "1") (pinfunction "1_1") (pintype "passive"))
      (node (ref "C21") (pin "1") (pinfunction "1_1") (pintype "passive"))
      (node (ref "C22") (pin "1") (pinfunction "1_1") (pintype "passive"))
      (node (ref "C23") (pin "1") (pinfunction "1_1") (pintype "passive"))
      (node (ref "C3") (pin "1") (pinfunction "1_1") (pintype "passive"))
      (node (ref "C4") (pin "1") (pinfunction "1_1") (pintype "passive"))
      (node (ref "C5") (pin "1") (pinfunction "1_1") (pintype "passive"))
      (node (ref "C6") (pin "1") (pinfunction "1_1") (pintype "passive"))
      (node (ref "C7") (pin "1") (pinfunction "1_1") (pintype "passive"))
      (node (ref "CC12") (pin "1") (pinfunction "1_1") (pintype "passive"))
      (node (ref "CC13") (pin "1") (pinfunction "1_1") (pintype "passive"))
      (node (ref "CC14") (pin "1") (pinfunction "1_1") (pintype "passive"))
      (node (ref "CPU1") (pin "102") (pinfunction "VCC_102") (pintype "passive"))
      (node (ref "CPU1") (pin "106") (pinfunction "VCC_106") (pintype "passive"))
      (node (ref "CPU1") (pin "111") (pinfunction "VCC_111") (pintype "passive"))
      (node (ref "CPU1") (pin "114") (pinfunction "VCC_114") (pintype "passive"))
      (node (ref "CPU1") (pin "121") (pinfunction "VCC_121") (pintype "passive"))
      (node (ref "CPU1") (pin "128") (pinfunction "VCC_128") (pintype "passive"))
      (node (ref "CPU1") (pin "131") (pinfunction "VCC_131") (pintype "passive"))
      (node (ref "CPU1") (pin "133") (pinfunction "VCC_133") (pintype "passive"))
      (node (ref "CPU1") (pin "134") (pinfunction "VCC_134") (pintype "passive"))
      (node (ref "CPU1") (pin "136") (pinfunction "VCC_136") (pintype "passive"))
      (node (ref "CPU1") (pin "137") (pinfunction "VCC_137") (pintype "passive"))
      (node (ref "CPU1") (pin "139") (pinfunction "VCC_139") (pintype "passive"))
      (node (ref "CPU1") (pin "14") (pinfunction "VCC_14") (pintype "passive"))
      (node (ref "CPU1") (pin "150") (pinfunction "VCC_150") (pintype "passive"))
      (node (ref "CPU1") (pin "155") (pinfunction "VCC_155") (pintype "passive"))
      (node (ref "CPU1") (pin "162") (pinfunction "VCC_162") (pintype "passive"))
      (node (ref "CPU1") (pin "163") (pinfunction "VCC_163") (pintype "passive"))
      (node (ref "CPU1") (pin "169") (pinfunction "VCC_169") (pintype "passive"))
      (node (ref "CPU1") (pin "172") (pinfunction "VCC_172") (pintype "passive"))
      (node (ref "CPU1") (pin "176") (pinfunction "VCC_176") (pintype "passive"))
      (node (ref "CPU1") (pin "179") (pinfunction "VCC_179") (pintype "passive"))
      (node (ref "CPU1") (pin "183") (pinfunction "VCC_183") (pintype "passive"))
      (node (ref "CPU1") (pin "185") (pinfunction "VCC_185") (pintype "passive"))
      (node (ref "CPU1") (pin "188") (pinfunction "VCC_188") (pintype "passive"))
      (node (ref "CPU1") (pin "19") (pinfunction "VCC_19") (pintype "passive"))
      (node (ref "CPU1") (pin "191") (pinfunction "VCC_191") (pintype "passive"))
      (node (ref "CPU1") (pin "198") (pinfunction "VCC_198") (pintype "passive"))
      (node (ref "CPU1") (pin "2") (pinfunction "VCC_2") (pintype "passive"))
      (node (ref "CPU1") (pin "20") (pinfunction "VCC_20") (pintype "passive"))
      (node (ref "CPU1") (pin "200") (pinfunction "VCC_200") (pintype "passive"))
      (node (ref "CPU1") (pin "205") (pinfunction "VCC_205") (pintype "passive"))
      (node (ref "CPU1") (pin "22") (pinfunction "VCC_22") (pintype "passive"))
      (node (ref "CPU1") (pin "23") (pinfunction "VCC_23") (pintype "passive"))
      (node (ref "CPU1") (pin "25") (pinfunction "VCC_25") (pintype "passive"))
      (node (ref "CPU1") (pin "29") (pinfunction "VCC_29") (pintype "passive"))
      (node (ref "CPU1") (pin "35") (pinfunction "VCC_35") (pintype "passive"))
      (node (ref "CPU1") (pin "38") (pinfunction "VCC_38") (pintype "passive"))
      (node (ref "CPU1") (pin "42") (pinfunction "VCC_42") (pintype "passive"))
      (node (ref "CPU1") (pin "44") (pinfunction "VCC_44") (pintype "passive"))
      (node (ref "CPU1") (pin "45") (pinfunction "VCC_45") (pintype "passive"))
      (node (ref "CPU1") (pin "49") (pinfunction "FLUSH#_49") (pintype "passive"))
      (node (ref "CPU1") (pin "54") (pinfunction "VCC_54") (pintype "passive"))
      (node (ref "CPU1") (pin "56") (pinfunction "VCC_56") (pintype "passive"))
      (node (ref "CPU1") (pin "60") (pinfunction "VCC_60") (pintype "passive"))
      (node (ref "CPU1") (pin "62") (pinfunction "VCC_62") (pintype "passive"))
      (node (ref "CPU1") (pin "69") (pinfunction "VCC_69") (pintype "passive"))
      (node (ref "CPU1") (pin "7") (pinfunction "BS16#_7") (pintype "passive"))
      (node (ref "CPU1") (pin "77") (pinfunction "VCC_77") (pintype "passive"))
      (node (ref "CPU1") (pin "8") (pinfunction "BS8#_8") (pintype "passive"))
      (node (ref "CPU1") (pin "80") (pinfunction "VCC_80") (pintype "passive"))
      (node (ref "CPU1") (pin "82") (pinfunction "VCC_82") (pintype "passive"))
      (node (ref "CPU1") (pin "86") (pinfunction "VCC_86") (pintype "passive"))
      (node (ref "CPU1") (pin "89") (pinfunction "VCC_89") (pintype "passive"))
      (node (ref "CPU1") (pin "9") (pinfunction "VCC_9") (pintype "passive"))
      (node (ref "CPU1") (pin "95") (pinfunction "VCC_95") (pintype "passive"))
      (node (ref "CPU1") (pin "98") (pinfunction "VCC_98") (pintype "passive"))
      (node (ref "Q1") (pin "1") (pinfunction "E_1") (pintype "passive"))
      (node (ref "R31") (pin "1") (pinfunction "1_1") (pintype "passive"))
      (node (ref "R70") (pin "2") (pinfunction "2_2") (pintype "passive"))
      (node (ref "R71") (pin "2") (pinfunction "2_2") (pintype "passive"))
      (node (ref "R73") (pin "2") (pinfunction "2_2") (pintype "passive"))
      (node (ref "R74") (pin "2") (pinfunction "2_2") (pintype "passive"))
      (node (ref "RP212") (pin "2") (pinfunction "2_2") (pintype "passive"))
      (node (ref "RP213") (pin "2") (pinfunction "2_2") (pintype "passive"))
      (node (ref "RP214") (pin "2") (pinfunction "2_2") (pintype "passive"))
      (node (ref "RP221") (pin "2") (pinfunction "2_2") (pintype "passive"))
      (node (ref "RP222") (pin "2") (pinfunction "2_2") (pintype "passive"))
      (node (ref "RP223") (pin "2") (pinfunction "2_2") (pintype "passive"))
      (node (ref "RP224") (pin "2") (pinfunction "2_2") (pintype "passive"))
    )
    (net (code "471") (name "unconnected-(CN1-Pad3)") (class "Default")
      (node (ref "CN1") (pin "3") (pinfunction "3_3") (pintype "passive"))
    )
    (net (code "472") (name "unconnected-(CPU1-BLAST#-Pad204)") (class "Default")
      (node (ref "CPU1") (pin "204") (pinfunction "BLAST#_204") (pintype "passive"))
    )
    (net (code "473") (name "unconnected-(CPU1-BREQ-Pad30)") (class "Default")
      (node (ref "CPU1") (pin "30") (pinfunction "BREQ_30") (pintype "passive"))
    )
    (net (code "474") (name "unconnected-(CPU1-DP0-Pad145)") (class "Default")
      (node (ref "CPU1") (pin "145") (pinfunction "DP0_145") (pintype "passive"))
    )
    (net (code "475") (name "unconnected-(CPU1-DP1-Pad125)") (class "Default")
      (node (ref "CPU1") (pin "125") (pinfunction "DP1_125") (pintype "passive"))
    )
    (net (code "476") (name "unconnected-(CPU1-DP2-Pad109)") (class "Default")
      (node (ref "CPU1") (pin "109") (pinfunction "DP2_109") (pintype "passive"))
    )
    (net (code "477") (name "unconnected-(CPU1-DP3-Pad90)") (class "Default")
      (node (ref "CPU1") (pin "90") (pinfunction "DP3_90") (pintype "passive"))
    )
    (net (code "478") (name "unconnected-(CPU1-HLDA-Pad26)") (class "Default")
      (node (ref "CPU1") (pin "26") (pinfunction "HLDA_26") (pintype "passive"))
    )
    (net (code "479") (name "unconnected-(CPU1-INC-Pad3)") (class "Default")
      (node (ref "CPU1") (pin "3") (pinfunction "INC_3") (pintype "passive"))
    )
    (net (code "480") (name "unconnected-(CPU1-INC-Pad67)") (class "Default")
      (node (ref "CPU1") (pin "67") (pinfunction "INC_67") (pintype "passive"))
    )
    (net (code "481") (name "unconnected-(CPU1-INC-Pad96)") (class "Default")
      (node (ref "CPU1") (pin "96") (pinfunction "INC_96") (pintype "passive"))
    )
    (net (code "482") (name "unconnected-(CPU1-INC-Pad127)") (class "Default")
      (node (ref "CPU1") (pin "127") (pinfunction "INC_127") (pintype "passive"))
    )
    (net (code "483") (name "unconnected-(CPU1-PCHK#-Pad4)") (class "Default")
      (node (ref "CPU1") (pin "4") (pinfunction "PCHK#_4") (pintype "passive"))
    )
    (net (code "484") (name "unconnected-(CPU1-PLOCK#-Pad206)") (class "Default")
      (node (ref "CPU1") (pin "206") (pinfunction "PLOCK#_206") (pintype "passive"))
    )
    (net (code "485") (name "unconnected-(CPU1-PWT-Pad40)") (class "Default")
      (node (ref "CPU1") (pin "40") (pinfunction "PWT_40") (pintype "passive"))
    )
    (net (code "486") (name "unconnected-(CPU1-TCK-Pad18)") (class "Default")
      (node (ref "CPU1") (pin "18") (pinfunction "TCK_18") (pintype "passive"))
    )
    (net (code "487") (name "unconnected-(CPU1-TDI-Pad168)") (class "Default")
      (node (ref "CPU1") (pin "168") (pinfunction "TDI_168") (pintype "passive"))
    )
    (net (code "488") (name "unconnected-(CPU1-TDO-Pad68)") (class "Default")
      (node (ref "CPU1") (pin "68") (pinfunction "TDO_68") (pintype "passive"))
    )
    (net (code "489") (name "unconnected-(CPU1-TMS-Pad167)") (class "Default")
      (node (ref "CPU1") (pin "167") (pinfunction "TMS_167") (pintype "passive"))
    )
    (net (code "490") (name "unconnected-(CPU1-UP#-Pad194)") (class "Default")
      (node (ref "CPU1") (pin "194") (pinfunction "UP#_194") (pintype "passive"))
    )
    (net (code "491") (name "unconnected-(CT1-Pad0)") (class "Default")
      (node (ref "CT1") (pin "0") (pinfunction "0_0") (pintype "passive"))
    )
    (net (code "492") (name "unconnected-(CT1-Pad1)") (class "Default")
      (node (ref "CT1") (pin "1") (pinfunction "1_1") (pintype "passive"))
    )
    (net (code "493") (name "unconnected-(CT1-Pad12)") (class "Default")
      (node (ref "CT1") (pin "12") (pinfunction "12_12") (pintype "passive"))
    )
    (net (code "494") (name "unconnected-(CT1-Pad40)") (class "Default")
      (node (ref "CT1") (pin "40") (pinfunction "40_40") (pintype "passive"))
    )
    (net (code "495") (name "unconnected-(CT1-Pad51)") (class "Default")
      (node (ref "CT1") (pin "51") (pinfunction "51_51") (pintype "passive"))
    )
    (net (code "496") (name "unconnected-(CT2-Pad0)") (class "Default")
      (node (ref "CT2") (pin "0") (pinfunction "0_0") (pintype "passive"))
    )
    (net (code "497") (name "unconnected-(IDE1-DMARQ-Pad21)") (class "Default")
      (node (ref "IDE1") (pin "21") (pinfunction "DMARQ_21") (pintype "passive"))
    )
    (net (code "498") (name "unconnected-(IDE1-Passed_diagnostics-Pad34)") (class "Default")
      (node (ref "IDE1") (pin "34") (pinfunction "Passed_diagnostics_34") (pintype "passive"))
    )
    (net (code "499") (name "unconnected-(IDE1-~{DMAACK}-Pad29)") (class "Default")
      (node (ref "IDE1") (pin "29") (pinfunction "~{DMAACK}_29") (pintype "passive"))
    )
    (net (code "500") (name "unconnected-(IDE2-DMARQ-Pad21)") (class "Default")
      (node (ref "IDE2") (pin "21") (pinfunction "DMARQ_21") (pintype "passive"))
    )
    (net (code "501") (name "unconnected-(IDE2-Passed_diagnostics-Pad34)") (class "Default")
      (node (ref "IDE2") (pin "34") (pinfunction "Passed_diagnostics_34") (pintype "passive"))
    )
    (net (code "502") (name "unconnected-(IDE2-~{DMAACK}-Pad29)") (class "Default")
      (node (ref "IDE2") (pin "29") (pinfunction "~{DMAACK}_29") (pintype "passive"))
    )
    (net (code "503") (name "unconnected-(ISA1--5V-PadB05)") (class "Default")
      (node (ref "ISA1") (pin "B05") (pinfunction "-5V_B05") (pintype "passive"))
    )
    (net (code "504") (name "unconnected-(ISA2--5V-PadB05)") (class "Default")
      (node (ref "ISA2") (pin "B05") (pinfunction "-5V_B05") (pintype "passive"))
    )
    (net (code "505") (name "unconnected-(ISA3--5V-PadB05)") (class "Default")
      (node (ref "ISA3") (pin "B05") (pinfunction "-5V_B05") (pintype "passive"))
    )
    (net (code "506") (name "unconnected-(K1-Pad3)") (class "Default")
      (node (ref "K1") (pin "3") (pinfunction "3_3") (pintype "passive"))
    )
    (net (code "507") (name "unconnected-(K1-Pad4)") (class "Default")
      (node (ref "K1") (pin "4") (pinfunction "4_4") (pintype "passive"))
    )
    (net (code "508") (name "unconnected-(M1-NC-Pad11)") (class "Default")
      (node (ref "M1") (pin "11") (pinfunction "NC_11") (pintype "passive"))
    )
    (net (code "509") (name "unconnected-(M1-NC-Pad48)") (class "Default")
      (node (ref "M1") (pin "48") (pinfunction "NC_48") (pintype "passive"))
    )
    (net (code "510") (name "unconnected-(M1-NC-Pad66)") (class "Default")
      (node (ref "M1") (pin "66") (pinfunction "NC_66") (pintype "passive"))
    )
    (net (code "511") (name "unconnected-(M1-NC-Pad71)") (class "Default")
      (node (ref "M1") (pin "71") (pinfunction "NC_71") (pintype "passive"))
    )
    (net (code "512") (name "unconnected-(M1-PD1-Pad67)") (class "Default")
      (node (ref "M1") (pin "67") (pinfunction "PD1_67") (pintype "passive"))
    )
    (net (code "513") (name "unconnected-(M1-PD2-Pad68)") (class "Default")
      (node (ref "M1") (pin "68") (pinfunction "PD2_68") (pintype "passive"))
    )
    (net (code "514") (name "unconnected-(M1-PD3-Pad69)") (class "Default")
      (node (ref "M1") (pin "69") (pinfunction "PD3_69") (pintype "passive"))
    )
    (net (code "515") (name "unconnected-(M1-PD4-Pad70)") (class "Default")
      (node (ref "M1") (pin "70") (pinfunction "PD4_70") (pintype "passive"))
    )
    (net (code "516") (name "unconnected-(M1-PQ1(NC)-Pad36)") (class "Default")
      (node (ref "M1") (pin "36") (pinfunction "PQ1(NC)_36") (pintype "passive"))
    )
    (net (code "517") (name "unconnected-(M1-PQ2(NC)-Pad37)") (class "Default")
      (node (ref "M1") (pin "37") (pinfunction "PQ2(NC)_37") (pintype "passive"))
    )
    (net (code "518") (name "unconnected-(M1-PQ3(NC)-Pad35)") (class "Default")
      (node (ref "M1") (pin "35") (pinfunction "PQ3(NC)_35") (pintype "passive"))
    )
    (net (code "519") (name "unconnected-(M1-PQ4(NC)-Pad38)") (class "Default")
      (node (ref "M1") (pin "38") (pinfunction "PQ4(NC)_38") (pintype "passive"))
    )
    (net (code "520") (name "unconnected-(M2-NC-Pad11)") (class "Default")
      (node (ref "M2") (pin "11") (pinfunction "NC_11") (pintype "passive"))
    )
    (net (code "521") (name "unconnected-(M2-NC-Pad48)") (class "Default")
      (node (ref "M2") (pin "48") (pinfunction "NC_48") (pintype "passive"))
    )
    (net (code "522") (name "unconnected-(M2-NC-Pad66)") (class "Default")
      (node (ref "M2") (pin "66") (pinfunction "NC_66") (pintype "passive"))
    )
    (net (code "523") (name "unconnected-(M2-NC-Pad71)") (class "Default")
      (node (ref "M2") (pin "71") (pinfunction "NC_71") (pintype "passive"))
    )
    (net (code "524") (name "unconnected-(M2-PD1-Pad67)") (class "Default")
      (node (ref "M2") (pin "67") (pinfunction "PD1_67") (pintype "passive"))
    )
    (net (code "525") (name "unconnected-(M2-PD2-Pad68)") (class "Default")
      (node (ref "M2") (pin "68") (pinfunction "PD2_68") (pintype "passive"))
    )
    (net (code "526") (name "unconnected-(M2-PD3-Pad69)") (class "Default")
      (node (ref "M2") (pin "69") (pinfunction "PD3_69") (pintype "passive"))
    )
    (net (code "527") (name "unconnected-(M2-PD4-Pad70)") (class "Default")
      (node (ref "M2") (pin "70") (pinfunction "PD4_70") (pintype "passive"))
    )
    (net (code "528") (name "unconnected-(M2-PQ1(NC)-Pad36)") (class "Default")
      (node (ref "M2") (pin "36") (pinfunction "PQ1(NC)_36") (pintype "passive"))
    )
    (net (code "529") (name "unconnected-(M2-PQ2(NC)-Pad37)") (class "Default")
      (node (ref "M2") (pin "37") (pinfunction "PQ2(NC)_37") (pintype "passive"))
    )
    (net (code "530") (name "unconnected-(M2-PQ3(NC)-Pad35)") (class "Default")
      (node (ref "M2") (pin "35") (pinfunction "PQ3(NC)_35") (pintype "passive"))
    )
    (net (code "531") (name "unconnected-(M2-PQ4(NC)-Pad38)") (class "Default")
      (node (ref "M2") (pin "38") (pinfunction "PQ4(NC)_38") (pintype "passive"))
    )
    (net (code "532") (name "unconnected-(M3-NC-Pad11)") (class "Default")
      (node (ref "M3") (pin "11") (pinfunction "NC_11") (pintype "passive"))
    )
    (net (code "533") (name "unconnected-(M3-NC-Pad48)") (class "Default")
      (node (ref "M3") (pin "48") (pinfunction "NC_48") (pintype "passive"))
    )
    (net (code "534") (name "unconnected-(M3-NC-Pad66)") (class "Default")
      (node (ref "M3") (pin "66") (pinfunction "NC_66") (pintype "passive"))
    )
    (net (code "535") (name "unconnected-(M3-NC-Pad71)") (class "Default")
      (node (ref "M3") (pin "71") (pinfunction "NC_71") (pintype "passive"))
    )
    (net (code "536") (name "unconnected-(M3-PD1-Pad67)") (class "Default")
      (node (ref "M3") (pin "67") (pinfunction "PD1_67") (pintype "passive"))
    )
    (net (code "537") (name "unconnected-(M3-PD2-Pad68)") (class "Default")
      (node (ref "M3") (pin "68") (pinfunction "PD2_68") (pintype "passive"))
    )
    (net (code "538") (name "unconnected-(M3-PD3-Pad69)") (class "Default")
      (node (ref "M3") (pin "69") (pinfunction "PD3_69") (pintype "passive"))
    )
    (net (code "539") (name "unconnected-(M3-PD4-Pad70)") (class "Default")
      (node (ref "M3") (pin "70") (pinfunction "PD4_70") (pintype "passive"))
    )
    (net (code "540") (name "unconnected-(M3-PQ1(NC)-Pad36)") (class "Default")
      (node (ref "M3") (pin "36") (pinfunction "PQ1(NC)_36") (pintype "passive"))
    )
    (net (code "541") (name "unconnected-(M3-PQ2(NC)-Pad37)") (class "Default")
      (node (ref "M3") (pin "37") (pinfunction "PQ2(NC)_37") (pintype "passive"))
    )
    (net (code "542") (name "unconnected-(M3-PQ3(NC)-Pad35)") (class "Default")
      (node (ref "M3") (pin "35") (pinfunction "PQ3(NC)_35") (pintype "passive"))
    )
    (net (code "543") (name "unconnected-(M3-PQ4(NC)-Pad38)") (class "Default")
      (node (ref "M3") (pin "38") (pinfunction "PQ4(NC)_38") (pintype "passive"))
    )
    (net (code "544") (name "unconnected-(M4-NC-Pad11)") (class "Default")
      (node (ref "M4") (pin "11") (pinfunction "NC_11") (pintype "passive"))
    )
    (net (code "545") (name "unconnected-(M4-NC-Pad48)") (class "Default")
      (node (ref "M4") (pin "48") (pinfunction "NC_48") (pintype "passive"))
    )
    (net (code "546") (name "unconnected-(M4-NC-Pad66)") (class "Default")
      (node (ref "M4") (pin "66") (pinfunction "NC_66") (pintype "passive"))
    )
    (net (code "547") (name "unconnected-(M4-NC-Pad71)") (class "Default")
      (node (ref "M4") (pin "71") (pinfunction "NC_71") (pintype "passive"))
    )
    (net (code "548") (name "unconnected-(M4-PD1-Pad67)") (class "Default")
      (node (ref "M4") (pin "67") (pinfunction "PD1_67") (pintype "passive"))
    )
    (net (code "549") (name "unconnected-(M4-PD2-Pad68)") (class "Default")
      (node (ref "M4") (pin "68") (pinfunction "PD2_68") (pintype "passive"))
    )
    (net (code "550") (name "unconnected-(M4-PD3-Pad69)") (class "Default")
      (node (ref "M4") (pin "69") (pinfunction "PD3_69") (pintype "passive"))
    )
    (net (code "551") (name "unconnected-(M4-PD4-Pad70)") (class "Default")
      (node (ref "M4") (pin "70") (pinfunction "PD4_70") (pintype "passive"))
    )
    (net (code "552") (name "unconnected-(M4-PQ1(NC)-Pad36)") (class "Default")
      (node (ref "M4") (pin "36") (pinfunction "PQ1(NC)_36") (pintype "passive"))
    )
    (net (code "553") (name "unconnected-(M4-PQ2(NC)-Pad37)") (class "Default")
      (node (ref "M4") (pin "37") (pinfunction "PQ2(NC)_37") (pintype "passive"))
    )
    (net (code "554") (name "unconnected-(M4-PQ3(NC)-Pad35)") (class "Default")
      (node (ref "M4") (pin "35") (pinfunction "PQ3(NC)_35") (pintype "passive"))
    )
    (net (code "555") (name "unconnected-(M4-PQ4(NC)-Pad38)") (class "Default")
      (node (ref "M4") (pin "38") (pinfunction "PQ4(NC)_38") (pintype "passive"))
    )
    (net (code "556") (name "unconnected-(P1-VO+-Pad1)") (class "Default")
      (node (ref "P1") (pin "1") (pinfunction "VO+_1") (pintype "passive"))
    )
    (net (code "557") (name "unconnected-(PCI0-Reserved-PadA9)") (class "Default")
      (node (ref "PCI0") (pin "A9") (pinfunction "Reserved_A9") (pintype "passive"))
    )
    (net (code "558") (name "unconnected-(PCI0-Reserved-PadA11)") (class "Default")
      (node (ref "PCI0") (pin "A11") (pinfunction "Reserved_A11") (pintype "passive"))
    )
    (net (code "559") (name "unconnected-(PCI0-Reserved-PadB10)") (class "Default")
      (node (ref "PCI0") (pin "B10") (pinfunction "Reserved_B10") (pintype "passive"))
    )
    (net (code "560") (name "unconnected-(PCI0-Reserved-PadB14)") (class "Default")
      (node (ref "PCI0") (pin "B14") (pinfunction "Reserved_B14") (pintype "passive"))
    )
    (net (code "561") (name "unconnected-(PCI0-SBO#-PadA41)") (class "Default")
      (node (ref "PCI0") (pin "A41") (pinfunction "SBO#_A41") (pintype "passive"))
    )
    (net (code "562") (name "unconnected-(PCI0-SDONE-PadA40)") (class "Default")
      (node (ref "PCI0") (pin "A40") (pinfunction "SDONE_A40") (pintype "passive"))
    )
    (net (code "563") (name "unconnected-(PCI0-TCK-PadB2)") (class "Default")
      (node (ref "PCI0") (pin "B2") (pinfunction "TCK_B2") (pintype "passive"))
    )
    (net (code "564") (name "unconnected-(PCI0-TDI-PadA4)") (class "Default")
      (node (ref "PCI0") (pin "A4") (pinfunction "TDI_A4") (pintype "passive"))
    )
    (net (code "565") (name "unconnected-(PCI0-TDO-PadB4)") (class "Default")
      (node (ref "PCI0") (pin "B4") (pinfunction "TDO_B4") (pintype "passive"))
    )
    (net (code "566") (name "unconnected-(PCI0-TMS-PadA3)") (class "Default")
      (node (ref "PCI0") (pin "A3") (pinfunction "TMS_A3") (pintype "passive"))
    )
    (net (code "567") (name "unconnected-(PCI0-~{ACK64}-PadB60)") (class "Default")
      (node (ref "PCI0") (pin "B60") (pinfunction "~{ACK64}_B60") (pintype "passive"))
    )
    (net (code "568") (name "unconnected-(PCI0-~{LOCK}-PadB39)") (class "Default")
      (node (ref "PCI0") (pin "B39") (pinfunction "~{LOCK}_B39") (pintype "passive"))
    )
    (net (code "569") (name "unconnected-(PCI0-~{PME}-PadA19)") (class "Default")
      (node (ref "PCI0") (pin "A19") (pinfunction "~{PME}_A19") (pintype "passive"))
    )
    (net (code "570") (name "unconnected-(PCI0-~{PRSTN1}-PadB9)") (class "Default")
      (node (ref "PCI0") (pin "B9") (pinfunction "~{PRSTN1}_B9") (pintype "passive"))
    )
    (net (code "571") (name "unconnected-(PCI0-~{PRST}N~{2}-PadB11)") (class "Default")
      (node (ref "PCI0") (pin "B11") (pinfunction "~{PRST}N~{2}_B11") (pintype "passive"))
    )
    (net (code "572") (name "unconnected-(PCI0-~{REQ64}-PadA60)") (class "Default")
      (node (ref "PCI0") (pin "A60") (pinfunction "~{REQ64}_A60") (pintype "passive"))
    )
    (net (code "573") (name "unconnected-(PCI0-~{TRST}-PadA1)") (class "Default")
      (node (ref "PCI0") (pin "A1") (pinfunction "~{TRST}_A1") (pintype "passive"))
    )
    (net (code "574") (name "unconnected-(PCI1-Reserved-PadA9)") (class "Default")
      (node (ref "PCI1") (pin "A9") (pinfunction "Reserved_A9") (pintype "passive"))
    )
    (net (code "575") (name "unconnected-(PCI1-Reserved-PadA11)") (class "Default")
      (node (ref "PCI1") (pin "A11") (pinfunction "Reserved_A11") (pintype "passive"))
    )
    (net (code "576") (name "unconnected-(PCI1-Reserved-PadB10)") (class "Default")
      (node (ref "PCI1") (pin "B10") (pinfunction "Reserved_B10") (pintype "passive"))
    )
    (net (code "577") (name "unconnected-(PCI1-Reserved-PadB14)") (class "Default")
      (node (ref "PCI1") (pin "B14") (pinfunction "Reserved_B14") (pintype "passive"))
    )
    (net (code "578") (name "unconnected-(PCI1-SBO#-PadA41)") (class "Default")
      (node (ref "PCI1") (pin "A41") (pinfunction "SBO#_A41") (pintype "passive"))
    )
    (net (code "579") (name "unconnected-(PCI1-SDONE-PadA40)") (class "Default")
      (node (ref "PCI1") (pin "A40") (pinfunction "SDONE_A40") (pintype "passive"))
    )
    (net (code "580") (name "unconnected-(PCI1-TCK-PadB2)") (class "Default")
      (node (ref "PCI1") (pin "B2") (pinfunction "TCK_B2") (pintype "passive"))
    )
    (net (code "581") (name "unconnected-(PCI1-TDI-PadA4)") (class "Default")
      (node (ref "PCI1") (pin "A4") (pinfunction "TDI_A4") (pintype "passive"))
    )
    (net (code "582") (name "unconnected-(PCI1-TDO-PadB4)") (class "Default")
      (node (ref "PCI1") (pin "B4") (pinfunction "TDO_B4") (pintype "passive"))
    )
    (net (code "583") (name "unconnected-(PCI1-TMS-PadA3)") (class "Default")
      (node (ref "PCI1") (pin "A3") (pinfunction "TMS_A3") (pintype "passive"))
    )
    (net (code "584") (name "unconnected-(PCI1-~{ACK64}-PadB60)") (class "Default")
      (node (ref "PCI1") (pin "B60") (pinfunction "~{ACK64}_B60") (pintype "passive"))
    )
    (net (code "585") (name "unconnected-(PCI1-~{LOCK}-PadB39)") (class "Default")
      (node (ref "PCI1") (pin "B39") (pinfunction "~{LOCK}_B39") (pintype "passive"))
    )
    (net (code "586") (name "unconnected-(PCI1-~{PME}-PadA19)") (class "Default")
      (node (ref "PCI1") (pin "A19") (pinfunction "~{PME}_A19") (pintype "passive"))
    )
    (net (code "587") (name "unconnected-(PCI1-~{PRSTN1}-PadB9)") (class "Default")
      (node (ref "PCI1") (pin "B9") (pinfunction "~{PRSTN1}_B9") (pintype "passive"))
    )
    (net (code "588") (name "unconnected-(PCI1-~{PRST}N~{2}-PadB11)") (class "Default")
      (node (ref "PCI1") (pin "B11") (pinfunction "~{PRST}N~{2}_B11") (pintype "passive"))
    )
    (net (code "589") (name "unconnected-(PCI1-~{REQ64}-PadA60)") (class "Default")
      (node (ref "PCI1") (pin "A60") (pinfunction "~{REQ64}_A60") (pintype "passive"))
    )
    (net (code "590") (name "unconnected-(PCI1-~{TRST}-PadA1)") (class "Default")
      (node (ref "PCI1") (pin "A1") (pinfunction "~{TRST}_A1") (pintype "passive"))
    )
    (net (code "591") (name "unconnected-(PCI2-Reserved-PadA9)") (class "Default")
      (node (ref "PCI2") (pin "A9") (pinfunction "Reserved_A9") (pintype "passive"))
    )
    (net (code "592") (name "unconnected-(PCI2-Reserved-PadA11)") (class "Default")
      (node (ref "PCI2") (pin "A11") (pinfunction "Reserved_A11") (pintype "passive"))
    )
    (net (code "593") (name "unconnected-(PCI2-Reserved-PadB10)") (class "Default")
      (node (ref "PCI2") (pin "B10") (pinfunction "Reserved_B10") (pintype "passive"))
    )
    (net (code "594") (name "unconnected-(PCI2-Reserved-PadB14)") (class "Default")
      (node (ref "PCI2") (pin "B14") (pinfunction "Reserved_B14") (pintype "passive"))
    )
    (net (code "595") (name "unconnected-(PCI2-SBO#-PadA41)") (class "Default")
      (node (ref "PCI2") (pin "A41") (pinfunction "SBO#_A41") (pintype "passive"))
    )
    (net (code "596") (name "unconnected-(PCI2-SDONE-PadA40)") (class "Default")
      (node (ref "PCI2") (pin "A40") (pinfunction "SDONE_A40") (pintype "passive"))
    )
    (net (code "597") (name "unconnected-(PCI2-TCK-PadB2)") (class "Default")
      (node (ref "PCI2") (pin "B2") (pinfunction "TCK_B2") (pintype "passive"))
    )
    (net (code "598") (name "unconnected-(PCI2-TDI-PadA4)") (class "Default")
      (node (ref "PCI2") (pin "A4") (pinfunction "TDI_A4") (pintype "passive"))
    )
    (net (code "599") (name "unconnected-(PCI2-TDO-PadB4)") (class "Default")
      (node (ref "PCI2") (pin "B4") (pinfunction "TDO_B4") (pintype "passive"))
    )
    (net (code "600") (name "unconnected-(PCI2-TMS-PadA3)") (class "Default")
      (node (ref "PCI2") (pin "A3") (pinfunction "TMS_A3") (pintype "passive"))
    )
    (net (code "601") (name "unconnected-(PCI2-~{ACK64}-PadB60)") (class "Default")
      (node (ref "PCI2") (pin "B60") (pinfunction "~{ACK64}_B60") (pintype "passive"))
    )
    (net (code "602") (name "unconnected-(PCI2-~{LOCK}-PadB39)") (class "Default")
      (node (ref "PCI2") (pin "B39") (pinfunction "~{LOCK}_B39") (pintype "passive"))
    )
    (net (code "603") (name "unconnected-(PCI2-~{PME}-PadA19)") (class "Default")
      (node (ref "PCI2") (pin "A19") (pinfunction "~{PME}_A19") (pintype "passive"))
    )
    (net (code "604") (name "unconnected-(PCI2-~{PRSTN1}-PadB9)") (class "Default")
      (node (ref "PCI2") (pin "B9") (pinfunction "~{PRSTN1}_B9") (pintype "passive"))
    )
    (net (code "605") (name "unconnected-(PCI2-~{PRST}N~{2}-PadB11)") (class "Default")
      (node (ref "PCI2") (pin "B11") (pinfunction "~{PRST}N~{2}_B11") (pintype "passive"))
    )
    (net (code "606") (name "unconnected-(PCI2-~{REQ64}-PadA60)") (class "Default")
      (node (ref "PCI2") (pin "A60") (pinfunction "~{REQ64}_A60") (pintype "passive"))
    )
    (net (code "607") (name "unconnected-(PCI2-~{TRST}-PadA1)") (class "Default")
      (node (ref "PCI2") (pin "A1") (pinfunction "~{TRST}_A1") (pintype "passive"))
    )
    (net (code "608") (name "unconnected-(S1-NC2-Pad4)") (class "Default")
      (node (ref "S1") (pin "4") (pinfunction "NC2_4") (pintype "passive"))
    )
    (net (code "609") (name "unconnected-(S1-NO1-Pad1)") (class "Default")
      (node (ref "S1") (pin "1") (pinfunction "NO1_1") (pintype "passive"))
    )
    (net (code "610") (name "unconnected-(SW1-Pad3)") (class "Default")
      (node (ref "SW1") (pin "3") (pinfunction "3_3") (pintype "passive"))
    )
    (net (code "611") (name "unconnected-(TFT1-3.3V-Pad6)") (class "Default")
      (node (ref "TFT1") (pin "6") (pinfunction "3.3V_6") (pintype "passive"))
    )
    (net (code "612") (name "unconnected-(TFT1-GND-Pad8)") (class "Default")
      (node (ref "TFT1") (pin "8") (pinfunction "GND_8") (pintype "passive"))
    )
    (net (code "613") (name "unconnected-(TFT1-LED-Pad7)") (class "Default")
      (node (ref "TFT1") (pin "7") (pinfunction "LED_7") (pintype "passive"))
    )
    (net (code "614") (name "unconnected-(TFT1-NC-Pad12)") (class "Default")
      (node (ref "TFT1") (pin "12") (pinfunction "NC_12") (pintype "passive"))
    )
    (net (code "615") (name "unconnected-(TFT1-NC-Pad13)") (class "Default")
      (node (ref "TFT1") (pin "13") (pinfunction "NC_13") (pintype "passive"))
    )
    (net (code "616") (name "unconnected-(TFT1-RS-Pad3)") (class "Default")
      (node (ref "TFT1") (pin "3") (pinfunction "RS_3") (pintype "passive"))
    )
    (net (code "617") (name "unconnected-(TFT1-RST-Pad1)") (class "Default")
      (node (ref "TFT1") (pin "1") (pinfunction "RST_1") (pintype "passive"))
    )
    (net (code "618") (name "unconnected-(TFT1-SCL-Pad5)") (class "Default")
      (node (ref "TFT1") (pin "5") (pinfunction "SCL_5") (pintype "passive"))
    )
    (net (code "619") (name "unconnected-(TFT1-SDA-Pad4)") (class "Default")
      (node (ref "TFT1") (pin "4") (pinfunction "SDA_4") (pintype "passive"))
    )
    (net (code "620") (name "unconnected-(TFT1-~{CS}-Pad2)") (class "Default")
      (node (ref "TFT1") (pin "2") (pinfunction "~{CS}_2") (pintype "passive"))
    )
    (net (code "621") (name "unconnected-(U7-1Y3-Pad14)") (class "Default")
      (node (ref "U7") (pin "14") (pinfunction "1Y3_14") (pintype "output"))
    )
    (net (code "622") (name "unconnected-(U7-1Y4-Pad12)") (class "Default")
      (node (ref "U7") (pin "12") (pinfunction "1Y4_12") (pintype "output"))
    )
    (net (code "623") (name "unconnected-(U7-2Y3-Pad5)") (class "Default")
      (node (ref "U7") (pin "5") (pinfunction "2Y3_5") (pintype "output"))
    )
    (net (code "624") (name "unconnected-(U15-Pad8)") (class "Default")
      (node (ref "U15") (pin "8") (pintype "output"))
    )
    (net (code "625") (name "unconnected-(U15-Pad10)") (class "Default")
      (node (ref "U15") (pin "10") (pintype "output"))
    )
    (net (code "626") (name "unconnected-(U15-Pad12)") (class "Default")
      (node (ref "U15") (pin "12") (pintype "output"))
    )
    (net (code "627") (name "unconnected-(U19-I3-Pad4)") (class "Default")
      (node (ref "U19") (pin "4") (pinfunction "I3_4") (pintype "passive"))
    )
    (net (code "628") (name "unconnected-(U19-I8-Pad9)") (class "Default")
      (node (ref "U19") (pin "9") (pinfunction "I8_9") (pintype "passive"))
    )
    (net (code "629") (name "unconnected-(U19-I{slash}O2-Pad18)") (class "Default")
      (node (ref "U19") (pin "18") (pinfunction "I/O2_18") (pintype "passive"))
    )
    (net (code "630") (name "unconnected-(U19-I{slash}O3-Pad17)") (class "Default")
      (node (ref "U19") (pin "17") (pinfunction "I/O3_17") (pintype "passive"))
    )
    (net (code "631") (name "unconnected-(U19-I{slash}O5-Pad15)") (class "Default")
      (node (ref "U19") (pin "15") (pinfunction "I/O5_15") (pintype "passive"))
    )
    (net (code "632") (name "unconnected-(U19-I{slash}O6-Pad14)") (class "Default")
      (node (ref "U19") (pin "14") (pinfunction "I/O6_14") (pintype "passive"))
    )
    (net (code "633") (name "unconnected-(U19-I{slash}O7-Pad13)") (class "Default")
      (node (ref "U19") (pin "13") (pinfunction "I/O7_13") (pintype "passive"))
    )
    (net (code "634") (name "unconnected-(U19-I{slash}O8-Pad12)") (class "Default")
      (node (ref "U19") (pin "12") (pinfunction "I/O8_12") (pintype "passive"))
    )
    (net (code "635") (name "unconnected-(UM9-CTS-Pad9)") (class "Default")
      (node (ref "UM9") (pin "9") (pinfunction "CTS_9") (pintype "passive"))
    )
    (net (code "636") (name "unconnected-(UM9-DCD#-Pad12)") (class "Default")
      (node (ref "UM9") (pin "12") (pinfunction "DCD#_12") (pintype "passive"))
    )
    (net (code "637") (name "unconnected-(UM9-DST-Pad10)") (class "Default")
      (node (ref "UM9") (pin "10") (pinfunction "DST_10") (pintype "passive"))
    )
    (net (code "638") (name "unconnected-(UM9-DTR-Pad13)") (class "Default")
      (node (ref "UM9") (pin "13") (pinfunction "DTR_13") (pintype "passive"))
    )
    (net (code "639") (name "unconnected-(UM9-R232-Pad15)") (class "Default")
      (node (ref "UM9") (pin "15") (pinfunction "R232_15") (pintype "passive"))
    )
    (net (code "640") (name "unconnected-(UM9-RI-Pad11)") (class "Default")
      (node (ref "UM9") (pin "11") (pinfunction "RI_11") (pintype "passive"))
    )
    (net (code "641") (name "unconnected-(UM9-RTS#-Pad14)") (class "Default")
      (node (ref "UM9") (pin "14") (pinfunction "RTS#_14") (pintype "passive"))
    )
    (net (code "642") (name "unconnected-(UM9-Xi-Pad7)") (class "Default")
      (node (ref "UM9") (pin "7") (pinfunction "Xi_7") (pintype "passive"))
    )
    (net (code "643") (name "unconnected-(UM9-Xo-Pad8)") (class "Default")
      (node (ref "UM9") (pin "8") (pinfunction "Xo_8") (pintype "passive"))
    )
    (net (code "644") (name "unconnected-(USB1-ID-Pad4)") (class "Default")
      (node (ref "USB1") (pin "4") (pinfunction "ID_4") (pintype "passive"))
    )
  )
)
